# WS2812B_ARRAY.net
KiCad netlist of a schematic drawn in Altium Designer
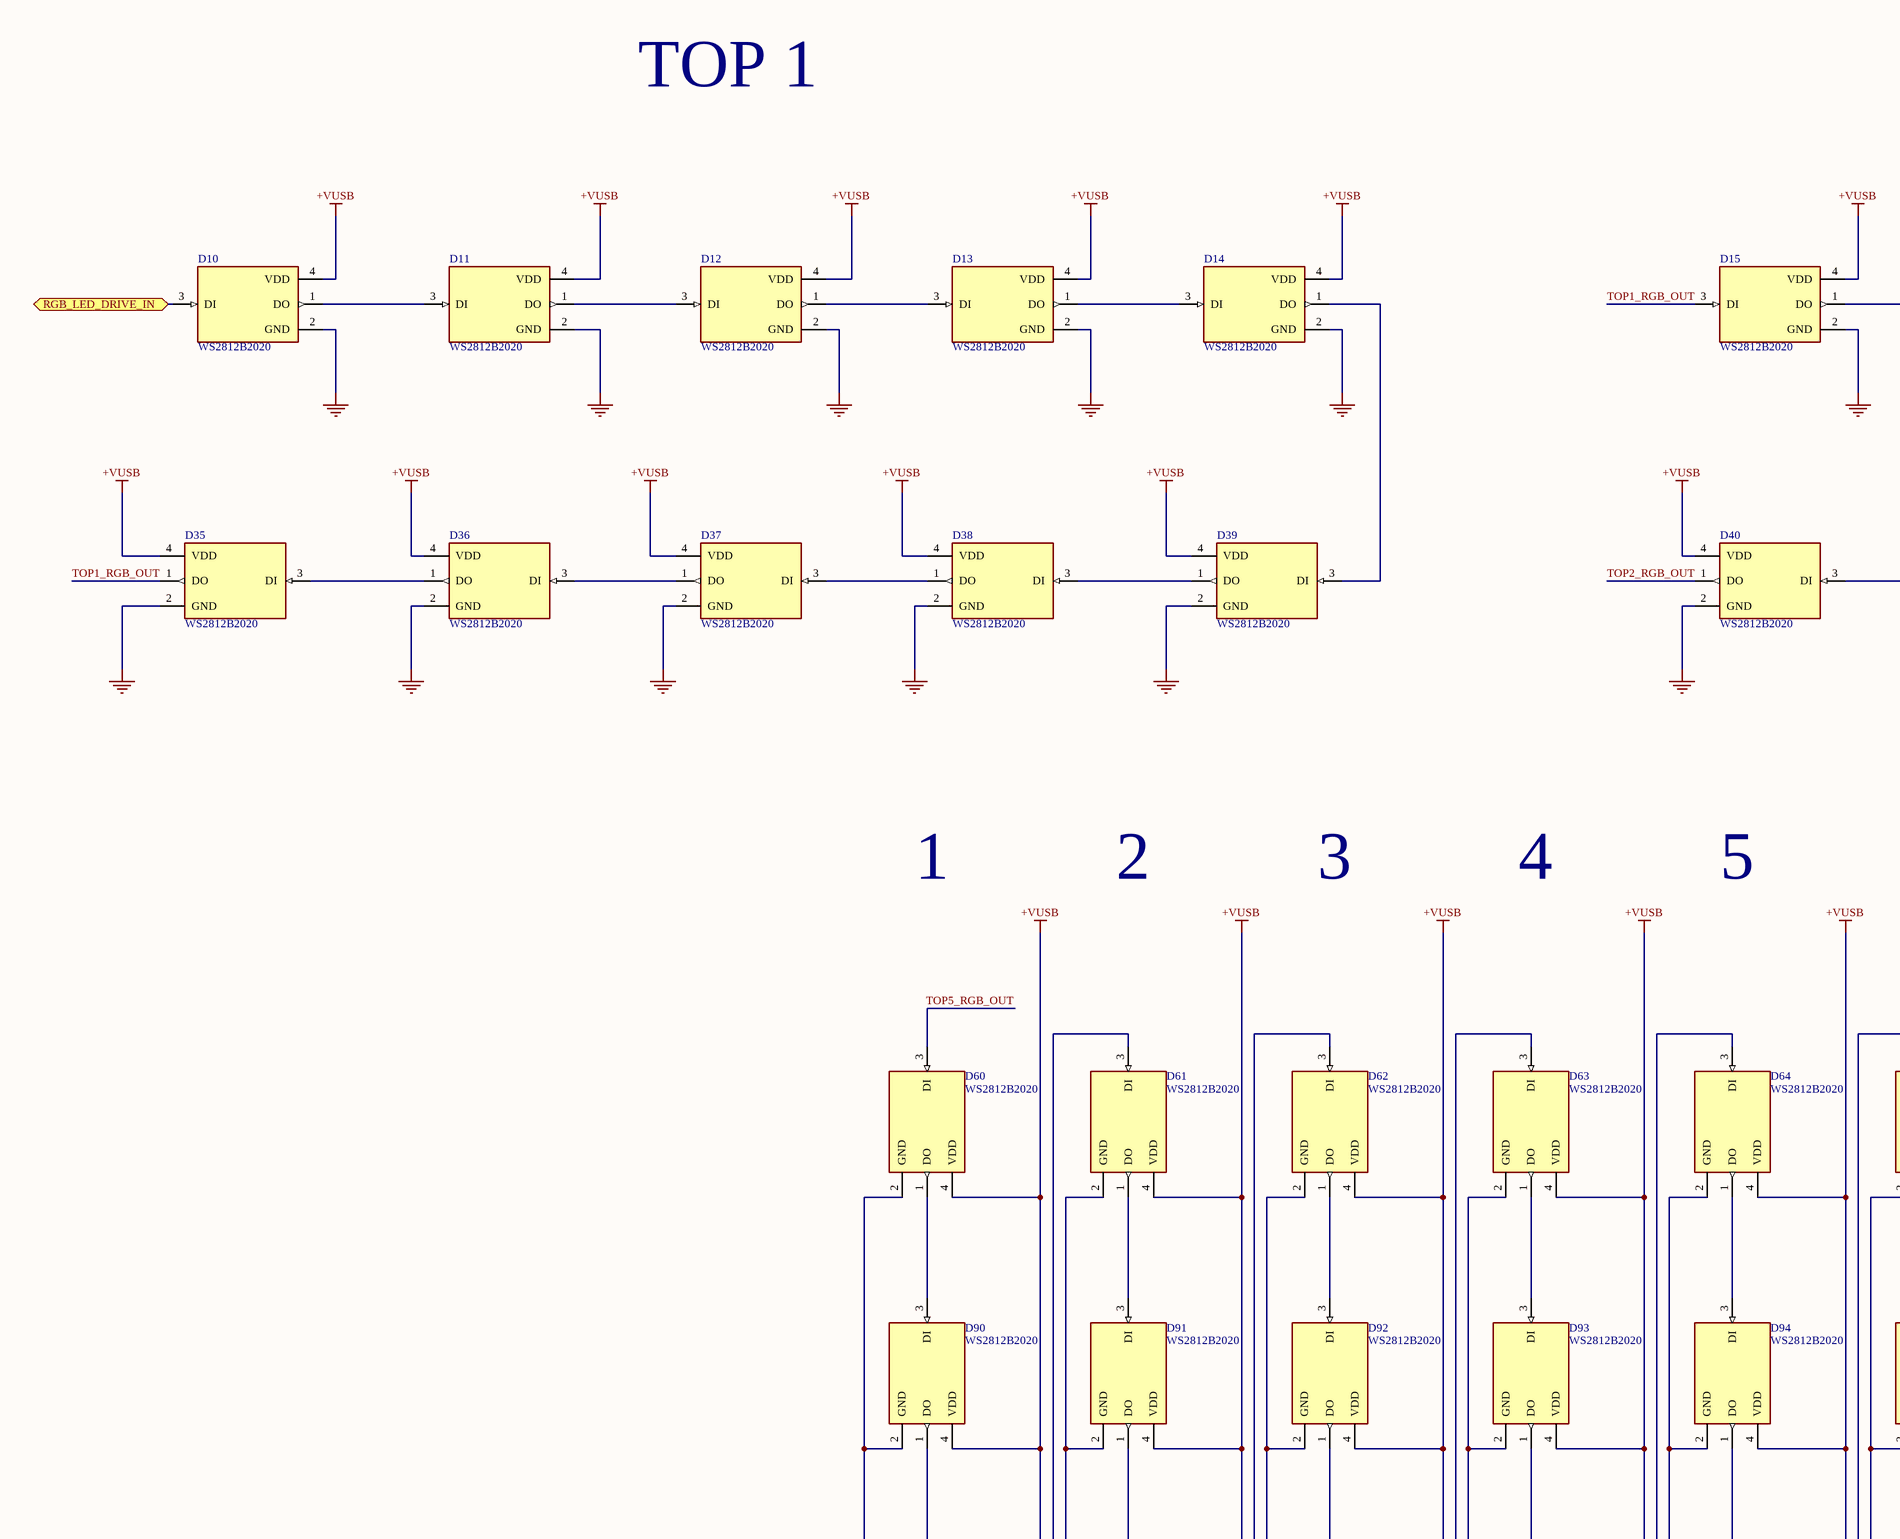
[diagram p0: WS2812B_ARRAY.SchDoc, top column 1 of 4]
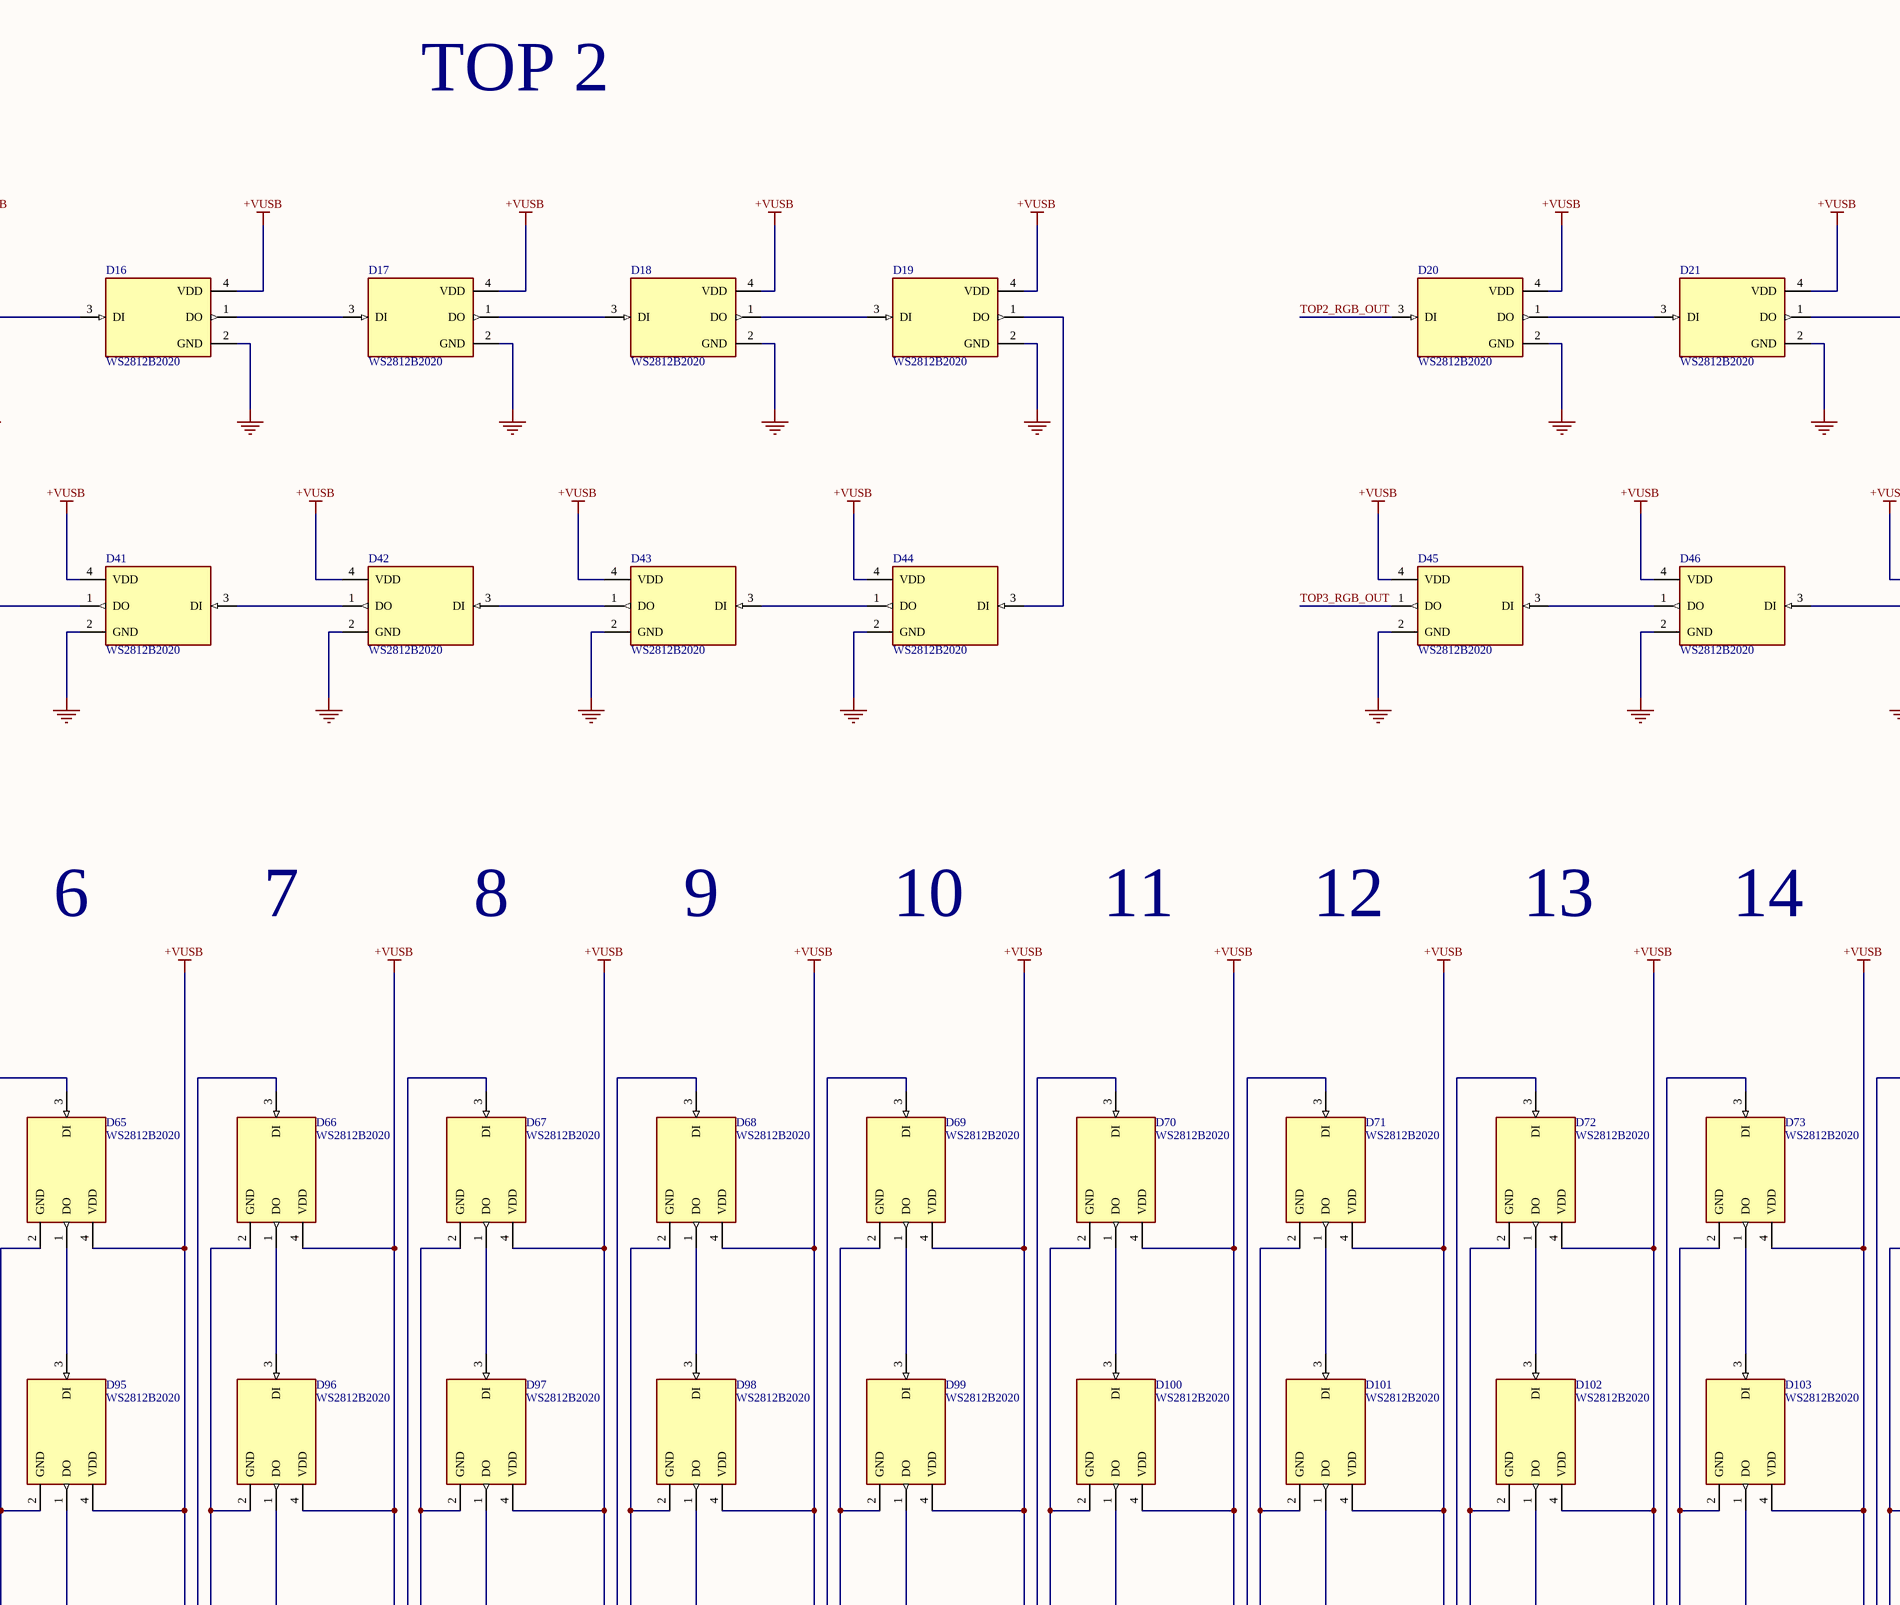
[diagram p1: WS2812B_ARRAY.SchDoc, top column 2 of 4]
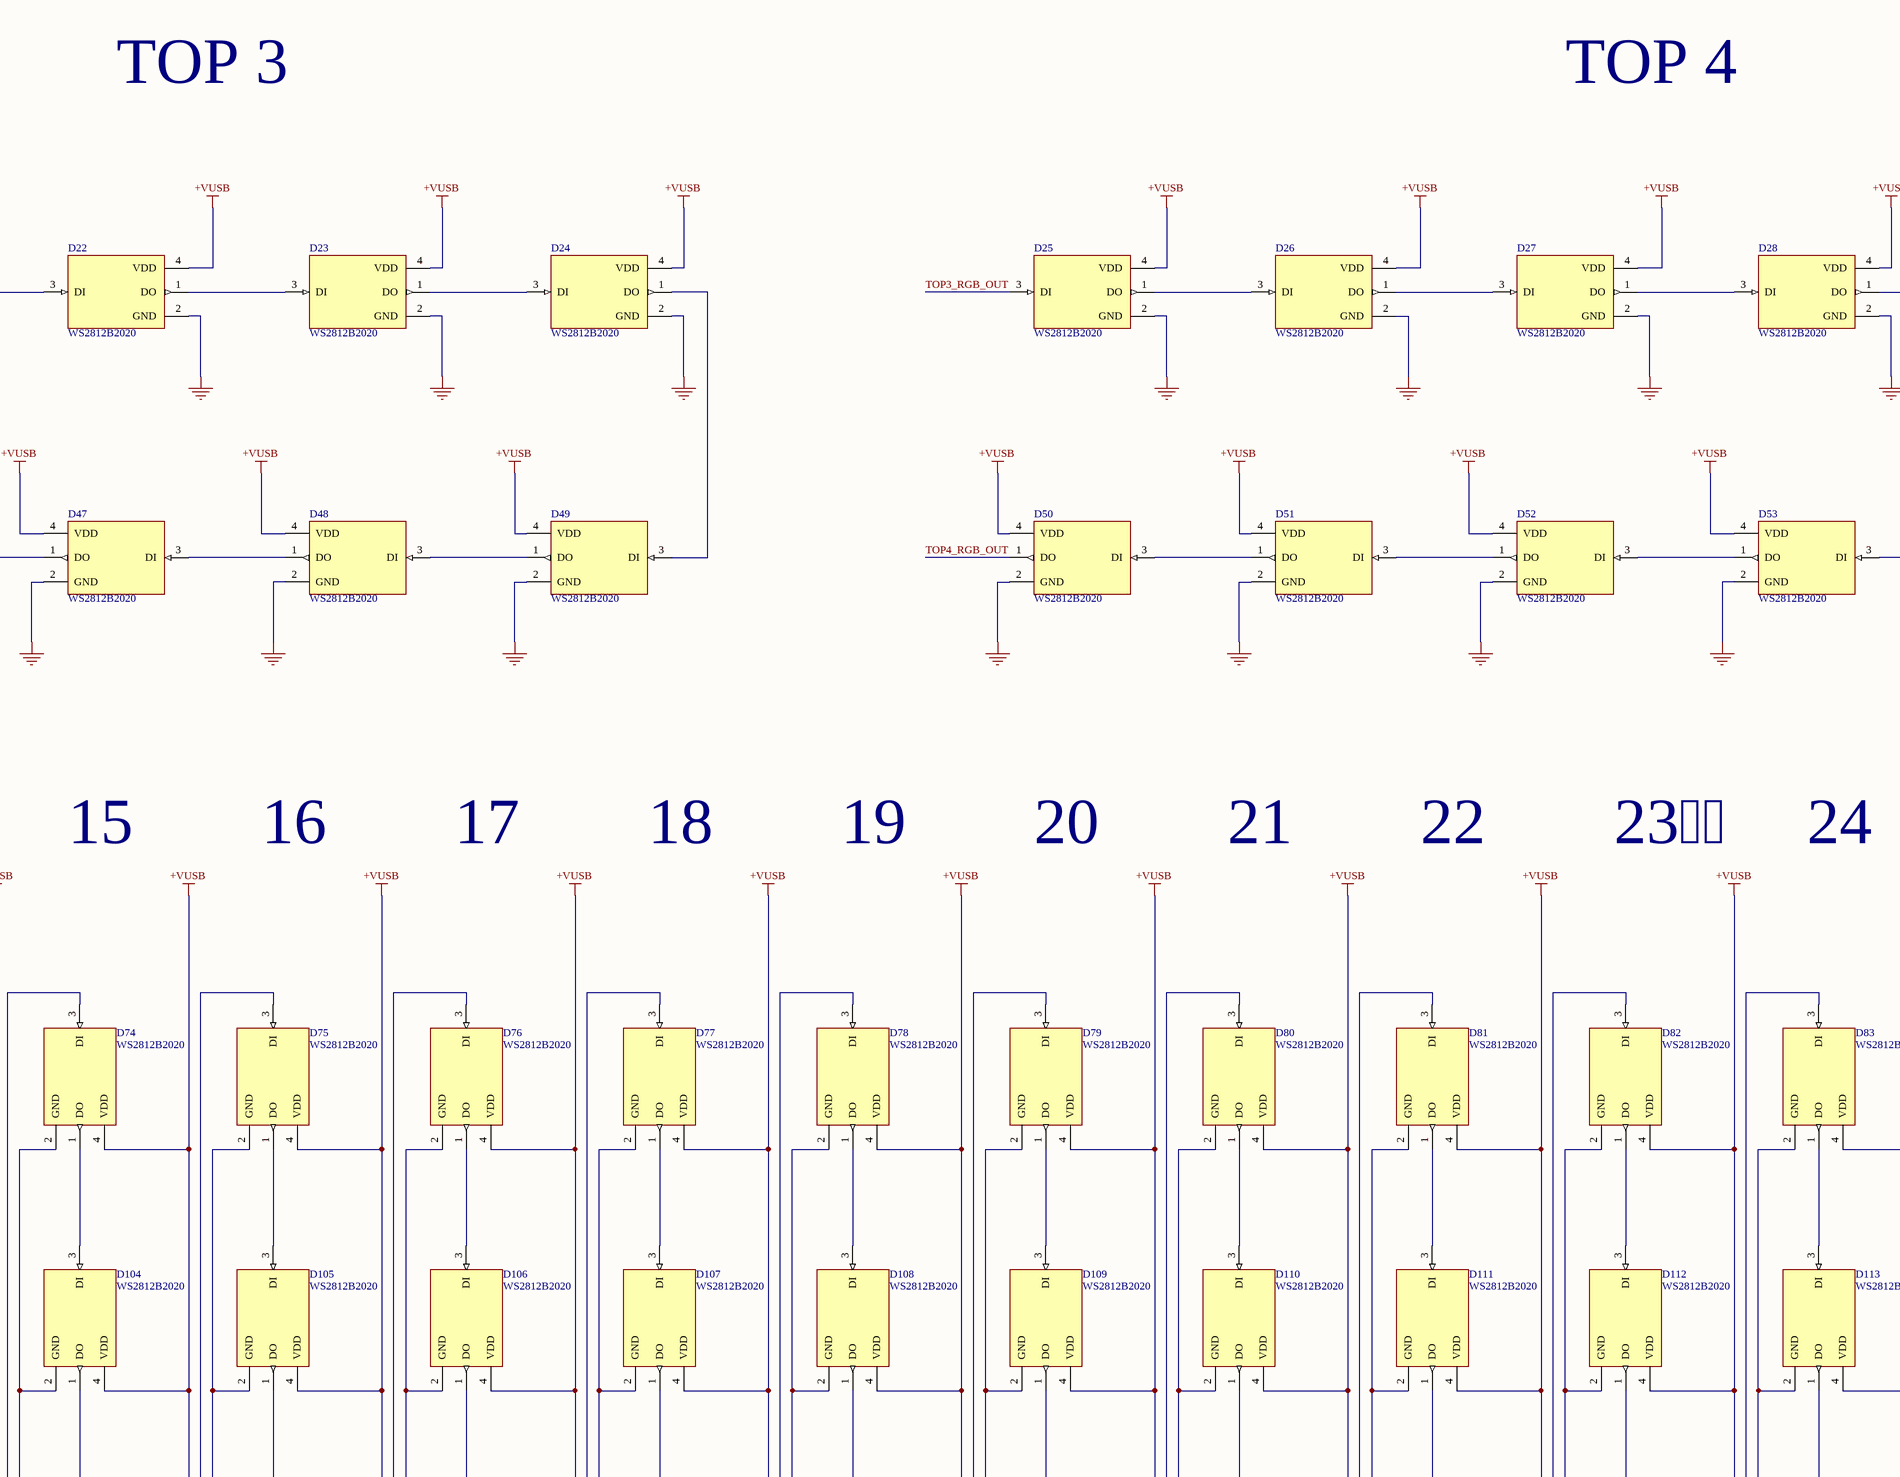
[diagram p2: WS2812B_ARRAY.SchDoc, top column 3 of 4]
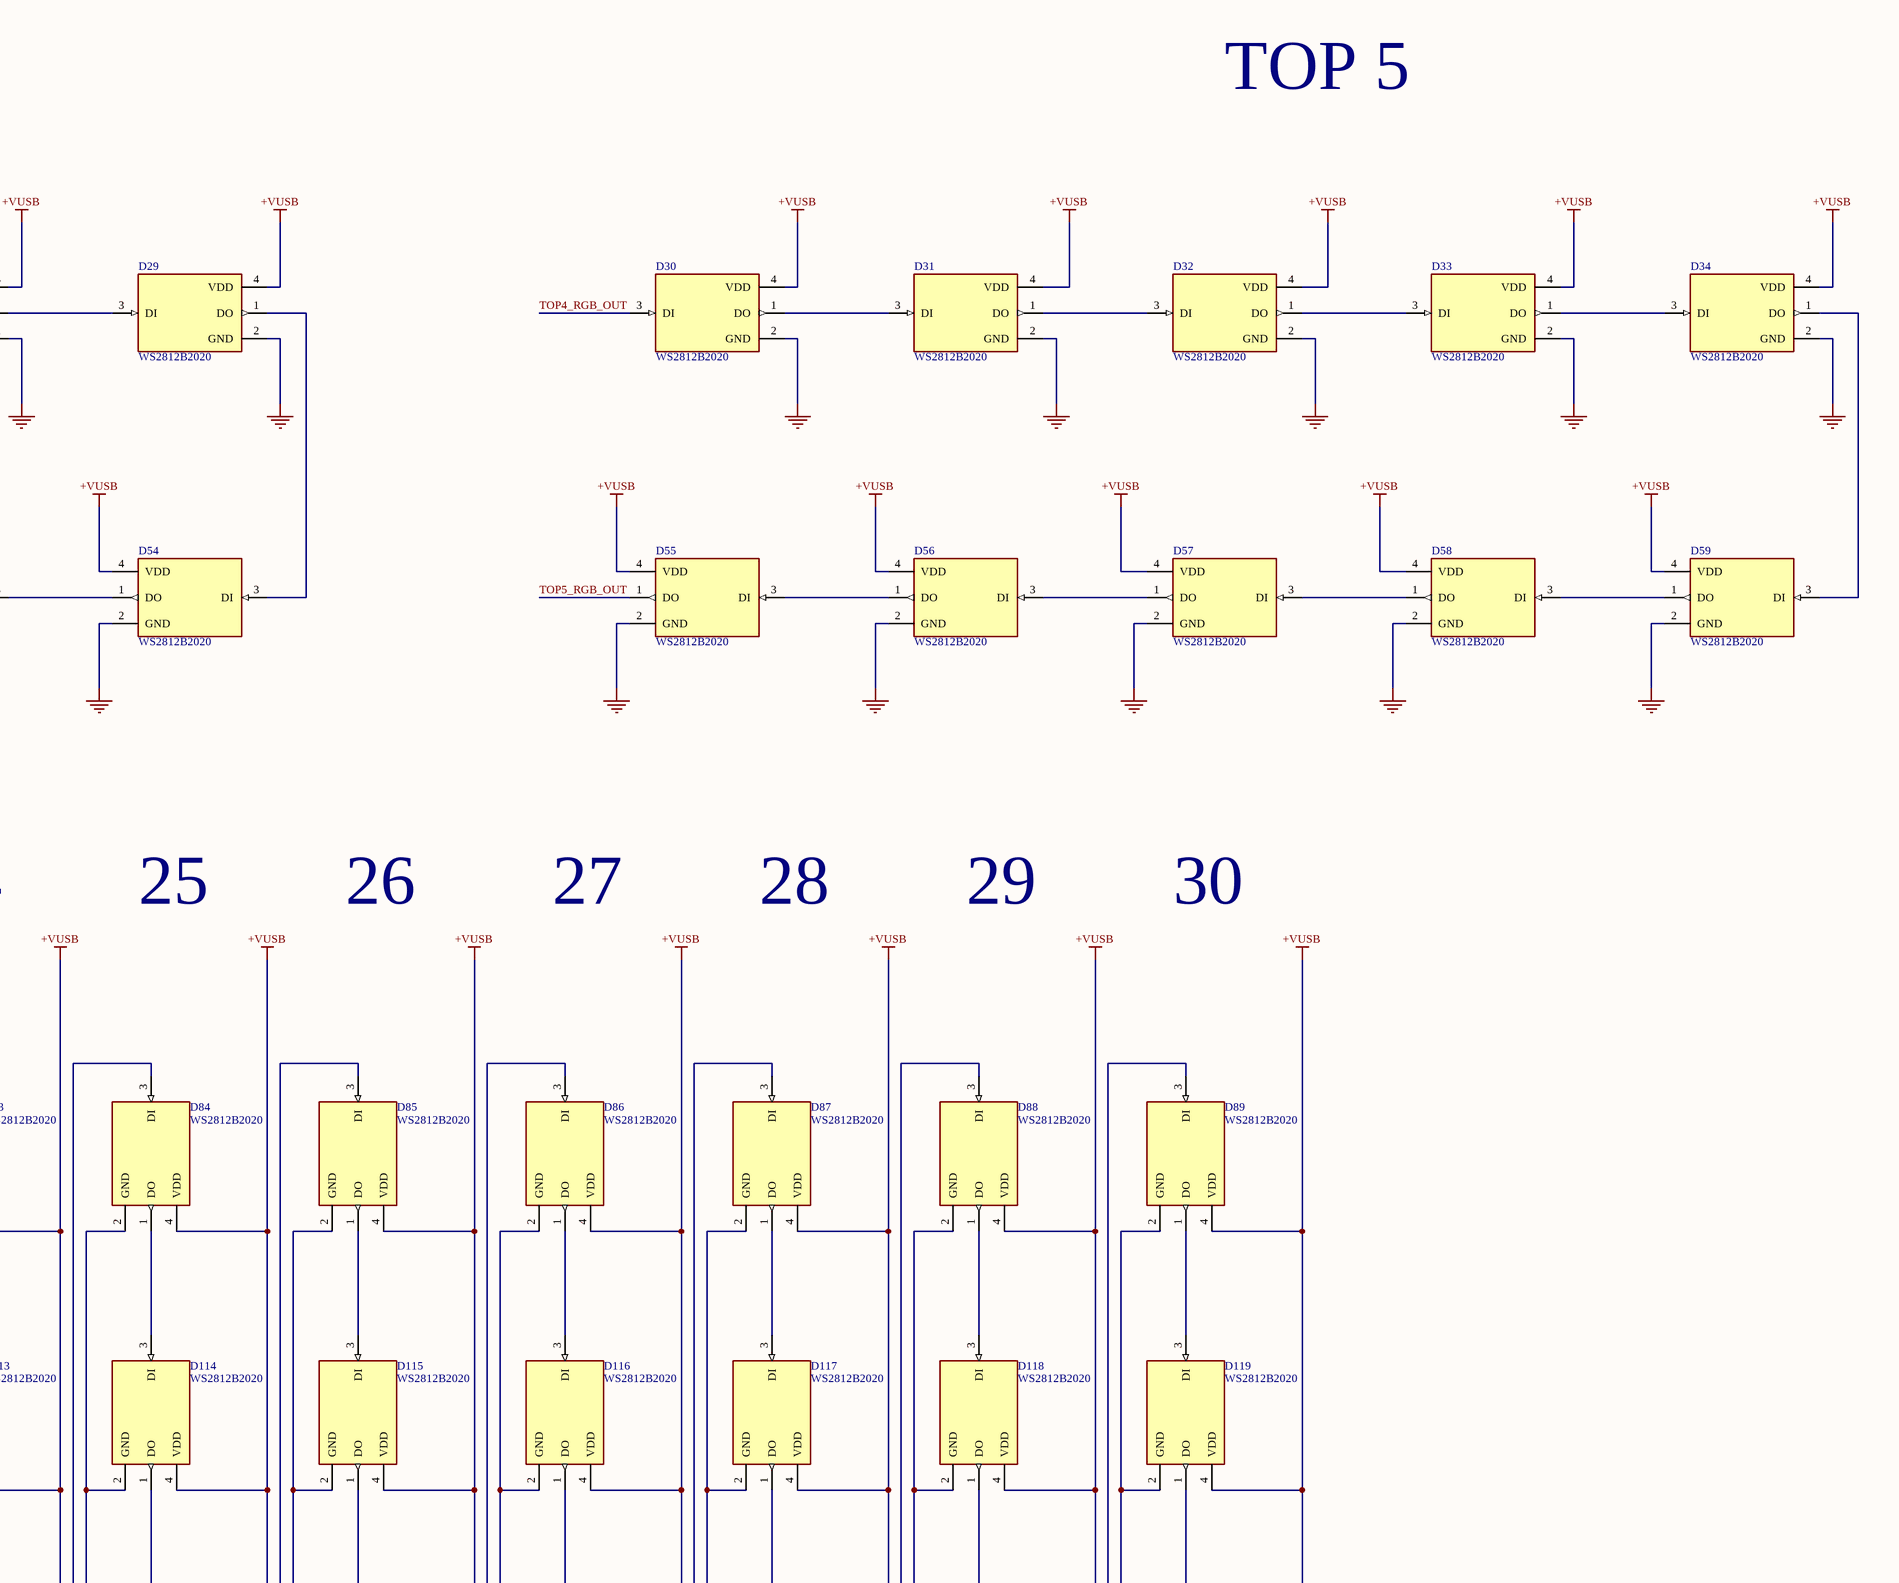
[diagram p3: WS2812B_ARRAY.SchDoc, top column 4 of 4]
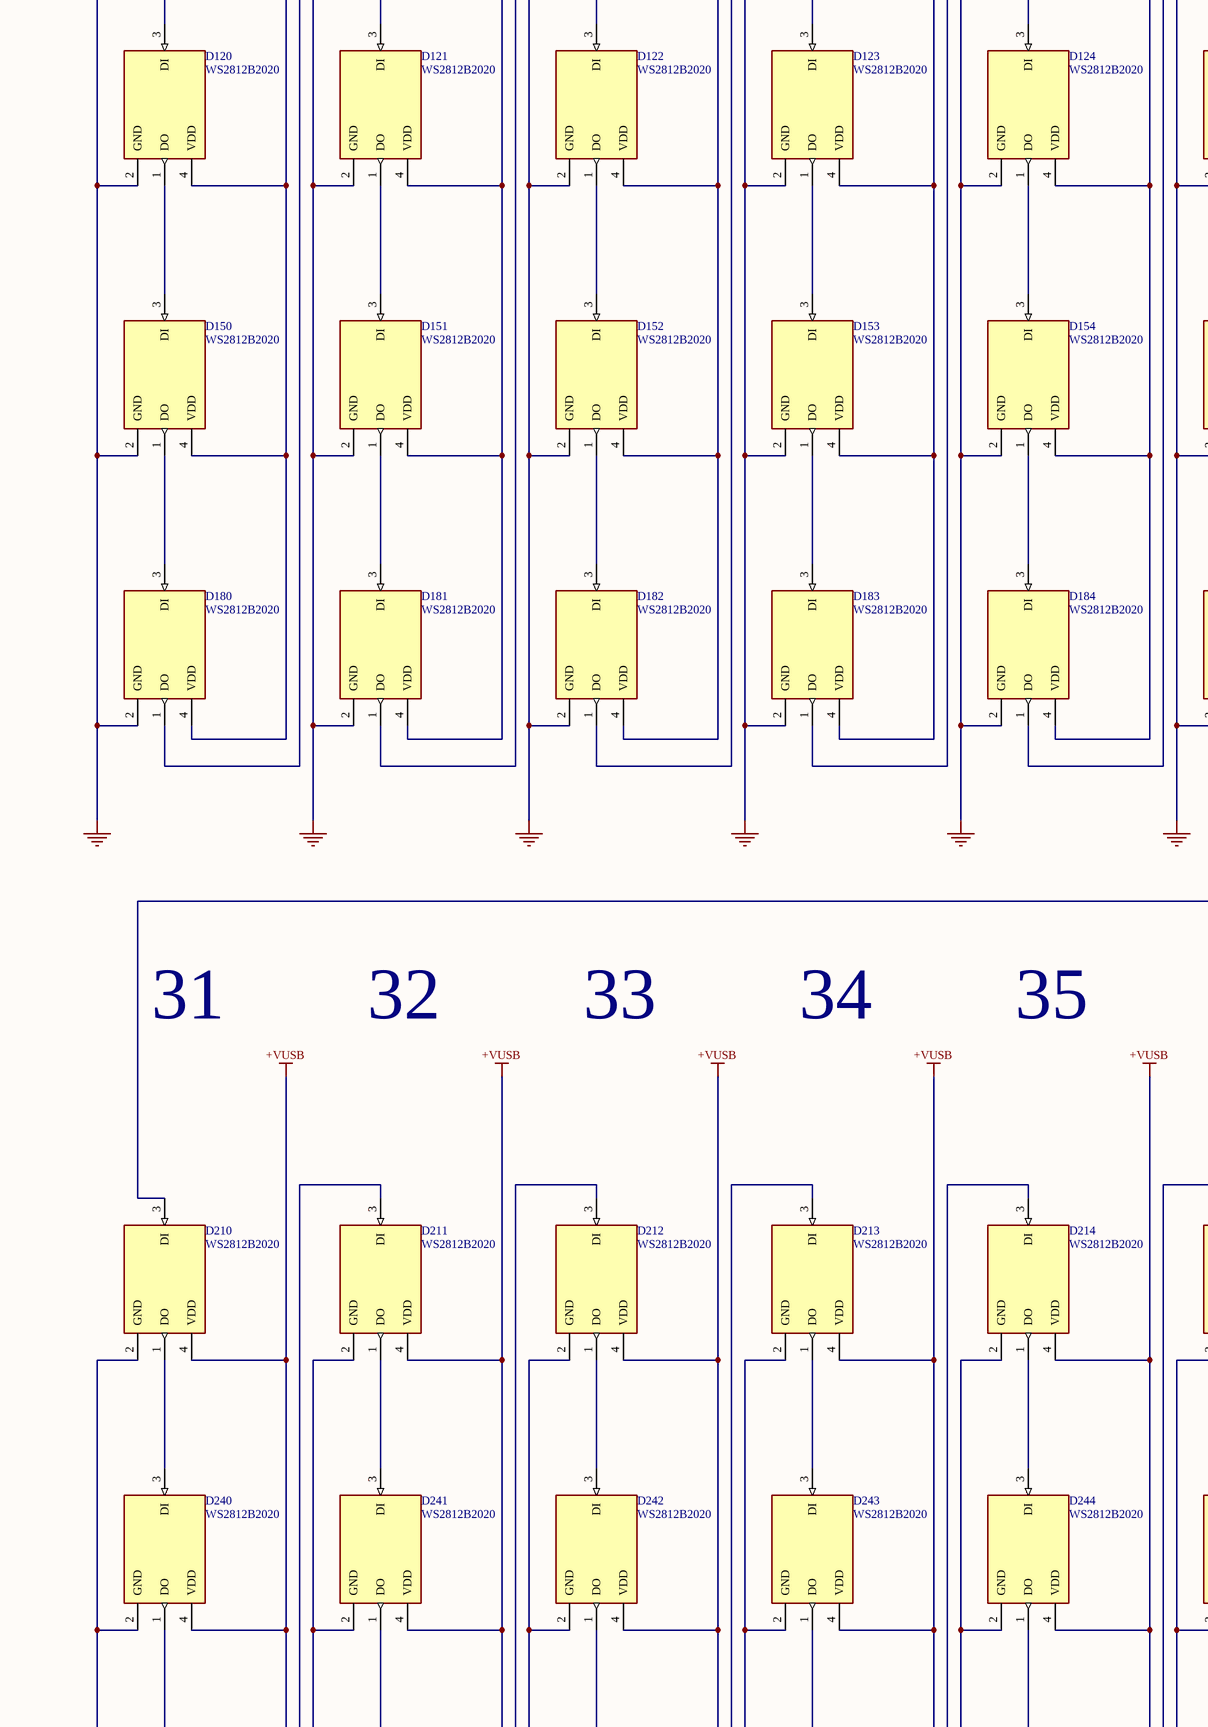
[diagram p4: WS2812B_ARRAY.SchDoc, centre column 1 of 4]
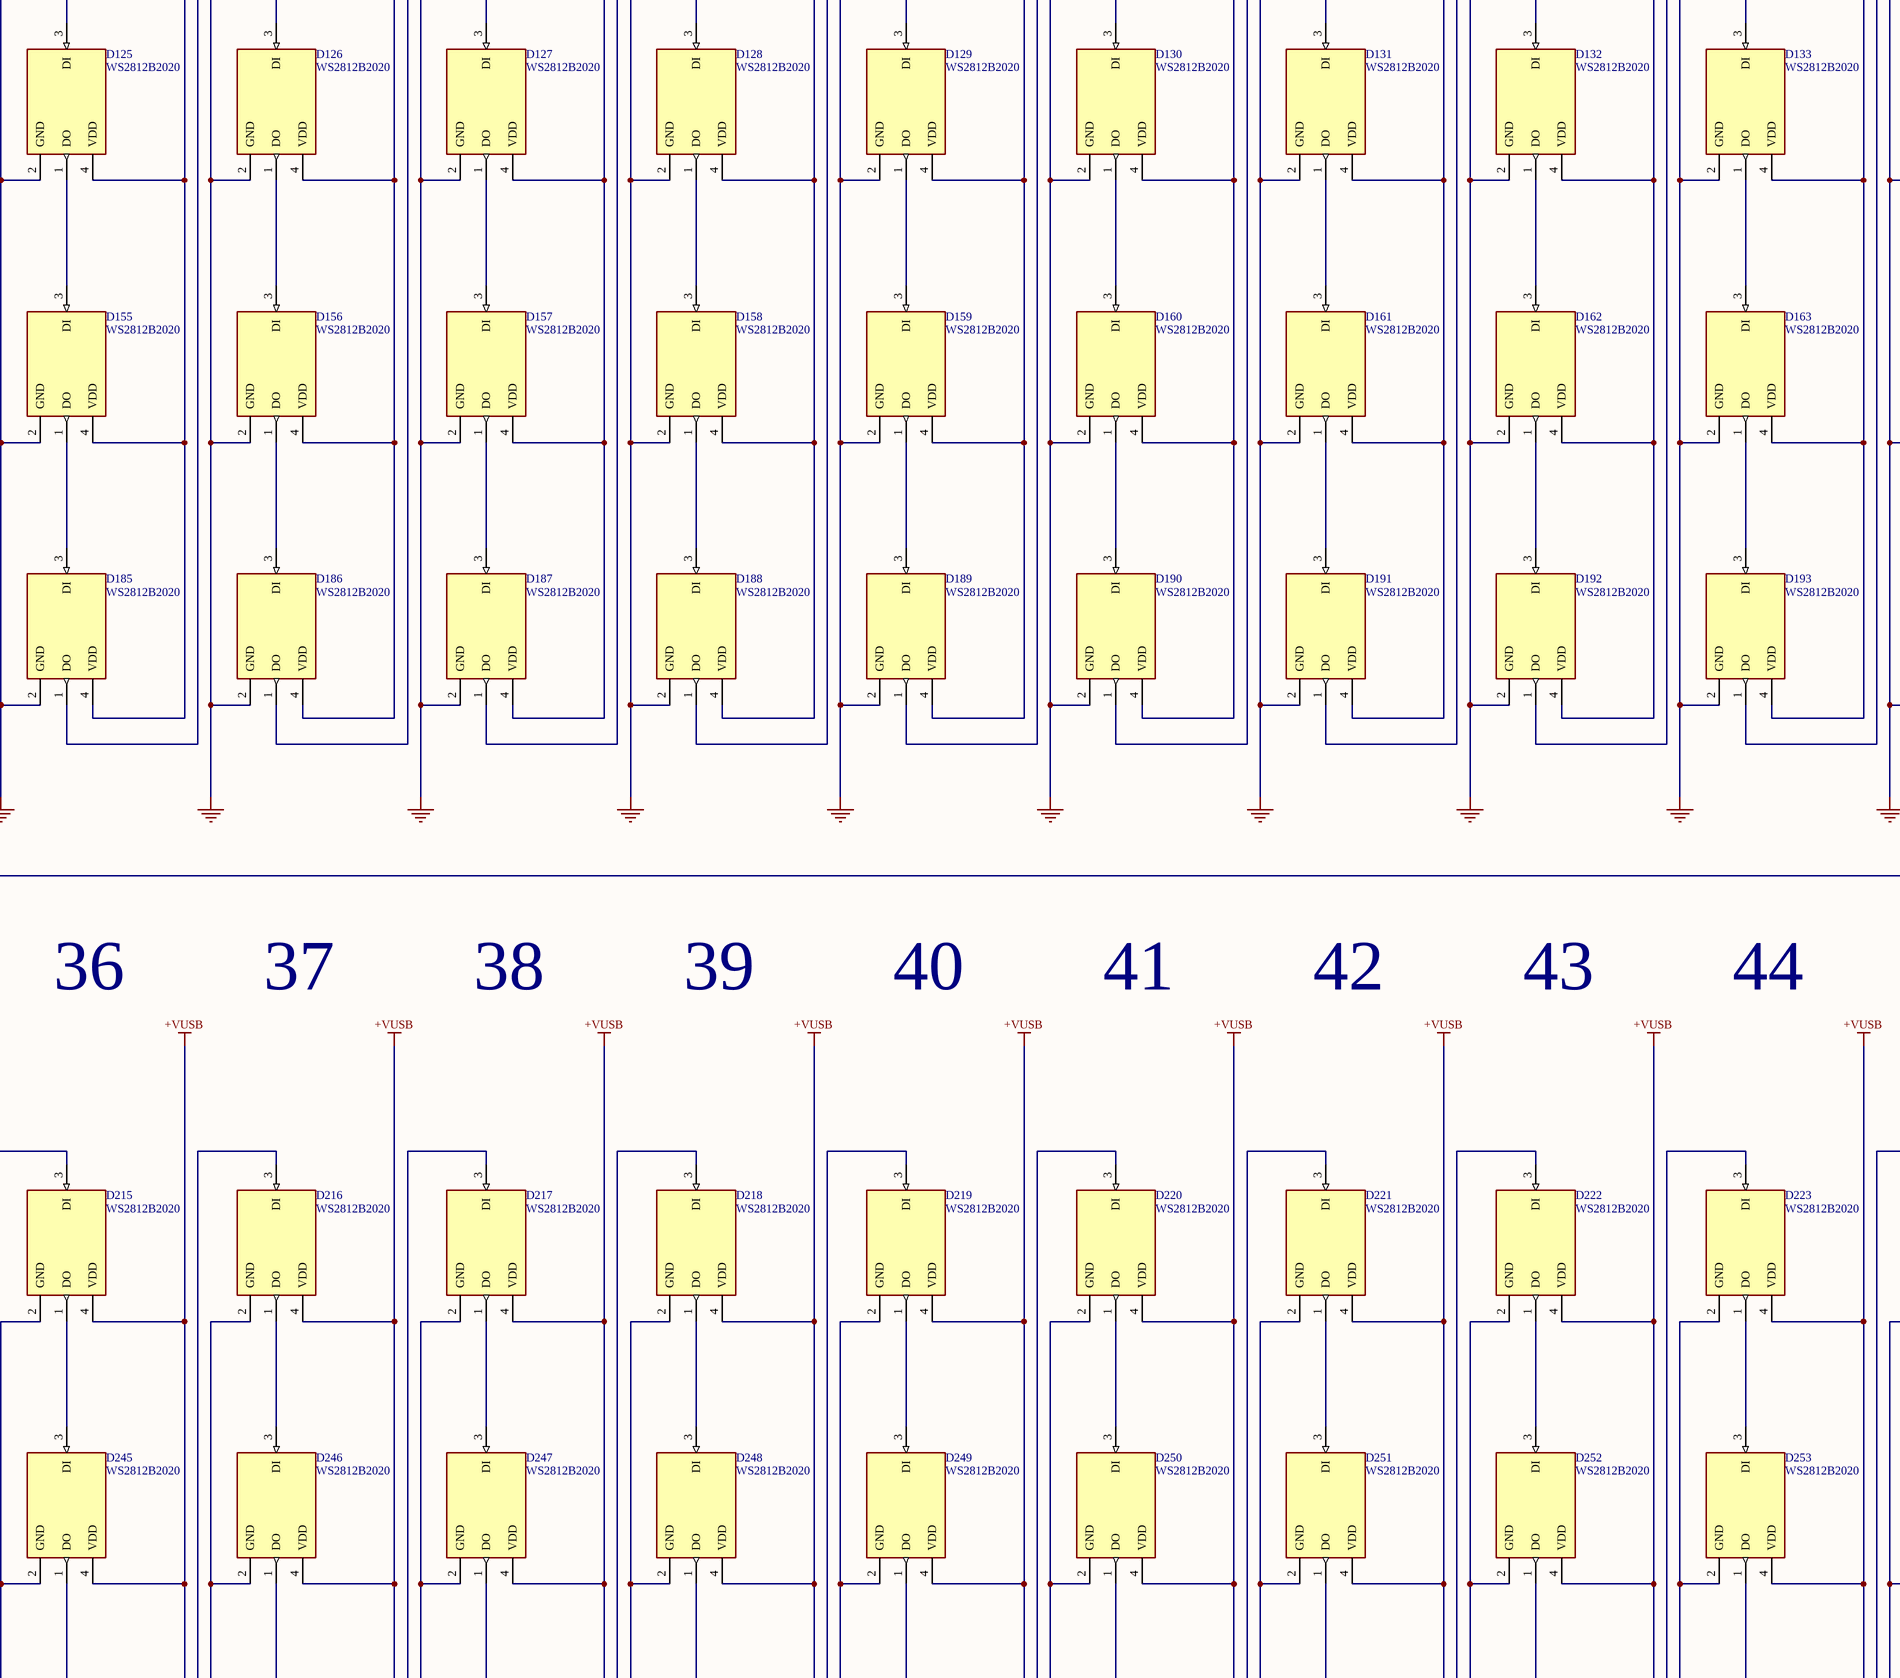
[diagram p5: WS2812B_ARRAY.SchDoc, centre column 2 of 4]
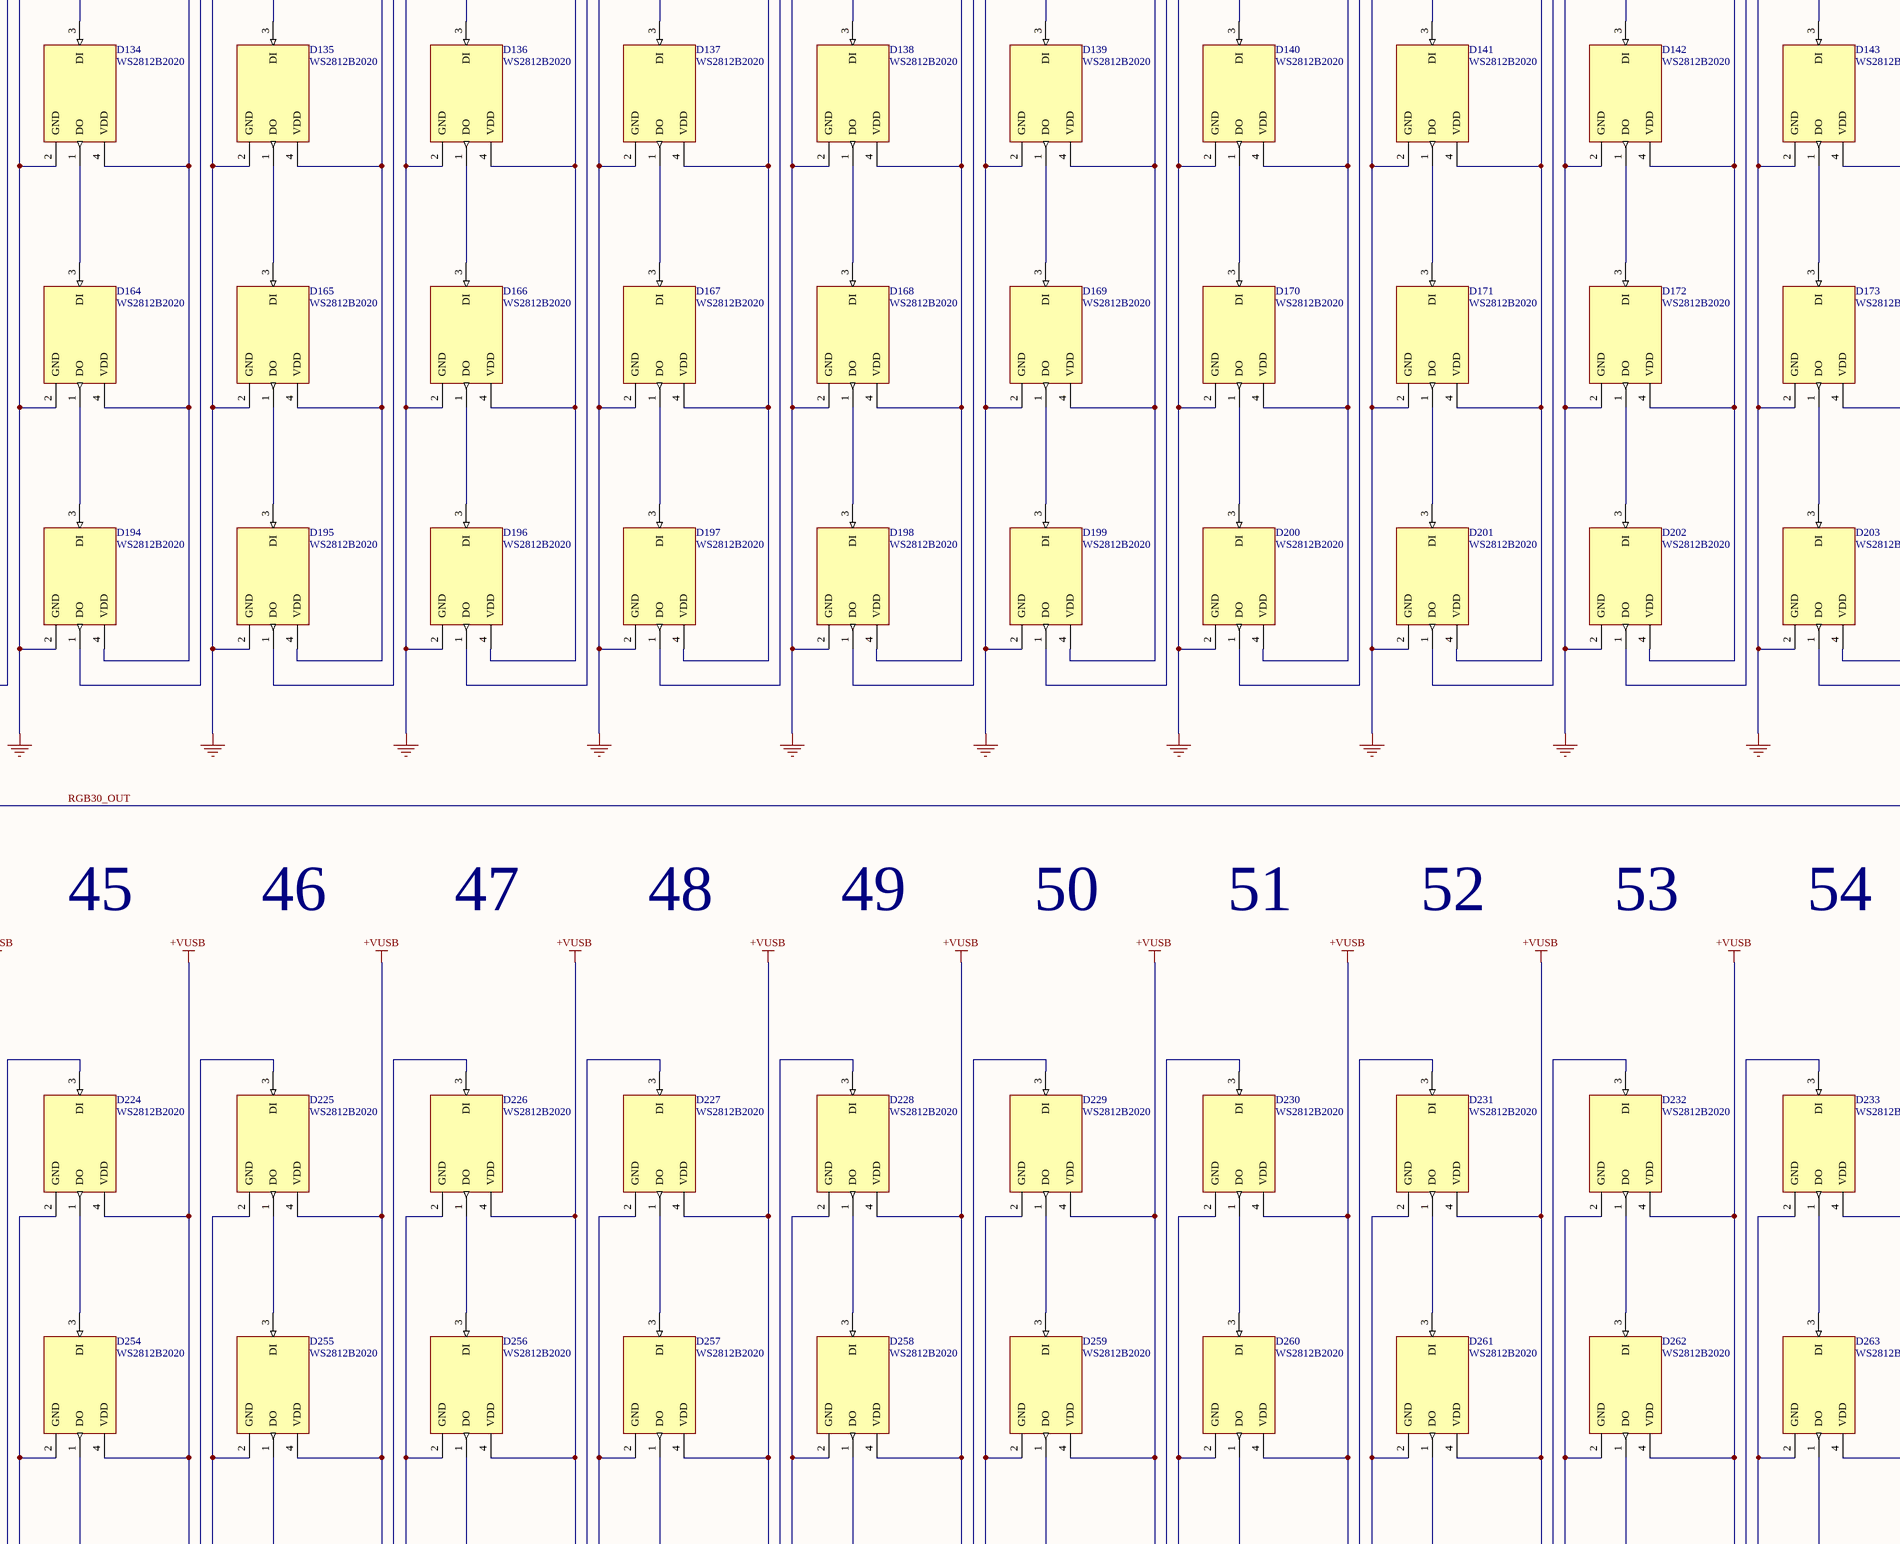
[diagram p6: WS2812B_ARRAY.SchDoc, centre column 3 of 4]
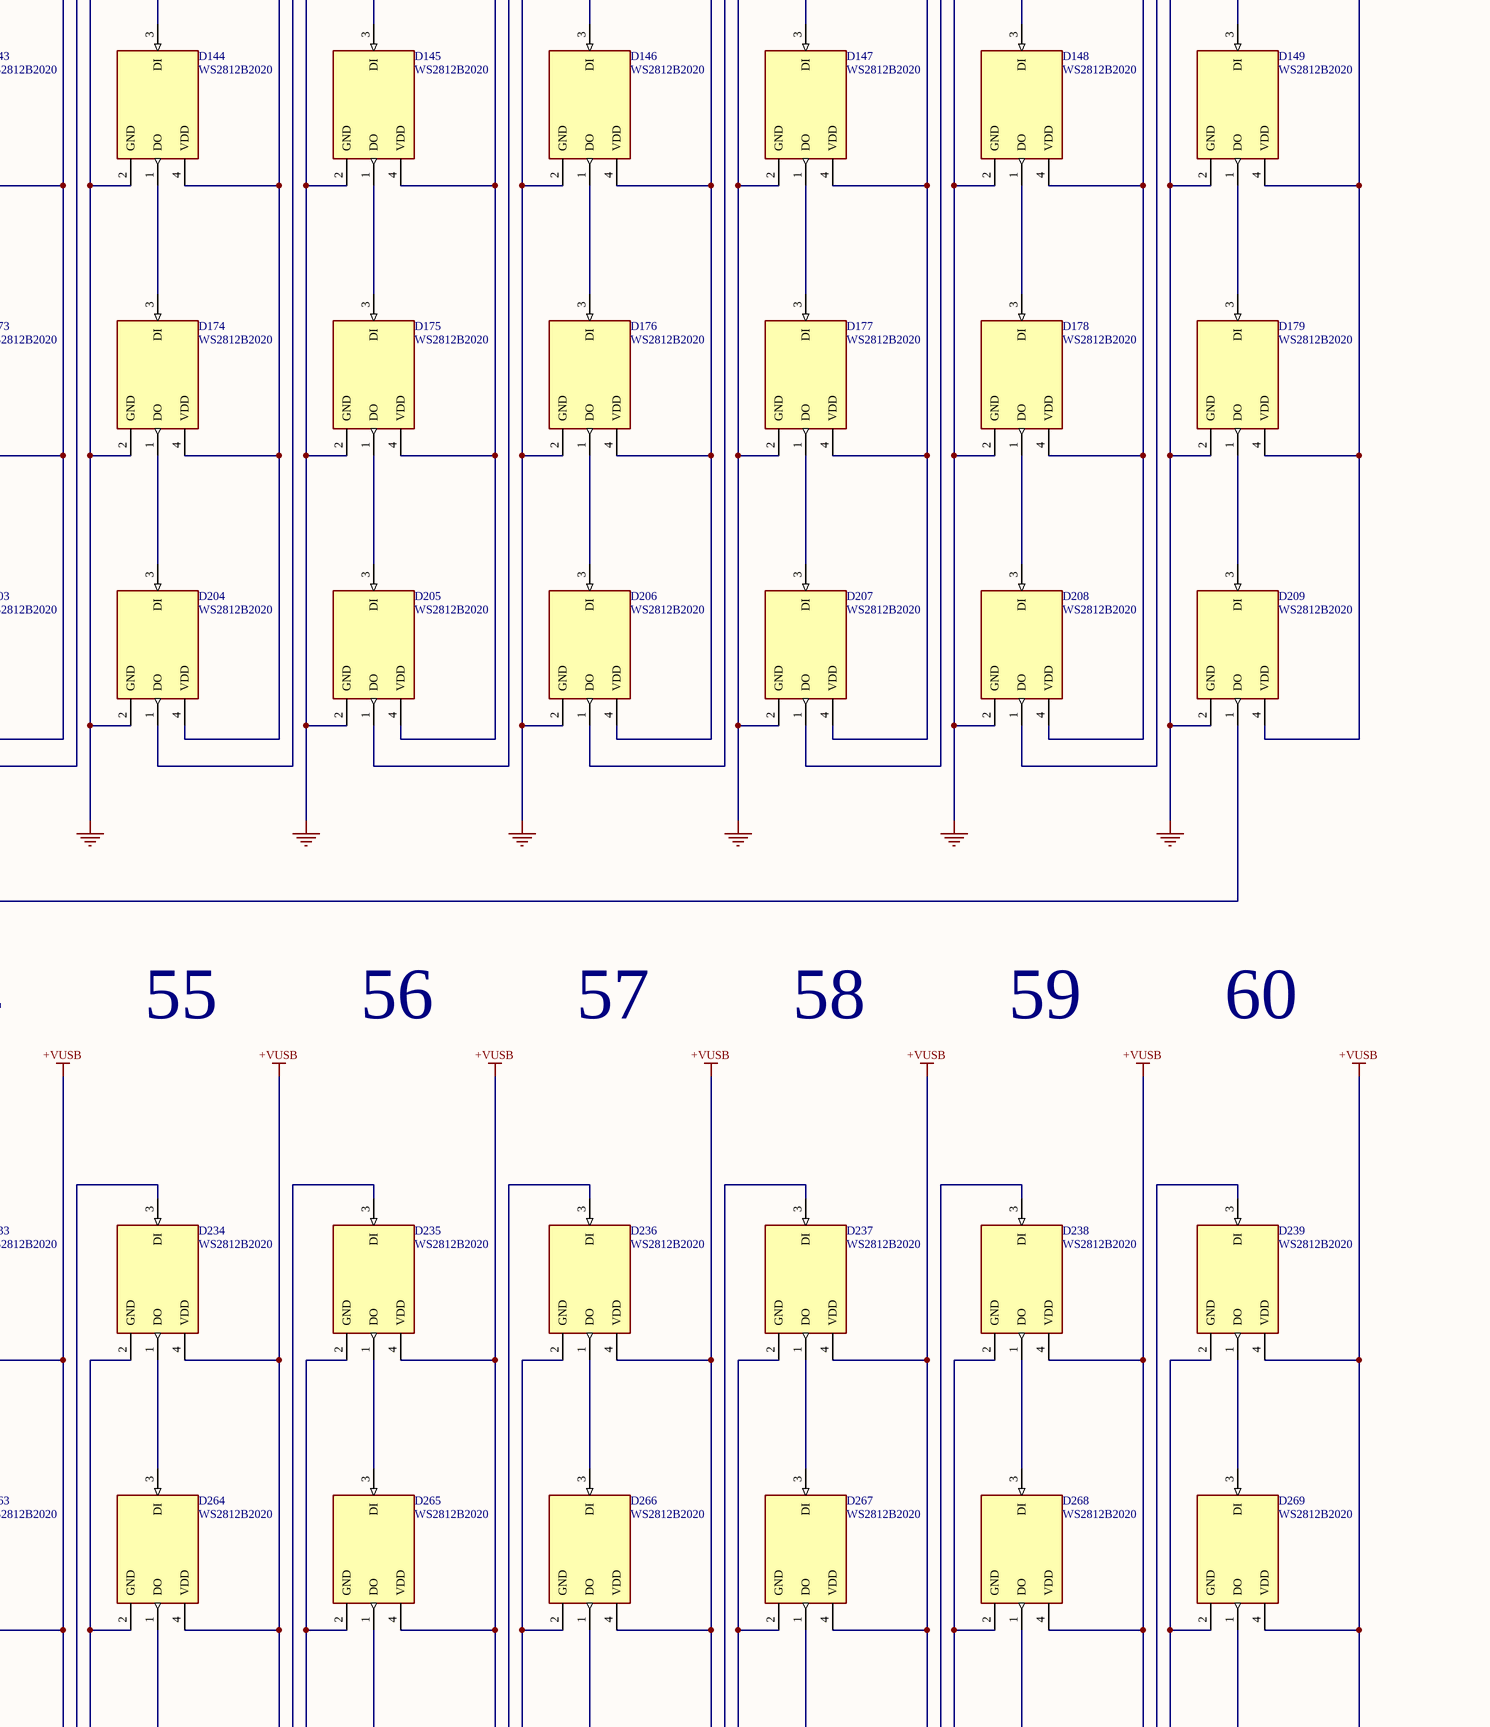
[diagram p7: WS2812B_ARRAY.SchDoc, centre column 4 of 4]
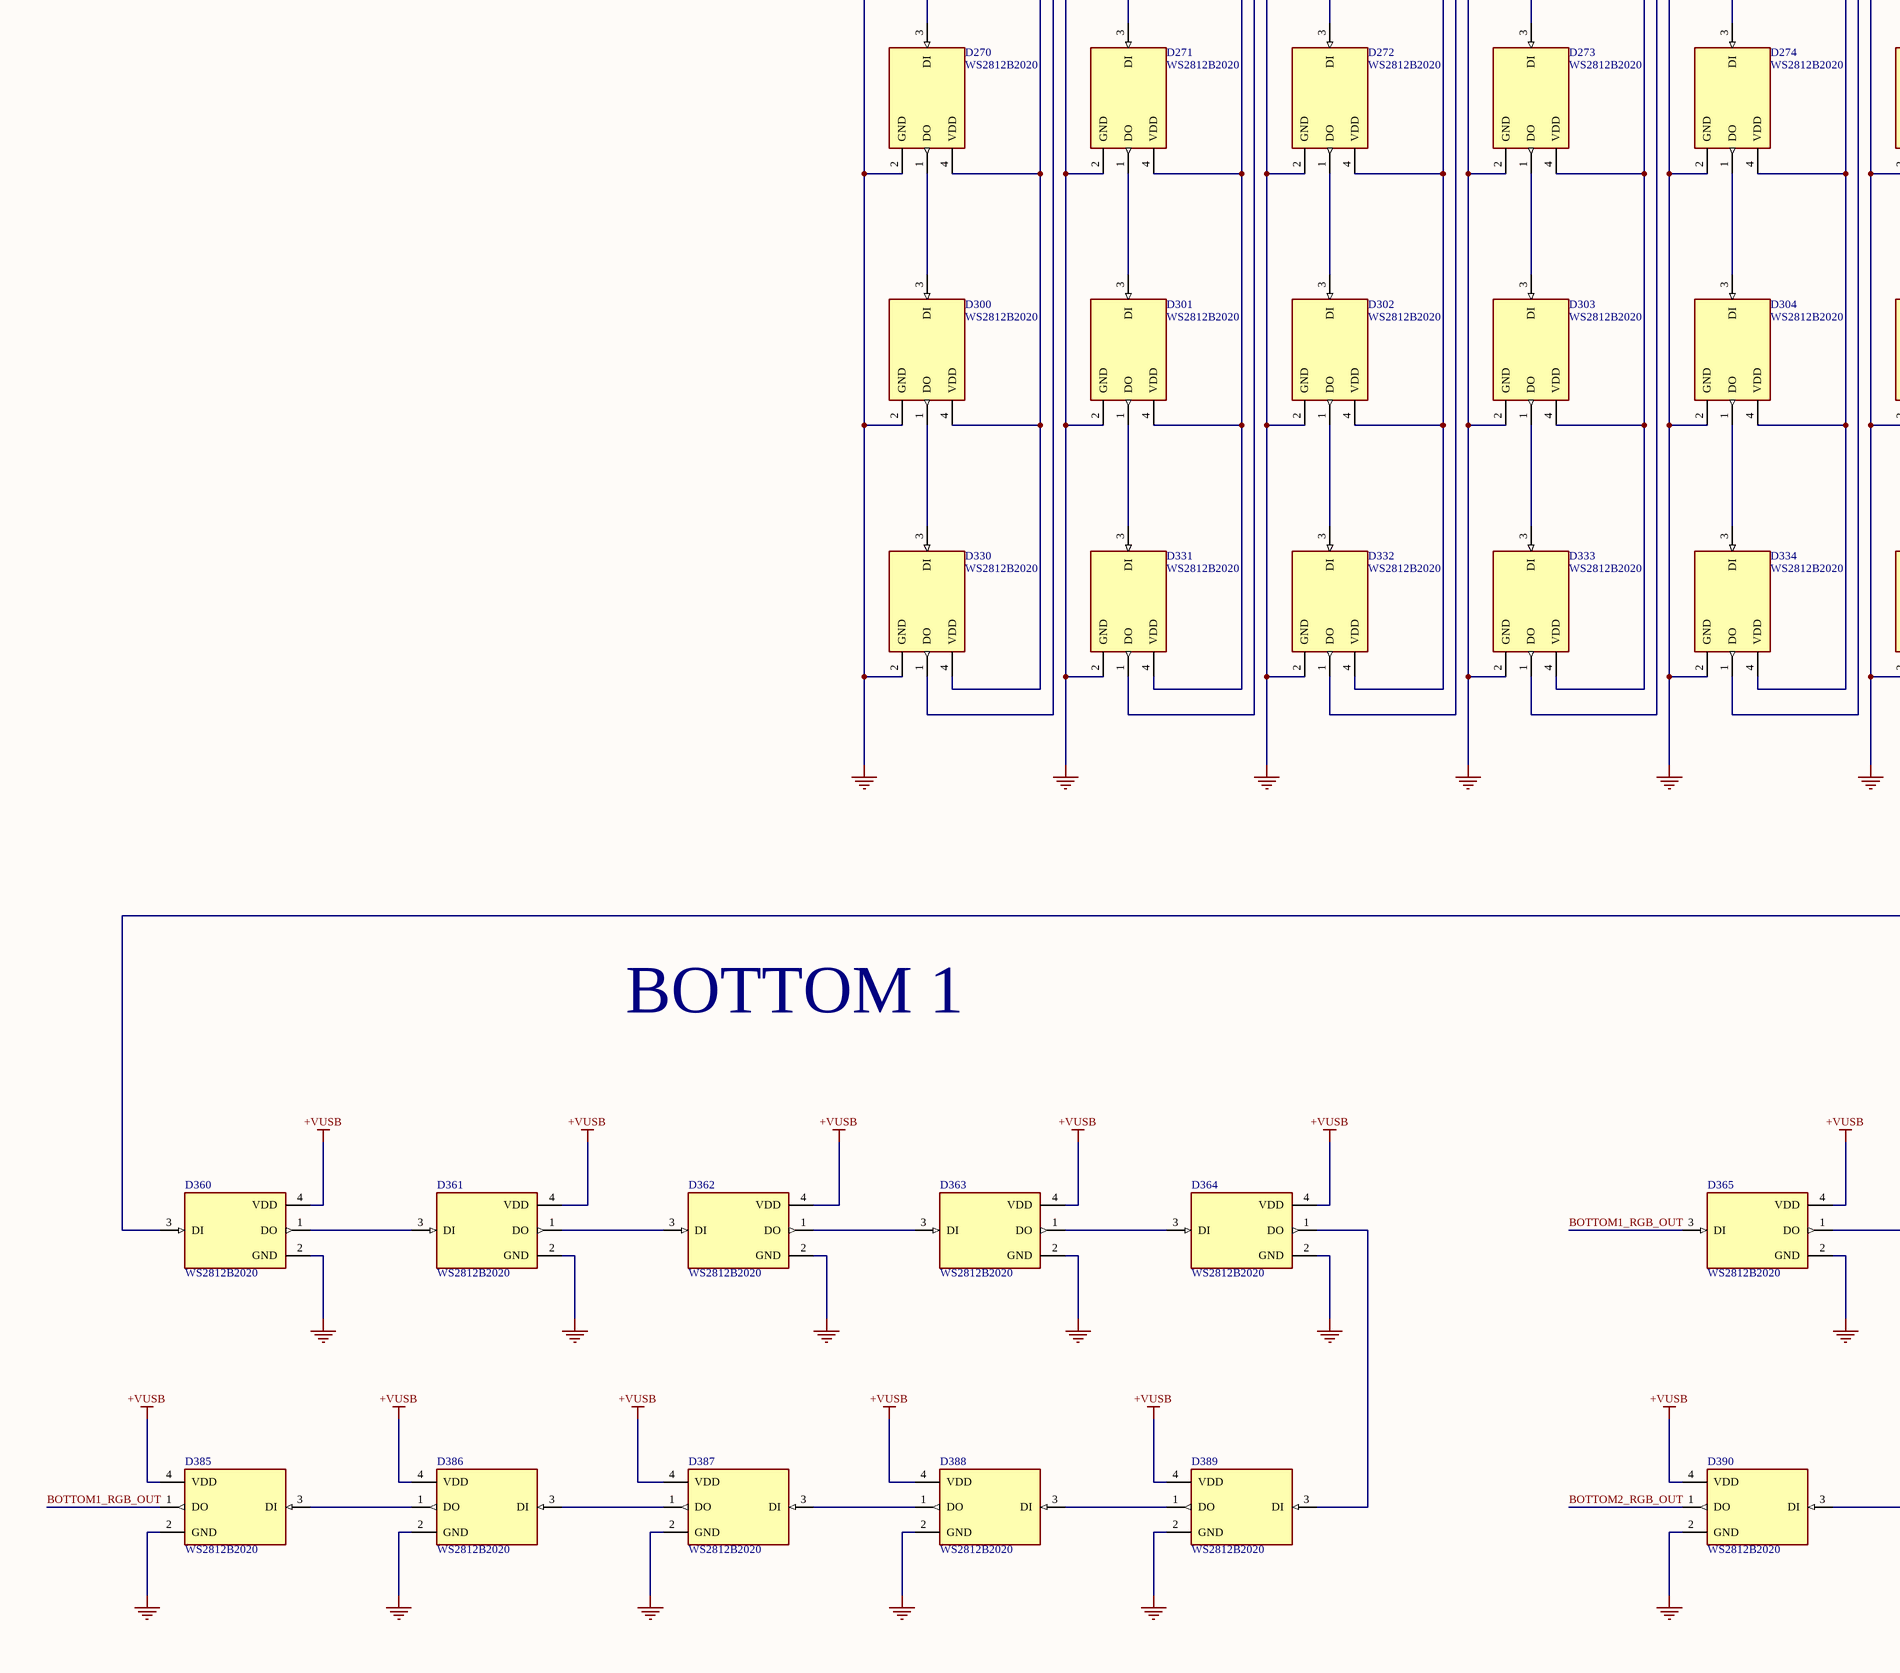
[diagram p8: WS2812B_ARRAY.SchDoc, bottom column 1 of 4]
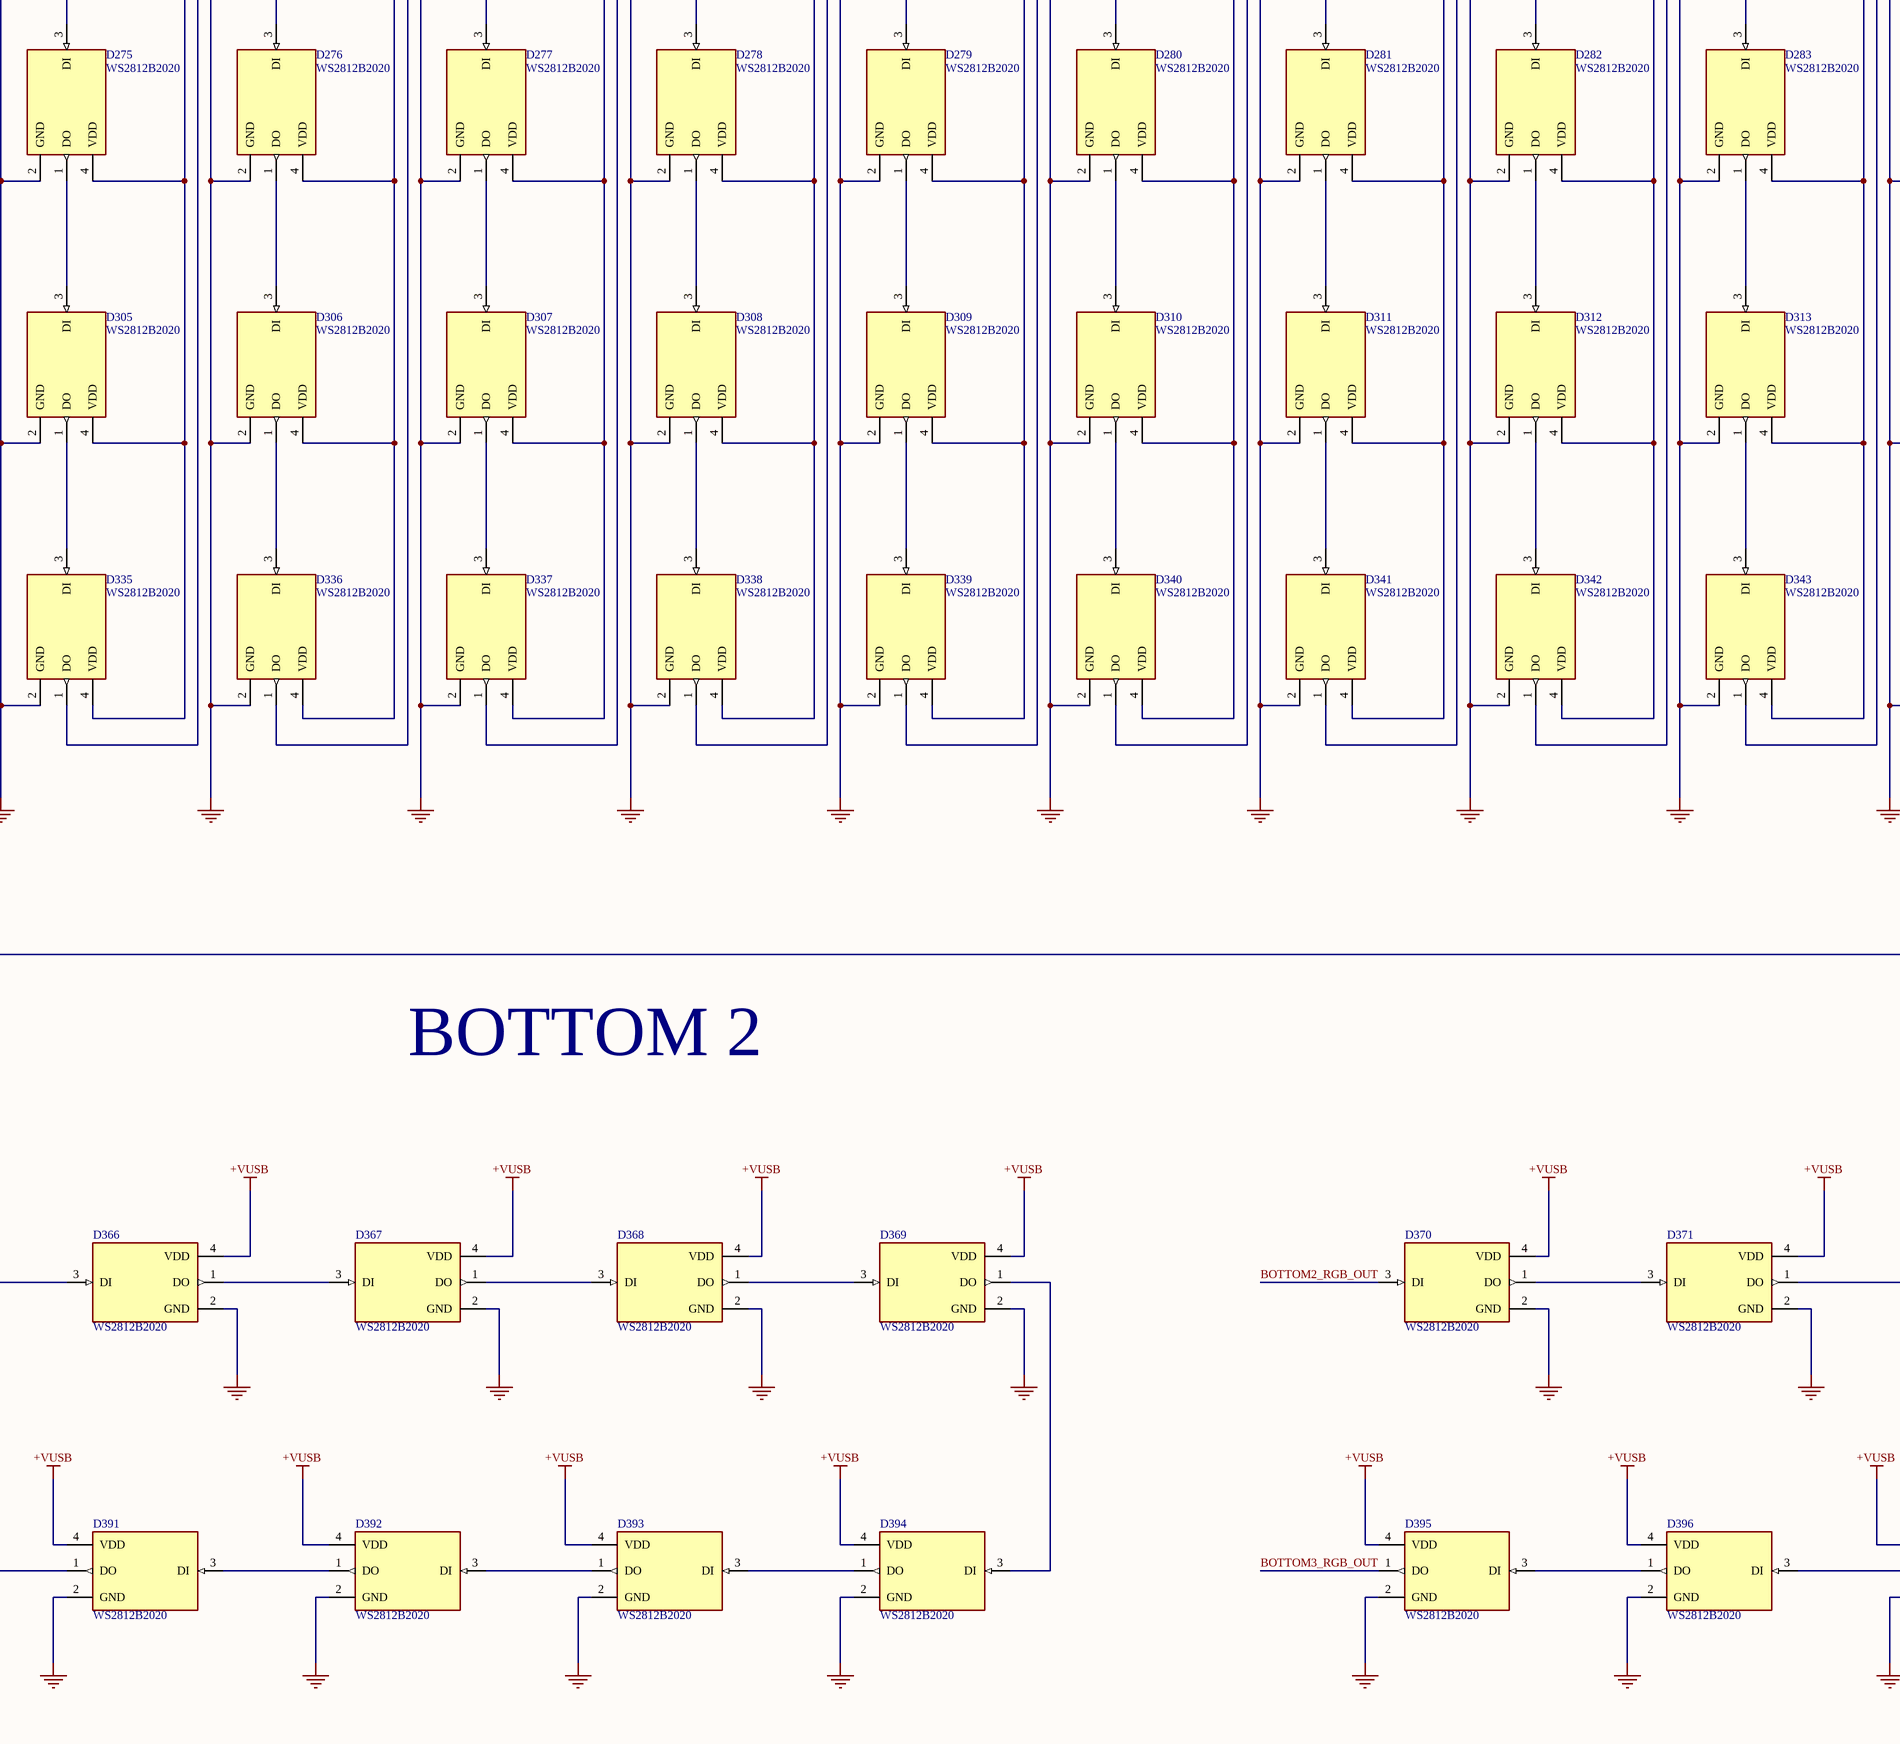
[diagram p9: WS2812B_ARRAY.SchDoc, bottom column 2 of 4]
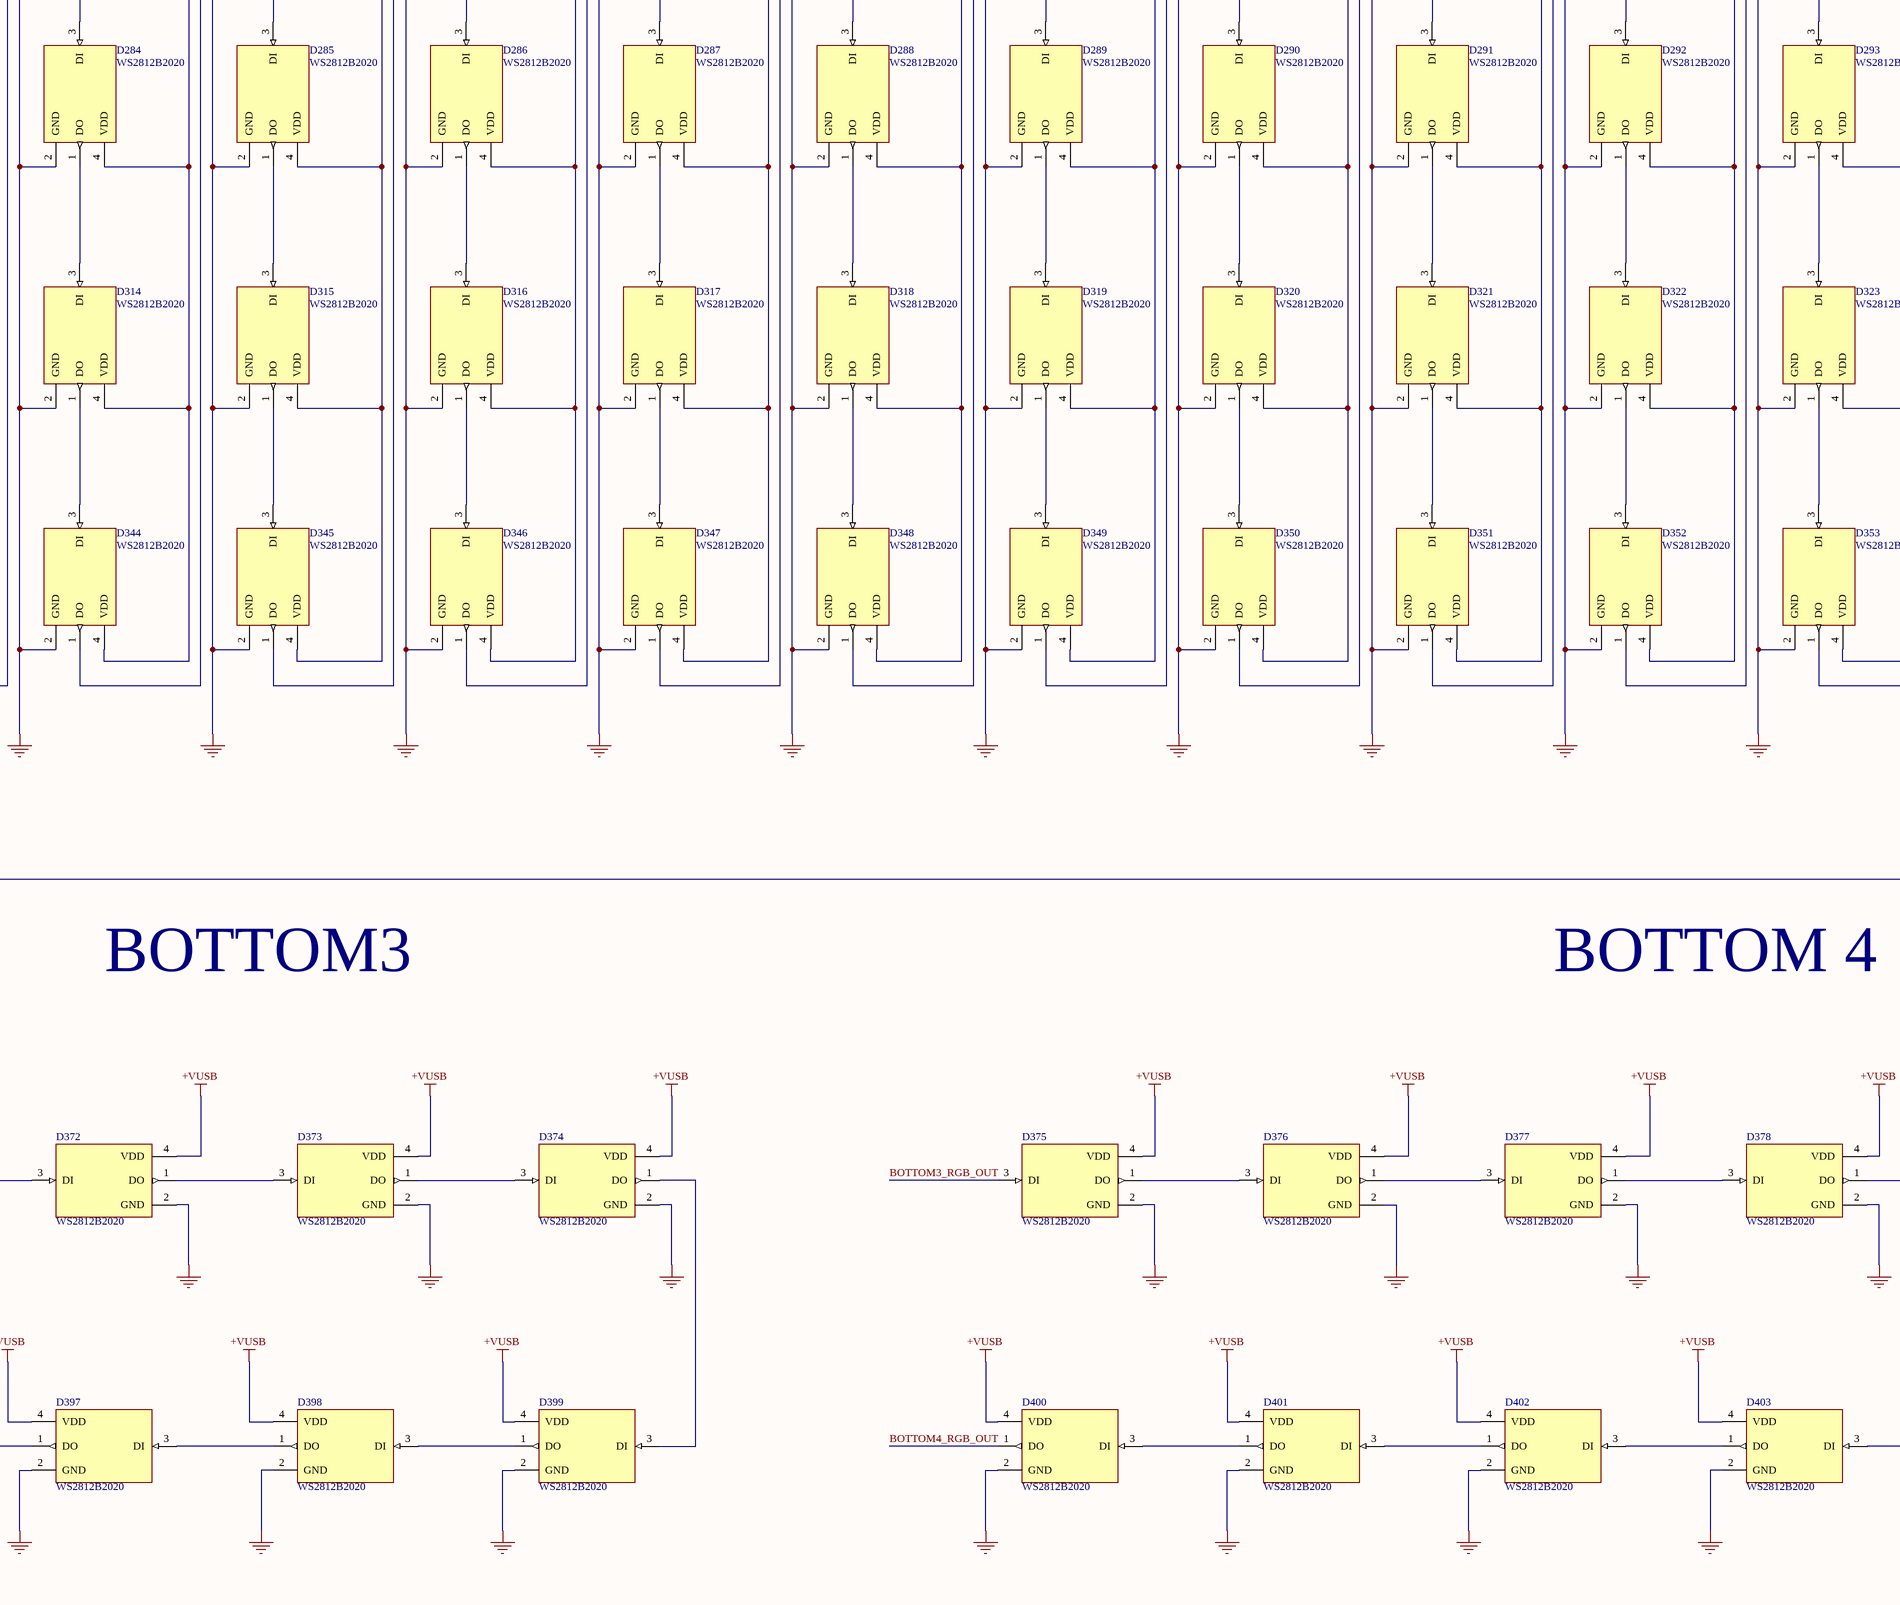
[diagram p10: WS2812B_ARRAY.SchDoc, bottom column 3 of 4]
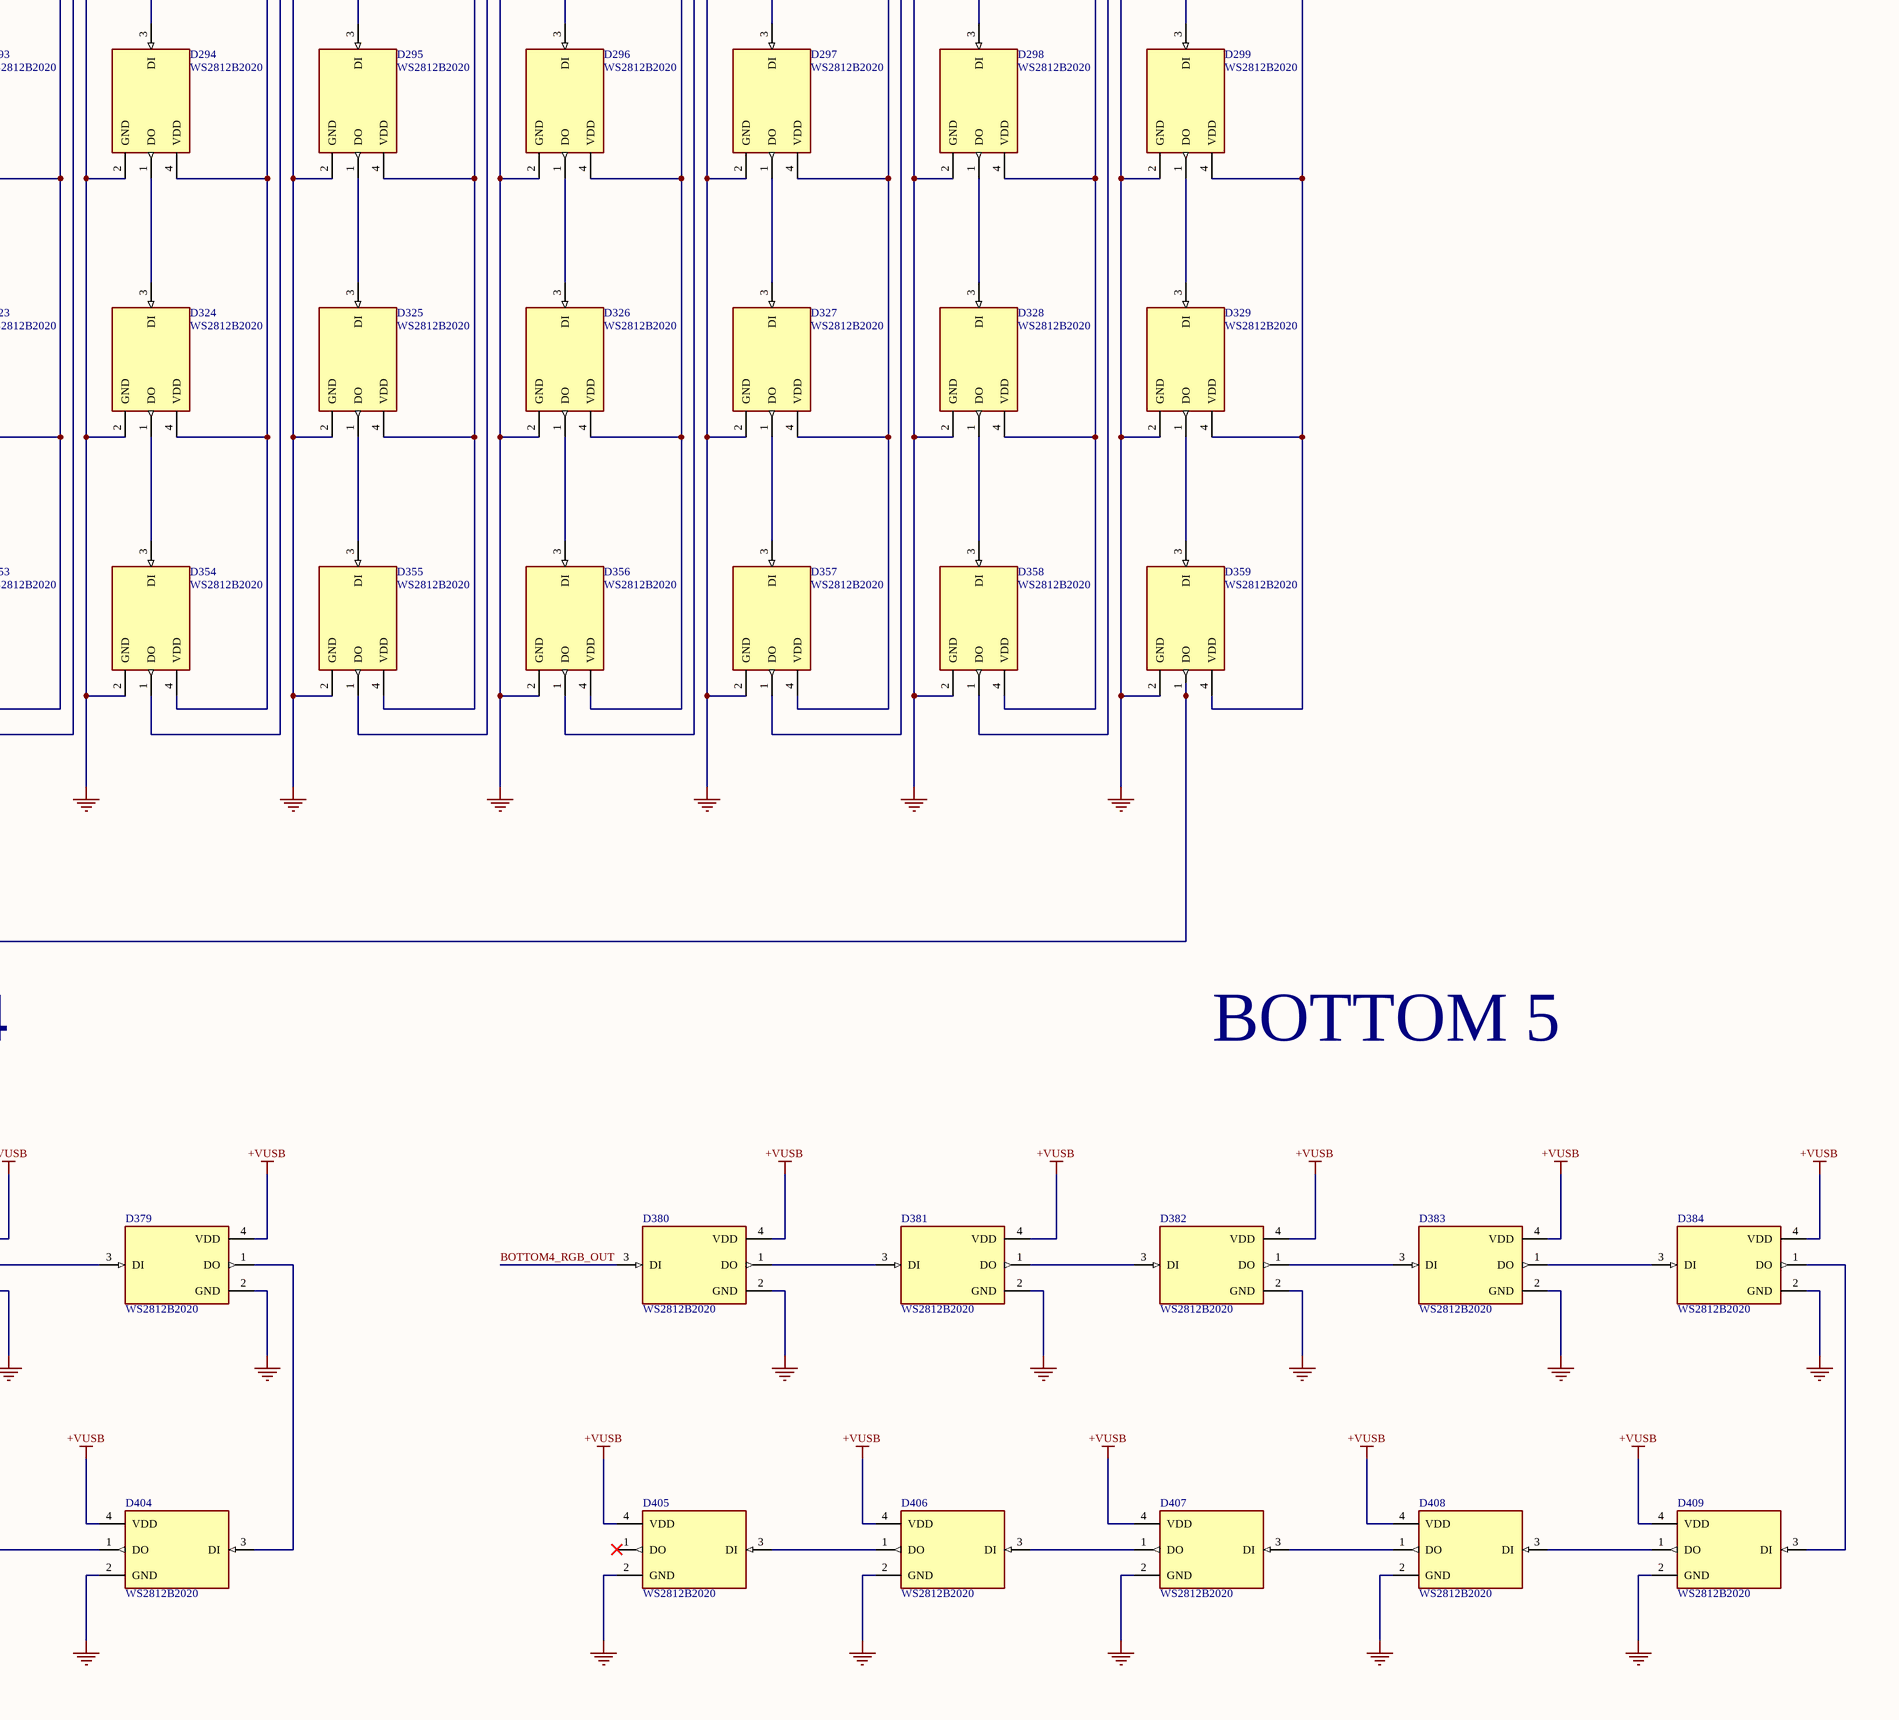
[diagram p11: WS2812B_ARRAY.SchDoc, bottom column 4 of 4]

(export (version "E")
  (design (tool "Eeschema 10.0.6"))
  (components
    (comp (ref "D10")
      (value "WS2812B2020")
      (footprint "XL-1010RGBC-WS2812B")
      (description "LED; SMD; 2020; RGB; 2x2x0.84mm; 3.7Ã·5.3V; Lens: transparent; 2kHz")
      (fields (field (name "MF") "WorldSemi"))
      (libsource (lib "") (part "WS2812B2020_1"))
    )
    (comp (ref "D11")
      (value "WS2812B2020")
      (footprint "XL-1010RGBC-WS2812B")
      (description "LED; SMD; 2020; RGB; 2x2x0.84mm; 3.7Ã·5.3V; Lens: transparent; 2kHz")
      (fields (field (name "MF") "WorldSemi"))
      (libsource (lib "") (part "WS2812B2020_1"))
    )
    (comp (ref "D12")
      (value "WS2812B2020")
      (footprint "XL-1010RGBC-WS2812B")
      (description "LED; SMD; 2020; RGB; 2x2x0.84mm; 3.7Ã·5.3V; Lens: transparent; 2kHz")
      (fields (field (name "MF") "WorldSemi"))
      (libsource (lib "") (part "WS2812B2020_1"))
    )
    (comp (ref "D13")
      (value "WS2812B2020")
      (footprint "XL-1010RGBC-WS2812B")
      (description "LED; SMD; 2020; RGB; 2x2x0.84mm; 3.7Ã·5.3V; Lens: transparent; 2kHz")
      (fields (field (name "MF") "WorldSemi"))
      (libsource (lib "") (part "WS2812B2020_1"))
    )
    (comp (ref "D14")
      (value "WS2812B2020")
      (footprint "XL-1010RGBC-WS2812B")
      (description "LED; SMD; 2020; RGB; 2x2x0.84mm; 3.7Ã·5.3V; Lens: transparent; 2kHz")
      (fields (field (name "MF") "WorldSemi"))
      (libsource (lib "") (part "WS2812B2020_1"))
    )
    (comp (ref "D15")
      (value "WS2812B2020")
      (footprint "XL-1010RGBC-WS2812B")
      (description "LED; SMD; 2020; RGB; 2x2x0.84mm; 3.7Ã·5.3V; Lens: transparent; 2kHz")
      (fields (field (name "MF") "WorldSemi"))
      (libsource (lib "") (part "WS2812B2020_1"))
    )
    (comp (ref "D16")
      (value "WS2812B2020")
      (footprint "XL-1010RGBC-WS2812B")
      (description "LED; SMD; 2020; RGB; 2x2x0.84mm; 3.7Ã·5.3V; Lens: transparent; 2kHz")
      (fields (field (name "MF") "WorldSemi"))
      (libsource (lib "") (part "WS2812B2020_1"))
    )
    (comp (ref "D17")
      (value "WS2812B2020")
      (footprint "XL-1010RGBC-WS2812B")
      (description "LED; SMD; 2020; RGB; 2x2x0.84mm; 3.7Ã·5.3V; Lens: transparent; 2kHz")
      (fields (field (name "MF") "WorldSemi"))
      (libsource (lib "") (part "WS2812B2020_1"))
    )
    (comp (ref "D18")
      (value "WS2812B2020")
      (footprint "XL-1010RGBC-WS2812B")
      (description "LED; SMD; 2020; RGB; 2x2x0.84mm; 3.7Ã·5.3V; Lens: transparent; 2kHz")
      (fields (field (name "MF") "WorldSemi"))
      (libsource (lib "") (part "WS2812B2020_1"))
    )
    (comp (ref "D19")
      (value "WS2812B2020")
      (footprint "XL-1010RGBC-WS2812B")
      (description "LED; SMD; 2020; RGB; 2x2x0.84mm; 3.7Ã·5.3V; Lens: transparent; 2kHz")
      (fields (field (name "MF") "WorldSemi"))
      (libsource (lib "") (part "WS2812B2020_1"))
    )
    (comp (ref "D20")
      (value "WS2812B2020")
      (footprint "XL-1010RGBC-WS2812B")
      (description "LED; SMD; 2020; RGB; 2x2x0.84mm; 3.7Ã·5.3V; Lens: transparent; 2kHz")
      (fields (field (name "MF") "WorldSemi"))
      (libsource (lib "") (part "WS2812B2020_1"))
    )
    (comp (ref "D21")
      (value "WS2812B2020")
      (footprint "XL-1010RGBC-WS2812B")
      (description "LED; SMD; 2020; RGB; 2x2x0.84mm; 3.7Ã·5.3V; Lens: transparent; 2kHz")
      (fields (field (name "MF") "WorldSemi"))
      (libsource (lib "") (part "WS2812B2020_1"))
    )
    (comp (ref "D22")
      (value "WS2812B2020")
      (footprint "XL-1010RGBC-WS2812B")
      (description "LED; SMD; 2020; RGB; 2x2x0.84mm; 3.7Ã·5.3V; Lens: transparent; 2kHz")
      (fields (field (name "MF") "WorldSemi"))
      (libsource (lib "") (part "WS2812B2020_1"))
    )
    (comp (ref "D23")
      (value "WS2812B2020")
      (footprint "XL-1010RGBC-WS2812B")
      (description "LED; SMD; 2020; RGB; 2x2x0.84mm; 3.7Ã·5.3V; Lens: transparent; 2kHz")
      (fields (field (name "MF") "WorldSemi"))
      (libsource (lib "") (part "WS2812B2020_1"))
    )
    (comp (ref "D24")
      (value "WS2812B2020")
      (footprint "XL-1010RGBC-WS2812B")
      (description "LED; SMD; 2020; RGB; 2x2x0.84mm; 3.7Ã·5.3V; Lens: transparent; 2kHz")
      (fields (field (name "MF") "WorldSemi"))
      (libsource (lib "") (part "WS2812B2020_1"))
    )
    (comp (ref "D25")
      (value "WS2812B2020")
      (footprint "XL-1010RGBC-WS2812B")
      (description "LED; SMD; 2020; RGB; 2x2x0.84mm; 3.7Ã·5.3V; Lens: transparent; 2kHz")
      (fields (field (name "MF") "WorldSemi"))
      (libsource (lib "") (part "WS2812B2020_1"))
    )
    (comp (ref "D26")
      (value "WS2812B2020")
      (footprint "XL-1010RGBC-WS2812B")
      (description "LED; SMD; 2020; RGB; 2x2x0.84mm; 3.7Ã·5.3V; Lens: transparent; 2kHz")
      (fields (field (name "MF") "WorldSemi"))
      (libsource (lib "") (part "WS2812B2020_1"))
    )
    (comp (ref "D27")
      (value "WS2812B2020")
      (footprint "XL-1010RGBC-WS2812B")
      (description "LED; SMD; 2020; RGB; 2x2x0.84mm; 3.7Ã·5.3V; Lens: transparent; 2kHz")
      (fields (field (name "MF") "WorldSemi"))
      (libsource (lib "") (part "WS2812B2020_1"))
    )
    (comp (ref "D28")
      (value "WS2812B2020")
      (footprint "XL-1010RGBC-WS2812B")
      (description "LED; SMD; 2020; RGB; 2x2x0.84mm; 3.7Ã·5.3V; Lens: transparent; 2kHz")
      (fields (field (name "MF") "WorldSemi"))
      (libsource (lib "") (part "WS2812B2020_1"))
    )
    (comp (ref "D29")
      (value "WS2812B2020")
      (footprint "XL-1010RGBC-WS2812B")
      (description "LED; SMD; 2020; RGB; 2x2x0.84mm; 3.7Ã·5.3V; Lens: transparent; 2kHz")
      (fields (field (name "MF") "WorldSemi"))
      (libsource (lib "") (part "WS2812B2020_1"))
    )
    (comp (ref "D30")
      (value "WS2812B2020")
      (footprint "XL-1010RGBC-WS2812B")
      (description "LED; SMD; 2020; RGB; 2x2x0.84mm; 3.7Ã·5.3V; Lens: transparent; 2kHz")
      (fields (field (name "MF") "WorldSemi"))
      (libsource (lib "") (part "WS2812B2020_1"))
    )
    (comp (ref "D31")
      (value "WS2812B2020")
      (footprint "XL-1010RGBC-WS2812B")
      (description "LED; SMD; 2020; RGB; 2x2x0.84mm; 3.7Ã·5.3V; Lens: transparent; 2kHz")
      (fields (field (name "MF") "WorldSemi"))
      (libsource (lib "") (part "WS2812B2020_1"))
    )
    (comp (ref "D32")
      (value "WS2812B2020")
      (footprint "XL-1010RGBC-WS2812B")
      (description "LED; SMD; 2020; RGB; 2x2x0.84mm; 3.7Ã·5.3V; Lens: transparent; 2kHz")
      (fields (field (name "MF") "WorldSemi"))
      (libsource (lib "") (part "WS2812B2020_1"))
    )
    (comp (ref "D33")
      (value "WS2812B2020")
      (footprint "XL-1010RGBC-WS2812B")
      (description "LED; SMD; 2020; RGB; 2x2x0.84mm; 3.7Ã·5.3V; Lens: transparent; 2kHz")
      (fields (field (name "MF") "WorldSemi"))
      (libsource (lib "") (part "WS2812B2020_1"))
    )
    (comp (ref "D34")
      (value "WS2812B2020")
      (footprint "XL-1010RGBC-WS2812B")
      (description "LED; SMD; 2020; RGB; 2x2x0.84mm; 3.7Ã·5.3V; Lens: transparent; 2kHz")
      (fields (field (name "MF") "WorldSemi"))
      (libsource (lib "") (part "WS2812B2020_1"))
    )
    (comp (ref "D35")
      (value "WS2812B2020")
      (footprint "XL-1010RGBC-WS2812B")
      (description "LED; SMD; 2020; RGB; 2x2x0.84mm; 3.7Ã·5.3V; Lens: transparent; 2kHz")
      (fields (field (name "MF") "WorldSemi"))
      (libsource (lib "WS2812B2020") (part "WS2812B2020"))
    )
    (comp (ref "D36")
      (value "WS2812B2020")
      (footprint "XL-1010RGBC-WS2812B")
      (description "LED; SMD; 2020; RGB; 2x2x0.84mm; 3.7Ã·5.3V; Lens: transparent; 2kHz")
      (fields (field (name "MF") "WorldSemi"))
      (libsource (lib "WS2812B2020") (part "WS2812B2020"))
    )
    (comp (ref "D37")
      (value "WS2812B2020")
      (footprint "XL-1010RGBC-WS2812B")
      (description "LED; SMD; 2020; RGB; 2x2x0.84mm; 3.7Ã·5.3V; Lens: transparent; 2kHz")
      (fields (field (name "MF") "WorldSemi"))
      (libsource (lib "WS2812B2020") (part "WS2812B2020"))
    )
    (comp (ref "D38")
      (value "WS2812B2020")
      (footprint "XL-1010RGBC-WS2812B")
      (description "LED; SMD; 2020; RGB; 2x2x0.84mm; 3.7Ã·5.3V; Lens: transparent; 2kHz")
      (fields (field (name "MF") "WorldSemi"))
      (libsource (lib "WS2812B2020") (part "WS2812B2020"))
    )
    (comp (ref "D39")
      (value "WS2812B2020")
      (footprint "XL-1010RGBC-WS2812B")
      (description "LED; SMD; 2020; RGB; 2x2x0.84mm; 3.7Ã·5.3V; Lens: transparent; 2kHz")
      (fields (field (name "MF") "WorldSemi"))
      (libsource (lib "WS2812B2020") (part "WS2812B2020"))
    )
    (comp (ref "D40")
      (value "WS2812B2020")
      (footprint "XL-1010RGBC-WS2812B")
      (description "LED; SMD; 2020; RGB; 2x2x0.84mm; 3.7Ã·5.3V; Lens: transparent; 2kHz")
      (fields (field (name "MF") "WorldSemi"))
      (libsource (lib "WS2812B2020") (part "WS2812B2020"))
    )
    (comp (ref "D41")
      (value "WS2812B2020")
      (footprint "XL-1010RGBC-WS2812B")
      (description "LED; SMD; 2020; RGB; 2x2x0.84mm; 3.7Ã·5.3V; Lens: transparent; 2kHz")
      (fields (field (name "MF") "WorldSemi"))
      (libsource (lib "WS2812B2020") (part "WS2812B2020"))
    )
    (comp (ref "D42")
      (value "WS2812B2020")
      (footprint "XL-1010RGBC-WS2812B")
      (description "LED; SMD; 2020; RGB; 2x2x0.84mm; 3.7Ã·5.3V; Lens: transparent; 2kHz")
      (fields (field (name "MF") "WorldSemi"))
      (libsource (lib "WS2812B2020") (part "WS2812B2020"))
    )
    (comp (ref "D43")
      (value "WS2812B2020")
      (footprint "XL-1010RGBC-WS2812B")
      (description "LED; SMD; 2020; RGB; 2x2x0.84mm; 3.7Ã·5.3V; Lens: transparent; 2kHz")
      (fields (field (name "MF") "WorldSemi"))
      (libsource (lib "WS2812B2020") (part "WS2812B2020"))
    )
    (comp (ref "D44")
      (value "WS2812B2020")
      (footprint "XL-1010RGBC-WS2812B")
      (description "LED; SMD; 2020; RGB; 2x2x0.84mm; 3.7Ã·5.3V; Lens: transparent; 2kHz")
      (fields (field (name "MF") "WorldSemi"))
      (libsource (lib "WS2812B2020") (part "WS2812B2020"))
    )
    (comp (ref "D45")
      (value "WS2812B2020")
      (footprint "XL-1010RGBC-WS2812B")
      (description "LED; SMD; 2020; RGB; 2x2x0.84mm; 3.7Ã·5.3V; Lens: transparent; 2kHz")
      (fields (field (name "MF") "WorldSemi"))
      (libsource (lib "WS2812B2020") (part "WS2812B2020"))
    )
    (comp (ref "D46")
      (value "WS2812B2020")
      (footprint "XL-1010RGBC-WS2812B")
      (description "LED; SMD; 2020; RGB; 2x2x0.84mm; 3.7Ã·5.3V; Lens: transparent; 2kHz")
      (fields (field (name "MF") "WorldSemi"))
      (libsource (lib "WS2812B2020") (part "WS2812B2020"))
    )
    (comp (ref "D47")
      (value "WS2812B2020")
      (footprint "XL-1010RGBC-WS2812B")
      (description "LED; SMD; 2020; RGB; 2x2x0.84mm; 3.7Ã·5.3V; Lens: transparent; 2kHz")
      (fields (field (name "MF") "WorldSemi"))
      (libsource (lib "WS2812B2020") (part "WS2812B2020"))
    )
    (comp (ref "D48")
      (value "WS2812B2020")
      (footprint "XL-1010RGBC-WS2812B")
      (description "LED; SMD; 2020; RGB; 2x2x0.84mm; 3.7Ã·5.3V; Lens: transparent; 2kHz")
      (fields (field (name "MF") "WorldSemi"))
      (libsource (lib "WS2812B2020") (part "WS2812B2020"))
    )
    (comp (ref "D49")
      (value "WS2812B2020")
      (footprint "XL-1010RGBC-WS2812B")
      (description "LED; SMD; 2020; RGB; 2x2x0.84mm; 3.7Ã·5.3V; Lens: transparent; 2kHz")
      (fields (field (name "MF") "WorldSemi"))
      (libsource (lib "WS2812B2020") (part "WS2812B2020"))
    )
    (comp (ref "D50")
      (value "WS2812B2020")
      (footprint "XL-1010RGBC-WS2812B")
      (description "LED; SMD; 2020; RGB; 2x2x0.84mm; 3.7Ã·5.3V; Lens: transparent; 2kHz")
      (fields (field (name "MF") "WorldSemi"))
      (libsource (lib "WS2812B2020") (part "WS2812B2020"))
    )
    (comp (ref "D51")
      (value "WS2812B2020")
      (footprint "XL-1010RGBC-WS2812B")
      (description "LED; SMD; 2020; RGB; 2x2x0.84mm; 3.7Ã·5.3V; Lens: transparent; 2kHz")
      (fields (field (name "MF") "WorldSemi"))
      (libsource (lib "WS2812B2020") (part "WS2812B2020"))
    )
    (comp (ref "D52")
      (value "WS2812B2020")
      (footprint "XL-1010RGBC-WS2812B")
      (description "LED; SMD; 2020; RGB; 2x2x0.84mm; 3.7Ã·5.3V; Lens: transparent; 2kHz")
      (fields (field (name "MF") "WorldSemi"))
      (libsource (lib "WS2812B2020") (part "WS2812B2020"))
    )
    (comp (ref "D53")
      (value "WS2812B2020")
      (footprint "XL-1010RGBC-WS2812B")
      (description "LED; SMD; 2020; RGB; 2x2x0.84mm; 3.7Ã·5.3V; Lens: transparent; 2kHz")
      (fields (field (name "MF") "WorldSemi"))
      (libsource (lib "WS2812B2020") (part "WS2812B2020"))
    )
    (comp (ref "D54")
      (value "WS2812B2020")
      (footprint "XL-1010RGBC-WS2812B")
      (description "LED; SMD; 2020; RGB; 2x2x0.84mm; 3.7Ã·5.3V; Lens: transparent; 2kHz")
      (fields (field (name "MF") "WorldSemi"))
      (libsource (lib "WS2812B2020") (part "WS2812B2020"))
    )
    (comp (ref "D55")
      (value "WS2812B2020")
      (footprint "XL-1010RGBC-WS2812B")
      (description "LED; SMD; 2020; RGB; 2x2x0.84mm; 3.7Ã·5.3V; Lens: transparent; 2kHz")
      (fields (field (name "MF") "WorldSemi"))
      (libsource (lib "WS2812B2020") (part "WS2812B2020"))
    )
    (comp (ref "D56")
      (value "WS2812B2020")
      (footprint "XL-1010RGBC-WS2812B")
      (description "LED; SMD; 2020; RGB; 2x2x0.84mm; 3.7Ã·5.3V; Lens: transparent; 2kHz")
      (fields (field (name "MF") "WorldSemi"))
      (libsource (lib "WS2812B2020") (part "WS2812B2020"))
    )
    (comp (ref "D57")
      (value "WS2812B2020")
      (footprint "XL-1010RGBC-WS2812B")
      (description "LED; SMD; 2020; RGB; 2x2x0.84mm; 3.7Ã·5.3V; Lens: transparent; 2kHz")
      (fields (field (name "MF") "WorldSemi"))
      (libsource (lib "WS2812B2020") (part "WS2812B2020"))
    )
    (comp (ref "D58")
      (value "WS2812B2020")
      (footprint "XL-1010RGBC-WS2812B")
      (description "LED; SMD; 2020; RGB; 2x2x0.84mm; 3.7Ã·5.3V; Lens: transparent; 2kHz")
      (fields (field (name "MF") "WorldSemi"))
      (libsource (lib "WS2812B2020") (part "WS2812B2020"))
    )
    (comp (ref "D59")
      (value "WS2812B2020")
      (footprint "XL-1010RGBC-WS2812B")
      (description "LED; SMD; 2020; RGB; 2x2x0.84mm; 3.7Ã·5.3V; Lens: transparent; 2kHz")
      (fields (field (name "MF") "WorldSemi"))
      (libsource (lib "WS2812B2020") (part "WS2812B2020"))
    )
    (comp (ref "D60")
      (value "WS2812B2020")
      (footprint "XL-1010RGBC-WS2812B")
      (description "LED; SMD; 2020; RGB; 2x2x0.84mm; 3.7Ã·5.3V; Lens: transparent; 2kHz")
      (fields (field (name "MF") "WorldSemi"))
      (libsource (lib "WS2812B2020") (part "WS2812B2020"))
    )
    (comp (ref "D61")
      (value "WS2812B2020")
      (footprint "XL-1010RGBC-WS2812B")
      (description "LED; SMD; 2020; RGB; 2x2x0.84mm; 3.7Ã·5.3V; Lens: transparent; 2kHz")
      (fields (field (name "MF") "WorldSemi"))
      (libsource (lib "WS2812B2020") (part "WS2812B2020"))
    )
    (comp (ref "D62")
      (value "WS2812B2020")
      (footprint "XL-1010RGBC-WS2812B")
      (description "LED; SMD; 2020; RGB; 2x2x0.84mm; 3.7Ã·5.3V; Lens: transparent; 2kHz")
      (fields (field (name "MF") "WorldSemi"))
      (libsource (lib "WS2812B2020") (part "WS2812B2020"))
    )
    (comp (ref "D63")
      (value "WS2812B2020")
      (footprint "XL-1010RGBC-WS2812B")
      (description "LED; SMD; 2020; RGB; 2x2x0.84mm; 3.7Ã·5.3V; Lens: transparent; 2kHz")
      (fields (field (name "MF") "WorldSemi"))
      (libsource (lib "WS2812B2020") (part "WS2812B2020"))
    )
    (comp (ref "D64")
      (value "WS2812B2020")
      (footprint "XL-1010RGBC-WS2812B")
      (description "LED; SMD; 2020; RGB; 2x2x0.84mm; 3.7Ã·5.3V; Lens: transparent; 2kHz")
      (fields (field (name "MF") "WorldSemi"))
      (libsource (lib "WS2812B2020") (part "WS2812B2020"))
    )
    (comp (ref "D65")
      (value "WS2812B2020")
      (footprint "XL-1010RGBC-WS2812B")
      (description "LED; SMD; 2020; RGB; 2x2x0.84mm; 3.7Ã·5.3V; Lens: transparent; 2kHz")
      (fields (field (name "MF") "WorldSemi"))
      (libsource (lib "WS2812B2020") (part "WS2812B2020"))
    )
    (comp (ref "D66")
      (value "WS2812B2020")
      (footprint "XL-1010RGBC-WS2812B")
      (description "LED; SMD; 2020; RGB; 2x2x0.84mm; 3.7Ã·5.3V; Lens: transparent; 2kHz")
      (fields (field (name "MF") "WorldSemi"))
      (libsource (lib "WS2812B2020") (part "WS2812B2020"))
    )
    (comp (ref "D67")
      (value "WS2812B2020")
      (footprint "XL-1010RGBC-WS2812B")
      (description "LED; SMD; 2020; RGB; 2x2x0.84mm; 3.7Ã·5.3V; Lens: transparent; 2kHz")
      (fields (field (name "MF") "WorldSemi"))
      (libsource (lib "WS2812B2020") (part "WS2812B2020"))
    )
    (comp (ref "D68")
      (value "WS2812B2020")
      (footprint "XL-1010RGBC-WS2812B")
      (description "LED; SMD; 2020; RGB; 2x2x0.84mm; 3.7Ã·5.3V; Lens: transparent; 2kHz")
      (fields (field (name "MF") "WorldSemi"))
      (libsource (lib "WS2812B2020") (part "WS2812B2020"))
    )
    (comp (ref "D69")
      (value "WS2812B2020")
      (footprint "XL-1010RGBC-WS2812B")
      (description "LED; SMD; 2020; RGB; 2x2x0.84mm; 3.7Ã·5.3V; Lens: transparent; 2kHz")
      (fields (field (name "MF") "WorldSemi"))
      (libsource (lib "WS2812B2020") (part "WS2812B2020"))
    )
    (comp (ref "D70")
      (value "WS2812B2020")
      (footprint "XL-1010RGBC-WS2812B")
      (description "LED; SMD; 2020; RGB; 2x2x0.84mm; 3.7Ã·5.3V; Lens: transparent; 2kHz")
      (fields (field (name "MF") "WorldSemi"))
      (libsource (lib "WS2812B2020") (part "WS2812B2020"))
    )
    (comp (ref "D71")
      (value "WS2812B2020")
      (footprint "XL-1010RGBC-WS2812B")
      (description "LED; SMD; 2020; RGB; 2x2x0.84mm; 3.7Ã·5.3V; Lens: transparent; 2kHz")
      (fields (field (name "MF") "WorldSemi"))
      (libsource (lib "WS2812B2020") (part "WS2812B2020"))
    )
    (comp (ref "D72")
      (value "WS2812B2020")
      (footprint "XL-1010RGBC-WS2812B")
      (description "LED; SMD; 2020; RGB; 2x2x0.84mm; 3.7Ã·5.3V; Lens: transparent; 2kHz")
      (fields (field (name "MF") "WorldSemi"))
      (libsource (lib "WS2812B2020") (part "WS2812B2020"))
    )
    (comp (ref "D73")
      (value "WS2812B2020")
      (footprint "XL-1010RGBC-WS2812B")
      (description "LED; SMD; 2020; RGB; 2x2x0.84mm; 3.7Ã·5.3V; Lens: transparent; 2kHz")
      (fields (field (name "MF") "WorldSemi"))
      (libsource (lib "WS2812B2020") (part "WS2812B2020"))
    )
    (comp (ref "D74")
      (value "WS2812B2020")
      (footprint "XL-1010RGBC-WS2812B")
      (description "LED; SMD; 2020; RGB; 2x2x0.84mm; 3.7Ã·5.3V; Lens: transparent; 2kHz")
      (fields (field (name "MF") "WorldSemi"))
      (libsource (lib "WS2812B2020") (part "WS2812B2020"))
    )
    (comp (ref "D75")
      (value "WS2812B2020")
      (footprint "XL-1010RGBC-WS2812B")
      (description "LED; SMD; 2020; RGB; 2x2x0.84mm; 3.7Ã·5.3V; Lens: transparent; 2kHz")
      (fields (field (name "MF") "WorldSemi"))
      (libsource (lib "WS2812B2020") (part "WS2812B2020"))
    )
    (comp (ref "D76")
      (value "WS2812B2020")
      (footprint "XL-1010RGBC-WS2812B")
      (description "LED; SMD; 2020; RGB; 2x2x0.84mm; 3.7Ã·5.3V; Lens: transparent; 2kHz")
      (fields (field (name "MF") "WorldSemi"))
      (libsource (lib "WS2812B2020") (part "WS2812B2020"))
    )
    (comp (ref "D77")
      (value "WS2812B2020")
      (footprint "XL-1010RGBC-WS2812B")
      (description "LED; SMD; 2020; RGB; 2x2x0.84mm; 3.7Ã·5.3V; Lens: transparent; 2kHz")
      (fields (field (name "MF") "WorldSemi"))
      (libsource (lib "WS2812B2020") (part "WS2812B2020"))
    )
    (comp (ref "D78")
      (value "WS2812B2020")
      (footprint "XL-1010RGBC-WS2812B")
      (description "LED; SMD; 2020; RGB; 2x2x0.84mm; 3.7Ã·5.3V; Lens: transparent; 2kHz")
      (fields (field (name "MF") "WorldSemi"))
      (libsource (lib "WS2812B2020") (part "WS2812B2020"))
    )
    (comp (ref "D79")
      (value "WS2812B2020")
      (footprint "XL-1010RGBC-WS2812B")
      (description "LED; SMD; 2020; RGB; 2x2x0.84mm; 3.7Ã·5.3V; Lens: transparent; 2kHz")
      (fields (field (name "MF") "WorldSemi"))
      (libsource (lib "WS2812B2020") (part "WS2812B2020"))
    )
    (comp (ref "D80")
      (value "WS2812B2020")
      (footprint "XL-1010RGBC-WS2812B")
      (description "LED; SMD; 2020; RGB; 2x2x0.84mm; 3.7Ã·5.3V; Lens: transparent; 2kHz")
      (fields (field (name "MF") "WorldSemi"))
      (libsource (lib "WS2812B2020") (part "WS2812B2020"))
    )
    (comp (ref "D81")
      (value "WS2812B2020")
      (footprint "XL-1010RGBC-WS2812B")
      (description "LED; SMD; 2020; RGB; 2x2x0.84mm; 3.7Ã·5.3V; Lens: transparent; 2kHz")
      (fields (field (name "MF") "WorldSemi"))
      (libsource (lib "WS2812B2020") (part "WS2812B2020"))
    )
    (comp (ref "D82")
      (value "WS2812B2020")
      (footprint "XL-1010RGBC-WS2812B")
      (description "LED; SMD; 2020; RGB; 2x2x0.84mm; 3.7Ã·5.3V; Lens: transparent; 2kHz")
      (fields (field (name "MF") "WorldSemi"))
      (libsource (lib "WS2812B2020") (part "WS2812B2020"))
    )
    (comp (ref "D83")
      (value "WS2812B2020")
      (footprint "XL-1010RGBC-WS2812B")
      (description "LED; SMD; 2020; RGB; 2x2x0.84mm; 3.7Ã·5.3V; Lens: transparent; 2kHz")
      (fields (field (name "MF") "WorldSemi"))
      (libsource (lib "WS2812B2020") (part "WS2812B2020"))
    )
    (comp (ref "D84")
      (value "WS2812B2020")
      (footprint "XL-1010RGBC-WS2812B")
      (description "LED; SMD; 2020; RGB; 2x2x0.84mm; 3.7Ã·5.3V; Lens: transparent; 2kHz")
      (fields (field (name "MF") "WorldSemi"))
      (libsource (lib "WS2812B2020") (part "WS2812B2020"))
    )
    (comp (ref "D85")
      (value "WS2812B2020")
      (footprint "XL-1010RGBC-WS2812B")
      (description "LED; SMD; 2020; RGB; 2x2x0.84mm; 3.7Ã·5.3V; Lens: transparent; 2kHz")
      (fields (field (name "MF") "WorldSemi"))
      (libsource (lib "WS2812B2020") (part "WS2812B2020"))
    )
    (comp (ref "D86")
      (value "WS2812B2020")
      (footprint "XL-1010RGBC-WS2812B")
      (description "LED; SMD; 2020; RGB; 2x2x0.84mm; 3.7Ã·5.3V; Lens: transparent; 2kHz")
      (fields (field (name "MF") "WorldSemi"))
      (libsource (lib "WS2812B2020") (part "WS2812B2020"))
    )
    (comp (ref "D87")
      (value "WS2812B2020")
      (footprint "XL-1010RGBC-WS2812B")
      (description "LED; SMD; 2020; RGB; 2x2x0.84mm; 3.7Ã·5.3V; Lens: transparent; 2kHz")
      (fields (field (name "MF") "WorldSemi"))
      (libsource (lib "WS2812B2020") (part "WS2812B2020"))
    )
    (comp (ref "D88")
      (value "WS2812B2020")
      (footprint "XL-1010RGBC-WS2812B")
      (description "LED; SMD; 2020; RGB; 2x2x0.84mm; 3.7Ã·5.3V; Lens: transparent; 2kHz")
      (fields (field (name "MF") "WorldSemi"))
      (libsource (lib "WS2812B2020") (part "WS2812B2020"))
    )
    (comp (ref "D89")
      (value "WS2812B2020")
      (footprint "XL-1010RGBC-WS2812B")
      (description "LED; SMD; 2020; RGB; 2x2x0.84mm; 3.7Ã·5.3V; Lens: transparent; 2kHz")
      (fields (field (name "MF") "WorldSemi"))
      (libsource (lib "WS2812B2020") (part "WS2812B2020"))
    )
    (comp (ref "D90")
      (value "WS2812B2020")
      (footprint "XL-1010RGBC-WS2812B")
      (description "LED; SMD; 2020; RGB; 2x2x0.84mm; 3.7Ã·5.3V; Lens: transparent; 2kHz")
      (fields (field (name "MF") "WorldSemi"))
      (libsource (lib "WS2812B2020") (part "WS2812B2020"))
    )
    (comp (ref "D91")
      (value "WS2812B2020")
      (footprint "XL-1010RGBC-WS2812B")
      (description "LED; SMD; 2020; RGB; 2x2x0.84mm; 3.7Ã·5.3V; Lens: transparent; 2kHz")
      (fields (field (name "MF") "WorldSemi"))
      (libsource (lib "WS2812B2020") (part "WS2812B2020"))
    )
    (comp (ref "D92")
      (value "WS2812B2020")
      (footprint "XL-1010RGBC-WS2812B")
      (description "LED; SMD; 2020; RGB; 2x2x0.84mm; 3.7Ã·5.3V; Lens: transparent; 2kHz")
      (fields (field (name "MF") "WorldSemi"))
      (libsource (lib "WS2812B2020") (part "WS2812B2020"))
    )
    (comp (ref "D93")
      (value "WS2812B2020")
      (footprint "XL-1010RGBC-WS2812B")
      (description "LED; SMD; 2020; RGB; 2x2x0.84mm; 3.7Ã·5.3V; Lens: transparent; 2kHz")
      (fields (field (name "MF") "WorldSemi"))
      (libsource (lib "WS2812B2020") (part "WS2812B2020"))
    )
    (comp (ref "D94")
      (value "WS2812B2020")
      (footprint "XL-1010RGBC-WS2812B")
      (description "LED; SMD; 2020; RGB; 2x2x0.84mm; 3.7Ã·5.3V; Lens: transparent; 2kHz")
      (fields (field (name "MF") "WorldSemi"))
      (libsource (lib "WS2812B2020") (part "WS2812B2020"))
    )
    (comp (ref "D95")
      (value "WS2812B2020")
      (footprint "XL-1010RGBC-WS2812B")
      (description "LED; SMD; 2020; RGB; 2x2x0.84mm; 3.7Ã·5.3V; Lens: transparent; 2kHz")
      (fields (field (name "MF") "WorldSemi"))
      (libsource (lib "WS2812B2020") (part "WS2812B2020"))
    )
    (comp (ref "D96")
      (value "WS2812B2020")
      (footprint "XL-1010RGBC-WS2812B")
      (description "LED; SMD; 2020; RGB; 2x2x0.84mm; 3.7Ã·5.3V; Lens: transparent; 2kHz")
      (fields (field (name "MF") "WorldSemi"))
      (libsource (lib "WS2812B2020") (part "WS2812B2020"))
    )
    (comp (ref "D97")
      (value "WS2812B2020")
      (footprint "XL-1010RGBC-WS2812B")
      (description "LED; SMD; 2020; RGB; 2x2x0.84mm; 3.7Ã·5.3V; Lens: transparent; 2kHz")
      (fields (field (name "MF") "WorldSemi"))
      (libsource (lib "WS2812B2020") (part "WS2812B2020"))
    )
    (comp (ref "D98")
      (value "WS2812B2020")
      (footprint "XL-1010RGBC-WS2812B")
      (description "LED; SMD; 2020; RGB; 2x2x0.84mm; 3.7Ã·5.3V; Lens: transparent; 2kHz")
      (fields (field (name "MF") "WorldSemi"))
      (libsource (lib "WS2812B2020") (part "WS2812B2020"))
    )
    (comp (ref "D99")
      (value "WS2812B2020")
      (footprint "XL-1010RGBC-WS2812B")
      (description "LED; SMD; 2020; RGB; 2x2x0.84mm; 3.7Ã·5.3V; Lens: transparent; 2kHz")
      (fields (field (name "MF") "WorldSemi"))
      (libsource (lib "WS2812B2020") (part "WS2812B2020"))
    )
    (comp (ref "D100")
      (value "WS2812B2020")
      (footprint "XL-1010RGBC-WS2812B")
      (description "LED; SMD; 2020; RGB; 2x2x0.84mm; 3.7Ã·5.3V; Lens: transparent; 2kHz")
      (fields (field (name "MF") "WorldSemi"))
      (libsource (lib "WS2812B2020") (part "WS2812B2020"))
    )
    (comp (ref "D101")
      (value "WS2812B2020")
      (footprint "XL-1010RGBC-WS2812B")
      (description "LED; SMD; 2020; RGB; 2x2x0.84mm; 3.7Ã·5.3V; Lens: transparent; 2kHz")
      (fields (field (name "MF") "WorldSemi"))
      (libsource (lib "WS2812B2020") (part "WS2812B2020"))
    )
    (comp (ref "D102")
      (value "WS2812B2020")
      (footprint "XL-1010RGBC-WS2812B")
      (description "LED; SMD; 2020; RGB; 2x2x0.84mm; 3.7Ã·5.3V; Lens: transparent; 2kHz")
      (fields (field (name "MF") "WorldSemi"))
      (libsource (lib "WS2812B2020") (part "WS2812B2020"))
    )
    (comp (ref "D103")
      (value "WS2812B2020")
      (footprint "XL-1010RGBC-WS2812B")
      (description "LED; SMD; 2020; RGB; 2x2x0.84mm; 3.7Ã·5.3V; Lens: transparent; 2kHz")
      (fields (field (name "MF") "WorldSemi"))
      (libsource (lib "WS2812B2020") (part "WS2812B2020"))
    )
    (comp (ref "D104")
      (value "WS2812B2020")
      (footprint "XL-1010RGBC-WS2812B")
      (description "LED; SMD; 2020; RGB; 2x2x0.84mm; 3.7Ã·5.3V; Lens: transparent; 2kHz")
      (fields (field (name "MF") "WorldSemi"))
      (libsource (lib "WS2812B2020") (part "WS2812B2020"))
    )
    (comp (ref "D105")
      (value "WS2812B2020")
      (footprint "XL-1010RGBC-WS2812B")
      (description "LED; SMD; 2020; RGB; 2x2x0.84mm; 3.7Ã·5.3V; Lens: transparent; 2kHz")
      (fields (field (name "MF") "WorldSemi"))
      (libsource (lib "WS2812B2020") (part "WS2812B2020"))
    )
    (comp (ref "D106")
      (value "WS2812B2020")
      (footprint "XL-1010RGBC-WS2812B")
      (description "LED; SMD; 2020; RGB; 2x2x0.84mm; 3.7Ã·5.3V; Lens: transparent; 2kHz")
      (fields (field (name "MF") "WorldSemi"))
      (libsource (lib "WS2812B2020") (part "WS2812B2020"))
    )
    (comp (ref "D107")
      (value "WS2812B2020")
      (footprint "XL-1010RGBC-WS2812B")
      (description "LED; SMD; 2020; RGB; 2x2x0.84mm; 3.7Ã·5.3V; Lens: transparent; 2kHz")
      (fields (field (name "MF") "WorldSemi"))
      (libsource (lib "WS2812B2020") (part "WS2812B2020"))
    )
    (comp (ref "D108")
      (value "WS2812B2020")
      (footprint "XL-1010RGBC-WS2812B")
      (description "LED; SMD; 2020; RGB; 2x2x0.84mm; 3.7Ã·5.3V; Lens: transparent; 2kHz")
      (fields (field (name "MF") "WorldSemi"))
      (libsource (lib "WS2812B2020") (part "WS2812B2020"))
    )
    (comp (ref "D109")
      (value "WS2812B2020")
      (footprint "XL-1010RGBC-WS2812B")
      (description "LED; SMD; 2020; RGB; 2x2x0.84mm; 3.7Ã·5.3V; Lens: transparent; 2kHz")
      (fields (field (name "MF") "WorldSemi"))
      (libsource (lib "WS2812B2020") (part "WS2812B2020"))
    )
    (comp (ref "D110")
      (value "WS2812B2020")
      (footprint "XL-1010RGBC-WS2812B")
      (description "LED; SMD; 2020; RGB; 2x2x0.84mm; 3.7Ã·5.3V; Lens: transparent; 2kHz")
      (fields (field (name "MF") "WorldSemi"))
      (libsource (lib "WS2812B2020") (part "WS2812B2020"))
    )
    (comp (ref "D111")
      (value "WS2812B2020")
      (footprint "XL-1010RGBC-WS2812B")
      (description "LED; SMD; 2020; RGB; 2x2x0.84mm; 3.7Ã·5.3V; Lens: transparent; 2kHz")
      (fields (field (name "MF") "WorldSemi"))
      (libsource (lib "WS2812B2020") (part "WS2812B2020"))
    )
    (comp (ref "D112")
      (value "WS2812B2020")
      (footprint "XL-1010RGBC-WS2812B")
      (description "LED; SMD; 2020; RGB; 2x2x0.84mm; 3.7Ã·5.3V; Lens: transparent; 2kHz")
      (fields (field (name "MF") "WorldSemi"))
      (libsource (lib "WS2812B2020") (part "WS2812B2020"))
    )
    (comp (ref "D113")
      (value "WS2812B2020")
      (footprint "XL-1010RGBC-WS2812B")
      (description "LED; SMD; 2020; RGB; 2x2x0.84mm; 3.7Ã·5.3V; Lens: transparent; 2kHz")
      (fields (field (name "MF") "WorldSemi"))
      (libsource (lib "WS2812B2020") (part "WS2812B2020"))
    )
    (comp (ref "D114")
      (value "WS2812B2020")
      (footprint "XL-1010RGBC-WS2812B")
      (description "LED; SMD; 2020; RGB; 2x2x0.84mm; 3.7Ã·5.3V; Lens: transparent; 2kHz")
      (fields (field (name "MF") "WorldSemi"))
      (libsource (lib "WS2812B2020") (part "WS2812B2020"))
    )
    (comp (ref "D115")
      (value "WS2812B2020")
      (footprint "XL-1010RGBC-WS2812B")
      (description "LED; SMD; 2020; RGB; 2x2x0.84mm; 3.7Ã·5.3V; Lens: transparent; 2kHz")
      (fields (field (name "MF") "WorldSemi"))
      (libsource (lib "WS2812B2020") (part "WS2812B2020"))
    )
    (comp (ref "D116")
      (value "WS2812B2020")
      (footprint "XL-1010RGBC-WS2812B")
      (description "LED; SMD; 2020; RGB; 2x2x0.84mm; 3.7Ã·5.3V; Lens: transparent; 2kHz")
      (fields (field (name "MF") "WorldSemi"))
      (libsource (lib "WS2812B2020") (part "WS2812B2020"))
    )
    (comp (ref "D117")
      (value "WS2812B2020")
      (footprint "XL-1010RGBC-WS2812B")
      (description "LED; SMD; 2020; RGB; 2x2x0.84mm; 3.7Ã·5.3V; Lens: transparent; 2kHz")
      (fields (field (name "MF") "WorldSemi"))
      (libsource (lib "WS2812B2020") (part "WS2812B2020"))
    )
    (comp (ref "D118")
      (value "WS2812B2020")
      (footprint "XL-1010RGBC-WS2812B")
      (description "LED; SMD; 2020; RGB; 2x2x0.84mm; 3.7Ã·5.3V; Lens: transparent; 2kHz")
      (fields (field (name "MF") "WorldSemi"))
      (libsource (lib "WS2812B2020") (part "WS2812B2020"))
    )
    (comp (ref "D119")
      (value "WS2812B2020")
      (footprint "XL-1010RGBC-WS2812B")
      (description "LED; SMD; 2020; RGB; 2x2x0.84mm; 3.7Ã·5.3V; Lens: transparent; 2kHz")
      (fields (field (name "MF") "WorldSemi"))
      (libsource (lib "WS2812B2020") (part "WS2812B2020"))
    )
    (comp (ref "D120")
      (value "WS2812B2020")
      (footprint "XL-1010RGBC-WS2812B")
      (description "LED; SMD; 2020; RGB; 2x2x0.84mm; 3.7Ã·5.3V; Lens: transparent; 2kHz")
      (fields (field (name "MF") "WorldSemi"))
      (libsource (lib "WS2812B2020") (part "WS2812B2020"))
    )
    (comp (ref "D121")
      (value "WS2812B2020")
      (footprint "XL-1010RGBC-WS2812B")
      (description "LED; SMD; 2020; RGB; 2x2x0.84mm; 3.7Ã·5.3V; Lens: transparent; 2kHz")
      (fields (field (name "MF") "WorldSemi"))
      (libsource (lib "WS2812B2020") (part "WS2812B2020"))
    )
    (comp (ref "D122")
      (value "WS2812B2020")
      (footprint "XL-1010RGBC-WS2812B")
      (description "LED; SMD; 2020; RGB; 2x2x0.84mm; 3.7Ã·5.3V; Lens: transparent; 2kHz")
      (fields (field (name "MF") "WorldSemi"))
      (libsource (lib "WS2812B2020") (part "WS2812B2020"))
    )
    (comp (ref "D123")
      (value "WS2812B2020")
      (footprint "XL-1010RGBC-WS2812B")
      (description "LED; SMD; 2020; RGB; 2x2x0.84mm; 3.7Ã·5.3V; Lens: transparent; 2kHz")
      (fields (field (name "MF") "WorldSemi"))
      (libsource (lib "WS2812B2020") (part "WS2812B2020"))
    )
    (comp (ref "D124")
      (value "WS2812B2020")
      (footprint "XL-1010RGBC-WS2812B")
      (description "LED; SMD; 2020; RGB; 2x2x0.84mm; 3.7Ã·5.3V; Lens: transparent; 2kHz")
      (fields (field (name "MF") "WorldSemi"))
      (libsource (lib "WS2812B2020") (part "WS2812B2020"))
    )
    (comp (ref "D125")
      (value "WS2812B2020")
      (footprint "XL-1010RGBC-WS2812B")
      (description "LED; SMD; 2020; RGB; 2x2x0.84mm; 3.7Ã·5.3V; Lens: transparent; 2kHz")
      (fields (field (name "MF") "WorldSemi"))
      (libsource (lib "WS2812B2020") (part "WS2812B2020"))
    )
    (comp (ref "D126")
      (value "WS2812B2020")
      (footprint "XL-1010RGBC-WS2812B")
      (description "LED; SMD; 2020; RGB; 2x2x0.84mm; 3.7Ã·5.3V; Lens: transparent; 2kHz")
      (fields (field (name "MF") "WorldSemi"))
      (libsource (lib "WS2812B2020") (part "WS2812B2020"))
    )
    (comp (ref "D127")
      (value "WS2812B2020")
      (footprint "XL-1010RGBC-WS2812B")
      (description "LED; SMD; 2020; RGB; 2x2x0.84mm; 3.7Ã·5.3V; Lens: transparent; 2kHz")
      (fields (field (name "MF") "WorldSemi"))
      (libsource (lib "WS2812B2020") (part "WS2812B2020"))
    )
    (comp (ref "D128")
      (value "WS2812B2020")
      (footprint "XL-1010RGBC-WS2812B")
      (description "LED; SMD; 2020; RGB; 2x2x0.84mm; 3.7Ã·5.3V; Lens: transparent; 2kHz")
      (fields (field (name "MF") "WorldSemi"))
      (libsource (lib "WS2812B2020") (part "WS2812B2020"))
    )
    (comp (ref "D129")
      (value "WS2812B2020")
      (footprint "XL-1010RGBC-WS2812B")
      (description "LED; SMD; 2020; RGB; 2x2x0.84mm; 3.7Ã·5.3V; Lens: transparent; 2kHz")
      (fields (field (name "MF") "WorldSemi"))
      (libsource (lib "WS2812B2020") (part "WS2812B2020"))
    )
    (comp (ref "D130")
      (value "WS2812B2020")
      (footprint "XL-1010RGBC-WS2812B")
      (description "LED; SMD; 2020; RGB; 2x2x0.84mm; 3.7Ã·5.3V; Lens: transparent; 2kHz")
      (fields (field (name "MF") "WorldSemi"))
      (libsource (lib "WS2812B2020") (part "WS2812B2020"))
    )
    (comp (ref "D131")
      (value "WS2812B2020")
      (footprint "XL-1010RGBC-WS2812B")
      (description "LED; SMD; 2020; RGB; 2x2x0.84mm; 3.7Ã·5.3V; Lens: transparent; 2kHz")
      (fields (field (name "MF") "WorldSemi"))
      (libsource (lib "WS2812B2020") (part "WS2812B2020"))
    )
    (comp (ref "D132")
      (value "WS2812B2020")
      (footprint "XL-1010RGBC-WS2812B")
      (description "LED; SMD; 2020; RGB; 2x2x0.84mm; 3.7Ã·5.3V; Lens: transparent; 2kHz")
      (fields (field (name "MF") "WorldSemi"))
      (libsource (lib "WS2812B2020") (part "WS2812B2020"))
    )
    (comp (ref "D133")
      (value "WS2812B2020")
      (footprint "XL-1010RGBC-WS2812B")
      (description "LED; SMD; 2020; RGB; 2x2x0.84mm; 3.7Ã·5.3V; Lens: transparent; 2kHz")
      (fields (field (name "MF") "WorldSemi"))
      (libsource (lib "WS2812B2020") (part "WS2812B2020"))
    )
    (comp (ref "D134")
      (value "WS2812B2020")
      (footprint "XL-1010RGBC-WS2812B")
      (description "LED; SMD; 2020; RGB; 2x2x0.84mm; 3.7Ã·5.3V; Lens: transparent; 2kHz")
      (fields (field (name "MF") "WorldSemi"))
      (libsource (lib "WS2812B2020") (part "WS2812B2020"))
    )
    (comp (ref "D135")
      (value "WS2812B2020")
      (footprint "XL-1010RGBC-WS2812B")
      (description "LED; SMD; 2020; RGB; 2x2x0.84mm; 3.7Ã·5.3V; Lens: transparent; 2kHz")
      (fields (field (name "MF") "WorldSemi"))
      (libsource (lib "WS2812B2020") (part "WS2812B2020"))
    )
    (comp (ref "D136")
      (value "WS2812B2020")
      (footprint "XL-1010RGBC-WS2812B")
      (description "LED; SMD; 2020; RGB; 2x2x0.84mm; 3.7Ã·5.3V; Lens: transparent; 2kHz")
      (fields (field (name "MF") "WorldSemi"))
      (libsource (lib "WS2812B2020") (part "WS2812B2020"))
    )
    (comp (ref "D137")
      (value "WS2812B2020")
      (footprint "XL-1010RGBC-WS2812B")
      (description "LED; SMD; 2020; RGB; 2x2x0.84mm; 3.7Ã·5.3V; Lens: transparent; 2kHz")
      (fields (field (name "MF") "WorldSemi"))
      (libsource (lib "WS2812B2020") (part "WS2812B2020"))
    )
    (comp (ref "D138")
      (value "WS2812B2020")
      (footprint "XL-1010RGBC-WS2812B")
      (description "LED; SMD; 2020; RGB; 2x2x0.84mm; 3.7Ã·5.3V; Lens: transparent; 2kHz")
      (fields (field (name "MF") "WorldSemi"))
      (libsource (lib "WS2812B2020") (part "WS2812B2020"))
    )
    (comp (ref "D139")
      (value "WS2812B2020")
      (footprint "XL-1010RGBC-WS2812B")
      (description "LED; SMD; 2020; RGB; 2x2x0.84mm; 3.7Ã·5.3V; Lens: transparent; 2kHz")
      (fields (field (name "MF") "WorldSemi"))
      (libsource (lib "WS2812B2020") (part "WS2812B2020"))
    )
    (comp (ref "D140")
      (value "WS2812B2020")
      (footprint "XL-1010RGBC-WS2812B")
      (description "LED; SMD; 2020; RGB; 2x2x0.84mm; 3.7Ã·5.3V; Lens: transparent; 2kHz")
      (fields (field (name "MF") "WorldSemi"))
      (libsource (lib "WS2812B2020") (part "WS2812B2020"))
    )
    (comp (ref "D141")
      (value "WS2812B2020")
      (footprint "XL-1010RGBC-WS2812B")
      (description "LED; SMD; 2020; RGB; 2x2x0.84mm; 3.7Ã·5.3V; Lens: transparent; 2kHz")
      (fields (field (name "MF") "WorldSemi"))
      (libsource (lib "WS2812B2020") (part "WS2812B2020"))
    )
    (comp (ref "D142")
      (value "WS2812B2020")
      (footprint "XL-1010RGBC-WS2812B")
      (description "LED; SMD; 2020; RGB; 2x2x0.84mm; 3.7Ã·5.3V; Lens: transparent; 2kHz")
      (fields (field (name "MF") "WorldSemi"))
      (libsource (lib "WS2812B2020") (part "WS2812B2020"))
    )
    (comp (ref "D143")
      (value "WS2812B2020")
      (footprint "XL-1010RGBC-WS2812B")
      (description "LED; SMD; 2020; RGB; 2x2x0.84mm; 3.7Ã·5.3V; Lens: transparent; 2kHz")
      (fields (field (name "MF") "WorldSemi"))
      (libsource (lib "WS2812B2020") (part "WS2812B2020"))
    )
    (comp (ref "D144")
      (value "WS2812B2020")
      (footprint "XL-1010RGBC-WS2812B")
      (description "LED; SMD; 2020; RGB; 2x2x0.84mm; 3.7Ã·5.3V; Lens: transparent; 2kHz")
      (fields (field (name "MF") "WorldSemi"))
      (libsource (lib "WS2812B2020") (part "WS2812B2020"))
    )
    (comp (ref "D145")
      (value "WS2812B2020")
      (footprint "XL-1010RGBC-WS2812B")
      (description "LED; SMD; 2020; RGB; 2x2x0.84mm; 3.7Ã·5.3V; Lens: transparent; 2kHz")
      (fields (field (name "MF") "WorldSemi"))
      (libsource (lib "WS2812B2020") (part "WS2812B2020"))
    )
    (comp (ref "D146")
      (value "WS2812B2020")
      (footprint "XL-1010RGBC-WS2812B")
      (description "LED; SMD; 2020; RGB; 2x2x0.84mm; 3.7Ã·5.3V; Lens: transparent; 2kHz")
      (fields (field (name "MF") "WorldSemi"))
      (libsource (lib "WS2812B2020") (part "WS2812B2020"))
    )
    (comp (ref "D147")
      (value "WS2812B2020")
      (footprint "XL-1010RGBC-WS2812B")
      (description "LED; SMD; 2020; RGB; 2x2x0.84mm; 3.7Ã·5.3V; Lens: transparent; 2kHz")
      (fields (field (name "MF") "WorldSemi"))
      (libsource (lib "WS2812B2020") (part "WS2812B2020"))
    )
    (comp (ref "D148")
      (value "WS2812B2020")
      (footprint "XL-1010RGBC-WS2812B")
      (description "LED; SMD; 2020; RGB; 2x2x0.84mm; 3.7Ã·5.3V; Lens: transparent; 2kHz")
      (fields (field (name "MF") "WorldSemi"))
      (libsource (lib "WS2812B2020") (part "WS2812B2020"))
    )
    (comp (ref "D149")
      (value "WS2812B2020")
      (footprint "XL-1010RGBC-WS2812B")
      (description "LED; SMD; 2020; RGB; 2x2x0.84mm; 3.7Ã·5.3V; Lens: transparent; 2kHz")
      (fields (field (name "MF") "WorldSemi"))
      (libsource (lib "WS2812B2020") (part "WS2812B2020"))
    )
    (comp (ref "D150")
      (value "WS2812B2020")
      (footprint "XL-1010RGBC-WS2812B")
      (description "LED; SMD; 2020; RGB; 2x2x0.84mm; 3.7Ã·5.3V; Lens: transparent; 2kHz")
      (fields (field (name "MF") "WorldSemi"))
      (libsource (lib "WS2812B2020") (part "WS2812B2020"))
    )
    (comp (ref "D151")
      (value "WS2812B2020")
      (footprint "XL-1010RGBC-WS2812B")
      (description "LED; SMD; 2020; RGB; 2x2x0.84mm; 3.7Ã·5.3V; Lens: transparent; 2kHz")
      (fields (field (name "MF") "WorldSemi"))
      (libsource (lib "WS2812B2020") (part "WS2812B2020"))
    )
    (comp (ref "D152")
      (value "WS2812B2020")
      (footprint "XL-1010RGBC-WS2812B")
      (description "LED; SMD; 2020; RGB; 2x2x0.84mm; 3.7Ã·5.3V; Lens: transparent; 2kHz")
      (fields (field (name "MF") "WorldSemi"))
      (libsource (lib "WS2812B2020") (part "WS2812B2020"))
    )
    (comp (ref "D153")
      (value "WS2812B2020")
      (footprint "XL-1010RGBC-WS2812B")
      (description "LED; SMD; 2020; RGB; 2x2x0.84mm; 3.7Ã·5.3V; Lens: transparent; 2kHz")
      (fields (field (name "MF") "WorldSemi"))
      (libsource (lib "WS2812B2020") (part "WS2812B2020"))
    )
    (comp (ref "D154")
      (value "WS2812B2020")
      (footprint "XL-1010RGBC-WS2812B")
      (description "LED; SMD; 2020; RGB; 2x2x0.84mm; 3.7Ã·5.3V; Lens: transparent; 2kHz")
      (fields (field (name "MF") "WorldSemi"))
      (libsource (lib "WS2812B2020") (part "WS2812B2020"))
    )
    (comp (ref "D155")
      (value "WS2812B2020")
      (footprint "XL-1010RGBC-WS2812B")
      (description "LED; SMD; 2020; RGB; 2x2x0.84mm; 3.7Ã·5.3V; Lens: transparent; 2kHz")
      (fields (field (name "MF") "WorldSemi"))
      (libsource (lib "WS2812B2020") (part "WS2812B2020"))
    )
    (comp (ref "D156")
      (value "WS2812B2020")
      (footprint "XL-1010RGBC-WS2812B")
      (description "LED; SMD; 2020; RGB; 2x2x0.84mm; 3.7Ã·5.3V; Lens: transparent; 2kHz")
      (fields (field (name "MF") "WorldSemi"))
      (libsource (lib "WS2812B2020") (part "WS2812B2020"))
    )
    (comp (ref "D157")
      (value "WS2812B2020")
      (footprint "XL-1010RGBC-WS2812B")
      (description "LED; SMD; 2020; RGB; 2x2x0.84mm; 3.7Ã·5.3V; Lens: transparent; 2kHz")
      (fields (field (name "MF") "WorldSemi"))
      (libsource (lib "WS2812B2020") (part "WS2812B2020"))
    )
    (comp (ref "D158")
      (value "WS2812B2020")
      (footprint "XL-1010RGBC-WS2812B")
      (description "LED; SMD; 2020; RGB; 2x2x0.84mm; 3.7Ã·5.3V; Lens: transparent; 2kHz")
      (fields (field (name "MF") "WorldSemi"))
      (libsource (lib "WS2812B2020") (part "WS2812B2020"))
    )
    (comp (ref "D159")
      (value "WS2812B2020")
      (footprint "XL-1010RGBC-WS2812B")
      (description "LED; SMD; 2020; RGB; 2x2x0.84mm; 3.7Ã·5.3V; Lens: transparent; 2kHz")
      (fields (field (name "MF") "WorldSemi"))
      (libsource (lib "WS2812B2020") (part "WS2812B2020"))
    )
    (comp (ref "D160")
      (value "WS2812B2020")
      (footprint "XL-1010RGBC-WS2812B")
      (description "LED; SMD; 2020; RGB; 2x2x0.84mm; 3.7Ã·5.3V; Lens: transparent; 2kHz")
      (fields (field (name "MF") "WorldSemi"))
      (libsource (lib "WS2812B2020") (part "WS2812B2020"))
    )
    (comp (ref "D161")
      (value "WS2812B2020")
      (footprint "XL-1010RGBC-WS2812B")
      (description "LED; SMD; 2020; RGB; 2x2x0.84mm; 3.7Ã·5.3V; Lens: transparent; 2kHz")
      (fields (field (name "MF") "WorldSemi"))
      (libsource (lib "WS2812B2020") (part "WS2812B2020"))
    )
    (comp (ref "D162")
      (value "WS2812B2020")
      (footprint "XL-1010RGBC-WS2812B")
      (description "LED; SMD; 2020; RGB; 2x2x0.84mm; 3.7Ã·5.3V; Lens: transparent; 2kHz")
      (fields (field (name "MF") "WorldSemi"))
      (libsource (lib "WS2812B2020") (part "WS2812B2020"))
    )
    (comp (ref "D163")
      (value "WS2812B2020")
      (footprint "XL-1010RGBC-WS2812B")
      (description "LED; SMD; 2020; RGB; 2x2x0.84mm; 3.7Ã·5.3V; Lens: transparent; 2kHz")
      (fields (field (name "MF") "WorldSemi"))
      (libsource (lib "WS2812B2020") (part "WS2812B2020"))
    )
    (comp (ref "D164")
      (value "WS2812B2020")
      (footprint "XL-1010RGBC-WS2812B")
      (description "LED; SMD; 2020; RGB; 2x2x0.84mm; 3.7Ã·5.3V; Lens: transparent; 2kHz")
      (fields (field (name "MF") "WorldSemi"))
      (libsource (lib "WS2812B2020") (part "WS2812B2020"))
    )
    (comp (ref "D165")
      (value "WS2812B2020")
      (footprint "XL-1010RGBC-WS2812B")
      (description "LED; SMD; 2020; RGB; 2x2x0.84mm; 3.7Ã·5.3V; Lens: transparent; 2kHz")
      (fields (field (name "MF") "WorldSemi"))
      (libsource (lib "WS2812B2020") (part "WS2812B2020"))
    )
    (comp (ref "D166")
      (value "WS2812B2020")
      (footprint "XL-1010RGBC-WS2812B")
      (description "LED; SMD; 2020; RGB; 2x2x0.84mm; 3.7Ã·5.3V; Lens: transparent; 2kHz")
      (fields (field (name "MF") "WorldSemi"))
      (libsource (lib "WS2812B2020") (part "WS2812B2020"))
    )
    (comp (ref "D167")
      (value "WS2812B2020")
      (footprint "XL-1010RGBC-WS2812B")
      (description "LED; SMD; 2020; RGB; 2x2x0.84mm; 3.7Ã·5.3V; Lens: transparent; 2kHz")
      (fields (field (name "MF") "WorldSemi"))
      (libsource (lib "WS2812B2020") (part "WS2812B2020"))
    )
    (comp (ref "D168")
      (value "WS2812B2020")
      (footprint "XL-1010RGBC-WS2812B")
      (description "LED; SMD; 2020; RGB; 2x2x0.84mm; 3.7Ã·5.3V; Lens: transparent; 2kHz")
      (fields (field (name "MF") "WorldSemi"))
      (libsource (lib "WS2812B2020") (part "WS2812B2020"))
    )
    (comp (ref "D169")
      (value "WS2812B2020")
      (footprint "XL-1010RGBC-WS2812B")
      (description "LED; SMD; 2020; RGB; 2x2x0.84mm; 3.7Ã·5.3V; Lens: transparent; 2kHz")
      (fields (field (name "MF") "WorldSemi"))
      (libsource (lib "WS2812B2020") (part "WS2812B2020"))
    )
    (comp (ref "D170")
      (value "WS2812B2020")
      (footprint "XL-1010RGBC-WS2812B")
      (description "LED; SMD; 2020; RGB; 2x2x0.84mm; 3.7Ã·5.3V; Lens: transparent; 2kHz")
      (fields (field (name "MF") "WorldSemi"))
      (libsource (lib "WS2812B2020") (part "WS2812B2020"))
    )
    (comp (ref "D171")
      (value "WS2812B2020")
      (footprint "XL-1010RGBC-WS2812B")
      (description "LED; SMD; 2020; RGB; 2x2x0.84mm; 3.7Ã·5.3V; Lens: transparent; 2kHz")
      (fields (field (name "MF") "WorldSemi"))
      (libsource (lib "WS2812B2020") (part "WS2812B2020"))
    )
    (comp (ref "D172")
      (value "WS2812B2020")
      (footprint "XL-1010RGBC-WS2812B")
      (description "LED; SMD; 2020; RGB; 2x2x0.84mm; 3.7Ã·5.3V; Lens: transparent; 2kHz")
      (fields (field (name "MF") "WorldSemi"))
      (libsource (lib "WS2812B2020") (part "WS2812B2020"))
    )
    (comp (ref "D173")
      (value "WS2812B2020")
      (footprint "XL-1010RGBC-WS2812B")
      (description "LED; SMD; 2020; RGB; 2x2x0.84mm; 3.7Ã·5.3V; Lens: transparent; 2kHz")
      (fields (field (name "MF") "WorldSemi"))
      (libsource (lib "WS2812B2020") (part "WS2812B2020"))
    )
    (comp (ref "D174")
      (value "WS2812B2020")
      (footprint "XL-1010RGBC-WS2812B")
      (description "LED; SMD; 2020; RGB; 2x2x0.84mm; 3.7Ã·5.3V; Lens: transparent; 2kHz")
      (fields (field (name "MF") "WorldSemi"))
      (libsource (lib "WS2812B2020") (part "WS2812B2020"))
    )
    (comp (ref "D175")
      (value "WS2812B2020")
      (footprint "XL-1010RGBC-WS2812B")
      (description "LED; SMD; 2020; RGB; 2x2x0.84mm; 3.7Ã·5.3V; Lens: transparent; 2kHz")
      (fields (field (name "MF") "WorldSemi"))
      (libsource (lib "WS2812B2020") (part "WS2812B2020"))
    )
    (comp (ref "D176")
      (value "WS2812B2020")
      (footprint "XL-1010RGBC-WS2812B")
      (description "LED; SMD; 2020; RGB; 2x2x0.84mm; 3.7Ã·5.3V; Lens: transparent; 2kHz")
      (fields (field (name "MF") "WorldSemi"))
      (libsource (lib "WS2812B2020") (part "WS2812B2020"))
    )
    (comp (ref "D177")
      (value "WS2812B2020")
      (footprint "XL-1010RGBC-WS2812B")
      (description "LED; SMD; 2020; RGB; 2x2x0.84mm; 3.7Ã·5.3V; Lens: transparent; 2kHz")
      (fields (field (name "MF") "WorldSemi"))
      (libsource (lib "WS2812B2020") (part "WS2812B2020"))
    )
    (comp (ref "D178")
      (value "WS2812B2020")
      (footprint "XL-1010RGBC-WS2812B")
      (description "LED; SMD; 2020; RGB; 2x2x0.84mm; 3.7Ã·5.3V; Lens: transparent; 2kHz")
      (fields (field (name "MF") "WorldSemi"))
      (libsource (lib "WS2812B2020") (part "WS2812B2020"))
    )
    (comp (ref "D179")
      (value "WS2812B2020")
      (footprint "XL-1010RGBC-WS2812B")
      (description "LED; SMD; 2020; RGB; 2x2x0.84mm; 3.7Ã·5.3V; Lens: transparent; 2kHz")
      (fields (field (name "MF") "WorldSemi"))
      (libsource (lib "WS2812B2020") (part "WS2812B2020"))
    )
    (comp (ref "D180")
      (value "WS2812B2020")
      (footprint "XL-1010RGBC-WS2812B")
      (description "LED; SMD; 2020; RGB; 2x2x0.84mm; 3.7Ã·5.3V; Lens: transparent; 2kHz")
      (fields (field (name "MF") "WorldSemi"))
      (libsource (lib "WS2812B2020") (part "WS2812B2020"))
    )
    (comp (ref "D181")
      (value "WS2812B2020")
      (footprint "XL-1010RGBC-WS2812B")
      (description "LED; SMD; 2020; RGB; 2x2x0.84mm; 3.7Ã·5.3V; Lens: transparent; 2kHz")
      (fields (field (name "MF") "WorldSemi"))
      (libsource (lib "WS2812B2020") (part "WS2812B2020"))
    )
    (comp (ref "D182")
      (value "WS2812B2020")
      (footprint "XL-1010RGBC-WS2812B")
      (description "LED; SMD; 2020; RGB; 2x2x0.84mm; 3.7Ã·5.3V; Lens: transparent; 2kHz")
      (fields (field (name "MF") "WorldSemi"))
      (libsource (lib "WS2812B2020") (part "WS2812B2020"))
    )
    (comp (ref "D183")
      (value "WS2812B2020")
      (footprint "XL-1010RGBC-WS2812B")
      (description "LED; SMD; 2020; RGB; 2x2x0.84mm; 3.7Ã·5.3V; Lens: transparent; 2kHz")
      (fields (field (name "MF") "WorldSemi"))
      (libsource (lib "WS2812B2020") (part "WS2812B2020"))
    )
    (comp (ref "D184")
      (value "WS2812B2020")
      (footprint "XL-1010RGBC-WS2812B")
      (description "LED; SMD; 2020; RGB; 2x2x0.84mm; 3.7Ã·5.3V; Lens: transparent; 2kHz")
      (fields (field (name "MF") "WorldSemi"))
      (libsource (lib "WS2812B2020") (part "WS2812B2020"))
    )
    (comp (ref "D185")
      (value "WS2812B2020")
      (footprint "XL-1010RGBC-WS2812B")
      (description "LED; SMD; 2020; RGB; 2x2x0.84mm; 3.7Ã·5.3V; Lens: transparent; 2kHz")
      (fields (field (name "MF") "WorldSemi"))
      (libsource (lib "WS2812B2020") (part "WS2812B2020"))
    )
    (comp (ref "D186")
      (value "WS2812B2020")
      (footprint "XL-1010RGBC-WS2812B")
      (description "LED; SMD; 2020; RGB; 2x2x0.84mm; 3.7Ã·5.3V; Lens: transparent; 2kHz")
      (fields (field (name "MF") "WorldSemi"))
      (libsource (lib "WS2812B2020") (part "WS2812B2020"))
    )
    (comp (ref "D187")
      (value "WS2812B2020")
      (footprint "XL-1010RGBC-WS2812B")
      (description "LED; SMD; 2020; RGB; 2x2x0.84mm; 3.7Ã·5.3V; Lens: transparent; 2kHz")
      (fields (field (name "MF") "WorldSemi"))
      (libsource (lib "WS2812B2020") (part "WS2812B2020"))
    )
    (comp (ref "D188")
      (value "WS2812B2020")
      (footprint "XL-1010RGBC-WS2812B")
      (description "LED; SMD; 2020; RGB; 2x2x0.84mm; 3.7Ã·5.3V; Lens: transparent; 2kHz")
      (fields (field (name "MF") "WorldSemi"))
      (libsource (lib "WS2812B2020") (part "WS2812B2020"))
    )
    (comp (ref "D189")
      (value "WS2812B2020")
      (footprint "XL-1010RGBC-WS2812B")
      (description "LED; SMD; 2020; RGB; 2x2x0.84mm; 3.7Ã·5.3V; Lens: transparent; 2kHz")
      (fields (field (name "MF") "WorldSemi"))
      (libsource (lib "WS2812B2020") (part "WS2812B2020"))
    )
    (comp (ref "D190")
      (value "WS2812B2020")
      (footprint "XL-1010RGBC-WS2812B")
      (description "LED; SMD; 2020; RGB; 2x2x0.84mm; 3.7Ã·5.3V; Lens: transparent; 2kHz")
      (fields (field (name "MF") "WorldSemi"))
      (libsource (lib "WS2812B2020") (part "WS2812B2020"))
    )
    (comp (ref "D191")
      (value "WS2812B2020")
      (footprint "XL-1010RGBC-WS2812B")
      (description "LED; SMD; 2020; RGB; 2x2x0.84mm; 3.7Ã·5.3V; Lens: transparent; 2kHz")
      (fields (field (name "MF") "WorldSemi"))
      (libsource (lib "WS2812B2020") (part "WS2812B2020"))
    )
    (comp (ref "D192")
      (value "WS2812B2020")
      (footprint "XL-1010RGBC-WS2812B")
      (description "LED; SMD; 2020; RGB; 2x2x0.84mm; 3.7Ã·5.3V; Lens: transparent; 2kHz")
      (fields (field (name "MF") "WorldSemi"))
      (libsource (lib "WS2812B2020") (part "WS2812B2020"))
    )
    (comp (ref "D193")
      (value "WS2812B2020")
      (footprint "XL-1010RGBC-WS2812B")
      (description "LED; SMD; 2020; RGB; 2x2x0.84mm; 3.7Ã·5.3V; Lens: transparent; 2kHz")
      (fields (field (name "MF") "WorldSemi"))
      (libsource (lib "WS2812B2020") (part "WS2812B2020"))
    )
    (comp (ref "D194")
      (value "WS2812B2020")
      (footprint "XL-1010RGBC-WS2812B")
      (description "LED; SMD; 2020; RGB; 2x2x0.84mm; 3.7Ã·5.3V; Lens: transparent; 2kHz")
      (fields (field (name "MF") "WorldSemi"))
      (libsource (lib "WS2812B2020") (part "WS2812B2020"))
    )
    (comp (ref "D195")
      (value "WS2812B2020")
      (footprint "XL-1010RGBC-WS2812B")
      (description "LED; SMD; 2020; RGB; 2x2x0.84mm; 3.7Ã·5.3V; Lens: transparent; 2kHz")
      (fields (field (name "MF") "WorldSemi"))
      (libsource (lib "WS2812B2020") (part "WS2812B2020"))
    )
    (comp (ref "D196")
      (value "WS2812B2020")
      (footprint "XL-1010RGBC-WS2812B")
      (description "LED; SMD; 2020; RGB; 2x2x0.84mm; 3.7Ã·5.3V; Lens: transparent; 2kHz")
      (fields (field (name "MF") "WorldSemi"))
      (libsource (lib "WS2812B2020") (part "WS2812B2020"))
    )
    (comp (ref "D197")
      (value "WS2812B2020")
      (footprint "XL-1010RGBC-WS2812B")
      (description "LED; SMD; 2020; RGB; 2x2x0.84mm; 3.7Ã·5.3V; Lens: transparent; 2kHz")
      (fields (field (name "MF") "WorldSemi"))
      (libsource (lib "WS2812B2020") (part "WS2812B2020"))
    )
    (comp (ref "D198")
      (value "WS2812B2020")
      (footprint "XL-1010RGBC-WS2812B")
      (description "LED; SMD; 2020; RGB; 2x2x0.84mm; 3.7Ã·5.3V; Lens: transparent; 2kHz")
      (fields (field (name "MF") "WorldSemi"))
      (libsource (lib "WS2812B2020") (part "WS2812B2020"))
    )
    (comp (ref "D199")
      (value "WS2812B2020")
      (footprint "XL-1010RGBC-WS2812B")
      (description "LED; SMD; 2020; RGB; 2x2x0.84mm; 3.7Ã·5.3V; Lens: transparent; 2kHz")
      (fields (field (name "MF") "WorldSemi"))
      (libsource (lib "WS2812B2020") (part "WS2812B2020"))
    )
    (comp (ref "D200")
      (value "WS2812B2020")
      (footprint "XL-1010RGBC-WS2812B")
      (description "LED; SMD; 2020; RGB; 2x2x0.84mm; 3.7Ã·5.3V; Lens: transparent; 2kHz")
      (fields (field (name "MF") "WorldSemi"))
      (libsource (lib "WS2812B2020") (part "WS2812B2020"))
    )
    (comp (ref "D201")
      (value "WS2812B2020")
      (footprint "XL-1010RGBC-WS2812B")
      (description "LED; SMD; 2020; RGB; 2x2x0.84mm; 3.7Ã·5.3V; Lens: transparent; 2kHz")
      (fields (field (name "MF") "WorldSemi"))
      (libsource (lib "WS2812B2020") (part "WS2812B2020"))
    )
    (comp (ref "D202")
      (value "WS2812B2020")
      (footprint "XL-1010RGBC-WS2812B")
      (description "LED; SMD; 2020; RGB; 2x2x0.84mm; 3.7Ã·5.3V; Lens: transparent; 2kHz")
      (fields (field (name "MF") "WorldSemi"))
      (libsource (lib "WS2812B2020") (part "WS2812B2020"))
    )
    (comp (ref "D203")
      (value "WS2812B2020")
      (footprint "XL-1010RGBC-WS2812B")
      (description "LED; SMD; 2020; RGB; 2x2x0.84mm; 3.7Ã·5.3V; Lens: transparent; 2kHz")
      (fields (field (name "MF") "WorldSemi"))
      (libsource (lib "WS2812B2020") (part "WS2812B2020"))
    )
    (comp (ref "D204")
      (value "WS2812B2020")
      (footprint "XL-1010RGBC-WS2812B")
      (description "LED; SMD; 2020; RGB; 2x2x0.84mm; 3.7Ã·5.3V; Lens: transparent; 2kHz")
      (fields (field (name "MF") "WorldSemi"))
      (libsource (lib "WS2812B2020") (part "WS2812B2020"))
    )
    (comp (ref "D205")
      (value "WS2812B2020")
      (footprint "XL-1010RGBC-WS2812B")
      (description "LED; SMD; 2020; RGB; 2x2x0.84mm; 3.7Ã·5.3V; Lens: transparent; 2kHz")
      (fields (field (name "MF") "WorldSemi"))
      (libsource (lib "WS2812B2020") (part "WS2812B2020"))
    )
    (comp (ref "D206")
      (value "WS2812B2020")
      (footprint "XL-1010RGBC-WS2812B")
      (description "LED; SMD; 2020; RGB; 2x2x0.84mm; 3.7Ã·5.3V; Lens: transparent; 2kHz")
      (fields (field (name "MF") "WorldSemi"))
      (libsource (lib "WS2812B2020") (part "WS2812B2020"))
    )
    (comp (ref "D207")
      (value "WS2812B2020")
      (footprint "XL-1010RGBC-WS2812B")
      (description "LED; SMD; 2020; RGB; 2x2x0.84mm; 3.7Ã·5.3V; Lens: transparent; 2kHz")
      (fields (field (name "MF") "WorldSemi"))
      (libsource (lib "WS2812B2020") (part "WS2812B2020"))
    )
    (comp (ref "D208")
      (value "WS2812B2020")
      (footprint "XL-1010RGBC-WS2812B")
      (description "LED; SMD; 2020; RGB; 2x2x0.84mm; 3.7Ã·5.3V; Lens: transparent; 2kHz")
      (fields (field (name "MF") "WorldSemi"))
      (libsource (lib "WS2812B2020") (part "WS2812B2020"))
    )
    (comp (ref "D209")
      (value "WS2812B2020")
      (footprint "XL-1010RGBC-WS2812B")
      (description "LED; SMD; 2020; RGB; 2x2x0.84mm; 3.7Ã·5.3V; Lens: transparent; 2kHz")
      (fields (field (name "MF") "WorldSemi"))
      (libsource (lib "WS2812B2020") (part "WS2812B2020"))
    )
    (comp (ref "D210")
      (value "WS2812B2020")
      (footprint "XL-1010RGBC-WS2812B")
      (description "LED; SMD; 2020; RGB; 2x2x0.84mm; 3.7Ã·5.3V; Lens: transparent; 2kHz")
      (fields (field (name "MF") "WorldSemi"))
      (libsource (lib "WS2812B2020") (part "WS2812B2020"))
    )
    (comp (ref "D211")
      (value "WS2812B2020")
      (footprint "XL-1010RGBC-WS2812B")
      (description "LED; SMD; 2020; RGB; 2x2x0.84mm; 3.7Ã·5.3V; Lens: transparent; 2kHz")
      (fields (field (name "MF") "WorldSemi"))
      (libsource (lib "WS2812B2020") (part "WS2812B2020"))
    )
    (comp (ref "D212")
      (value "WS2812B2020")
      (footprint "XL-1010RGBC-WS2812B")
      (description "LED; SMD; 2020; RGB; 2x2x0.84mm; 3.7Ã·5.3V; Lens: transparent; 2kHz")
      (fields (field (name "MF") "WorldSemi"))
      (libsource (lib "WS2812B2020") (part "WS2812B2020"))
    )
    (comp (ref "D213")
      (value "WS2812B2020")
      (footprint "XL-1010RGBC-WS2812B")
      (description "LED; SMD; 2020; RGB; 2x2x0.84mm; 3.7Ã·5.3V; Lens: transparent; 2kHz")
      (fields (field (name "MF") "WorldSemi"))
      (libsource (lib "WS2812B2020") (part "WS2812B2020"))
    )
    (comp (ref "D214")
      (value "WS2812B2020")
      (footprint "XL-1010RGBC-WS2812B")
      (description "LED; SMD; 2020; RGB; 2x2x0.84mm; 3.7Ã·5.3V; Lens: transparent; 2kHz")
      (fields (field (name "MF") "WorldSemi"))
      (libsource (lib "WS2812B2020") (part "WS2812B2020"))
    )
    (comp (ref "D215")
      (value "WS2812B2020")
      (footprint "XL-1010RGBC-WS2812B")
      (description "LED; SMD; 2020; RGB; 2x2x0.84mm; 3.7Ã·5.3V; Lens: transparent; 2kHz")
      (fields (field (name "MF") "WorldSemi"))
      (libsource (lib "WS2812B2020") (part "WS2812B2020"))
    )
    (comp (ref "D216")
      (value "WS2812B2020")
      (footprint "XL-1010RGBC-WS2812B")
      (description "LED; SMD; 2020; RGB; 2x2x0.84mm; 3.7Ã·5.3V; Lens: transparent; 2kHz")
      (fields (field (name "MF") "WorldSemi"))
      (libsource (lib "WS2812B2020") (part "WS2812B2020"))
    )
    (comp (ref "D217")
      (value "WS2812B2020")
      (footprint "XL-1010RGBC-WS2812B")
      (description "LED; SMD; 2020; RGB; 2x2x0.84mm; 3.7Ã·5.3V; Lens: transparent; 2kHz")
      (fields (field (name "MF") "WorldSemi"))
      (libsource (lib "WS2812B2020") (part "WS2812B2020"))
    )
    (comp (ref "D218")
      (value "WS2812B2020")
      (footprint "XL-1010RGBC-WS2812B")
      (description "LED; SMD; 2020; RGB; 2x2x0.84mm; 3.7Ã·5.3V; Lens: transparent; 2kHz")
      (fields (field (name "MF") "WorldSemi"))
      (libsource (lib "WS2812B2020") (part "WS2812B2020"))
    )
    (comp (ref "D219")
      (value "WS2812B2020")
      (footprint "XL-1010RGBC-WS2812B")
      (description "LED; SMD; 2020; RGB; 2x2x0.84mm; 3.7Ã·5.3V; Lens: transparent; 2kHz")
      (fields (field (name "MF") "WorldSemi"))
      (libsource (lib "WS2812B2020") (part "WS2812B2020"))
    )
    (comp (ref "D220")
      (value "WS2812B2020")
      (footprint "XL-1010RGBC-WS2812B")
      (description "LED; SMD; 2020; RGB; 2x2x0.84mm; 3.7Ã·5.3V; Lens: transparent; 2kHz")
      (fields (field (name "MF") "WorldSemi"))
      (libsource (lib "WS2812B2020") (part "WS2812B2020"))
    )
    (comp (ref "D221")
      (value "WS2812B2020")
      (footprint "XL-1010RGBC-WS2812B")
      (description "LED; SMD; 2020; RGB; 2x2x0.84mm; 3.7Ã·5.3V; Lens: transparent; 2kHz")
      (fields (field (name "MF") "WorldSemi"))
      (libsource (lib "WS2812B2020") (part "WS2812B2020"))
    )
    (comp (ref "D222")
      (value "WS2812B2020")
      (footprint "XL-1010RGBC-WS2812B")
      (description "LED; SMD; 2020; RGB; 2x2x0.84mm; 3.7Ã·5.3V; Lens: transparent; 2kHz")
      (fields (field (name "MF") "WorldSemi"))
      (libsource (lib "WS2812B2020") (part "WS2812B2020"))
    )
    (comp (ref "D223")
      (value "WS2812B2020")
      (footprint "XL-1010RGBC-WS2812B")
      (description "LED; SMD; 2020; RGB; 2x2x0.84mm; 3.7Ã·5.3V; Lens: transparent; 2kHz")
      (fields (field (name "MF") "WorldSemi"))
      (libsource (lib "WS2812B2020") (part "WS2812B2020"))
    )
    (comp (ref "D224")
      (value "WS2812B2020")
      (footprint "XL-1010RGBC-WS2812B")
      (description "LED; SMD; 2020; RGB; 2x2x0.84mm; 3.7Ã·5.3V; Lens: transparent; 2kHz")
      (fields (field (name "MF") "WorldSemi"))
      (libsource (lib "WS2812B2020") (part "WS2812B2020"))
    )
    (comp (ref "D225")
      (value "WS2812B2020")
      (footprint "XL-1010RGBC-WS2812B")
      (description "LED; SMD; 2020; RGB; 2x2x0.84mm; 3.7Ã·5.3V; Lens: transparent; 2kHz")
      (fields (field (name "MF") "WorldSemi"))
      (libsource (lib "WS2812B2020") (part "WS2812B2020"))
    )
    (comp (ref "D226")
      (value "WS2812B2020")
      (footprint "XL-1010RGBC-WS2812B")
      (description "LED; SMD; 2020; RGB; 2x2x0.84mm; 3.7Ã·5.3V; Lens: transparent; 2kHz")
      (fields (field (name "MF") "WorldSemi"))
      (libsource (lib "WS2812B2020") (part "WS2812B2020"))
    )
    (comp (ref "D227")
      (value "WS2812B2020")
      (footprint "XL-1010RGBC-WS2812B")
      (description "LED; SMD; 2020; RGB; 2x2x0.84mm; 3.7Ã·5.3V; Lens: transparent; 2kHz")
      (fields (field (name "MF") "WorldSemi"))
      (libsource (lib "WS2812B2020") (part "WS2812B2020"))
    )
    (comp (ref "D228")
      (value "WS2812B2020")
      (footprint "XL-1010RGBC-WS2812B")
      (description "LED; SMD; 2020; RGB; 2x2x0.84mm; 3.7Ã·5.3V; Lens: transparent; 2kHz")
      (fields (field (name "MF") "WorldSemi"))
      (libsource (lib "WS2812B2020") (part "WS2812B2020"))
    )
    (comp (ref "D229")
      (value "WS2812B2020")
      (footprint "XL-1010RGBC-WS2812B")
      (description "LED; SMD; 2020; RGB; 2x2x0.84mm; 3.7Ã·5.3V; Lens: transparent; 2kHz")
      (fields (field (name "MF") "WorldSemi"))
      (libsource (lib "WS2812B2020") (part "WS2812B2020"))
    )
    (comp (ref "D230")
      (value "WS2812B2020")
      (footprint "XL-1010RGBC-WS2812B")
      (description "LED; SMD; 2020; RGB; 2x2x0.84mm; 3.7Ã·5.3V; Lens: transparent; 2kHz")
      (fields (field (name "MF") "WorldSemi"))
      (libsource (lib "WS2812B2020") (part "WS2812B2020"))
    )
    (comp (ref "D231")
      (value "WS2812B2020")
      (footprint "XL-1010RGBC-WS2812B")
      (description "LED; SMD; 2020; RGB; 2x2x0.84mm; 3.7Ã·5.3V; Lens: transparent; 2kHz")
      (fields (field (name "MF") "WorldSemi"))
      (libsource (lib "WS2812B2020") (part "WS2812B2020"))
    )
    (comp (ref "D232")
      (value "WS2812B2020")
      (footprint "XL-1010RGBC-WS2812B")
      (description "LED; SMD; 2020; RGB; 2x2x0.84mm; 3.7Ã·5.3V; Lens: transparent; 2kHz")
      (fields (field (name "MF") "WorldSemi"))
      (libsource (lib "WS2812B2020") (part "WS2812B2020"))
    )
    (comp (ref "D233")
      (value "WS2812B2020")
      (footprint "XL-1010RGBC-WS2812B")
      (description "LED; SMD; 2020; RGB; 2x2x0.84mm; 3.7Ã·5.3V; Lens: transparent; 2kHz")
      (fields (field (name "MF") "WorldSemi"))
      (libsource (lib "WS2812B2020") (part "WS2812B2020"))
    )
    (comp (ref "D234")
      (value "WS2812B2020")
      (footprint "XL-1010RGBC-WS2812B")
      (description "LED; SMD; 2020; RGB; 2x2x0.84mm; 3.7Ã·5.3V; Lens: transparent; 2kHz")
      (fields (field (name "MF") "WorldSemi"))
      (libsource (lib "WS2812B2020") (part "WS2812B2020"))
    )
    (comp (ref "D235")
      (value "WS2812B2020")
      (footprint "XL-1010RGBC-WS2812B")
      (description "LED; SMD; 2020; RGB; 2x2x0.84mm; 3.7Ã·5.3V; Lens: transparent; 2kHz")
      (fields (field (name "MF") "WorldSemi"))
      (libsource (lib "WS2812B2020") (part "WS2812B2020"))
    )
    (comp (ref "D236")
      (value "WS2812B2020")
      (footprint "XL-1010RGBC-WS2812B")
      (description "LED; SMD; 2020; RGB; 2x2x0.84mm; 3.7Ã·5.3V; Lens: transparent; 2kHz")
      (fields (field (name "MF") "WorldSemi"))
      (libsource (lib "WS2812B2020") (part "WS2812B2020"))
    )
    (comp (ref "D237")
      (value "WS2812B2020")
      (footprint "XL-1010RGBC-WS2812B")
      (description "LED; SMD; 2020; RGB; 2x2x0.84mm; 3.7Ã·5.3V; Lens: transparent; 2kHz")
      (fields (field (name "MF") "WorldSemi"))
      (libsource (lib "WS2812B2020") (part "WS2812B2020"))
    )
    (comp (ref "D238")
      (value "WS2812B2020")
      (footprint "XL-1010RGBC-WS2812B")
      (description "LED; SMD; 2020; RGB; 2x2x0.84mm; 3.7Ã·5.3V; Lens: transparent; 2kHz")
      (fields (field (name "MF") "WorldSemi"))
      (libsource (lib "WS2812B2020") (part "WS2812B2020"))
    )
    (comp (ref "D239")
      (value "WS2812B2020")
      (footprint "XL-1010RGBC-WS2812B")
      (description "LED; SMD; 2020; RGB; 2x2x0.84mm; 3.7Ã·5.3V; Lens: transparent; 2kHz")
      (fields (field (name "MF") "WorldSemi"))
      (libsource (lib "WS2812B2020") (part "WS2812B2020"))
    )
    (comp (ref "D240")
      (value "WS2812B2020")
      (footprint "XL-1010RGBC-WS2812B")
      (description "LED; SMD; 2020; RGB; 2x2x0.84mm; 3.7Ã·5.3V; Lens: transparent; 2kHz")
      (fields (field (name "MF") "WorldSemi"))
      (libsource (lib "WS2812B2020") (part "WS2812B2020"))
    )
    (comp (ref "D241")
      (value "WS2812B2020")
      (footprint "XL-1010RGBC-WS2812B")
      (description "LED; SMD; 2020; RGB; 2x2x0.84mm; 3.7Ã·5.3V; Lens: transparent; 2kHz")
      (fields (field (name "MF") "WorldSemi"))
      (libsource (lib "WS2812B2020") (part "WS2812B2020"))
    )
    (comp (ref "D242")
      (value "WS2812B2020")
      (footprint "XL-1010RGBC-WS2812B")
      (description "LED; SMD; 2020; RGB; 2x2x0.84mm; 3.7Ã·5.3V; Lens: transparent; 2kHz")
      (fields (field (name "MF") "WorldSemi"))
      (libsource (lib "WS2812B2020") (part "WS2812B2020"))
    )
    (comp (ref "D243")
      (value "WS2812B2020")
      (footprint "XL-1010RGBC-WS2812B")
      (description "LED; SMD; 2020; RGB; 2x2x0.84mm; 3.7Ã·5.3V; Lens: transparent; 2kHz")
      (fields (field (name "MF") "WorldSemi"))
      (libsource (lib "WS2812B2020") (part "WS2812B2020"))
    )
    (comp (ref "D244")
      (value "WS2812B2020")
      (footprint "XL-1010RGBC-WS2812B")
      (description "LED; SMD; 2020; RGB; 2x2x0.84mm; 3.7Ã·5.3V; Lens: transparent; 2kHz")
      (fields (field (name "MF") "WorldSemi"))
      (libsource (lib "WS2812B2020") (part "WS2812B2020"))
    )
    (comp (ref "D245")
      (value "WS2812B2020")
      (footprint "XL-1010RGBC-WS2812B")
      (description "LED; SMD; 2020; RGB; 2x2x0.84mm; 3.7Ã·5.3V; Lens: transparent; 2kHz")
      (fields (field (name "MF") "WorldSemi"))
      (libsource (lib "WS2812B2020") (part "WS2812B2020"))
    )
    (comp (ref "D246")
      (value "WS2812B2020")
      (footprint "XL-1010RGBC-WS2812B")
      (description "LED; SMD; 2020; RGB; 2x2x0.84mm; 3.7Ã·5.3V; Lens: transparent; 2kHz")
      (fields (field (name "MF") "WorldSemi"))
      (libsource (lib "WS2812B2020") (part "WS2812B2020"))
    )
    (comp (ref "D247")
      (value "WS2812B2020")
      (footprint "XL-1010RGBC-WS2812B")
      (description "LED; SMD; 2020; RGB; 2x2x0.84mm; 3.7Ã·5.3V; Lens: transparent; 2kHz")
      (fields (field (name "MF") "WorldSemi"))
      (libsource (lib "WS2812B2020") (part "WS2812B2020"))
    )
    (comp (ref "D248")
      (value "WS2812B2020")
      (footprint "XL-1010RGBC-WS2812B")
      (description "LED; SMD; 2020; RGB; 2x2x0.84mm; 3.7Ã·5.3V; Lens: transparent; 2kHz")
      (fields (field (name "MF") "WorldSemi"))
      (libsource (lib "WS2812B2020") (part "WS2812B2020"))
    )
    (comp (ref "D249")
      (value "WS2812B2020")
      (footprint "XL-1010RGBC-WS2812B")
      (description "LED; SMD; 2020; RGB; 2x2x0.84mm; 3.7Ã·5.3V; Lens: transparent; 2kHz")
      (fields (field (name "MF") "WorldSemi"))
      (libsource (lib "WS2812B2020") (part "WS2812B2020"))
    )
    (comp (ref "D250")
      (value "WS2812B2020")
      (footprint "XL-1010RGBC-WS2812B")
      (description "LED; SMD; 2020; RGB; 2x2x0.84mm; 3.7Ã·5.3V; Lens: transparent; 2kHz")
      (fields (field (name "MF") "WorldSemi"))
      (libsource (lib "WS2812B2020") (part "WS2812B2020"))
    )
    (comp (ref "D251")
      (value "WS2812B2020")
      (footprint "XL-1010RGBC-WS2812B")
      (description "LED; SMD; 2020; RGB; 2x2x0.84mm; 3.7Ã·5.3V; Lens: transparent; 2kHz")
      (fields (field (name "MF") "WorldSemi"))
      (libsource (lib "WS2812B2020") (part "WS2812B2020"))
    )
    (comp (ref "D252")
      (value "WS2812B2020")
      (footprint "XL-1010RGBC-WS2812B")
      (description "LED; SMD; 2020; RGB; 2x2x0.84mm; 3.7Ã·5.3V; Lens: transparent; 2kHz")
      (fields (field (name "MF") "WorldSemi"))
      (libsource (lib "WS2812B2020") (part "WS2812B2020"))
    )
    (comp (ref "D253")
      (value "WS2812B2020")
      (footprint "XL-1010RGBC-WS2812B")
      (description "LED; SMD; 2020; RGB; 2x2x0.84mm; 3.7Ã·5.3V; Lens: transparent; 2kHz")
      (fields (field (name "MF") "WorldSemi"))
      (libsource (lib "WS2812B2020") (part "WS2812B2020"))
    )
    (comp (ref "D254")
      (value "WS2812B2020")
      (footprint "XL-1010RGBC-WS2812B")
      (description "LED; SMD; 2020; RGB; 2x2x0.84mm; 3.7Ã·5.3V; Lens: transparent; 2kHz")
      (fields (field (name "MF") "WorldSemi"))
      (libsource (lib "WS2812B2020") (part "WS2812B2020"))
    )
    (comp (ref "D255")
      (value "WS2812B2020")
      (footprint "XL-1010RGBC-WS2812B")
      (description "LED; SMD; 2020; RGB; 2x2x0.84mm; 3.7Ã·5.3V; Lens: transparent; 2kHz")
      (fields (field (name "MF") "WorldSemi"))
      (libsource (lib "WS2812B2020") (part "WS2812B2020"))
    )
    (comp (ref "D256")
      (value "WS2812B2020")
      (footprint "XL-1010RGBC-WS2812B")
      (description "LED; SMD; 2020; RGB; 2x2x0.84mm; 3.7Ã·5.3V; Lens: transparent; 2kHz")
      (fields (field (name "MF") "WorldSemi"))
      (libsource (lib "WS2812B2020") (part "WS2812B2020"))
    )
    (comp (ref "D257")
      (value "WS2812B2020")
      (footprint "XL-1010RGBC-WS2812B")
      (description "LED; SMD; 2020; RGB; 2x2x0.84mm; 3.7Ã·5.3V; Lens: transparent; 2kHz")
      (fields (field (name "MF") "WorldSemi"))
      (libsource (lib "WS2812B2020") (part "WS2812B2020"))
    )
    (comp (ref "D258")
      (value "WS2812B2020")
      (footprint "XL-1010RGBC-WS2812B")
      (description "LED; SMD; 2020; RGB; 2x2x0.84mm; 3.7Ã·5.3V; Lens: transparent; 2kHz")
      (fields (field (name "MF") "WorldSemi"))
      (libsource (lib "WS2812B2020") (part "WS2812B2020"))
    )
    (comp (ref "D259")
      (value "WS2812B2020")
      (footprint "XL-1010RGBC-WS2812B")
      (description "LED; SMD; 2020; RGB; 2x2x0.84mm; 3.7Ã·5.3V; Lens: transparent; 2kHz")
      (fields (field (name "MF") "WorldSemi"))
      (libsource (lib "WS2812B2020") (part "WS2812B2020"))
    )
    (comp (ref "D260")
      (value "WS2812B2020")
      (footprint "XL-1010RGBC-WS2812B")
      (description "LED; SMD; 2020; RGB; 2x2x0.84mm; 3.7Ã·5.3V; Lens: transparent; 2kHz")
      (fields (field (name "MF") "WorldSemi"))
      (libsource (lib "WS2812B2020") (part "WS2812B2020"))
    )
    (comp (ref "D261")
      (value "WS2812B2020")
      (footprint "XL-1010RGBC-WS2812B")
      (description "LED; SMD; 2020; RGB; 2x2x0.84mm; 3.7Ã·5.3V; Lens: transparent; 2kHz")
      (fields (field (name "MF") "WorldSemi"))
      (libsource (lib "WS2812B2020") (part "WS2812B2020"))
    )
    (comp (ref "D262")
      (value "WS2812B2020")
      (footprint "XL-1010RGBC-WS2812B")
      (description "LED; SMD; 2020; RGB; 2x2x0.84mm; 3.7Ã·5.3V; Lens: transparent; 2kHz")
      (fields (field (name "MF") "WorldSemi"))
      (libsource (lib "WS2812B2020") (part "WS2812B2020"))
    )
    (comp (ref "D263")
      (value "WS2812B2020")
      (footprint "XL-1010RGBC-WS2812B")
      (description "LED; SMD; 2020; RGB; 2x2x0.84mm; 3.7Ã·5.3V; Lens: transparent; 2kHz")
      (fields (field (name "MF") "WorldSemi"))
      (libsource (lib "WS2812B2020") (part "WS2812B2020"))
    )
    (comp (ref "D264")
      (value "WS2812B2020")
      (footprint "XL-1010RGBC-WS2812B")
      (description "LED; SMD; 2020; RGB; 2x2x0.84mm; 3.7Ã·5.3V; Lens: transparent; 2kHz")
      (fields (field (name "MF") "WorldSemi"))
      (libsource (lib "WS2812B2020") (part "WS2812B2020"))
    )
    (comp (ref "D265")
      (value "WS2812B2020")
      (footprint "XL-1010RGBC-WS2812B")
      (description "LED; SMD; 2020; RGB; 2x2x0.84mm; 3.7Ã·5.3V; Lens: transparent; 2kHz")
      (fields (field (name "MF") "WorldSemi"))
      (libsource (lib "WS2812B2020") (part "WS2812B2020"))
    )
    (comp (ref "D266")
      (value "WS2812B2020")
      (footprint "XL-1010RGBC-WS2812B")
      (description "LED; SMD; 2020; RGB; 2x2x0.84mm; 3.7Ã·5.3V; Lens: transparent; 2kHz")
      (fields (field (name "MF") "WorldSemi"))
      (libsource (lib "WS2812B2020") (part "WS2812B2020"))
    )
    (comp (ref "D267")
      (value "WS2812B2020")
      (footprint "XL-1010RGBC-WS2812B")
      (description "LED; SMD; 2020; RGB; 2x2x0.84mm; 3.7Ã·5.3V; Lens: transparent; 2kHz")
      (fields (field (name "MF") "WorldSemi"))
      (libsource (lib "WS2812B2020") (part "WS2812B2020"))
    )
    (comp (ref "D268")
      (value "WS2812B2020")
      (footprint "XL-1010RGBC-WS2812B")
      (description "LED; SMD; 2020; RGB; 2x2x0.84mm; 3.7Ã·5.3V; Lens: transparent; 2kHz")
      (fields (field (name "MF") "WorldSemi"))
      (libsource (lib "WS2812B2020") (part "WS2812B2020"))
    )
    (comp (ref "D269")
      (value "WS2812B2020")
      (footprint "XL-1010RGBC-WS2812B")
      (description "LED; SMD; 2020; RGB; 2x2x0.84mm; 3.7Ã·5.3V; Lens: transparent; 2kHz")
      (fields (field (name "MF") "WorldSemi"))
      (libsource (lib "WS2812B2020") (part "WS2812B2020"))
    )
    (comp (ref "D270")
      (value "WS2812B2020")
      (footprint "XL-1010RGBC-WS2812B")
      (description "LED; SMD; 2020; RGB; 2x2x0.84mm; 3.7Ã·5.3V; Lens: transparent; 2kHz")
      (fields (field (name "MF") "WorldSemi"))
      (libsource (lib "WS2812B2020") (part "WS2812B2020"))
    )
    (comp (ref "D271")
      (value "WS2812B2020")
      (footprint "XL-1010RGBC-WS2812B")
      (description "LED; SMD; 2020; RGB; 2x2x0.84mm; 3.7Ã·5.3V; Lens: transparent; 2kHz")
      (fields (field (name "MF") "WorldSemi"))
      (libsource (lib "WS2812B2020") (part "WS2812B2020"))
    )
    (comp (ref "D272")
      (value "WS2812B2020")
      (footprint "XL-1010RGBC-WS2812B")
      (description "LED; SMD; 2020; RGB; 2x2x0.84mm; 3.7Ã·5.3V; Lens: transparent; 2kHz")
      (fields (field (name "MF") "WorldSemi"))
      (libsource (lib "WS2812B2020") (part "WS2812B2020"))
    )
    (comp (ref "D273")
      (value "WS2812B2020")
      (footprint "XL-1010RGBC-WS2812B")
      (description "LED; SMD; 2020; RGB; 2x2x0.84mm; 3.7Ã·5.3V; Lens: transparent; 2kHz")
      (fields (field (name "MF") "WorldSemi"))
      (libsource (lib "WS2812B2020") (part "WS2812B2020"))
    )
    (comp (ref "D274")
      (value "WS2812B2020")
      (footprint "XL-1010RGBC-WS2812B")
      (description "LED; SMD; 2020; RGB; 2x2x0.84mm; 3.7Ã·5.3V; Lens: transparent; 2kHz")
      (fields (field (name "MF") "WorldSemi"))
      (libsource (lib "WS2812B2020") (part "WS2812B2020"))
    )
    (comp (ref "D275")
      (value "WS2812B2020")
      (footprint "XL-1010RGBC-WS2812B")
      (description "LED; SMD; 2020; RGB; 2x2x0.84mm; 3.7Ã·5.3V; Lens: transparent; 2kHz")
      (fields (field (name "MF") "WorldSemi"))
      (libsource (lib "WS2812B2020") (part "WS2812B2020"))
    )
    (comp (ref "D276")
      (value "WS2812B2020")
      (footprint "XL-1010RGBC-WS2812B")
      (description "LED; SMD; 2020; RGB; 2x2x0.84mm; 3.7Ã·5.3V; Lens: transparent; 2kHz")
      (fields (field (name "MF") "WorldSemi"))
      (libsource (lib "WS2812B2020") (part "WS2812B2020"))
    )
    (comp (ref "D277")
      (value "WS2812B2020")
      (footprint "XL-1010RGBC-WS2812B")
      (description "LED; SMD; 2020; RGB; 2x2x0.84mm; 3.7Ã·5.3V; Lens: transparent; 2kHz")
      (fields (field (name "MF") "WorldSemi"))
      (libsource (lib "WS2812B2020") (part "WS2812B2020"))
    )
    (comp (ref "D278")
      (value "WS2812B2020")
      (footprint "XL-1010RGBC-WS2812B")
      (description "LED; SMD; 2020; RGB; 2x2x0.84mm; 3.7Ã·5.3V; Lens: transparent; 2kHz")
      (fields (field (name "MF") "WorldSemi"))
      (libsource (lib "WS2812B2020") (part "WS2812B2020"))
    )
    (comp (ref "D279")
      (value "WS2812B2020")
      (footprint "XL-1010RGBC-WS2812B")
      (description "LED; SMD; 2020; RGB; 2x2x0.84mm; 3.7Ã·5.3V; Lens: transparent; 2kHz")
      (fields (field (name "MF") "WorldSemi"))
      (libsource (lib "WS2812B2020") (part "WS2812B2020"))
    )
    (comp (ref "D280")
      (value "WS2812B2020")
      (footprint "XL-1010RGBC-WS2812B")
      (description "LED; SMD; 2020; RGB; 2x2x0.84mm; 3.7Ã·5.3V; Lens: transparent; 2kHz")
      (fields (field (name "MF") "WorldSemi"))
      (libsource (lib "WS2812B2020") (part "WS2812B2020"))
    )
    (comp (ref "D281")
      (value "WS2812B2020")
      (footprint "XL-1010RGBC-WS2812B")
      (description "LED; SMD; 2020; RGB; 2x2x0.84mm; 3.7Ã·5.3V; Lens: transparent; 2kHz")
      (fields (field (name "MF") "WorldSemi"))
      (libsource (lib "WS2812B2020") (part "WS2812B2020"))
    )
    (comp (ref "D282")
      (value "WS2812B2020")
      (footprint "XL-1010RGBC-WS2812B")
      (description "LED; SMD; 2020; RGB; 2x2x0.84mm; 3.7Ã·5.3V; Lens: transparent; 2kHz")
      (fields (field (name "MF") "WorldSemi"))
      (libsource (lib "WS2812B2020") (part "WS2812B2020"))
    )
    (comp (ref "D283")
      (value "WS2812B2020")
      (footprint "XL-1010RGBC-WS2812B")
      (description "LED; SMD; 2020; RGB; 2x2x0.84mm; 3.7Ã·5.3V; Lens: transparent; 2kHz")
      (fields (field (name "MF") "WorldSemi"))
      (libsource (lib "WS2812B2020") (part "WS2812B2020"))
    )
    (comp (ref "D284")
      (value "WS2812B2020")
      (footprint "XL-1010RGBC-WS2812B")
      (description "LED; SMD; 2020; RGB; 2x2x0.84mm; 3.7Ã·5.3V; Lens: transparent; 2kHz")
      (fields (field (name "MF") "WorldSemi"))
      (libsource (lib "WS2812B2020") (part "WS2812B2020"))
    )
    (comp (ref "D285")
      (value "WS2812B2020")
      (footprint "XL-1010RGBC-WS2812B")
      (description "LED; SMD; 2020; RGB; 2x2x0.84mm; 3.7Ã·5.3V; Lens: transparent; 2kHz")
      (fields (field (name "MF") "WorldSemi"))
      (libsource (lib "WS2812B2020") (part "WS2812B2020"))
    )
    (comp (ref "D286")
      (value "WS2812B2020")
      (footprint "XL-1010RGBC-WS2812B")
      (description "LED; SMD; 2020; RGB; 2x2x0.84mm; 3.7Ã·5.3V; Lens: transparent; 2kHz")
      (fields (field (name "MF") "WorldSemi"))
      (libsource (lib "WS2812B2020") (part "WS2812B2020"))
    )
    (comp (ref "D287")
      (value "WS2812B2020")
      (footprint "XL-1010RGBC-WS2812B")
      (description "LED; SMD; 2020; RGB; 2x2x0.84mm; 3.7Ã·5.3V; Lens: transparent; 2kHz")
      (fields (field (name "MF") "WorldSemi"))
      (libsource (lib "WS2812B2020") (part "WS2812B2020"))
    )
    (comp (ref "D288")
      (value "WS2812B2020")
      (footprint "XL-1010RGBC-WS2812B")
      (description "LED; SMD; 2020; RGB; 2x2x0.84mm; 3.7Ã·5.3V; Lens: transparent; 2kHz")
      (fields (field (name "MF") "WorldSemi"))
      (libsource (lib "WS2812B2020") (part "WS2812B2020"))
    )
    (comp (ref "D289")
      (value "WS2812B2020")
      (footprint "XL-1010RGBC-WS2812B")
      (description "LED; SMD; 2020; RGB; 2x2x0.84mm; 3.7Ã·5.3V; Lens: transparent; 2kHz")
      (fields (field (name "MF") "WorldSemi"))
      (libsource (lib "WS2812B2020") (part "WS2812B2020"))
    )
    (comp (ref "D290")
      (value "WS2812B2020")
      (footprint "XL-1010RGBC-WS2812B")
      (description "LED; SMD; 2020; RGB; 2x2x0.84mm; 3.7Ã·5.3V; Lens: transparent; 2kHz")
      (fields (field (name "MF") "WorldSemi"))
      (libsource (lib "WS2812B2020") (part "WS2812B2020"))
    )
    (comp (ref "D291")
      (value "WS2812B2020")
      (footprint "XL-1010RGBC-WS2812B")
      (description "LED; SMD; 2020; RGB; 2x2x0.84mm; 3.7Ã·5.3V; Lens: transparent; 2kHz")
      (fields (field (name "MF") "WorldSemi"))
      (libsource (lib "WS2812B2020") (part "WS2812B2020"))
    )
    (comp (ref "D292")
      (value "WS2812B2020")
      (footprint "XL-1010RGBC-WS2812B")
      (description "LED; SMD; 2020; RGB; 2x2x0.84mm; 3.7Ã·5.3V; Lens: transparent; 2kHz")
      (fields (field (name "MF") "WorldSemi"))
      (libsource (lib "WS2812B2020") (part "WS2812B2020"))
    )
    (comp (ref "D293")
      (value "WS2812B2020")
      (footprint "XL-1010RGBC-WS2812B")
      (description "LED; SMD; 2020; RGB; 2x2x0.84mm; 3.7Ã·5.3V; Lens: transparent; 2kHz")
      (fields (field (name "MF") "WorldSemi"))
      (libsource (lib "WS2812B2020") (part "WS2812B2020"))
    )
    (comp (ref "D294")
      (value "WS2812B2020")
      (footprint "XL-1010RGBC-WS2812B")
      (description "LED; SMD; 2020; RGB; 2x2x0.84mm; 3.7Ã·5.3V; Lens: transparent; 2kHz")
      (fields (field (name "MF") "WorldSemi"))
      (libsource (lib "WS2812B2020") (part "WS2812B2020"))
    )
    (comp (ref "D295")
      (value "WS2812B2020")
      (footprint "XL-1010RGBC-WS2812B")
      (description "LED; SMD; 2020; RGB; 2x2x0.84mm; 3.7Ã·5.3V; Lens: transparent; 2kHz")
      (fields (field (name "MF") "WorldSemi"))
      (libsource (lib "WS2812B2020") (part "WS2812B2020"))
    )
    (comp (ref "D296")
      (value "WS2812B2020")
      (footprint "XL-1010RGBC-WS2812B")
      (description "LED; SMD; 2020; RGB; 2x2x0.84mm; 3.7Ã·5.3V; Lens: transparent; 2kHz")
      (fields (field (name "MF") "WorldSemi"))
      (libsource (lib "WS2812B2020") (part "WS2812B2020"))
    )
    (comp (ref "D297")
      (value "WS2812B2020")
      (footprint "XL-1010RGBC-WS2812B")
      (description "LED; SMD; 2020; RGB; 2x2x0.84mm; 3.7Ã·5.3V; Lens: transparent; 2kHz")
      (fields (field (name "MF") "WorldSemi"))
      (libsource (lib "WS2812B2020") (part "WS2812B2020"))
    )
    (comp (ref "D298")
      (value "WS2812B2020")
      (footprint "XL-1010RGBC-WS2812B")
      (description "LED; SMD; 2020; RGB; 2x2x0.84mm; 3.7Ã·5.3V; Lens: transparent; 2kHz")
      (fields (field (name "MF") "WorldSemi"))
      (libsource (lib "WS2812B2020") (part "WS2812B2020"))
    )
    (comp (ref "D299")
      (value "WS2812B2020")
      (footprint "XL-1010RGBC-WS2812B")
      (description "LED; SMD; 2020; RGB; 2x2x0.84mm; 3.7Ã·5.3V; Lens: transparent; 2kHz")
      (fields (field (name "MF") "WorldSemi"))
      (libsource (lib "WS2812B2020") (part "WS2812B2020"))
    )
    (comp (ref "D300")
      (value "WS2812B2020")
      (footprint "XL-1010RGBC-WS2812B")
      (description "LED; SMD; 2020; RGB; 2x2x0.84mm; 3.7Ã·5.3V; Lens: transparent; 2kHz")
      (fields (field (name "MF") "WorldSemi"))
      (libsource (lib "WS2812B2020") (part "WS2812B2020"))
    )
    (comp (ref "D301")
      (value "WS2812B2020")
      (footprint "XL-1010RGBC-WS2812B")
      (description "LED; SMD; 2020; RGB; 2x2x0.84mm; 3.7Ã·5.3V; Lens: transparent; 2kHz")
      (fields (field (name "MF") "WorldSemi"))
      (libsource (lib "WS2812B2020") (part "WS2812B2020"))
    )
    (comp (ref "D302")
      (value "WS2812B2020")
      (footprint "XL-1010RGBC-WS2812B")
      (description "LED; SMD; 2020; RGB; 2x2x0.84mm; 3.7Ã·5.3V; Lens: transparent; 2kHz")
      (fields (field (name "MF") "WorldSemi"))
      (libsource (lib "WS2812B2020") (part "WS2812B2020"))
    )
    (comp (ref "D303")
      (value "WS2812B2020")
      (footprint "XL-1010RGBC-WS2812B")
      (description "LED; SMD; 2020; RGB; 2x2x0.84mm; 3.7Ã·5.3V; Lens: transparent; 2kHz")
      (fields (field (name "MF") "WorldSemi"))
      (libsource (lib "WS2812B2020") (part "WS2812B2020"))
    )
    (comp (ref "D304")
      (value "WS2812B2020")
      (footprint "XL-1010RGBC-WS2812B")
      (description "LED; SMD; 2020; RGB; 2x2x0.84mm; 3.7Ã·5.3V; Lens: transparent; 2kHz")
      (fields (field (name "MF") "WorldSemi"))
      (libsource (lib "WS2812B2020") (part "WS2812B2020"))
    )
    (comp (ref "D305")
      (value "WS2812B2020")
      (footprint "XL-1010RGBC-WS2812B")
      (description "LED; SMD; 2020; RGB; 2x2x0.84mm; 3.7Ã·5.3V; Lens: transparent; 2kHz")
      (fields (field (name "MF") "WorldSemi"))
      (libsource (lib "WS2812B2020") (part "WS2812B2020"))
    )
    (comp (ref "D306")
      (value "WS2812B2020")
      (footprint "XL-1010RGBC-WS2812B")
      (description "LED; SMD; 2020; RGB; 2x2x0.84mm; 3.7Ã·5.3V; Lens: transparent; 2kHz")
      (fields (field (name "MF") "WorldSemi"))
      (libsource (lib "WS2812B2020") (part "WS2812B2020"))
    )
    (comp (ref "D307")
      (value "WS2812B2020")
      (footprint "XL-1010RGBC-WS2812B")
      (description "LED; SMD; 2020; RGB; 2x2x0.84mm; 3.7Ã·5.3V; Lens: transparent; 2kHz")
      (fields (field (name "MF") "WorldSemi"))
      (libsource (lib "WS2812B2020") (part "WS2812B2020"))
    )
    (comp (ref "D308")
      (value "WS2812B2020")
      (footprint "XL-1010RGBC-WS2812B")
      (description "LED; SMD; 2020; RGB; 2x2x0.84mm; 3.7Ã·5.3V; Lens: transparent; 2kHz")
      (fields (field (name "MF") "WorldSemi"))
      (libsource (lib "WS2812B2020") (part "WS2812B2020"))
    )
    (comp (ref "D309")
      (value "WS2812B2020")
      (footprint "XL-1010RGBC-WS2812B")
      (description "LED; SMD; 2020; RGB; 2x2x0.84mm; 3.7Ã·5.3V; Lens: transparent; 2kHz")
      (fields (field (name "MF") "WorldSemi"))
      (libsource (lib "WS2812B2020") (part "WS2812B2020"))
    )
    (comp (ref "D310")
      (value "WS2812B2020")
      (footprint "XL-1010RGBC-WS2812B")
      (description "LED; SMD; 2020; RGB; 2x2x0.84mm; 3.7Ã·5.3V; Lens: transparent; 2kHz")
      (fields (field (name "MF") "WorldSemi"))
      (libsource (lib "WS2812B2020") (part "WS2812B2020"))
    )
    (comp (ref "D311")
      (value "WS2812B2020")
      (footprint "XL-1010RGBC-WS2812B")
      (description "LED; SMD; 2020; RGB; 2x2x0.84mm; 3.7Ã·5.3V; Lens: transparent; 2kHz")
      (fields (field (name "MF") "WorldSemi"))
      (libsource (lib "WS2812B2020") (part "WS2812B2020"))
    )
    (comp (ref "D312")
      (value "WS2812B2020")
      (footprint "XL-1010RGBC-WS2812B")
      (description "LED; SMD; 2020; RGB; 2x2x0.84mm; 3.7Ã·5.3V; Lens: transparent; 2kHz")
      (fields (field (name "MF") "WorldSemi"))
      (libsource (lib "WS2812B2020") (part "WS2812B2020"))
    )
    (comp (ref "D313")
      (value "WS2812B2020")
      (footprint "XL-1010RGBC-WS2812B")
      (description "LED; SMD; 2020; RGB; 2x2x0.84mm; 3.7Ã·5.3V; Lens: transparent; 2kHz")
      (fields (field (name "MF") "WorldSemi"))
      (libsource (lib "WS2812B2020") (part "WS2812B2020"))
    )
    (comp (ref "D314")
      (value "WS2812B2020")
      (footprint "XL-1010RGBC-WS2812B")
      (description "LED; SMD; 2020; RGB; 2x2x0.84mm; 3.7Ã·5.3V; Lens: transparent; 2kHz")
      (fields (field (name "MF") "WorldSemi"))
      (libsource (lib "WS2812B2020") (part "WS2812B2020"))
    )
    (comp (ref "D315")
      (value "WS2812B2020")
      (footprint "XL-1010RGBC-WS2812B")
      (description "LED; SMD; 2020; RGB; 2x2x0.84mm; 3.7Ã·5.3V; Lens: transparent; 2kHz")
      (fields (field (name "MF") "WorldSemi"))
      (libsource (lib "WS2812B2020") (part "WS2812B2020"))
    )
    (comp (ref "D316")
      (value "WS2812B2020")
      (footprint "XL-1010RGBC-WS2812B")
      (description "LED; SMD; 2020; RGB; 2x2x0.84mm; 3.7Ã·5.3V; Lens: transparent; 2kHz")
      (fields (field (name "MF") "WorldSemi"))
      (libsource (lib "WS2812B2020") (part "WS2812B2020"))
    )
    (comp (ref "D317")
      (value "WS2812B2020")
      (footprint "XL-1010RGBC-WS2812B")
      (description "LED; SMD; 2020; RGB; 2x2x0.84mm; 3.7Ã·5.3V; Lens: transparent; 2kHz")
      (fields (field (name "MF") "WorldSemi"))
      (libsource (lib "WS2812B2020") (part "WS2812B2020"))
    )
    (comp (ref "D318")
      (value "WS2812B2020")
      (footprint "XL-1010RGBC-WS2812B")
      (description "LED; SMD; 2020; RGB; 2x2x0.84mm; 3.7Ã·5.3V; Lens: transparent; 2kHz")
      (fields (field (name "MF") "WorldSemi"))
      (libsource (lib "WS2812B2020") (part "WS2812B2020"))
    )
    (comp (ref "D319")
      (value "WS2812B2020")
      (footprint "XL-1010RGBC-WS2812B")
      (description "LED; SMD; 2020; RGB; 2x2x0.84mm; 3.7Ã·5.3V; Lens: transparent; 2kHz")
      (fields (field (name "MF") "WorldSemi"))
      (libsource (lib "WS2812B2020") (part "WS2812B2020"))
    )
    (comp (ref "D320")
      (value "WS2812B2020")
      (footprint "XL-1010RGBC-WS2812B")
      (description "LED; SMD; 2020; RGB; 2x2x0.84mm; 3.7Ã·5.3V; Lens: transparent; 2kHz")
      (fields (field (name "MF") "WorldSemi"))
      (libsource (lib "WS2812B2020") (part "WS2812B2020"))
    )
    (comp (ref "D321")
      (value "WS2812B2020")
      (footprint "XL-1010RGBC-WS2812B")
      (description "LED; SMD; 2020; RGB; 2x2x0.84mm; 3.7Ã·5.3V; Lens: transparent; 2kHz")
      (fields (field (name "MF") "WorldSemi"))
      (libsource (lib "WS2812B2020") (part "WS2812B2020"))
    )
    (comp (ref "D322")
      (value "WS2812B2020")
      (footprint "XL-1010RGBC-WS2812B")
      (description "LED; SMD; 2020; RGB; 2x2x0.84mm; 3.7Ã·5.3V; Lens: transparent; 2kHz")
      (fields (field (name "MF") "WorldSemi"))
      (libsource (lib "WS2812B2020") (part "WS2812B2020"))
    )
    (comp (ref "D323")
      (value "WS2812B2020")
      (footprint "XL-1010RGBC-WS2812B")
      (description "LED; SMD; 2020; RGB; 2x2x0.84mm; 3.7Ã·5.3V; Lens: transparent; 2kHz")
      (fields (field (name "MF") "WorldSemi"))
      (libsource (lib "WS2812B2020") (part "WS2812B2020"))
    )
    (comp (ref "D324")
      (value "WS2812B2020")
      (footprint "XL-1010RGBC-WS2812B")
      (description "LED; SMD; 2020; RGB; 2x2x0.84mm; 3.7Ã·5.3V; Lens: transparent; 2kHz")
      (fields (field (name "MF") "WorldSemi"))
      (libsource (lib "WS2812B2020") (part "WS2812B2020"))
    )
    (comp (ref "D325")
      (value "WS2812B2020")
      (footprint "XL-1010RGBC-WS2812B")
      (description "LED; SMD; 2020; RGB; 2x2x0.84mm; 3.7Ã·5.3V; Lens: transparent; 2kHz")
      (fields (field (name "MF") "WorldSemi"))
      (libsource (lib "WS2812B2020") (part "WS2812B2020"))
    )
    (comp (ref "D326")
      (value "WS2812B2020")
      (footprint "XL-1010RGBC-WS2812B")
      (description "LED; SMD; 2020; RGB; 2x2x0.84mm; 3.7Ã·5.3V; Lens: transparent; 2kHz")
      (fields (field (name "MF") "WorldSemi"))
      (libsource (lib "WS2812B2020") (part "WS2812B2020"))
    )
    (comp (ref "D327")
      (value "WS2812B2020")
      (footprint "XL-1010RGBC-WS2812B")
      (description "LED; SMD; 2020; RGB; 2x2x0.84mm; 3.7Ã·5.3V; Lens: transparent; 2kHz")
      (fields (field (name "MF") "WorldSemi"))
      (libsource (lib "WS2812B2020") (part "WS2812B2020"))
    )
    (comp (ref "D328")
      (value "WS2812B2020")
      (footprint "XL-1010RGBC-WS2812B")
      (description "LED; SMD; 2020; RGB; 2x2x0.84mm; 3.7Ã·5.3V; Lens: transparent; 2kHz")
      (fields (field (name "MF") "WorldSemi"))
      (libsource (lib "WS2812B2020") (part "WS2812B2020"))
    )
    (comp (ref "D329")
      (value "WS2812B2020")
      (footprint "XL-1010RGBC-WS2812B")
      (description "LED; SMD; 2020; RGB; 2x2x0.84mm; 3.7Ã·5.3V; Lens: transparent; 2kHz")
      (fields (field (name "MF") "WorldSemi"))
      (libsource (lib "WS2812B2020") (part "WS2812B2020"))
    )
    (comp (ref "D330")
      (value "WS2812B2020")
      (footprint "XL-1010RGBC-WS2812B")
      (description "LED; SMD; 2020; RGB; 2x2x0.84mm; 3.7Ã·5.3V; Lens: transparent; 2kHz")
      (fields (field (name "MF") "WorldSemi"))
      (libsource (lib "WS2812B2020") (part "WS2812B2020"))
    )
    (comp (ref "D331")
      (value "WS2812B2020")
      (footprint "XL-1010RGBC-WS2812B")
      (description "LED; SMD; 2020; RGB; 2x2x0.84mm; 3.7Ã·5.3V; Lens: transparent; 2kHz")
      (fields (field (name "MF") "WorldSemi"))
      (libsource (lib "WS2812B2020") (part "WS2812B2020"))
    )
    (comp (ref "D332")
      (value "WS2812B2020")
      (footprint "XL-1010RGBC-WS2812B")
      (description "LED; SMD; 2020; RGB; 2x2x0.84mm; 3.7Ã·5.3V; Lens: transparent; 2kHz")
      (fields (field (name "MF") "WorldSemi"))
      (libsource (lib "WS2812B2020") (part "WS2812B2020"))
    )
    (comp (ref "D333")
      (value "WS2812B2020")
      (footprint "XL-1010RGBC-WS2812B")
      (description "LED; SMD; 2020; RGB; 2x2x0.84mm; 3.7Ã·5.3V; Lens: transparent; 2kHz")
      (fields (field (name "MF") "WorldSemi"))
      (libsource (lib "WS2812B2020") (part "WS2812B2020"))
    )
    (comp (ref "D334")
      (value "WS2812B2020")
      (footprint "XL-1010RGBC-WS2812B")
      (description "LED; SMD; 2020; RGB; 2x2x0.84mm; 3.7Ã·5.3V; Lens: transparent; 2kHz")
      (fields (field (name "MF") "WorldSemi"))
      (libsource (lib "WS2812B2020") (part "WS2812B2020"))
    )
    (comp (ref "D335")
      (value "WS2812B2020")
      (footprint "XL-1010RGBC-WS2812B")
      (description "LED; SMD; 2020; RGB; 2x2x0.84mm; 3.7Ã·5.3V; Lens: transparent; 2kHz")
      (fields (field (name "MF") "WorldSemi"))
      (libsource (lib "WS2812B2020") (part "WS2812B2020"))
    )
    (comp (ref "D336")
      (value "WS2812B2020")
      (footprint "XL-1010RGBC-WS2812B")
      (description "LED; SMD; 2020; RGB; 2x2x0.84mm; 3.7Ã·5.3V; Lens: transparent; 2kHz")
      (fields (field (name "MF") "WorldSemi"))
      (libsource (lib "WS2812B2020") (part "WS2812B2020"))
    )
    (comp (ref "D337")
      (value "WS2812B2020")
      (footprint "XL-1010RGBC-WS2812B")
      (description "LED; SMD; 2020; RGB; 2x2x0.84mm; 3.7Ã·5.3V; Lens: transparent; 2kHz")
      (fields (field (name "MF") "WorldSemi"))
      (libsource (lib "WS2812B2020") (part "WS2812B2020"))
    )
    (comp (ref "D338")
      (value "WS2812B2020")
      (footprint "XL-1010RGBC-WS2812B")
      (description "LED; SMD; 2020; RGB; 2x2x0.84mm; 3.7Ã·5.3V; Lens: transparent; 2kHz")
      (fields (field (name "MF") "WorldSemi"))
      (libsource (lib "WS2812B2020") (part "WS2812B2020"))
    )
    (comp (ref "D339")
      (value "WS2812B2020")
      (footprint "XL-1010RGBC-WS2812B")
      (description "LED; SMD; 2020; RGB; 2x2x0.84mm; 3.7Ã·5.3V; Lens: transparent; 2kHz")
      (fields (field (name "MF") "WorldSemi"))
      (libsource (lib "WS2812B2020") (part "WS2812B2020"))
    )
    (comp (ref "D340")
      (value "WS2812B2020")
      (footprint "XL-1010RGBC-WS2812B")
      (description "LED; SMD; 2020; RGB; 2x2x0.84mm; 3.7Ã·5.3V; Lens: transparent; 2kHz")
      (fields (field (name "MF") "WorldSemi"))
      (libsource (lib "WS2812B2020") (part "WS2812B2020"))
    )
    (comp (ref "D341")
      (value "WS2812B2020")
      (footprint "XL-1010RGBC-WS2812B")
      (description "LED; SMD; 2020; RGB; 2x2x0.84mm; 3.7Ã·5.3V; Lens: transparent; 2kHz")
      (fields (field (name "MF") "WorldSemi"))
      (libsource (lib "WS2812B2020") (part "WS2812B2020"))
    )
    (comp (ref "D342")
      (value "WS2812B2020")
      (footprint "XL-1010RGBC-WS2812B")
      (description "LED; SMD; 2020; RGB; 2x2x0.84mm; 3.7Ã·5.3V; Lens: transparent; 2kHz")
      (fields (field (name "MF") "WorldSemi"))
      (libsource (lib "WS2812B2020") (part "WS2812B2020"))
    )
    (comp (ref "D343")
      (value "WS2812B2020")
      (footprint "XL-1010RGBC-WS2812B")
      (description "LED; SMD; 2020; RGB; 2x2x0.84mm; 3.7Ã·5.3V; Lens: transparent; 2kHz")
      (fields (field (name "MF") "WorldSemi"))
      (libsource (lib "WS2812B2020") (part "WS2812B2020"))
    )
    (comp (ref "D344")
      (value "WS2812B2020")
      (footprint "XL-1010RGBC-WS2812B")
      (description "LED; SMD; 2020; RGB; 2x2x0.84mm; 3.7Ã·5.3V; Lens: transparent; 2kHz")
      (fields (field (name "MF") "WorldSemi"))
      (libsource (lib "WS2812B2020") (part "WS2812B2020"))
    )
    (comp (ref "D345")
      (value "WS2812B2020")
      (footprint "XL-1010RGBC-WS2812B")
      (description "LED; SMD; 2020; RGB; 2x2x0.84mm; 3.7Ã·5.3V; Lens: transparent; 2kHz")
      (fields (field (name "MF") "WorldSemi"))
      (libsource (lib "WS2812B2020") (part "WS2812B2020"))
    )
    (comp (ref "D346")
      (value "WS2812B2020")
      (footprint "XL-1010RGBC-WS2812B")
      (description "LED; SMD; 2020; RGB; 2x2x0.84mm; 3.7Ã·5.3V; Lens: transparent; 2kHz")
      (fields (field (name "MF") "WorldSemi"))
      (libsource (lib "WS2812B2020") (part "WS2812B2020"))
    )
    (comp (ref "D347")
      (value "WS2812B2020")
      (footprint "XL-1010RGBC-WS2812B")
      (description "LED; SMD; 2020; RGB; 2x2x0.84mm; 3.7Ã·5.3V; Lens: transparent; 2kHz")
      (fields (field (name "MF") "WorldSemi"))
      (libsource (lib "WS2812B2020") (part "WS2812B2020"))
    )
    (comp (ref "D348")
      (value "WS2812B2020")
      (footprint "XL-1010RGBC-WS2812B")
      (description "LED; SMD; 2020; RGB; 2x2x0.84mm; 3.7Ã·5.3V; Lens: transparent; 2kHz")
      (fields (field (name "MF") "WorldSemi"))
      (libsource (lib "WS2812B2020") (part "WS2812B2020"))
    )
    (comp (ref "D349")
      (value "WS2812B2020")
      (footprint "XL-1010RGBC-WS2812B")
      (description "LED; SMD; 2020; RGB; 2x2x0.84mm; 3.7Ã·5.3V; Lens: transparent; 2kHz")
      (fields (field (name "MF") "WorldSemi"))
      (libsource (lib "WS2812B2020") (part "WS2812B2020"))
    )
    (comp (ref "D350")
      (value "WS2812B2020")
      (footprint "XL-1010RGBC-WS2812B")
      (description "LED; SMD; 2020; RGB; 2x2x0.84mm; 3.7Ã·5.3V; Lens: transparent; 2kHz")
      (fields (field (name "MF") "WorldSemi"))
      (libsource (lib "WS2812B2020") (part "WS2812B2020"))
    )
    (comp (ref "D351")
      (value "WS2812B2020")
      (footprint "XL-1010RGBC-WS2812B")
      (description "LED; SMD; 2020; RGB; 2x2x0.84mm; 3.7Ã·5.3V; Lens: transparent; 2kHz")
      (fields (field (name "MF") "WorldSemi"))
      (libsource (lib "WS2812B2020") (part "WS2812B2020"))
    )
    (comp (ref "D352")
      (value "WS2812B2020")
      (footprint "XL-1010RGBC-WS2812B")
      (description "LED; SMD; 2020; RGB; 2x2x0.84mm; 3.7Ã·5.3V; Lens: transparent; 2kHz")
      (fields (field (name "MF") "WorldSemi"))
      (libsource (lib "WS2812B2020") (part "WS2812B2020"))
    )
    (comp (ref "D353")
      (value "WS2812B2020")
      (footprint "XL-1010RGBC-WS2812B")
      (description "LED; SMD; 2020; RGB; 2x2x0.84mm; 3.7Ã·5.3V; Lens: transparent; 2kHz")
      (fields (field (name "MF") "WorldSemi"))
      (libsource (lib "WS2812B2020") (part "WS2812B2020"))
    )
    (comp (ref "D354")
      (value "WS2812B2020")
      (footprint "XL-1010RGBC-WS2812B")
      (description "LED; SMD; 2020; RGB; 2x2x0.84mm; 3.7Ã·5.3V; Lens: transparent; 2kHz")
      (fields (field (name "MF") "WorldSemi"))
      (libsource (lib "WS2812B2020") (part "WS2812B2020"))
    )
    (comp (ref "D355")
      (value "WS2812B2020")
      (footprint "XL-1010RGBC-WS2812B")
      (description "LED; SMD; 2020; RGB; 2x2x0.84mm; 3.7Ã·5.3V; Lens: transparent; 2kHz")
      (fields (field (name "MF") "WorldSemi"))
      (libsource (lib "WS2812B2020") (part "WS2812B2020"))
    )
    (comp (ref "D356")
      (value "WS2812B2020")
      (footprint "XL-1010RGBC-WS2812B")
      (description "LED; SMD; 2020; RGB; 2x2x0.84mm; 3.7Ã·5.3V; Lens: transparent; 2kHz")
      (fields (field (name "MF") "WorldSemi"))
      (libsource (lib "WS2812B2020") (part "WS2812B2020"))
    )
    (comp (ref "D357")
      (value "WS2812B2020")
      (footprint "XL-1010RGBC-WS2812B")
      (description "LED; SMD; 2020; RGB; 2x2x0.84mm; 3.7Ã·5.3V; Lens: transparent; 2kHz")
      (fields (field (name "MF") "WorldSemi"))
      (libsource (lib "WS2812B2020") (part "WS2812B2020"))
    )
    (comp (ref "D358")
      (value "WS2812B2020")
      (footprint "XL-1010RGBC-WS2812B")
      (description "LED; SMD; 2020; RGB; 2x2x0.84mm; 3.7Ã·5.3V; Lens: transparent; 2kHz")
      (fields (field (name "MF") "WorldSemi"))
      (libsource (lib "WS2812B2020") (part "WS2812B2020"))
    )
    (comp (ref "D359")
      (value "WS2812B2020")
      (footprint "XL-1010RGBC-WS2812B")
      (description "LED; SMD; 2020; RGB; 2x2x0.84mm; 3.7Ã·5.3V; Lens: transparent; 2kHz")
      (fields (field (name "MF") "WorldSemi"))
      (libsource (lib "WS2812B2020") (part "WS2812B2020"))
    )
    (comp (ref "D360")
      (value "WS2812B2020")
      (footprint "XL-1010RGBC-WS2812B")
      (description "LED; SMD; 2020; RGB; 2x2x0.84mm; 3.7Ã·5.3V; Lens: transparent; 2kHz")
      (fields (field (name "MF") "WorldSemi"))
      (libsource (lib "") (part "WS2812B2020_1"))
    )
    (comp (ref "D361")
      (value "WS2812B2020")
      (footprint "XL-1010RGBC-WS2812B")
      (description "LED; SMD; 2020; RGB; 2x2x0.84mm; 3.7Ã·5.3V; Lens: transparent; 2kHz")
      (fields (field (name "MF") "WorldSemi"))
      (libsource (lib "") (part "WS2812B2020_1"))
    )
    (comp (ref "D362")
      (value "WS2812B2020")
      (footprint "XL-1010RGBC-WS2812B")
      (description "LED; SMD; 2020; RGB; 2x2x0.84mm; 3.7Ã·5.3V; Lens: transparent; 2kHz")
      (fields (field (name "MF") "WorldSemi"))
      (libsource (lib "") (part "WS2812B2020_1"))
    )
    (comp (ref "D363")
      (value "WS2812B2020")
      (footprint "XL-1010RGBC-WS2812B")
      (description "LED; SMD; 2020; RGB; 2x2x0.84mm; 3.7Ã·5.3V; Lens: transparent; 2kHz")
      (fields (field (name "MF") "WorldSemi"))
      (libsource (lib "") (part "WS2812B2020_1"))
    )
    (comp (ref "D364")
      (value "WS2812B2020")
      (footprint "XL-1010RGBC-WS2812B")
      (description "LED; SMD; 2020; RGB; 2x2x0.84mm; 3.7Ã·5.3V; Lens: transparent; 2kHz")
      (fields (field (name "MF") "WorldSemi"))
      (libsource (lib "") (part "WS2812B2020_1"))
    )
    (comp (ref "D365")
      (value "WS2812B2020")
      (footprint "XL-1010RGBC-WS2812B")
      (description "LED; SMD; 2020; RGB; 2x2x0.84mm; 3.7Ã·5.3V; Lens: transparent; 2kHz")
      (fields (field (name "MF") "WorldSemi"))
      (libsource (lib "") (part "WS2812B2020_1"))
    )
    (comp (ref "D366")
      (value "WS2812B2020")
      (footprint "XL-1010RGBC-WS2812B")
      (description "LED; SMD; 2020; RGB; 2x2x0.84mm; 3.7Ã·5.3V; Lens: transparent; 2kHz")
      (fields (field (name "MF") "WorldSemi"))
      (libsource (lib "") (part "WS2812B2020_1"))
    )
    (comp (ref "D367")
      (value "WS2812B2020")
      (footprint "XL-1010RGBC-WS2812B")
      (description "LED; SMD; 2020; RGB; 2x2x0.84mm; 3.7Ã·5.3V; Lens: transparent; 2kHz")
      (fields (field (name "MF") "WorldSemi"))
      (libsource (lib "") (part "WS2812B2020_1"))
    )
    (comp (ref "D368")
      (value "WS2812B2020")
      (footprint "XL-1010RGBC-WS2812B")
      (description "LED; SMD; 2020; RGB; 2x2x0.84mm; 3.7Ã·5.3V; Lens: transparent; 2kHz")
      (fields (field (name "MF") "WorldSemi"))
      (libsource (lib "") (part "WS2812B2020_1"))
    )
    (comp (ref "D369")
      (value "WS2812B2020")
      (footprint "XL-1010RGBC-WS2812B")
      (description "LED; SMD; 2020; RGB; 2x2x0.84mm; 3.7Ã·5.3V; Lens: transparent; 2kHz")
      (fields (field (name "MF") "WorldSemi"))
      (libsource (lib "") (part "WS2812B2020_1"))
    )
    (comp (ref "D370")
      (value "WS2812B2020")
      (footprint "XL-1010RGBC-WS2812B")
      (description "LED; SMD; 2020; RGB; 2x2x0.84mm; 3.7Ã·5.3V; Lens: transparent; 2kHz")
      (fields (field (name "MF") "WorldSemi"))
      (libsource (lib "") (part "WS2812B2020_1"))
    )
    (comp (ref "D371")
      (value "WS2812B2020")
      (footprint "XL-1010RGBC-WS2812B")
      (description "LED; SMD; 2020; RGB; 2x2x0.84mm; 3.7Ã·5.3V; Lens: transparent; 2kHz")
      (fields (field (name "MF") "WorldSemi"))
      (libsource (lib "") (part "WS2812B2020_1"))
    )
    (comp (ref "D372")
      (value "WS2812B2020")
      (footprint "XL-1010RGBC-WS2812B")
      (description "LED; SMD; 2020; RGB; 2x2x0.84mm; 3.7Ã·5.3V; Lens: transparent; 2kHz")
      (fields (field (name "MF") "WorldSemi"))
      (libsource (lib "") (part "WS2812B2020_1"))
    )
    (comp (ref "D373")
      (value "WS2812B2020")
      (footprint "XL-1010RGBC-WS2812B")
      (description "LED; SMD; 2020; RGB; 2x2x0.84mm; 3.7Ã·5.3V; Lens: transparent; 2kHz")
      (fields (field (name "MF") "WorldSemi"))
      (libsource (lib "") (part "WS2812B2020_1"))
    )
    (comp (ref "D374")
      (value "WS2812B2020")
      (footprint "XL-1010RGBC-WS2812B")
      (description "LED; SMD; 2020; RGB; 2x2x0.84mm; 3.7Ã·5.3V; Lens: transparent; 2kHz")
      (fields (field (name "MF") "WorldSemi"))
      (libsource (lib "") (part "WS2812B2020_1"))
    )
    (comp (ref "D375")
      (value "WS2812B2020")
      (footprint "XL-1010RGBC-WS2812B")
      (description "LED; SMD; 2020; RGB; 2x2x0.84mm; 3.7Ã·5.3V; Lens: transparent; 2kHz")
      (fields (field (name "MF") "WorldSemi"))
      (libsource (lib "") (part "WS2812B2020_1"))
    )
    (comp (ref "D376")
      (value "WS2812B2020")
      (footprint "XL-1010RGBC-WS2812B")
      (description "LED; SMD; 2020; RGB; 2x2x0.84mm; 3.7Ã·5.3V; Lens: transparent; 2kHz")
      (fields (field (name "MF") "WorldSemi"))
      (libsource (lib "") (part "WS2812B2020_1"))
    )
    (comp (ref "D377")
      (value "WS2812B2020")
      (footprint "XL-1010RGBC-WS2812B")
      (description "LED; SMD; 2020; RGB; 2x2x0.84mm; 3.7Ã·5.3V; Lens: transparent; 2kHz")
      (fields (field (name "MF") "WorldSemi"))
      (libsource (lib "") (part "WS2812B2020_1"))
    )
    (comp (ref "D378")
      (value "WS2812B2020")
      (footprint "XL-1010RGBC-WS2812B")
      (description "LED; SMD; 2020; RGB; 2x2x0.84mm; 3.7Ã·5.3V; Lens: transparent; 2kHz")
      (fields (field (name "MF") "WorldSemi"))
      (libsource (lib "") (part "WS2812B2020_1"))
    )
    (comp (ref "D379")
      (value "WS2812B2020")
      (footprint "XL-1010RGBC-WS2812B")
      (description "LED; SMD; 2020; RGB; 2x2x0.84mm; 3.7Ã·5.3V; Lens: transparent; 2kHz")
      (fields (field (name "MF") "WorldSemi"))
      (libsource (lib "") (part "WS2812B2020_1"))
    )
    (comp (ref "D380")
      (value "WS2812B2020")
      (footprint "XL-1010RGBC-WS2812B")
      (description "LED; SMD; 2020; RGB; 2x2x0.84mm; 3.7Ã·5.3V; Lens: transparent; 2kHz")
      (fields (field (name "MF") "WorldSemi"))
      (libsource (lib "") (part "WS2812B2020_1"))
    )
    (comp (ref "D381")
      (value "WS2812B2020")
      (footprint "XL-1010RGBC-WS2812B")
      (description "LED; SMD; 2020; RGB; 2x2x0.84mm; 3.7Ã·5.3V; Lens: transparent; 2kHz")
      (fields (field (name "MF") "WorldSemi"))
      (libsource (lib "") (part "WS2812B2020_1"))
    )
    (comp (ref "D382")
      (value "WS2812B2020")
      (footprint "XL-1010RGBC-WS2812B")
      (description "LED; SMD; 2020; RGB; 2x2x0.84mm; 3.7Ã·5.3V; Lens: transparent; 2kHz")
      (fields (field (name "MF") "WorldSemi"))
      (libsource (lib "") (part "WS2812B2020_1"))
    )
    (comp (ref "D383")
      (value "WS2812B2020")
      (footprint "XL-1010RGBC-WS2812B")
      (description "LED; SMD; 2020; RGB; 2x2x0.84mm; 3.7Ã·5.3V; Lens: transparent; 2kHz")
      (fields (field (name "MF") "WorldSemi"))
      (libsource (lib "") (part "WS2812B2020_1"))
    )
    (comp (ref "D384")
      (value "WS2812B2020")
      (footprint "XL-1010RGBC-WS2812B")
      (description "LED; SMD; 2020; RGB; 2x2x0.84mm; 3.7Ã·5.3V; Lens: transparent; 2kHz")
      (fields (field (name "MF") "WorldSemi"))
      (libsource (lib "") (part "WS2812B2020_1"))
    )
    (comp (ref "D385")
      (value "WS2812B2020")
      (footprint "XL-1010RGBC-WS2812B")
      (description "LED; SMD; 2020; RGB; 2x2x0.84mm; 3.7Ã·5.3V; Lens: transparent; 2kHz")
      (fields (field (name "MF") "WorldSemi"))
      (libsource (lib "WS2812B2020") (part "WS2812B2020"))
    )
    (comp (ref "D386")
      (value "WS2812B2020")
      (footprint "XL-1010RGBC-WS2812B")
      (description "LED; SMD; 2020; RGB; 2x2x0.84mm; 3.7Ã·5.3V; Lens: transparent; 2kHz")
      (fields (field (name "MF") "WorldSemi"))
      (libsource (lib "WS2812B2020") (part "WS2812B2020"))
    )
    (comp (ref "D387")
      (value "WS2812B2020")
      (footprint "XL-1010RGBC-WS2812B")
      (description "LED; SMD; 2020; RGB; 2x2x0.84mm; 3.7Ã·5.3V; Lens: transparent; 2kHz")
      (fields (field (name "MF") "WorldSemi"))
      (libsource (lib "WS2812B2020") (part "WS2812B2020"))
    )
    (comp (ref "D388")
      (value "WS2812B2020")
      (footprint "XL-1010RGBC-WS2812B")
      (description "LED; SMD; 2020; RGB; 2x2x0.84mm; 3.7Ã·5.3V; Lens: transparent; 2kHz")
      (fields (field (name "MF") "WorldSemi"))
      (libsource (lib "WS2812B2020") (part "WS2812B2020"))
    )
    (comp (ref "D389")
      (value "WS2812B2020")
      (footprint "XL-1010RGBC-WS2812B")
      (description "LED; SMD; 2020; RGB; 2x2x0.84mm; 3.7Ã·5.3V; Lens: transparent; 2kHz")
      (fields (field (name "MF") "WorldSemi"))
      (libsource (lib "WS2812B2020") (part "WS2812B2020"))
    )
    (comp (ref "D390")
      (value "WS2812B2020")
      (footprint "XL-1010RGBC-WS2812B")
      (description "LED; SMD; 2020; RGB; 2x2x0.84mm; 3.7Ã·5.3V; Lens: transparent; 2kHz")
      (fields (field (name "MF") "WorldSemi"))
      (libsource (lib "WS2812B2020") (part "WS2812B2020"))
    )
    (comp (ref "D391")
      (value "WS2812B2020")
      (footprint "XL-1010RGBC-WS2812B")
      (description "LED; SMD; 2020; RGB; 2x2x0.84mm; 3.7Ã·5.3V; Lens: transparent; 2kHz")
      (fields (field (name "MF") "WorldSemi"))
      (libsource (lib "WS2812B2020") (part "WS2812B2020"))
    )
    (comp (ref "D392")
      (value "WS2812B2020")
      (footprint "XL-1010RGBC-WS2812B")
      (description "LED; SMD; 2020; RGB; 2x2x0.84mm; 3.7Ã·5.3V; Lens: transparent; 2kHz")
      (fields (field (name "MF") "WorldSemi"))
      (libsource (lib "WS2812B2020") (part "WS2812B2020"))
    )
    (comp (ref "D393")
      (value "WS2812B2020")
      (footprint "XL-1010RGBC-WS2812B")
      (description "LED; SMD; 2020; RGB; 2x2x0.84mm; 3.7Ã·5.3V; Lens: transparent; 2kHz")
      (fields (field (name "MF") "WorldSemi"))
      (libsource (lib "WS2812B2020") (part "WS2812B2020"))
    )
    (comp (ref "D394")
      (value "WS2812B2020")
      (footprint "XL-1010RGBC-WS2812B")
      (description "LED; SMD; 2020; RGB; 2x2x0.84mm; 3.7Ã·5.3V; Lens: transparent; 2kHz")
      (fields (field (name "MF") "WorldSemi"))
      (libsource (lib "WS2812B2020") (part "WS2812B2020"))
    )
    (comp (ref "D395")
      (value "WS2812B2020")
      (footprint "XL-1010RGBC-WS2812B")
      (description "LED; SMD; 2020; RGB; 2x2x0.84mm; 3.7Ã·5.3V; Lens: transparent; 2kHz")
      (fields (field (name "MF") "WorldSemi"))
      (libsource (lib "WS2812B2020") (part "WS2812B2020"))
    )
    (comp (ref "D396")
      (value "WS2812B2020")
      (footprint "XL-1010RGBC-WS2812B")
      (description "LED; SMD; 2020; RGB; 2x2x0.84mm; 3.7Ã·5.3V; Lens: transparent; 2kHz")
      (fields (field (name "MF") "WorldSemi"))
      (libsource (lib "WS2812B2020") (part "WS2812B2020"))
    )
    (comp (ref "D397")
      (value "WS2812B2020")
      (footprint "XL-1010RGBC-WS2812B")
      (description "LED; SMD; 2020; RGB; 2x2x0.84mm; 3.7Ã·5.3V; Lens: transparent; 2kHz")
      (fields (field (name "MF") "WorldSemi"))
      (libsource (lib "WS2812B2020") (part "WS2812B2020"))
    )
    (comp (ref "D398")
      (value "WS2812B2020")
      (footprint "XL-1010RGBC-WS2812B")
      (description "LED; SMD; 2020; RGB; 2x2x0.84mm; 3.7Ã·5.3V; Lens: transparent; 2kHz")
      (fields (field (name "MF") "WorldSemi"))
      (libsource (lib "WS2812B2020") (part "WS2812B2020"))
    )
    (comp (ref "D399")
      (value "WS2812B2020")
      (footprint "XL-1010RGBC-WS2812B")
      (description "LED; SMD; 2020; RGB; 2x2x0.84mm; 3.7Ã·5.3V; Lens: transparent; 2kHz")
      (fields (field (name "MF") "WorldSemi"))
      (libsource (lib "WS2812B2020") (part "WS2812B2020"))
    )
    (comp (ref "D400")
      (value "WS2812B2020")
      (footprint "XL-1010RGBC-WS2812B")
      (description "LED; SMD; 2020; RGB; 2x2x0.84mm; 3.7Ã·5.3V; Lens: transparent; 2kHz")
      (fields (field (name "MF") "WorldSemi"))
      (libsource (lib "WS2812B2020") (part "WS2812B2020"))
    )
    (comp (ref "D401")
      (value "WS2812B2020")
      (footprint "XL-1010RGBC-WS2812B")
      (description "LED; SMD; 2020; RGB; 2x2x0.84mm; 3.7Ã·5.3V; Lens: transparent; 2kHz")
      (fields (field (name "MF") "WorldSemi"))
      (libsource (lib "WS2812B2020") (part "WS2812B2020"))
    )
    (comp (ref "D402")
      (value "WS2812B2020")
      (footprint "XL-1010RGBC-WS2812B")
      (description "LED; SMD; 2020; RGB; 2x2x0.84mm; 3.7Ã·5.3V; Lens: transparent; 2kHz")
      (fields (field (name "MF") "WorldSemi"))
      (libsource (lib "WS2812B2020") (part "WS2812B2020"))
    )
    (comp (ref "D403")
      (value "WS2812B2020")
      (footprint "XL-1010RGBC-WS2812B")
      (description "LED; SMD; 2020; RGB; 2x2x0.84mm; 3.7Ã·5.3V; Lens: transparent; 2kHz")
      (fields (field (name "MF") "WorldSemi"))
      (libsource (lib "WS2812B2020") (part "WS2812B2020"))
    )
    (comp (ref "D404")
      (value "WS2812B2020")
      (footprint "XL-1010RGBC-WS2812B")
      (description "LED; SMD; 2020; RGB; 2x2x0.84mm; 3.7Ã·5.3V; Lens: transparent; 2kHz")
      (fields (field (name "MF") "WorldSemi"))
      (libsource (lib "WS2812B2020") (part "WS2812B2020"))
    )
    (comp (ref "D405")
      (value "WS2812B2020")
      (footprint "XL-1010RGBC-WS2812B")
      (description "LED; SMD; 2020; RGB; 2x2x0.84mm; 3.7Ã·5.3V; Lens: transparent; 2kHz")
      (fields (field (name "MF") "WorldSemi"))
      (libsource (lib "WS2812B2020") (part "WS2812B2020"))
    )
    (comp (ref "D406")
      (value "WS2812B2020")
      (footprint "XL-1010RGBC-WS2812B")
      (description "LED; SMD; 2020; RGB; 2x2x0.84mm; 3.7Ã·5.3V; Lens: transparent; 2kHz")
      (fields (field (name "MF") "WorldSemi"))
      (libsource (lib "WS2812B2020") (part "WS2812B2020"))
    )
    (comp (ref "D407")
      (value "WS2812B2020")
      (footprint "XL-1010RGBC-WS2812B")
      (description "LED; SMD; 2020; RGB; 2x2x0.84mm; 3.7Ã·5.3V; Lens: transparent; 2kHz")
      (fields (field (name "MF") "WorldSemi"))
      (libsource (lib "WS2812B2020") (part "WS2812B2020"))
    )
    (comp (ref "D408")
      (value "WS2812B2020")
      (footprint "XL-1010RGBC-WS2812B")
      (description "LED; SMD; 2020; RGB; 2x2x0.84mm; 3.7Ã·5.3V; Lens: transparent; 2kHz")
      (fields (field (name "MF") "WorldSemi"))
      (libsource (lib "WS2812B2020") (part "WS2812B2020"))
    )
    (comp (ref "D409")
      (value "WS2812B2020")
      (footprint "XL-1010RGBC-WS2812B")
      (description "LED; SMD; 2020; RGB; 2x2x0.84mm; 3.7Ã·5.3V; Lens: transparent; 2kHz")
      (fields (field (name "MF") "WorldSemi"))
      (libsource (lib "WS2812B2020") (part "WS2812B2020"))
    )
  )
  (nets
    (net (code "1") (name "+VUSB") (class "Default")
      (node (ref "D10") (pin "4") (pinfunction "VDD_4") (pintype "power_in"))
      (node (ref "D100") (pin "4") (pinfunction "VDD_4") (pintype "power_in"))
      (node (ref "D101") (pin "4") (pinfunction "VDD_4") (pintype "power_in"))
      (node (ref "D102") (pin "4") (pinfunction "VDD_4") (pintype "power_in"))
      (node (ref "D103") (pin "4") (pinfunction "VDD_4") (pintype "power_in"))
      (node (ref "D104") (pin "4") (pinfunction "VDD_4") (pintype "power_in"))
      (node (ref "D105") (pin "4") (pinfunction "VDD_4") (pintype "power_in"))
      (node (ref "D106") (pin "4") (pinfunction "VDD_4") (pintype "power_in"))
      (node (ref "D107") (pin "4") (pinfunction "VDD_4") (pintype "power_in"))
      (node (ref "D108") (pin "4") (pinfunction "VDD_4") (pintype "power_in"))
      (node (ref "D109") (pin "4") (pinfunction "VDD_4") (pintype "power_in"))
      (node (ref "D11") (pin "4") (pinfunction "VDD_4") (pintype "power_in"))
      (node (ref "D110") (pin "4") (pinfunction "VDD_4") (pintype "power_in"))
      (node (ref "D111") (pin "4") (pinfunction "VDD_4") (pintype "power_in"))
      (node (ref "D112") (pin "4") (pinfunction "VDD_4") (pintype "power_in"))
      (node (ref "D113") (pin "4") (pinfunction "VDD_4") (pintype "power_in"))
      (node (ref "D114") (pin "4") (pinfunction "VDD_4") (pintype "power_in"))
      (node (ref "D115") (pin "4") (pinfunction "VDD_4") (pintype "power_in"))
      (node (ref "D116") (pin "4") (pinfunction "VDD_4") (pintype "power_in"))
      (node (ref "D117") (pin "4") (pinfunction "VDD_4") (pintype "power_in"))
      (node (ref "D118") (pin "4") (pinfunction "VDD_4") (pintype "power_in"))
      (node (ref "D119") (pin "4") (pinfunction "VDD_4") (pintype "power_in"))
      (node (ref "D12") (pin "4") (pinfunction "VDD_4") (pintype "power_in"))
      (node (ref "D120") (pin "4") (pinfunction "VDD_4") (pintype "power_in"))
      (node (ref "D121") (pin "4") (pinfunction "VDD_4") (pintype "power_in"))
      (node (ref "D122") (pin "4") (pinfunction "VDD_4") (pintype "power_in"))
      (node (ref "D123") (pin "4") (pinfunction "VDD_4") (pintype "power_in"))
      (node (ref "D124") (pin "4") (pinfunction "VDD_4") (pintype "power_in"))
      (node (ref "D125") (pin "4") (pinfunction "VDD_4") (pintype "power_in"))
      (node (ref "D126") (pin "4") (pinfunction "VDD_4") (pintype "power_in"))
      (node (ref "D127") (pin "4") (pinfunction "VDD_4") (pintype "power_in"))
      (node (ref "D128") (pin "4") (pinfunction "VDD_4") (pintype "power_in"))
      (node (ref "D129") (pin "4") (pinfunction "VDD_4") (pintype "power_in"))
      (node (ref "D13") (pin "4") (pinfunction "VDD_4") (pintype "power_in"))
      (node (ref "D130") (pin "4") (pinfunction "VDD_4") (pintype "power_in"))
      (node (ref "D131") (pin "4") (pinfunction "VDD_4") (pintype "power_in"))
      (node (ref "D132") (pin "4") (pinfunction "VDD_4") (pintype "power_in"))
      (node (ref "D133") (pin "4") (pinfunction "VDD_4") (pintype "power_in"))
      (node (ref "D134") (pin "4") (pinfunction "VDD_4") (pintype "power_in"))
      (node (ref "D135") (pin "4") (pinfunction "VDD_4") (pintype "power_in"))
      (node (ref "D136") (pin "4") (pinfunction "VDD_4") (pintype "power_in"))
      (node (ref "D137") (pin "4") (pinfunction "VDD_4") (pintype "power_in"))
      (node (ref "D138") (pin "4") (pinfunction "VDD_4") (pintype "power_in"))
      (node (ref "D139") (pin "4") (pinfunction "VDD_4") (pintype "power_in"))
      (node (ref "D14") (pin "4") (pinfunction "VDD_4") (pintype "power_in"))
      (node (ref "D140") (pin "4") (pinfunction "VDD_4") (pintype "power_in"))
      (node (ref "D141") (pin "4") (pinfunction "VDD_4") (pintype "power_in"))
      (node (ref "D142") (pin "4") (pinfunction "VDD_4") (pintype "power_in"))
      (node (ref "D143") (pin "4") (pinfunction "VDD_4") (pintype "power_in"))
      (node (ref "D144") (pin "4") (pinfunction "VDD_4") (pintype "power_in"))
      (node (ref "D145") (pin "4") (pinfunction "VDD_4") (pintype "power_in"))
      (node (ref "D146") (pin "4") (pinfunction "VDD_4") (pintype "power_in"))
      (node (ref "D147") (pin "4") (pinfunction "VDD_4") (pintype "power_in"))
      (node (ref "D148") (pin "4") (pinfunction "VDD_4") (pintype "power_in"))
      (node (ref "D149") (pin "4") (pinfunction "VDD_4") (pintype "power_in"))
      (node (ref "D15") (pin "4") (pinfunction "VDD_4") (pintype "power_in"))
      (node (ref "D150") (pin "4") (pinfunction "VDD_4") (pintype "power_in"))
      (node (ref "D151") (pin "4") (pinfunction "VDD_4") (pintype "power_in"))
      (node (ref "D152") (pin "4") (pinfunction "VDD_4") (pintype "power_in"))
      (node (ref "D153") (pin "4") (pinfunction "VDD_4") (pintype "power_in"))
      (node (ref "D154") (pin "4") (pinfunction "VDD_4") (pintype "power_in"))
      (node (ref "D155") (pin "4") (pinfunction "VDD_4") (pintype "power_in"))
      (node (ref "D156") (pin "4") (pinfunction "VDD_4") (pintype "power_in"))
      (node (ref "D157") (pin "4") (pinfunction "VDD_4") (pintype "power_in"))
      (node (ref "D158") (pin "4") (pinfunction "VDD_4") (pintype "power_in"))
      (node (ref "D159") (pin "4") (pinfunction "VDD_4") (pintype "power_in"))
      (node (ref "D16") (pin "4") (pinfunction "VDD_4") (pintype "power_in"))
      (node (ref "D160") (pin "4") (pinfunction "VDD_4") (pintype "power_in"))
      (node (ref "D161") (pin "4") (pinfunction "VDD_4") (pintype "power_in"))
      (node (ref "D162") (pin "4") (pinfunction "VDD_4") (pintype "power_in"))
      (node (ref "D163") (pin "4") (pinfunction "VDD_4") (pintype "power_in"))
      (node (ref "D164") (pin "4") (pinfunction "VDD_4") (pintype "power_in"))
      (node (ref "D165") (pin "4") (pinfunction "VDD_4") (pintype "power_in"))
      (node (ref "D166") (pin "4") (pinfunction "VDD_4") (pintype "power_in"))
      (node (ref "D167") (pin "4") (pinfunction "VDD_4") (pintype "power_in"))
      (node (ref "D168") (pin "4") (pinfunction "VDD_4") (pintype "power_in"))
      (node (ref "D169") (pin "4") (pinfunction "VDD_4") (pintype "power_in"))
      (node (ref "D17") (pin "4") (pinfunction "VDD_4") (pintype "power_in"))
      (node (ref "D170") (pin "4") (pinfunction "VDD_4") (pintype "power_in"))
      (node (ref "D171") (pin "4") (pinfunction "VDD_4") (pintype "power_in"))
      (node (ref "D172") (pin "4") (pinfunction "VDD_4") (pintype "power_in"))
      (node (ref "D173") (pin "4") (pinfunction "VDD_4") (pintype "power_in"))
      (node (ref "D174") (pin "4") (pinfunction "VDD_4") (pintype "power_in"))
      (node (ref "D175") (pin "4") (pinfunction "VDD_4") (pintype "power_in"))
      (node (ref "D176") (pin "4") (pinfunction "VDD_4") (pintype "power_in"))
      (node (ref "D177") (pin "4") (pinfunction "VDD_4") (pintype "power_in"))
      (node (ref "D178") (pin "4") (pinfunction "VDD_4") (pintype "power_in"))
      (node (ref "D179") (pin "4") (pinfunction "VDD_4") (pintype "power_in"))
      (node (ref "D18") (pin "4") (pinfunction "VDD_4") (pintype "power_in"))
      (node (ref "D180") (pin "4") (pinfunction "VDD_4") (pintype "power_in"))
      (node (ref "D181") (pin "4") (pinfunction "VDD_4") (pintype "power_in"))
      (node (ref "D182") (pin "4") (pinfunction "VDD_4") (pintype "power_in"))
      (node (ref "D183") (pin "4") (pinfunction "VDD_4") (pintype "power_in"))
      (node (ref "D184") (pin "4") (pinfunction "VDD_4") (pintype "power_in"))
      (node (ref "D185") (pin "4") (pinfunction "VDD_4") (pintype "power_in"))
      (node (ref "D186") (pin "4") (pinfunction "VDD_4") (pintype "power_in"))
      (node (ref "D187") (pin "4") (pinfunction "VDD_4") (pintype "power_in"))
      (node (ref "D188") (pin "4") (pinfunction "VDD_4") (pintype "power_in"))
      (node (ref "D189") (pin "4") (pinfunction "VDD_4") (pintype "power_in"))
      (node (ref "D19") (pin "4") (pinfunction "VDD_4") (pintype "power_in"))
      (node (ref "D190") (pin "4") (pinfunction "VDD_4") (pintype "power_in"))
      (node (ref "D191") (pin "4") (pinfunction "VDD_4") (pintype "power_in"))
      (node (ref "D192") (pin "4") (pinfunction "VDD_4") (pintype "power_in"))
      (node (ref "D193") (pin "4") (pinfunction "VDD_4") (pintype "power_in"))
      (node (ref "D194") (pin "4") (pinfunction "VDD_4") (pintype "power_in"))
      (node (ref "D195") (pin "4") (pinfunction "VDD_4") (pintype "power_in"))
      (node (ref "D196") (pin "4") (pinfunction "VDD_4") (pintype "power_in"))
      (node (ref "D197") (pin "4") (pinfunction "VDD_4") (pintype "power_in"))
      (node (ref "D198") (pin "4") (pinfunction "VDD_4") (pintype "power_in"))
      (node (ref "D199") (pin "4") (pinfunction "VDD_4") (pintype "power_in"))
      (node (ref "D20") (pin "4") (pinfunction "VDD_4") (pintype "power_in"))
      (node (ref "D200") (pin "4") (pinfunction "VDD_4") (pintype "power_in"))
      (node (ref "D201") (pin "4") (pinfunction "VDD_4") (pintype "power_in"))
      (node (ref "D202") (pin "4") (pinfunction "VDD_4") (pintype "power_in"))
      (node (ref "D203") (pin "4") (pinfunction "VDD_4") (pintype "power_in"))
      (node (ref "D204") (pin "4") (pinfunction "VDD_4") (pintype "power_in"))
      (node (ref "D205") (pin "4") (pinfunction "VDD_4") (pintype "power_in"))
      (node (ref "D206") (pin "4") (pinfunction "VDD_4") (pintype "power_in"))
      (node (ref "D207") (pin "4") (pinfunction "VDD_4") (pintype "power_in"))
      (node (ref "D208") (pin "4") (pinfunction "VDD_4") (pintype "power_in"))
      (node (ref "D209") (pin "4") (pinfunction "VDD_4") (pintype "power_in"))
      (node (ref "D21") (pin "4") (pinfunction "VDD_4") (pintype "power_in"))
      (node (ref "D210") (pin "4") (pinfunction "VDD_4") (pintype "power_in"))
      (node (ref "D211") (pin "4") (pinfunction "VDD_4") (pintype "power_in"))
      (node (ref "D212") (pin "4") (pinfunction "VDD_4") (pintype "power_in"))
      (node (ref "D213") (pin "4") (pinfunction "VDD_4") (pintype "power_in"))
      (node (ref "D214") (pin "4") (pinfunction "VDD_4") (pintype "power_in"))
      (node (ref "D215") (pin "4") (pinfunction "VDD_4") (pintype "power_in"))
      (node (ref "D216") (pin "4") (pinfunction "VDD_4") (pintype "power_in"))
      (node (ref "D217") (pin "4") (pinfunction "VDD_4") (pintype "power_in"))
      (node (ref "D218") (pin "4") (pinfunction "VDD_4") (pintype "power_in"))
      (node (ref "D219") (pin "4") (pinfunction "VDD_4") (pintype "power_in"))
      (node (ref "D22") (pin "4") (pinfunction "VDD_4") (pintype "power_in"))
      (node (ref "D220") (pin "4") (pinfunction "VDD_4") (pintype "power_in"))
      (node (ref "D221") (pin "4") (pinfunction "VDD_4") (pintype "power_in"))
      (node (ref "D222") (pin "4") (pinfunction "VDD_4") (pintype "power_in"))
      (node (ref "D223") (pin "4") (pinfunction "VDD_4") (pintype "power_in"))
      (node (ref "D224") (pin "4") (pinfunction "VDD_4") (pintype "power_in"))
      (node (ref "D225") (pin "4") (pinfunction "VDD_4") (pintype "power_in"))
      (node (ref "D226") (pin "4") (pinfunction "VDD_4") (pintype "power_in"))
      (node (ref "D227") (pin "4") (pinfunction "VDD_4") (pintype "power_in"))
      (node (ref "D228") (pin "4") (pinfunction "VDD_4") (pintype "power_in"))
      (node (ref "D229") (pin "4") (pinfunction "VDD_4") (pintype "power_in"))
      (node (ref "D23") (pin "4") (pinfunction "VDD_4") (pintype "power_in"))
      (node (ref "D230") (pin "4") (pinfunction "VDD_4") (pintype "power_in"))
      (node (ref "D231") (pin "4") (pinfunction "VDD_4") (pintype "power_in"))
      (node (ref "D232") (pin "4") (pinfunction "VDD_4") (pintype "power_in"))
      (node (ref "D233") (pin "4") (pinfunction "VDD_4") (pintype "power_in"))
      (node (ref "D234") (pin "4") (pinfunction "VDD_4") (pintype "power_in"))
      (node (ref "D235") (pin "4") (pinfunction "VDD_4") (pintype "power_in"))
      (node (ref "D236") (pin "4") (pinfunction "VDD_4") (pintype "power_in"))
      (node (ref "D237") (pin "4") (pinfunction "VDD_4") (pintype "power_in"))
      (node (ref "D238") (pin "4") (pinfunction "VDD_4") (pintype "power_in"))
      (node (ref "D239") (pin "4") (pinfunction "VDD_4") (pintype "power_in"))
      (node (ref "D24") (pin "4") (pinfunction "VDD_4") (pintype "power_in"))
      (node (ref "D240") (pin "4") (pinfunction "VDD_4") (pintype "power_in"))
      (node (ref "D241") (pin "4") (pinfunction "VDD_4") (pintype "power_in"))
      (node (ref "D242") (pin "4") (pinfunction "VDD_4") (pintype "power_in"))
      (node (ref "D243") (pin "4") (pinfunction "VDD_4") (pintype "power_in"))
      (node (ref "D244") (pin "4") (pinfunction "VDD_4") (pintype "power_in"))
      (node (ref "D245") (pin "4") (pinfunction "VDD_4") (pintype "power_in"))
      (node (ref "D246") (pin "4") (pinfunction "VDD_4") (pintype "power_in"))
      (node (ref "D247") (pin "4") (pinfunction "VDD_4") (pintype "power_in"))
      (node (ref "D248") (pin "4") (pinfunction "VDD_4") (pintype "power_in"))
      (node (ref "D249") (pin "4") (pinfunction "VDD_4") (pintype "power_in"))
      (node (ref "D25") (pin "4") (pinfunction "VDD_4") (pintype "power_in"))
      (node (ref "D250") (pin "4") (pinfunction "VDD_4") (pintype "power_in"))
      (node (ref "D251") (pin "4") (pinfunction "VDD_4") (pintype "power_in"))
      (node (ref "D252") (pin "4") (pinfunction "VDD_4") (pintype "power_in"))
      (node (ref "D253") (pin "4") (pinfunction "VDD_4") (pintype "power_in"))
      (node (ref "D254") (pin "4") (pinfunction "VDD_4") (pintype "power_in"))
      (node (ref "D255") (pin "4") (pinfunction "VDD_4") (pintype "power_in"))
      (node (ref "D256") (pin "4") (pinfunction "VDD_4") (pintype "power_in"))
      (node (ref "D257") (pin "4") (pinfunction "VDD_4") (pintype "power_in"))
      (node (ref "D258") (pin "4") (pinfunction "VDD_4") (pintype "power_in"))
      (node (ref "D259") (pin "4") (pinfunction "VDD_4") (pintype "power_in"))
      (node (ref "D26") (pin "4") (pinfunction "VDD_4") (pintype "power_in"))
      (node (ref "D260") (pin "4") (pinfunction "VDD_4") (pintype "power_in"))
      (node (ref "D261") (pin "4") (pinfunction "VDD_4") (pintype "power_in"))
      (node (ref "D262") (pin "4") (pinfunction "VDD_4") (pintype "power_in"))
      (node (ref "D263") (pin "4") (pinfunction "VDD_4") (pintype "power_in"))
      (node (ref "D264") (pin "4") (pinfunction "VDD_4") (pintype "power_in"))
      (node (ref "D265") (pin "4") (pinfunction "VDD_4") (pintype "power_in"))
      (node (ref "D266") (pin "4") (pinfunction "VDD_4") (pintype "power_in"))
      (node (ref "D267") (pin "4") (pinfunction "VDD_4") (pintype "power_in"))
      (node (ref "D268") (pin "4") (pinfunction "VDD_4") (pintype "power_in"))
      (node (ref "D269") (pin "4") (pinfunction "VDD_4") (pintype "power_in"))
      (node (ref "D27") (pin "4") (pinfunction "VDD_4") (pintype "power_in"))
      (node (ref "D270") (pin "4") (pinfunction "VDD_4") (pintype "power_in"))
      (node (ref "D271") (pin "4") (pinfunction "VDD_4") (pintype "power_in"))
      (node (ref "D272") (pin "4") (pinfunction "VDD_4") (pintype "power_in"))
      (node (ref "D273") (pin "4") (pinfunction "VDD_4") (pintype "power_in"))
      (node (ref "D274") (pin "4") (pinfunction "VDD_4") (pintype "power_in"))
      (node (ref "D275") (pin "4") (pinfunction "VDD_4") (pintype "power_in"))
      (node (ref "D276") (pin "4") (pinfunction "VDD_4") (pintype "power_in"))
      (node (ref "D277") (pin "4") (pinfunction "VDD_4") (pintype "power_in"))
      (node (ref "D278") (pin "4") (pinfunction "VDD_4") (pintype "power_in"))
      (node (ref "D279") (pin "4") (pinfunction "VDD_4") (pintype "power_in"))
      (node (ref "D28") (pin "4") (pinfunction "VDD_4") (pintype "power_in"))
      (node (ref "D280") (pin "4") (pinfunction "VDD_4") (pintype "power_in"))
      (node (ref "D281") (pin "4") (pinfunction "VDD_4") (pintype "power_in"))
      (node (ref "D282") (pin "4") (pinfunction "VDD_4") (pintype "power_in"))
      (node (ref "D283") (pin "4") (pinfunction "VDD_4") (pintype "power_in"))
      (node (ref "D284") (pin "4") (pinfunction "VDD_4") (pintype "power_in"))
      (node (ref "D285") (pin "4") (pinfunction "VDD_4") (pintype "power_in"))
      (node (ref "D286") (pin "4") (pinfunction "VDD_4") (pintype "power_in"))
      (node (ref "D287") (pin "4") (pinfunction "VDD_4") (pintype "power_in"))
      (node (ref "D288") (pin "4") (pinfunction "VDD_4") (pintype "power_in"))
      (node (ref "D289") (pin "4") (pinfunction "VDD_4") (pintype "power_in"))
      (node (ref "D29") (pin "4") (pinfunction "VDD_4") (pintype "power_in"))
      (node (ref "D290") (pin "4") (pinfunction "VDD_4") (pintype "power_in"))
      (node (ref "D291") (pin "4") (pinfunction "VDD_4") (pintype "power_in"))
      (node (ref "D292") (pin "4") (pinfunction "VDD_4") (pintype "power_in"))
      (node (ref "D293") (pin "4") (pinfunction "VDD_4") (pintype "power_in"))
      (node (ref "D294") (pin "4") (pinfunction "VDD_4") (pintype "power_in"))
      (node (ref "D295") (pin "4") (pinfunction "VDD_4") (pintype "power_in"))
      (node (ref "D296") (pin "4") (pinfunction "VDD_4") (pintype "power_in"))
      (node (ref "D297") (pin "4") (pinfunction "VDD_4") (pintype "power_in"))
      (node (ref "D298") (pin "4") (pinfunction "VDD_4") (pintype "power_in"))
      (node (ref "D299") (pin "4") (pinfunction "VDD_4") (pintype "power_in"))
      (node (ref "D30") (pin "4") (pinfunction "VDD_4") (pintype "power_in"))
      (node (ref "D300") (pin "4") (pinfunction "VDD_4") (pintype "power_in"))
      (node (ref "D301") (pin "4") (pinfunction "VDD_4") (pintype "power_in"))
      (node (ref "D302") (pin "4") (pinfunction "VDD_4") (pintype "power_in"))
      (node (ref "D303") (pin "4") (pinfunction "VDD_4") (pintype "power_in"))
      (node (ref "D304") (pin "4") (pinfunction "VDD_4") (pintype "power_in"))
      (node (ref "D305") (pin "4") (pinfunction "VDD_4") (pintype "power_in"))
      (node (ref "D306") (pin "4") (pinfunction "VDD_4") (pintype "power_in"))
      (node (ref "D307") (pin "4") (pinfunction "VDD_4") (pintype "power_in"))
      (node (ref "D308") (pin "4") (pinfunction "VDD_4") (pintype "power_in"))
      (node (ref "D309") (pin "4") (pinfunction "VDD_4") (pintype "power_in"))
      (node (ref "D31") (pin "4") (pinfunction "VDD_4") (pintype "power_in"))
      (node (ref "D310") (pin "4") (pinfunction "VDD_4") (pintype "power_in"))
      (node (ref "D311") (pin "4") (pinfunction "VDD_4") (pintype "power_in"))
      (node (ref "D312") (pin "4") (pinfunction "VDD_4") (pintype "power_in"))
      (node (ref "D313") (pin "4") (pinfunction "VDD_4") (pintype "power_in"))
      (node (ref "D314") (pin "4") (pinfunction "VDD_4") (pintype "power_in"))
      (node (ref "D315") (pin "4") (pinfunction "VDD_4") (pintype "power_in"))
      (node (ref "D316") (pin "4") (pinfunction "VDD_4") (pintype "power_in"))
      (node (ref "D317") (pin "4") (pinfunction "VDD_4") (pintype "power_in"))
      (node (ref "D318") (pin "4") (pinfunction "VDD_4") (pintype "power_in"))
      (node (ref "D319") (pin "4") (pinfunction "VDD_4") (pintype "power_in"))
      (node (ref "D32") (pin "4") (pinfunction "VDD_4") (pintype "power_in"))
      (node (ref "D320") (pin "4") (pinfunction "VDD_4") (pintype "power_in"))
      (node (ref "D321") (pin "4") (pinfunction "VDD_4") (pintype "power_in"))
      (node (ref "D322") (pin "4") (pinfunction "VDD_4") (pintype "power_in"))
      (node (ref "D323") (pin "4") (pinfunction "VDD_4") (pintype "power_in"))
      (node (ref "D324") (pin "4") (pinfunction "VDD_4") (pintype "power_in"))
      (node (ref "D325") (pin "4") (pinfunction "VDD_4") (pintype "power_in"))
      (node (ref "D326") (pin "4") (pinfunction "VDD_4") (pintype "power_in"))
      (node (ref "D327") (pin "4") (pinfunction "VDD_4") (pintype "power_in"))
      (node (ref "D328") (pin "4") (pinfunction "VDD_4") (pintype "power_in"))
      (node (ref "D329") (pin "4") (pinfunction "VDD_4") (pintype "power_in"))
      (node (ref "D33") (pin "4") (pinfunction "VDD_4") (pintype "power_in"))
      (node (ref "D330") (pin "4") (pinfunction "VDD_4") (pintype "power_in"))
      (node (ref "D331") (pin "4") (pinfunction "VDD_4") (pintype "power_in"))
      (node (ref "D332") (pin "4") (pinfunction "VDD_4") (pintype "power_in"))
      (node (ref "D333") (pin "4") (pinfunction "VDD_4") (pintype "power_in"))
      (node (ref "D334") (pin "4") (pinfunction "VDD_4") (pintype "power_in"))
      (node (ref "D335") (pin "4") (pinfunction "VDD_4") (pintype "power_in"))
      (node (ref "D336") (pin "4") (pinfunction "VDD_4") (pintype "power_in"))
      (node (ref "D337") (pin "4") (pinfunction "VDD_4") (pintype "power_in"))
      (node (ref "D338") (pin "4") (pinfunction "VDD_4") (pintype "power_in"))
      (node (ref "D339") (pin "4") (pinfunction "VDD_4") (pintype "power_in"))
      (node (ref "D34") (pin "4") (pinfunction "VDD_4") (pintype "power_in"))
      (node (ref "D340") (pin "4") (pinfunction "VDD_4") (pintype "power_in"))
      (node (ref "D341") (pin "4") (pinfunction "VDD_4") (pintype "power_in"))
      (node (ref "D342") (pin "4") (pinfunction "VDD_4") (pintype "power_in"))
      (node (ref "D343") (pin "4") (pinfunction "VDD_4") (pintype "power_in"))
      (node (ref "D344") (pin "4") (pinfunction "VDD_4") (pintype "power_in"))
      (node (ref "D345") (pin "4") (pinfunction "VDD_4") (pintype "power_in"))
      (node (ref "D346") (pin "4") (pinfunction "VDD_4") (pintype "power_in"))
      (node (ref "D347") (pin "4") (pinfunction "VDD_4") (pintype "power_in"))
      (node (ref "D348") (pin "4") (pinfunction "VDD_4") (pintype "power_in"))
      (node (ref "D349") (pin "4") (pinfunction "VDD_4") (pintype "power_in"))
      (node (ref "D35") (pin "4") (pinfunction "VDD_4") (pintype "power_in"))
      (node (ref "D350") (pin "4") (pinfunction "VDD_4") (pintype "power_in"))
      (node (ref "D351") (pin "4") (pinfunction "VDD_4") (pintype "power_in"))
      (node (ref "D352") (pin "4") (pinfunction "VDD_4") (pintype "power_in"))
      (node (ref "D353") (pin "4") (pinfunction "VDD_4") (pintype "power_in"))
      (node (ref "D354") (pin "4") (pinfunction "VDD_4") (pintype "power_in"))
      (node (ref "D355") (pin "4") (pinfunction "VDD_4") (pintype "power_in"))
      (node (ref "D356") (pin "4") (pinfunction "VDD_4") (pintype "power_in"))
      (node (ref "D357") (pin "4") (pinfunction "VDD_4") (pintype "power_in"))
      (node (ref "D358") (pin "4") (pinfunction "VDD_4") (pintype "power_in"))
      (node (ref "D359") (pin "4") (pinfunction "VDD_4") (pintype "power_in"))
      (node (ref "D36") (pin "4") (pinfunction "VDD_4") (pintype "power_in"))
      (node (ref "D360") (pin "4") (pinfunction "VDD_4") (pintype "power_in"))
      (node (ref "D361") (pin "4") (pinfunction "VDD_4") (pintype "power_in"))
      (node (ref "D362") (pin "4") (pinfunction "VDD_4") (pintype "power_in"))
      (node (ref "D363") (pin "4") (pinfunction "VDD_4") (pintype "power_in"))
      (node (ref "D364") (pin "4") (pinfunction "VDD_4") (pintype "power_in"))
      (node (ref "D365") (pin "4") (pinfunction "VDD_4") (pintype "power_in"))
      (node (ref "D366") (pin "4") (pinfunction "VDD_4") (pintype "power_in"))
      (node (ref "D367") (pin "4") (pinfunction "VDD_4") (pintype "power_in"))
      (node (ref "D368") (pin "4") (pinfunction "VDD_4") (pintype "power_in"))
      (node (ref "D369") (pin "4") (pinfunction "VDD_4") (pintype "power_in"))
      (node (ref "D37") (pin "4") (pinfunction "VDD_4") (pintype "power_in"))
      (node (ref "D370") (pin "4") (pinfunction "VDD_4") (pintype "power_in"))
      (node (ref "D371") (pin "4") (pinfunction "VDD_4") (pintype "power_in"))
      (node (ref "D372") (pin "4") (pinfunction "VDD_4") (pintype "power_in"))
      (node (ref "D373") (pin "4") (pinfunction "VDD_4") (pintype "power_in"))
      (node (ref "D374") (pin "4") (pinfunction "VDD_4") (pintype "power_in"))
      (node (ref "D375") (pin "4") (pinfunction "VDD_4") (pintype "power_in"))
      (node (ref "D376") (pin "4") (pinfunction "VDD_4") (pintype "power_in"))
      (node (ref "D377") (pin "4") (pinfunction "VDD_4") (pintype "power_in"))
      (node (ref "D378") (pin "4") (pinfunction "VDD_4") (pintype "power_in"))
      (node (ref "D379") (pin "4") (pinfunction "VDD_4") (pintype "power_in"))
      (node (ref "D38") (pin "4") (pinfunction "VDD_4") (pintype "power_in"))
      (node (ref "D380") (pin "4") (pinfunction "VDD_4") (pintype "power_in"))
      (node (ref "D381") (pin "4") (pinfunction "VDD_4") (pintype "power_in"))
      (node (ref "D382") (pin "4") (pinfunction "VDD_4") (pintype "power_in"))
      (node (ref "D383") (pin "4") (pinfunction "VDD_4") (pintype "power_in"))
      (node (ref "D384") (pin "4") (pinfunction "VDD_4") (pintype "power_in"))
      (node (ref "D385") (pin "4") (pinfunction "VDD_4") (pintype "power_in"))
      (node (ref "D386") (pin "4") (pinfunction "VDD_4") (pintype "power_in"))
      (node (ref "D387") (pin "4") (pinfunction "VDD_4") (pintype "power_in"))
      (node (ref "D388") (pin "4") (pinfunction "VDD_4") (pintype "power_in"))
      (node (ref "D389") (pin "4") (pinfunction "VDD_4") (pintype "power_in"))
      (node (ref "D39") (pin "4") (pinfunction "VDD_4") (pintype "power_in"))
      (node (ref "D390") (pin "4") (pinfunction "VDD_4") (pintype "power_in"))
      (node (ref "D391") (pin "4") (pinfunction "VDD_4") (pintype "power_in"))
      (node (ref "D392") (pin "4") (pinfunction "VDD_4") (pintype "power_in"))
      (node (ref "D393") (pin "4") (pinfunction "VDD_4") (pintype "power_in"))
      (node (ref "D394") (pin "4") (pinfunction "VDD_4") (pintype "power_in"))
      (node (ref "D395") (pin "4") (pinfunction "VDD_4") (pintype "power_in"))
      (node (ref "D396") (pin "4") (pinfunction "VDD_4") (pintype "power_in"))
      (node (ref "D397") (pin "4") (pinfunction "VDD_4") (pintype "power_in"))
      (node (ref "D398") (pin "4") (pinfunction "VDD_4") (pintype "power_in"))
      (node (ref "D399") (pin "4") (pinfunction "VDD_4") (pintype "power_in"))
      (node (ref "D40") (pin "4") (pinfunction "VDD_4") (pintype "power_in"))
      (node (ref "D400") (pin "4") (pinfunction "VDD_4") (pintype "power_in"))
      (node (ref "D401") (pin "4") (pinfunction "VDD_4") (pintype "power_in"))
      (node (ref "D402") (pin "4") (pinfunction "VDD_4") (pintype "power_in"))
      (node (ref "D403") (pin "4") (pinfunction "VDD_4") (pintype "power_in"))
      (node (ref "D404") (pin "4") (pinfunction "VDD_4") (pintype "power_in"))
      (node (ref "D405") (pin "4") (pinfunction "VDD_4") (pintype "power_in"))
      (node (ref "D406") (pin "4") (pinfunction "VDD_4") (pintype "power_in"))
      (node (ref "D407") (pin "4") (pinfunction "VDD_4") (pintype "power_in"))
      (node (ref "D408") (pin "4") (pinfunction "VDD_4") (pintype "power_in"))
      (node (ref "D409") (pin "4") (pinfunction "VDD_4") (pintype "power_in"))
      (node (ref "D41") (pin "4") (pinfunction "VDD_4") (pintype "power_in"))
      (node (ref "D42") (pin "4") (pinfunction "VDD_4") (pintype "power_in"))
      (node (ref "D43") (pin "4") (pinfunction "VDD_4") (pintype "power_in"))
      (node (ref "D44") (pin "4") (pinfunction "VDD_4") (pintype "power_in"))
      (node (ref "D45") (pin "4") (pinfunction "VDD_4") (pintype "power_in"))
      (node (ref "D46") (pin "4") (pinfunction "VDD_4") (pintype "power_in"))
      (node (ref "D47") (pin "4") (pinfunction "VDD_4") (pintype "power_in"))
      (node (ref "D48") (pin "4") (pinfunction "VDD_4") (pintype "power_in"))
      (node (ref "D49") (pin "4") (pinfunction "VDD_4") (pintype "power_in"))
      (node (ref "D50") (pin "4") (pinfunction "VDD_4") (pintype "power_in"))
      (node (ref "D51") (pin "4") (pinfunction "VDD_4") (pintype "power_in"))
      (node (ref "D52") (pin "4") (pinfunction "VDD_4") (pintype "power_in"))
      (node (ref "D53") (pin "4") (pinfunction "VDD_4") (pintype "power_in"))
      (node (ref "D54") (pin "4") (pinfunction "VDD_4") (pintype "power_in"))
      (node (ref "D55") (pin "4") (pinfunction "VDD_4") (pintype "power_in"))
      (node (ref "D56") (pin "4") (pinfunction "VDD_4") (pintype "power_in"))
      (node (ref "D57") (pin "4") (pinfunction "VDD_4") (pintype "power_in"))
      (node (ref "D58") (pin "4") (pinfunction "VDD_4") (pintype "power_in"))
      (node (ref "D59") (pin "4") (pinfunction "VDD_4") (pintype "power_in"))
      (node (ref "D60") (pin "4") (pinfunction "VDD_4") (pintype "power_in"))
      (node (ref "D61") (pin "4") (pinfunction "VDD_4") (pintype "power_in"))
      (node (ref "D62") (pin "4") (pinfunction "VDD_4") (pintype "power_in"))
      (node (ref "D63") (pin "4") (pinfunction "VDD_4") (pintype "power_in"))
      (node (ref "D64") (pin "4") (pinfunction "VDD_4") (pintype "power_in"))
      (node (ref "D65") (pin "4") (pinfunction "VDD_4") (pintype "power_in"))
      (node (ref "D66") (pin "4") (pinfunction "VDD_4") (pintype "power_in"))
      (node (ref "D67") (pin "4") (pinfunction "VDD_4") (pintype "power_in"))
      (node (ref "D68") (pin "4") (pinfunction "VDD_4") (pintype "power_in"))
      (node (ref "D69") (pin "4") (pinfunction "VDD_4") (pintype "power_in"))
      (node (ref "D70") (pin "4") (pinfunction "VDD_4") (pintype "power_in"))
      (node (ref "D71") (pin "4") (pinfunction "VDD_4") (pintype "power_in"))
      (node (ref "D72") (pin "4") (pinfunction "VDD_4") (pintype "power_in"))
      (node (ref "D73") (pin "4") (pinfunction "VDD_4") (pintype "power_in"))
      (node (ref "D74") (pin "4") (pinfunction "VDD_4") (pintype "power_in"))
      (node (ref "D75") (pin "4") (pinfunction "VDD_4") (pintype "power_in"))
      (node (ref "D76") (pin "4") (pinfunction "VDD_4") (pintype "power_in"))
      (node (ref "D77") (pin "4") (pinfunction "VDD_4") (pintype "power_in"))
      (node (ref "D78") (pin "4") (pinfunction "VDD_4") (pintype "power_in"))
      (node (ref "D79") (pin "4") (pinfunction "VDD_4") (pintype "power_in"))
      (node (ref "D80") (pin "4") (pinfunction "VDD_4") (pintype "power_in"))
      (node (ref "D81") (pin "4") (pinfunction "VDD_4") (pintype "power_in"))
      (node (ref "D82") (pin "4") (pinfunction "VDD_4") (pintype "power_in"))
      (node (ref "D83") (pin "4") (pinfunction "VDD_4") (pintype "power_in"))
      (node (ref "D84") (pin "4") (pinfunction "VDD_4") (pintype "power_in"))
      (node (ref "D85") (pin "4") (pinfunction "VDD_4") (pintype "power_in"))
      (node (ref "D86") (pin "4") (pinfunction "VDD_4") (pintype "power_in"))
      (node (ref "D87") (pin "4") (pinfunction "VDD_4") (pintype "power_in"))
      (node (ref "D88") (pin "4") (pinfunction "VDD_4") (pintype "power_in"))
      (node (ref "D89") (pin "4") (pinfunction "VDD_4") (pintype "power_in"))
      (node (ref "D90") (pin "4") (pinfunction "VDD_4") (pintype "power_in"))
      (node (ref "D91") (pin "4") (pinfunction "VDD_4") (pintype "power_in"))
      (node (ref "D92") (pin "4") (pinfunction "VDD_4") (pintype "power_in"))
      (node (ref "D93") (pin "4") (pinfunction "VDD_4") (pintype "power_in"))
      (node (ref "D94") (pin "4") (pinfunction "VDD_4") (pintype "power_in"))
      (node (ref "D95") (pin "4") (pinfunction "VDD_4") (pintype "power_in"))
      (node (ref "D96") (pin "4") (pinfunction "VDD_4") (pintype "power_in"))
      (node (ref "D97") (pin "4") (pinfunction "VDD_4") (pintype "power_in"))
      (node (ref "D98") (pin "4") (pinfunction "VDD_4") (pintype "power_in"))
      (node (ref "D99") (pin "4") (pinfunction "VDD_4") (pintype "power_in"))
    )
    (net (code "2") (name "/BOTTOM1_RGB_OUT") (class "Default")
      (node (ref "D365") (pin "3") (pinfunction "DI_3") (pintype "input"))
      (node (ref "D385") (pin "1") (pinfunction "DO_1") (pintype "output"))
    )
    (net (code "3") (name "/BOTTOM2_RGB_OUT") (class "Default")
      (node (ref "D370") (pin "3") (pinfunction "DI_3") (pintype "input"))
      (node (ref "D390") (pin "1") (pinfunction "DO_1") (pintype "output"))
    )
    (net (code "4") (name "/BOTTOM3_RGB_OUT") (class "Default")
      (node (ref "D375") (pin "3") (pinfunction "DI_3") (pintype "input"))
      (node (ref "D395") (pin "1") (pinfunction "DO_1") (pintype "output"))
    )
    (net (code "5") (name "/BOTTOM4_RGB_OUT") (class "Default")
      (node (ref "D380") (pin "3") (pinfunction "DI_3") (pintype "input"))
      (node (ref "D400") (pin "1") (pinfunction "DO_1") (pintype "output"))
    )
    (net (code "6") (name "/RGB30_OUT") (class "Default")
      (node (ref "D209") (pin "1") (pinfunction "DO_1") (pintype "output"))
      (node (ref "D210") (pin "3") (pinfunction "DI_3") (pintype "input"))
    )
    (net (code "7") (name "/RGB_LED_DRIVE_IN") (class "Default")
      (node (ref "D10") (pin "3") (pinfunction "DI_3") (pintype "input"))
    )
    (net (code "8") (name "/TOP1_RGB_OUT") (class "Default")
      (node (ref "D15") (pin "3") (pinfunction "DI_3") (pintype "input"))
      (node (ref "D35") (pin "1") (pinfunction "DO_1") (pintype "output"))
    )
    (net (code "9") (name "/TOP2_RGB_OUT") (class "Default")
      (node (ref "D20") (pin "3") (pinfunction "DI_3") (pintype "input"))
      (node (ref "D40") (pin "1") (pinfunction "DO_1") (pintype "output"))
    )
    (net (code "10") (name "/TOP3_RGB_OUT") (class "Default")
      (node (ref "D25") (pin "3") (pinfunction "DI_3") (pintype "input"))
      (node (ref "D45") (pin "1") (pinfunction "DO_1") (pintype "output"))
    )
    (net (code "11") (name "/TOP4_RGB_OUT") (class "Default")
      (node (ref "D30") (pin "3") (pinfunction "DI_3") (pintype "input"))
      (node (ref "D50") (pin "1") (pinfunction "DO_1") (pintype "output"))
    )
    (net (code "12") (name "/TOP5_RGB_OUT") (class "Default")
      (node (ref "D55") (pin "1") (pinfunction "DO_1") (pintype "output"))
      (node (ref "D60") (pin "3") (pinfunction "DI_3") (pintype "input"))
    )
    (net (code "13") (name "GND") (class "Default")
      (node (ref "D10") (pin "2") (pinfunction "GND_2") (pintype "power_in"))
      (node (ref "D100") (pin "2") (pinfunction "GND_2") (pintype "power_in"))
      (node (ref "D101") (pin "2") (pinfunction "GND_2") (pintype "power_in"))
      (node (ref "D102") (pin "2") (pinfunction "GND_2") (pintype "power_in"))
      (node (ref "D103") (pin "2") (pinfunction "GND_2") (pintype "power_in"))
      (node (ref "D104") (pin "2") (pinfunction "GND_2") (pintype "power_in"))
      (node (ref "D105") (pin "2") (pinfunction "GND_2") (pintype "power_in"))
      (node (ref "D106") (pin "2") (pinfunction "GND_2") (pintype "power_in"))
      (node (ref "D107") (pin "2") (pinfunction "GND_2") (pintype "power_in"))
      (node (ref "D108") (pin "2") (pinfunction "GND_2") (pintype "power_in"))
      (node (ref "D109") (pin "2") (pinfunction "GND_2") (pintype "power_in"))
      (node (ref "D11") (pin "2") (pinfunction "GND_2") (pintype "power_in"))
      (node (ref "D110") (pin "2") (pinfunction "GND_2") (pintype "power_in"))
      (node (ref "D111") (pin "2") (pinfunction "GND_2") (pintype "power_in"))
      (node (ref "D112") (pin "2") (pinfunction "GND_2") (pintype "power_in"))
      (node (ref "D113") (pin "2") (pinfunction "GND_2") (pintype "power_in"))
      (node (ref "D114") (pin "2") (pinfunction "GND_2") (pintype "power_in"))
      (node (ref "D115") (pin "2") (pinfunction "GND_2") (pintype "power_in"))
      (node (ref "D116") (pin "2") (pinfunction "GND_2") (pintype "power_in"))
      (node (ref "D117") (pin "2") (pinfunction "GND_2") (pintype "power_in"))
      (node (ref "D118") (pin "2") (pinfunction "GND_2") (pintype "power_in"))
      (node (ref "D119") (pin "2") (pinfunction "GND_2") (pintype "power_in"))
      (node (ref "D12") (pin "2") (pinfunction "GND_2") (pintype "power_in"))
      (node (ref "D120") (pin "2") (pinfunction "GND_2") (pintype "power_in"))
      (node (ref "D121") (pin "2") (pinfunction "GND_2") (pintype "power_in"))
      (node (ref "D122") (pin "2") (pinfunction "GND_2") (pintype "power_in"))
      (node (ref "D123") (pin "2") (pinfunction "GND_2") (pintype "power_in"))
      (node (ref "D124") (pin "2") (pinfunction "GND_2") (pintype "power_in"))
      (node (ref "D125") (pin "2") (pinfunction "GND_2") (pintype "power_in"))
      (node (ref "D126") (pin "2") (pinfunction "GND_2") (pintype "power_in"))
      (node (ref "D127") (pin "2") (pinfunction "GND_2") (pintype "power_in"))
      (node (ref "D128") (pin "2") (pinfunction "GND_2") (pintype "power_in"))
      (node (ref "D129") (pin "2") (pinfunction "GND_2") (pintype "power_in"))
      (node (ref "D13") (pin "2") (pinfunction "GND_2") (pintype "power_in"))
      (node (ref "D130") (pin "2") (pinfunction "GND_2") (pintype "power_in"))
      (node (ref "D131") (pin "2") (pinfunction "GND_2") (pintype "power_in"))
      (node (ref "D132") (pin "2") (pinfunction "GND_2") (pintype "power_in"))
      (node (ref "D133") (pin "2") (pinfunction "GND_2") (pintype "power_in"))
      (node (ref "D134") (pin "2") (pinfunction "GND_2") (pintype "power_in"))
      (node (ref "D135") (pin "2") (pinfunction "GND_2") (pintype "power_in"))
      (node (ref "D136") (pin "2") (pinfunction "GND_2") (pintype "power_in"))
      (node (ref "D137") (pin "2") (pinfunction "GND_2") (pintype "power_in"))
      (node (ref "D138") (pin "2") (pinfunction "GND_2") (pintype "power_in"))
      (node (ref "D139") (pin "2") (pinfunction "GND_2") (pintype "power_in"))
      (node (ref "D14") (pin "2") (pinfunction "GND_2") (pintype "power_in"))
      (node (ref "D140") (pin "2") (pinfunction "GND_2") (pintype "power_in"))
      (node (ref "D141") (pin "2") (pinfunction "GND_2") (pintype "power_in"))
      (node (ref "D142") (pin "2") (pinfunction "GND_2") (pintype "power_in"))
      (node (ref "D143") (pin "2") (pinfunction "GND_2") (pintype "power_in"))
      (node (ref "D144") (pin "2") (pinfunction "GND_2") (pintype "power_in"))
      (node (ref "D145") (pin "2") (pinfunction "GND_2") (pintype "power_in"))
      (node (ref "D146") (pin "2") (pinfunction "GND_2") (pintype "power_in"))
      (node (ref "D147") (pin "2") (pinfunction "GND_2") (pintype "power_in"))
      (node (ref "D148") (pin "2") (pinfunction "GND_2") (pintype "power_in"))
      (node (ref "D149") (pin "2") (pinfunction "GND_2") (pintype "power_in"))
      (node (ref "D15") (pin "2") (pinfunction "GND_2") (pintype "power_in"))
      (node (ref "D150") (pin "2") (pinfunction "GND_2") (pintype "power_in"))
      (node (ref "D151") (pin "2") (pinfunction "GND_2") (pintype "power_in"))
      (node (ref "D152") (pin "2") (pinfunction "GND_2") (pintype "power_in"))
      (node (ref "D153") (pin "2") (pinfunction "GND_2") (pintype "power_in"))
      (node (ref "D154") (pin "2") (pinfunction "GND_2") (pintype "power_in"))
      (node (ref "D155") (pin "2") (pinfunction "GND_2") (pintype "power_in"))
      (node (ref "D156") (pin "2") (pinfunction "GND_2") (pintype "power_in"))
      (node (ref "D157") (pin "2") (pinfunction "GND_2") (pintype "power_in"))
      (node (ref "D158") (pin "2") (pinfunction "GND_2") (pintype "power_in"))
      (node (ref "D159") (pin "2") (pinfunction "GND_2") (pintype "power_in"))
      (node (ref "D16") (pin "2") (pinfunction "GND_2") (pintype "power_in"))
      (node (ref "D160") (pin "2") (pinfunction "GND_2") (pintype "power_in"))
      (node (ref "D161") (pin "2") (pinfunction "GND_2") (pintype "power_in"))
      (node (ref "D162") (pin "2") (pinfunction "GND_2") (pintype "power_in"))
      (node (ref "D163") (pin "2") (pinfunction "GND_2") (pintype "power_in"))
      (node (ref "D164") (pin "2") (pinfunction "GND_2") (pintype "power_in"))
      (node (ref "D165") (pin "2") (pinfunction "GND_2") (pintype "power_in"))
      (node (ref "D166") (pin "2") (pinfunction "GND_2") (pintype "power_in"))
      (node (ref "D167") (pin "2") (pinfunction "GND_2") (pintype "power_in"))
      (node (ref "D168") (pin "2") (pinfunction "GND_2") (pintype "power_in"))
      (node (ref "D169") (pin "2") (pinfunction "GND_2") (pintype "power_in"))
      (node (ref "D17") (pin "2") (pinfunction "GND_2") (pintype "power_in"))
      (node (ref "D170") (pin "2") (pinfunction "GND_2") (pintype "power_in"))
      (node (ref "D171") (pin "2") (pinfunction "GND_2") (pintype "power_in"))
      (node (ref "D172") (pin "2") (pinfunction "GND_2") (pintype "power_in"))
      (node (ref "D173") (pin "2") (pinfunction "GND_2") (pintype "power_in"))
      (node (ref "D174") (pin "2") (pinfunction "GND_2") (pintype "power_in"))
      (node (ref "D175") (pin "2") (pinfunction "GND_2") (pintype "power_in"))
      (node (ref "D176") (pin "2") (pinfunction "GND_2") (pintype "power_in"))
      (node (ref "D177") (pin "2") (pinfunction "GND_2") (pintype "power_in"))
      (node (ref "D178") (pin "2") (pinfunction "GND_2") (pintype "power_in"))
      (node (ref "D179") (pin "2") (pinfunction "GND_2") (pintype "power_in"))
      (node (ref "D18") (pin "2") (pinfunction "GND_2") (pintype "power_in"))
      (node (ref "D180") (pin "2") (pinfunction "GND_2") (pintype "power_in"))
      (node (ref "D181") (pin "2") (pinfunction "GND_2") (pintype "power_in"))
      (node (ref "D182") (pin "2") (pinfunction "GND_2") (pintype "power_in"))
      (node (ref "D183") (pin "2") (pinfunction "GND_2") (pintype "power_in"))
      (node (ref "D184") (pin "2") (pinfunction "GND_2") (pintype "power_in"))
      (node (ref "D185") (pin "2") (pinfunction "GND_2") (pintype "power_in"))
      (node (ref "D186") (pin "2") (pinfunction "GND_2") (pintype "power_in"))
      (node (ref "D187") (pin "2") (pinfunction "GND_2") (pintype "power_in"))
      (node (ref "D188") (pin "2") (pinfunction "GND_2") (pintype "power_in"))
      (node (ref "D189") (pin "2") (pinfunction "GND_2") (pintype "power_in"))
      (node (ref "D19") (pin "2") (pinfunction "GND_2") (pintype "power_in"))
      (node (ref "D190") (pin "2") (pinfunction "GND_2") (pintype "power_in"))
      (node (ref "D191") (pin "2") (pinfunction "GND_2") (pintype "power_in"))
      (node (ref "D192") (pin "2") (pinfunction "GND_2") (pintype "power_in"))
      (node (ref "D193") (pin "2") (pinfunction "GND_2") (pintype "power_in"))
      (node (ref "D194") (pin "2") (pinfunction "GND_2") (pintype "power_in"))
      (node (ref "D195") (pin "2") (pinfunction "GND_2") (pintype "power_in"))
      (node (ref "D196") (pin "2") (pinfunction "GND_2") (pintype "power_in"))
      (node (ref "D197") (pin "2") (pinfunction "GND_2") (pintype "power_in"))
      (node (ref "D198") (pin "2") (pinfunction "GND_2") (pintype "power_in"))
      (node (ref "D199") (pin "2") (pinfunction "GND_2") (pintype "power_in"))
      (node (ref "D20") (pin "2") (pinfunction "GND_2") (pintype "power_in"))
      (node (ref "D200") (pin "2") (pinfunction "GND_2") (pintype "power_in"))
      (node (ref "D201") (pin "2") (pinfunction "GND_2") (pintype "power_in"))
      (node (ref "D202") (pin "2") (pinfunction "GND_2") (pintype "power_in"))
      (node (ref "D203") (pin "2") (pinfunction "GND_2") (pintype "power_in"))
      (node (ref "D204") (pin "2") (pinfunction "GND_2") (pintype "power_in"))
      (node (ref "D205") (pin "2") (pinfunction "GND_2") (pintype "power_in"))
      (node (ref "D206") (pin "2") (pinfunction "GND_2") (pintype "power_in"))
      (node (ref "D207") (pin "2") (pinfunction "GND_2") (pintype "power_in"))
      (node (ref "D208") (pin "2") (pinfunction "GND_2") (pintype "power_in"))
      (node (ref "D209") (pin "2") (pinfunction "GND_2") (pintype "power_in"))
      (node (ref "D21") (pin "2") (pinfunction "GND_2") (pintype "power_in"))
      (node (ref "D210") (pin "2") (pinfunction "GND_2") (pintype "power_in"))
      (node (ref "D211") (pin "2") (pinfunction "GND_2") (pintype "power_in"))
      (node (ref "D212") (pin "2") (pinfunction "GND_2") (pintype "power_in"))
      (node (ref "D213") (pin "2") (pinfunction "GND_2") (pintype "power_in"))
      (node (ref "D214") (pin "2") (pinfunction "GND_2") (pintype "power_in"))
      (node (ref "D215") (pin "2") (pinfunction "GND_2") (pintype "power_in"))
      (node (ref "D216") (pin "2") (pinfunction "GND_2") (pintype "power_in"))
      (node (ref "D217") (pin "2") (pinfunction "GND_2") (pintype "power_in"))
      (node (ref "D218") (pin "2") (pinfunction "GND_2") (pintype "power_in"))
      (node (ref "D219") (pin "2") (pinfunction "GND_2") (pintype "power_in"))
      (node (ref "D22") (pin "2") (pinfunction "GND_2") (pintype "power_in"))
      (node (ref "D220") (pin "2") (pinfunction "GND_2") (pintype "power_in"))
      (node (ref "D221") (pin "2") (pinfunction "GND_2") (pintype "power_in"))
      (node (ref "D222") (pin "2") (pinfunction "GND_2") (pintype "power_in"))
      (node (ref "D223") (pin "2") (pinfunction "GND_2") (pintype "power_in"))
      (node (ref "D224") (pin "2") (pinfunction "GND_2") (pintype "power_in"))
      (node (ref "D225") (pin "2") (pinfunction "GND_2") (pintype "power_in"))
      (node (ref "D226") (pin "2") (pinfunction "GND_2") (pintype "power_in"))
      (node (ref "D227") (pin "2") (pinfunction "GND_2") (pintype "power_in"))
      (node (ref "D228") (pin "2") (pinfunction "GND_2") (pintype "power_in"))
      (node (ref "D229") (pin "2") (pinfunction "GND_2") (pintype "power_in"))
      (node (ref "D23") (pin "2") (pinfunction "GND_2") (pintype "power_in"))
      (node (ref "D230") (pin "2") (pinfunction "GND_2") (pintype "power_in"))
      (node (ref "D231") (pin "2") (pinfunction "GND_2") (pintype "power_in"))
      (node (ref "D232") (pin "2") (pinfunction "GND_2") (pintype "power_in"))
      (node (ref "D233") (pin "2") (pinfunction "GND_2") (pintype "power_in"))
      (node (ref "D234") (pin "2") (pinfunction "GND_2") (pintype "power_in"))
      (node (ref "D235") (pin "2") (pinfunction "GND_2") (pintype "power_in"))
      (node (ref "D236") (pin "2") (pinfunction "GND_2") (pintype "power_in"))
      (node (ref "D237") (pin "2") (pinfunction "GND_2") (pintype "power_in"))
      (node (ref "D238") (pin "2") (pinfunction "GND_2") (pintype "power_in"))
      (node (ref "D239") (pin "2") (pinfunction "GND_2") (pintype "power_in"))
      (node (ref "D24") (pin "2") (pinfunction "GND_2") (pintype "power_in"))
      (node (ref "D240") (pin "2") (pinfunction "GND_2") (pintype "power_in"))
      (node (ref "D241") (pin "2") (pinfunction "GND_2") (pintype "power_in"))
      (node (ref "D242") (pin "2") (pinfunction "GND_2") (pintype "power_in"))
      (node (ref "D243") (pin "2") (pinfunction "GND_2") (pintype "power_in"))
      (node (ref "D244") (pin "2") (pinfunction "GND_2") (pintype "power_in"))
      (node (ref "D245") (pin "2") (pinfunction "GND_2") (pintype "power_in"))
      (node (ref "D246") (pin "2") (pinfunction "GND_2") (pintype "power_in"))
      (node (ref "D247") (pin "2") (pinfunction "GND_2") (pintype "power_in"))
      (node (ref "D248") (pin "2") (pinfunction "GND_2") (pintype "power_in"))
      (node (ref "D249") (pin "2") (pinfunction "GND_2") (pintype "power_in"))
      (node (ref "D25") (pin "2") (pinfunction "GND_2") (pintype "power_in"))
      (node (ref "D250") (pin "2") (pinfunction "GND_2") (pintype "power_in"))
      (node (ref "D251") (pin "2") (pinfunction "GND_2") (pintype "power_in"))
      (node (ref "D252") (pin "2") (pinfunction "GND_2") (pintype "power_in"))
      (node (ref "D253") (pin "2") (pinfunction "GND_2") (pintype "power_in"))
      (node (ref "D254") (pin "2") (pinfunction "GND_2") (pintype "power_in"))
      (node (ref "D255") (pin "2") (pinfunction "GND_2") (pintype "power_in"))
      (node (ref "D256") (pin "2") (pinfunction "GND_2") (pintype "power_in"))
      (node (ref "D257") (pin "2") (pinfunction "GND_2") (pintype "power_in"))
      (node (ref "D258") (pin "2") (pinfunction "GND_2") (pintype "power_in"))
      (node (ref "D259") (pin "2") (pinfunction "GND_2") (pintype "power_in"))
      (node (ref "D26") (pin "2") (pinfunction "GND_2") (pintype "power_in"))
      (node (ref "D260") (pin "2") (pinfunction "GND_2") (pintype "power_in"))
      (node (ref "D261") (pin "2") (pinfunction "GND_2") (pintype "power_in"))
      (node (ref "D262") (pin "2") (pinfunction "GND_2") (pintype "power_in"))
      (node (ref "D263") (pin "2") (pinfunction "GND_2") (pintype "power_in"))
      (node (ref "D264") (pin "2") (pinfunction "GND_2") (pintype "power_in"))
      (node (ref "D265") (pin "2") (pinfunction "GND_2") (pintype "power_in"))
      (node (ref "D266") (pin "2") (pinfunction "GND_2") (pintype "power_in"))
      (node (ref "D267") (pin "2") (pinfunction "GND_2") (pintype "power_in"))
      (node (ref "D268") (pin "2") (pinfunction "GND_2") (pintype "power_in"))
      (node (ref "D269") (pin "2") (pinfunction "GND_2") (pintype "power_in"))
      (node (ref "D27") (pin "2") (pinfunction "GND_2") (pintype "power_in"))
      (node (ref "D270") (pin "2") (pinfunction "GND_2") (pintype "power_in"))
      (node (ref "D271") (pin "2") (pinfunction "GND_2") (pintype "power_in"))
      (node (ref "D272") (pin "2") (pinfunction "GND_2") (pintype "power_in"))
      (node (ref "D273") (pin "2") (pinfunction "GND_2") (pintype "power_in"))
      (node (ref "D274") (pin "2") (pinfunction "GND_2") (pintype "power_in"))
      (node (ref "D275") (pin "2") (pinfunction "GND_2") (pintype "power_in"))
      (node (ref "D276") (pin "2") (pinfunction "GND_2") (pintype "power_in"))
      (node (ref "D277") (pin "2") (pinfunction "GND_2") (pintype "power_in"))
      (node (ref "D278") (pin "2") (pinfunction "GND_2") (pintype "power_in"))
      (node (ref "D279") (pin "2") (pinfunction "GND_2") (pintype "power_in"))
      (node (ref "D28") (pin "2") (pinfunction "GND_2") (pintype "power_in"))
      (node (ref "D280") (pin "2") (pinfunction "GND_2") (pintype "power_in"))
      (node (ref "D281") (pin "2") (pinfunction "GND_2") (pintype "power_in"))
      (node (ref "D282") (pin "2") (pinfunction "GND_2") (pintype "power_in"))
      (node (ref "D283") (pin "2") (pinfunction "GND_2") (pintype "power_in"))
      (node (ref "D284") (pin "2") (pinfunction "GND_2") (pintype "power_in"))
      (node (ref "D285") (pin "2") (pinfunction "GND_2") (pintype "power_in"))
      (node (ref "D286") (pin "2") (pinfunction "GND_2") (pintype "power_in"))
      (node (ref "D287") (pin "2") (pinfunction "GND_2") (pintype "power_in"))
      (node (ref "D288") (pin "2") (pinfunction "GND_2") (pintype "power_in"))
      (node (ref "D289") (pin "2") (pinfunction "GND_2") (pintype "power_in"))
      (node (ref "D29") (pin "2") (pinfunction "GND_2") (pintype "power_in"))
      (node (ref "D290") (pin "2") (pinfunction "GND_2") (pintype "power_in"))
      (node (ref "D291") (pin "2") (pinfunction "GND_2") (pintype "power_in"))
      (node (ref "D292") (pin "2") (pinfunction "GND_2") (pintype "power_in"))
      (node (ref "D293") (pin "2") (pinfunction "GND_2") (pintype "power_in"))
      (node (ref "D294") (pin "2") (pinfunction "GND_2") (pintype "power_in"))
      (node (ref "D295") (pin "2") (pinfunction "GND_2") (pintype "power_in"))
      (node (ref "D296") (pin "2") (pinfunction "GND_2") (pintype "power_in"))
      (node (ref "D297") (pin "2") (pinfunction "GND_2") (pintype "power_in"))
      (node (ref "D298") (pin "2") (pinfunction "GND_2") (pintype "power_in"))
      (node (ref "D299") (pin "2") (pinfunction "GND_2") (pintype "power_in"))
      (node (ref "D30") (pin "2") (pinfunction "GND_2") (pintype "power_in"))
      (node (ref "D300") (pin "2") (pinfunction "GND_2") (pintype "power_in"))
      (node (ref "D301") (pin "2") (pinfunction "GND_2") (pintype "power_in"))
      (node (ref "D302") (pin "2") (pinfunction "GND_2") (pintype "power_in"))
      (node (ref "D303") (pin "2") (pinfunction "GND_2") (pintype "power_in"))
      (node (ref "D304") (pin "2") (pinfunction "GND_2") (pintype "power_in"))
      (node (ref "D305") (pin "2") (pinfunction "GND_2") (pintype "power_in"))
      (node (ref "D306") (pin "2") (pinfunction "GND_2") (pintype "power_in"))
      (node (ref "D307") (pin "2") (pinfunction "GND_2") (pintype "power_in"))
      (node (ref "D308") (pin "2") (pinfunction "GND_2") (pintype "power_in"))
      (node (ref "D309") (pin "2") (pinfunction "GND_2") (pintype "power_in"))
      (node (ref "D31") (pin "2") (pinfunction "GND_2") (pintype "power_in"))
      (node (ref "D310") (pin "2") (pinfunction "GND_2") (pintype "power_in"))
      (node (ref "D311") (pin "2") (pinfunction "GND_2") (pintype "power_in"))
      (node (ref "D312") (pin "2") (pinfunction "GND_2") (pintype "power_in"))
      (node (ref "D313") (pin "2") (pinfunction "GND_2") (pintype "power_in"))
      (node (ref "D314") (pin "2") (pinfunction "GND_2") (pintype "power_in"))
      (node (ref "D315") (pin "2") (pinfunction "GND_2") (pintype "power_in"))
      (node (ref "D316") (pin "2") (pinfunction "GND_2") (pintype "power_in"))
      (node (ref "D317") (pin "2") (pinfunction "GND_2") (pintype "power_in"))
      (node (ref "D318") (pin "2") (pinfunction "GND_2") (pintype "power_in"))
      (node (ref "D319") (pin "2") (pinfunction "GND_2") (pintype "power_in"))
      (node (ref "D32") (pin "2") (pinfunction "GND_2") (pintype "power_in"))
      (node (ref "D320") (pin "2") (pinfunction "GND_2") (pintype "power_in"))
      (node (ref "D321") (pin "2") (pinfunction "GND_2") (pintype "power_in"))
      (node (ref "D322") (pin "2") (pinfunction "GND_2") (pintype "power_in"))
      (node (ref "D323") (pin "2") (pinfunction "GND_2") (pintype "power_in"))
      (node (ref "D324") (pin "2") (pinfunction "GND_2") (pintype "power_in"))
      (node (ref "D325") (pin "2") (pinfunction "GND_2") (pintype "power_in"))
      (node (ref "D326") (pin "2") (pinfunction "GND_2") (pintype "power_in"))
      (node (ref "D327") (pin "2") (pinfunction "GND_2") (pintype "power_in"))
      (node (ref "D328") (pin "2") (pinfunction "GND_2") (pintype "power_in"))
      (node (ref "D329") (pin "2") (pinfunction "GND_2") (pintype "power_in"))
      (node (ref "D33") (pin "2") (pinfunction "GND_2") (pintype "power_in"))
      (node (ref "D330") (pin "2") (pinfunction "GND_2") (pintype "power_in"))
      (node (ref "D331") (pin "2") (pinfunction "GND_2") (pintype "power_in"))
      (node (ref "D332") (pin "2") (pinfunction "GND_2") (pintype "power_in"))
      (node (ref "D333") (pin "2") (pinfunction "GND_2") (pintype "power_in"))
      (node (ref "D334") (pin "2") (pinfunction "GND_2") (pintype "power_in"))
      (node (ref "D335") (pin "2") (pinfunction "GND_2") (pintype "power_in"))
      (node (ref "D336") (pin "2") (pinfunction "GND_2") (pintype "power_in"))
      (node (ref "D337") (pin "2") (pinfunction "GND_2") (pintype "power_in"))
      (node (ref "D338") (pin "2") (pinfunction "GND_2") (pintype "power_in"))
      (node (ref "D339") (pin "2") (pinfunction "GND_2") (pintype "power_in"))
      (node (ref "D34") (pin "2") (pinfunction "GND_2") (pintype "power_in"))
      (node (ref "D340") (pin "2") (pinfunction "GND_2") (pintype "power_in"))
      (node (ref "D341") (pin "2") (pinfunction "GND_2") (pintype "power_in"))
      (node (ref "D342") (pin "2") (pinfunction "GND_2") (pintype "power_in"))
      (node (ref "D343") (pin "2") (pinfunction "GND_2") (pintype "power_in"))
      (node (ref "D344") (pin "2") (pinfunction "GND_2") (pintype "power_in"))
      (node (ref "D345") (pin "2") (pinfunction "GND_2") (pintype "power_in"))
      (node (ref "D346") (pin "2") (pinfunction "GND_2") (pintype "power_in"))
      (node (ref "D347") (pin "2") (pinfunction "GND_2") (pintype "power_in"))
      (node (ref "D348") (pin "2") (pinfunction "GND_2") (pintype "power_in"))
      (node (ref "D349") (pin "2") (pinfunction "GND_2") (pintype "power_in"))
      (node (ref "D35") (pin "2") (pinfunction "GND_2") (pintype "power_in"))
      (node (ref "D350") (pin "2") (pinfunction "GND_2") (pintype "power_in"))
      (node (ref "D351") (pin "2") (pinfunction "GND_2") (pintype "power_in"))
      (node (ref "D352") (pin "2") (pinfunction "GND_2") (pintype "power_in"))
      (node (ref "D353") (pin "2") (pinfunction "GND_2") (pintype "power_in"))
      (node (ref "D354") (pin "2") (pinfunction "GND_2") (pintype "power_in"))
      (node (ref "D355") (pin "2") (pinfunction "GND_2") (pintype "power_in"))
      (node (ref "D356") (pin "2") (pinfunction "GND_2") (pintype "power_in"))
      (node (ref "D357") (pin "2") (pinfunction "GND_2") (pintype "power_in"))
      (node (ref "D358") (pin "2") (pinfunction "GND_2") (pintype "power_in"))
      (node (ref "D359") (pin "2") (pinfunction "GND_2") (pintype "power_in"))
      (node (ref "D36") (pin "2") (pinfunction "GND_2") (pintype "power_in"))
      (node (ref "D360") (pin "2") (pinfunction "GND_2") (pintype "power_in"))
      (node (ref "D361") (pin "2") (pinfunction "GND_2") (pintype "power_in"))
      (node (ref "D362") (pin "2") (pinfunction "GND_2") (pintype "power_in"))
      (node (ref "D363") (pin "2") (pinfunction "GND_2") (pintype "power_in"))
      (node (ref "D364") (pin "2") (pinfunction "GND_2") (pintype "power_in"))
      (node (ref "D365") (pin "2") (pinfunction "GND_2") (pintype "power_in"))
      (node (ref "D366") (pin "2") (pinfunction "GND_2") (pintype "power_in"))
      (node (ref "D367") (pin "2") (pinfunction "GND_2") (pintype "power_in"))
      (node (ref "D368") (pin "2") (pinfunction "GND_2") (pintype "power_in"))
      (node (ref "D369") (pin "2") (pinfunction "GND_2") (pintype "power_in"))
      (node (ref "D37") (pin "2") (pinfunction "GND_2") (pintype "power_in"))
      (node (ref "D370") (pin "2") (pinfunction "GND_2") (pintype "power_in"))
      (node (ref "D371") (pin "2") (pinfunction "GND_2") (pintype "power_in"))
      (node (ref "D372") (pin "2") (pinfunction "GND_2") (pintype "power_in"))
      (node (ref "D373") (pin "2") (pinfunction "GND_2") (pintype "power_in"))
      (node (ref "D374") (pin "2") (pinfunction "GND_2") (pintype "power_in"))
      (node (ref "D375") (pin "2") (pinfunction "GND_2") (pintype "power_in"))
      (node (ref "D376") (pin "2") (pinfunction "GND_2") (pintype "power_in"))
      (node (ref "D377") (pin "2") (pinfunction "GND_2") (pintype "power_in"))
      (node (ref "D378") (pin "2") (pinfunction "GND_2") (pintype "power_in"))
      (node (ref "D379") (pin "2") (pinfunction "GND_2") (pintype "power_in"))
      (node (ref "D38") (pin "2") (pinfunction "GND_2") (pintype "power_in"))
      (node (ref "D380") (pin "2") (pinfunction "GND_2") (pintype "power_in"))
      (node (ref "D381") (pin "2") (pinfunction "GND_2") (pintype "power_in"))
      (node (ref "D382") (pin "2") (pinfunction "GND_2") (pintype "power_in"))
      (node (ref "D383") (pin "2") (pinfunction "GND_2") (pintype "power_in"))
      (node (ref "D384") (pin "2") (pinfunction "GND_2") (pintype "power_in"))
      (node (ref "D385") (pin "2") (pinfunction "GND_2") (pintype "power_in"))
      (node (ref "D386") (pin "2") (pinfunction "GND_2") (pintype "power_in"))
      (node (ref "D387") (pin "2") (pinfunction "GND_2") (pintype "power_in"))
      (node (ref "D388") (pin "2") (pinfunction "GND_2") (pintype "power_in"))
      (node (ref "D389") (pin "2") (pinfunction "GND_2") (pintype "power_in"))
      (node (ref "D39") (pin "2") (pinfunction "GND_2") (pintype "power_in"))
      (node (ref "D390") (pin "2") (pinfunction "GND_2") (pintype "power_in"))
      (node (ref "D391") (pin "2") (pinfunction "GND_2") (pintype "power_in"))
      (node (ref "D392") (pin "2") (pinfunction "GND_2") (pintype "power_in"))
      (node (ref "D393") (pin "2") (pinfunction "GND_2") (pintype "power_in"))
      (node (ref "D394") (pin "2") (pinfunction "GND_2") (pintype "power_in"))
      (node (ref "D395") (pin "2") (pinfunction "GND_2") (pintype "power_in"))
      (node (ref "D396") (pin "2") (pinfunction "GND_2") (pintype "power_in"))
      (node (ref "D397") (pin "2") (pinfunction "GND_2") (pintype "power_in"))
      (node (ref "D398") (pin "2") (pinfunction "GND_2") (pintype "power_in"))
      (node (ref "D399") (pin "2") (pinfunction "GND_2") (pintype "power_in"))
      (node (ref "D40") (pin "2") (pinfunction "GND_2") (pintype "power_in"))
      (node (ref "D400") (pin "2") (pinfunction "GND_2") (pintype "power_in"))
      (node (ref "D401") (pin "2") (pinfunction "GND_2") (pintype "power_in"))
      (node (ref "D402") (pin "2") (pinfunction "GND_2") (pintype "power_in"))
      (node (ref "D403") (pin "2") (pinfunction "GND_2") (pintype "power_in"))
      (node (ref "D404") (pin "2") (pinfunction "GND_2") (pintype "power_in"))
      (node (ref "D405") (pin "2") (pinfunction "GND_2") (pintype "power_in"))
      (node (ref "D406") (pin "2") (pinfunction "GND_2") (pintype "power_in"))
      (node (ref "D407") (pin "2") (pinfunction "GND_2") (pintype "power_in"))
      (node (ref "D408") (pin "2") (pinfunction "GND_2") (pintype "power_in"))
      (node (ref "D409") (pin "2") (pinfunction "GND_2") (pintype "power_in"))
      (node (ref "D41") (pin "2") (pinfunction "GND_2") (pintype "power_in"))
      (node (ref "D42") (pin "2") (pinfunction "GND_2") (pintype "power_in"))
      (node (ref "D43") (pin "2") (pinfunction "GND_2") (pintype "power_in"))
      (node (ref "D44") (pin "2") (pinfunction "GND_2") (pintype "power_in"))
      (node (ref "D45") (pin "2") (pinfunction "GND_2") (pintype "power_in"))
      (node (ref "D46") (pin "2") (pinfunction "GND_2") (pintype "power_in"))
      (node (ref "D47") (pin "2") (pinfunction "GND_2") (pintype "power_in"))
      (node (ref "D48") (pin "2") (pinfunction "GND_2") (pintype "power_in"))
      (node (ref "D49") (pin "2") (pinfunction "GND_2") (pintype "power_in"))
      (node (ref "D50") (pin "2") (pinfunction "GND_2") (pintype "power_in"))
      (node (ref "D51") (pin "2") (pinfunction "GND_2") (pintype "power_in"))
      (node (ref "D52") (pin "2") (pinfunction "GND_2") (pintype "power_in"))
      (node (ref "D53") (pin "2") (pinfunction "GND_2") (pintype "power_in"))
      (node (ref "D54") (pin "2") (pinfunction "GND_2") (pintype "power_in"))
      (node (ref "D55") (pin "2") (pinfunction "GND_2") (pintype "power_in"))
      (node (ref "D56") (pin "2") (pinfunction "GND_2") (pintype "power_in"))
      (node (ref "D57") (pin "2") (pinfunction "GND_2") (pintype "power_in"))
      (node (ref "D58") (pin "2") (pinfunction "GND_2") (pintype "power_in"))
      (node (ref "D59") (pin "2") (pinfunction "GND_2") (pintype "power_in"))
      (node (ref "D60") (pin "2") (pinfunction "GND_2") (pintype "power_in"))
      (node (ref "D61") (pin "2") (pinfunction "GND_2") (pintype "power_in"))
      (node (ref "D62") (pin "2") (pinfunction "GND_2") (pintype "power_in"))
      (node (ref "D63") (pin "2") (pinfunction "GND_2") (pintype "power_in"))
      (node (ref "D64") (pin "2") (pinfunction "GND_2") (pintype "power_in"))
      (node (ref "D65") (pin "2") (pinfunction "GND_2") (pintype "power_in"))
      (node (ref "D66") (pin "2") (pinfunction "GND_2") (pintype "power_in"))
      (node (ref "D67") (pin "2") (pinfunction "GND_2") (pintype "power_in"))
      (node (ref "D68") (pin "2") (pinfunction "GND_2") (pintype "power_in"))
      (node (ref "D69") (pin "2") (pinfunction "GND_2") (pintype "power_in"))
      (node (ref "D70") (pin "2") (pinfunction "GND_2") (pintype "power_in"))
      (node (ref "D71") (pin "2") (pinfunction "GND_2") (pintype "power_in"))
      (node (ref "D72") (pin "2") (pinfunction "GND_2") (pintype "power_in"))
      (node (ref "D73") (pin "2") (pinfunction "GND_2") (pintype "power_in"))
      (node (ref "D74") (pin "2") (pinfunction "GND_2") (pintype "power_in"))
      (node (ref "D75") (pin "2") (pinfunction "GND_2") (pintype "power_in"))
      (node (ref "D76") (pin "2") (pinfunction "GND_2") (pintype "power_in"))
      (node (ref "D77") (pin "2") (pinfunction "GND_2") (pintype "power_in"))
      (node (ref "D78") (pin "2") (pinfunction "GND_2") (pintype "power_in"))
      (node (ref "D79") (pin "2") (pinfunction "GND_2") (pintype "power_in"))
      (node (ref "D80") (pin "2") (pinfunction "GND_2") (pintype "power_in"))
      (node (ref "D81") (pin "2") (pinfunction "GND_2") (pintype "power_in"))
      (node (ref "D82") (pin "2") (pinfunction "GND_2") (pintype "power_in"))
      (node (ref "D83") (pin "2") (pinfunction "GND_2") (pintype "power_in"))
      (node (ref "D84") (pin "2") (pinfunction "GND_2") (pintype "power_in"))
      (node (ref "D85") (pin "2") (pinfunction "GND_2") (pintype "power_in"))
      (node (ref "D86") (pin "2") (pinfunction "GND_2") (pintype "power_in"))
      (node (ref "D87") (pin "2") (pinfunction "GND_2") (pintype "power_in"))
      (node (ref "D88") (pin "2") (pinfunction "GND_2") (pintype "power_in"))
      (node (ref "D89") (pin "2") (pinfunction "GND_2") (pintype "power_in"))
      (node (ref "D90") (pin "2") (pinfunction "GND_2") (pintype "power_in"))
      (node (ref "D91") (pin "2") (pinfunction "GND_2") (pintype "power_in"))
      (node (ref "D92") (pin "2") (pinfunction "GND_2") (pintype "power_in"))
      (node (ref "D93") (pin "2") (pinfunction "GND_2") (pintype "power_in"))
      (node (ref "D94") (pin "2") (pinfunction "GND_2") (pintype "power_in"))
      (node (ref "D95") (pin "2") (pinfunction "GND_2") (pintype "power_in"))
      (node (ref "D96") (pin "2") (pinfunction "GND_2") (pintype "power_in"))
      (node (ref "D97") (pin "2") (pinfunction "GND_2") (pintype "power_in"))
      (node (ref "D98") (pin "2") (pinfunction "GND_2") (pintype "power_in"))
      (node (ref "D99") (pin "2") (pinfunction "GND_2") (pintype "power_in"))
    )
    (net (code "14") (name "Net-(D10-DO)") (class "Default")
      (node (ref "D10") (pin "1") (pinfunction "DO_1") (pintype "output"))
      (node (ref "D11") (pin "3") (pinfunction "DI_3") (pintype "input"))
    )
    (net (code "15") (name "Net-(D11-DO)") (class "Default")
      (node (ref "D11") (pin "1") (pinfunction "DO_1") (pintype "output"))
      (node (ref "D12") (pin "3") (pinfunction "DI_3") (pintype "input"))
    )
    (net (code "16") (name "Net-(D12-DO)") (class "Default")
      (node (ref "D12") (pin "1") (pinfunction "DO_1") (pintype "output"))
      (node (ref "D13") (pin "3") (pinfunction "DI_3") (pintype "input"))
    )
    (net (code "17") (name "Net-(D13-DO)") (class "Default")
      (node (ref "D13") (pin "1") (pinfunction "DO_1") (pintype "output"))
      (node (ref "D14") (pin "3") (pinfunction "DI_3") (pintype "input"))
    )
    (net (code "18") (name "Net-(D14-DO)") (class "Default")
      (node (ref "D14") (pin "1") (pinfunction "DO_1") (pintype "output"))
      (node (ref "D39") (pin "3") (pinfunction "DI_3") (pintype "input"))
    )
    (net (code "19") (name "Net-(D15-DO)") (class "Default")
      (node (ref "D15") (pin "1") (pinfunction "DO_1") (pintype "output"))
      (node (ref "D16") (pin "3") (pinfunction "DI_3") (pintype "input"))
    )
    (net (code "20") (name "Net-(D16-DO)") (class "Default")
      (node (ref "D16") (pin "1") (pinfunction "DO_1") (pintype "output"))
      (node (ref "D17") (pin "3") (pinfunction "DI_3") (pintype "input"))
    )
    (net (code "21") (name "Net-(D17-DO)") (class "Default")
      (node (ref "D17") (pin "1") (pinfunction "DO_1") (pintype "output"))
      (node (ref "D18") (pin "3") (pinfunction "DI_3") (pintype "input"))
    )
    (net (code "22") (name "Net-(D18-DO)") (class "Default")
      (node (ref "D18") (pin "1") (pinfunction "DO_1") (pintype "output"))
      (node (ref "D19") (pin "3") (pinfunction "DI_3") (pintype "input"))
    )
    (net (code "23") (name "Net-(D19-DO)") (class "Default")
      (node (ref "D19") (pin "1") (pinfunction "DO_1") (pintype "output"))
      (node (ref "D44") (pin "3") (pinfunction "DI_3") (pintype "input"))
    )
    (net (code "24") (name "Net-(D20-DO)") (class "Default")
      (node (ref "D20") (pin "1") (pinfunction "DO_1") (pintype "output"))
      (node (ref "D21") (pin "3") (pinfunction "DI_3") (pintype "input"))
    )
    (net (code "25") (name "Net-(D21-DO)") (class "Default")
      (node (ref "D21") (pin "1") (pinfunction "DO_1") (pintype "output"))
      (node (ref "D22") (pin "3") (pinfunction "DI_3") (pintype "input"))
    )
    (net (code "26") (name "Net-(D22-DO)") (class "Default")
      (node (ref "D22") (pin "1") (pinfunction "DO_1") (pintype "output"))
      (node (ref "D23") (pin "3") (pinfunction "DI_3") (pintype "input"))
    )
    (net (code "27") (name "Net-(D23-DO)") (class "Default")
      (node (ref "D23") (pin "1") (pinfunction "DO_1") (pintype "output"))
      (node (ref "D24") (pin "3") (pinfunction "DI_3") (pintype "input"))
    )
    (net (code "28") (name "Net-(D24-DO)") (class "Default")
      (node (ref "D24") (pin "1") (pinfunction "DO_1") (pintype "output"))
      (node (ref "D49") (pin "3") (pinfunction "DI_3") (pintype "input"))
    )
    (net (code "29") (name "Net-(D25-DO)") (class "Default")
      (node (ref "D25") (pin "1") (pinfunction "DO_1") (pintype "output"))
      (node (ref "D26") (pin "3") (pinfunction "DI_3") (pintype "input"))
    )
    (net (code "30") (name "Net-(D26-DO)") (class "Default")
      (node (ref "D26") (pin "1") (pinfunction "DO_1") (pintype "output"))
      (node (ref "D27") (pin "3") (pinfunction "DI_3") (pintype "input"))
    )
    (net (code "31") (name "Net-(D27-DO)") (class "Default")
      (node (ref "D27") (pin "1") (pinfunction "DO_1") (pintype "output"))
      (node (ref "D28") (pin "3") (pinfunction "DI_3") (pintype "input"))
    )
    (net (code "32") (name "Net-(D28-DO)") (class "Default")
      (node (ref "D28") (pin "1") (pinfunction "DO_1") (pintype "output"))
      (node (ref "D29") (pin "3") (pinfunction "DI_3") (pintype "input"))
    )
    (net (code "33") (name "Net-(D29-DO)") (class "Default")
      (node (ref "D29") (pin "1") (pinfunction "DO_1") (pintype "output"))
      (node (ref "D54") (pin "3") (pinfunction "DI_3") (pintype "input"))
    )
    (net (code "34") (name "Net-(D30-DO)") (class "Default")
      (node (ref "D30") (pin "1") (pinfunction "DO_1") (pintype "output"))
      (node (ref "D31") (pin "3") (pinfunction "DI_3") (pintype "input"))
    )
    (net (code "35") (name "Net-(D31-DO)") (class "Default")
      (node (ref "D31") (pin "1") (pinfunction "DO_1") (pintype "output"))
      (node (ref "D32") (pin "3") (pinfunction "DI_3") (pintype "input"))
    )
    (net (code "36") (name "Net-(D32-DO)") (class "Default")
      (node (ref "D32") (pin "1") (pinfunction "DO_1") (pintype "output"))
      (node (ref "D33") (pin "3") (pinfunction "DI_3") (pintype "input"))
    )
    (net (code "37") (name "Net-(D33-DO)") (class "Default")
      (node (ref "D33") (pin "1") (pinfunction "DO_1") (pintype "output"))
      (node (ref "D34") (pin "3") (pinfunction "DI_3") (pintype "input"))
    )
    (net (code "38") (name "Net-(D34-DO)") (class "Default")
      (node (ref "D34") (pin "1") (pinfunction "DO_1") (pintype "output"))
      (node (ref "D59") (pin "3") (pinfunction "DI_3") (pintype "input"))
    )
    (net (code "39") (name "Net-(D35-DI)") (class "Default")
      (node (ref "D35") (pin "3") (pinfunction "DI_3") (pintype "input"))
      (node (ref "D36") (pin "1") (pinfunction "DO_1") (pintype "output"))
    )
    (net (code "40") (name "Net-(D36-DI)") (class "Default")
      (node (ref "D36") (pin "3") (pinfunction "DI_3") (pintype "input"))
      (node (ref "D37") (pin "1") (pinfunction "DO_1") (pintype "output"))
    )
    (net (code "41") (name "Net-(D37-DI)") (class "Default")
      (node (ref "D37") (pin "3") (pinfunction "DI_3") (pintype "input"))
      (node (ref "D38") (pin "1") (pinfunction "DO_1") (pintype "output"))
    )
    (net (code "42") (name "Net-(D38-DI)") (class "Default")
      (node (ref "D38") (pin "3") (pinfunction "DI_3") (pintype "input"))
      (node (ref "D39") (pin "1") (pinfunction "DO_1") (pintype "output"))
    )
    (net (code "43") (name "Net-(D40-DI)") (class "Default")
      (node (ref "D40") (pin "3") (pinfunction "DI_3") (pintype "input"))
      (node (ref "D41") (pin "1") (pinfunction "DO_1") (pintype "output"))
    )
    (net (code "44") (name "Net-(D41-DI)") (class "Default")
      (node (ref "D41") (pin "3") (pinfunction "DI_3") (pintype "input"))
      (node (ref "D42") (pin "1") (pinfunction "DO_1") (pintype "output"))
    )
    (net (code "45") (name "Net-(D42-DI)") (class "Default")
      (node (ref "D42") (pin "3") (pinfunction "DI_3") (pintype "input"))
      (node (ref "D43") (pin "1") (pinfunction "DO_1") (pintype "output"))
    )
    (net (code "46") (name "Net-(D43-DI)") (class "Default")
      (node (ref "D43") (pin "3") (pinfunction "DI_3") (pintype "input"))
      (node (ref "D44") (pin "1") (pinfunction "DO_1") (pintype "output"))
    )
    (net (code "47") (name "Net-(D45-DI)") (class "Default")
      (node (ref "D45") (pin "3") (pinfunction "DI_3") (pintype "input"))
      (node (ref "D46") (pin "1") (pinfunction "DO_1") (pintype "output"))
    )
    (net (code "48") (name "Net-(D46-DI)") (class "Default")
      (node (ref "D46") (pin "3") (pinfunction "DI_3") (pintype "input"))
      (node (ref "D47") (pin "1") (pinfunction "DO_1") (pintype "output"))
    )
    (net (code "49") (name "Net-(D47-DI)") (class "Default")
      (node (ref "D47") (pin "3") (pinfunction "DI_3") (pintype "input"))
      (node (ref "D48") (pin "1") (pinfunction "DO_1") (pintype "output"))
    )
    (net (code "50") (name "Net-(D48-DI)") (class "Default")
      (node (ref "D48") (pin "3") (pinfunction "DI_3") (pintype "input"))
      (node (ref "D49") (pin "1") (pinfunction "DO_1") (pintype "output"))
    )
    (net (code "51") (name "Net-(D50-DI)") (class "Default")
      (node (ref "D50") (pin "3") (pinfunction "DI_3") (pintype "input"))
      (node (ref "D51") (pin "1") (pinfunction "DO_1") (pintype "output"))
    )
    (net (code "52") (name "Net-(D51-DI)") (class "Default")
      (node (ref "D51") (pin "3") (pinfunction "DI_3") (pintype "input"))
      (node (ref "D52") (pin "1") (pinfunction "DO_1") (pintype "output"))
    )
    (net (code "53") (name "Net-(D52-DI)") (class "Default")
      (node (ref "D52") (pin "3") (pinfunction "DI_3") (pintype "input"))
      (node (ref "D53") (pin "1") (pinfunction "DO_1") (pintype "output"))
    )
    (net (code "54") (name "Net-(D53-DI)") (class "Default")
      (node (ref "D53") (pin "3") (pinfunction "DI_3") (pintype "input"))
      (node (ref "D54") (pin "1") (pinfunction "DO_1") (pintype "output"))
    )
    (net (code "55") (name "Net-(D55-DI)") (class "Default")
      (node (ref "D55") (pin "3") (pinfunction "DI_3") (pintype "input"))
      (node (ref "D56") (pin "1") (pinfunction "DO_1") (pintype "output"))
    )
    (net (code "56") (name "Net-(D56-DI)") (class "Default")
      (node (ref "D56") (pin "3") (pinfunction "DI_3") (pintype "input"))
      (node (ref "D57") (pin "1") (pinfunction "DO_1") (pintype "output"))
    )
    (net (code "57") (name "Net-(D57-DI)") (class "Default")
      (node (ref "D57") (pin "3") (pinfunction "DI_3") (pintype "input"))
      (node (ref "D58") (pin "1") (pinfunction "DO_1") (pintype "output"))
    )
    (net (code "58") (name "Net-(D58-DI)") (class "Default")
      (node (ref "D58") (pin "3") (pinfunction "DI_3") (pintype "input"))
      (node (ref "D59") (pin "1") (pinfunction "DO_1") (pintype "output"))
    )
    (net (code "59") (name "Net-(D60-DO)") (class "Default")
      (node (ref "D60") (pin "1") (pinfunction "DO_1") (pintype "output"))
      (node (ref "D90") (pin "3") (pinfunction "DI_3") (pintype "input"))
    )
    (net (code "60") (name "Net-(D61-DO)") (class "Default")
      (node (ref "D61") (pin "1") (pinfunction "DO_1") (pintype "output"))
      (node (ref "D91") (pin "3") (pinfunction "DI_3") (pintype "input"))
    )
    (net (code "61") (name "Net-(D62-DO)") (class "Default")
      (node (ref "D62") (pin "1") (pinfunction "DO_1") (pintype "output"))
      (node (ref "D92") (pin "3") (pinfunction "DI_3") (pintype "input"))
    )
    (net (code "62") (name "Net-(D63-DO)") (class "Default")
      (node (ref "D63") (pin "1") (pinfunction "DO_1") (pintype "output"))
      (node (ref "D93") (pin "3") (pinfunction "DI_3") (pintype "input"))
    )
    (net (code "63") (name "Net-(D64-DO)") (class "Default")
      (node (ref "D64") (pin "1") (pinfunction "DO_1") (pintype "output"))
      (node (ref "D94") (pin "3") (pinfunction "DI_3") (pintype "input"))
    )
    (net (code "64") (name "Net-(D65-DO)") (class "Default")
      (node (ref "D65") (pin "1") (pinfunction "DO_1") (pintype "output"))
      (node (ref "D95") (pin "3") (pinfunction "DI_3") (pintype "input"))
    )
    (net (code "65") (name "Net-(D66-DO)") (class "Default")
      (node (ref "D66") (pin "1") (pinfunction "DO_1") (pintype "output"))
      (node (ref "D96") (pin "3") (pinfunction "DI_3") (pintype "input"))
    )
    (net (code "66") (name "Net-(D67-DO)") (class "Default")
      (node (ref "D67") (pin "1") (pinfunction "DO_1") (pintype "output"))
      (node (ref "D97") (pin "3") (pinfunction "DI_3") (pintype "input"))
    )
    (net (code "67") (name "Net-(D68-DO)") (class "Default")
      (node (ref "D68") (pin "1") (pinfunction "DO_1") (pintype "output"))
      (node (ref "D98") (pin "3") (pinfunction "DI_3") (pintype "input"))
    )
    (net (code "68") (name "Net-(D69-DO)") (class "Default")
      (node (ref "D69") (pin "1") (pinfunction "DO_1") (pintype "output"))
      (node (ref "D99") (pin "3") (pinfunction "DI_3") (pintype "input"))
    )
    (net (code "69") (name "Net-(D100-DI)") (class "Default")
      (node (ref "D100") (pin "3") (pinfunction "DI_3") (pintype "input"))
      (node (ref "D70") (pin "1") (pinfunction "DO_1") (pintype "output"))
    )
    (net (code "70") (name "Net-(D100-DO)") (class "Default")
      (node (ref "D100") (pin "1") (pinfunction "DO_1") (pintype "output"))
      (node (ref "D130") (pin "3") (pinfunction "DI_3") (pintype "input"))
    )
    (net (code "71") (name "Net-(D101-DI)") (class "Default")
      (node (ref "D101") (pin "3") (pinfunction "DI_3") (pintype "input"))
      (node (ref "D71") (pin "1") (pinfunction "DO_1") (pintype "output"))
    )
    (net (code "72") (name "Net-(D101-DO)") (class "Default")
      (node (ref "D101") (pin "1") (pinfunction "DO_1") (pintype "output"))
      (node (ref "D131") (pin "3") (pinfunction "DI_3") (pintype "input"))
    )
    (net (code "73") (name "Net-(D102-DI)") (class "Default")
      (node (ref "D102") (pin "3") (pinfunction "DI_3") (pintype "input"))
      (node (ref "D72") (pin "1") (pinfunction "DO_1") (pintype "output"))
    )
    (net (code "74") (name "Net-(D102-DO)") (class "Default")
      (node (ref "D102") (pin "1") (pinfunction "DO_1") (pintype "output"))
      (node (ref "D132") (pin "3") (pinfunction "DI_3") (pintype "input"))
    )
    (net (code "75") (name "Net-(D103-DI)") (class "Default")
      (node (ref "D103") (pin "3") (pinfunction "DI_3") (pintype "input"))
      (node (ref "D73") (pin "1") (pinfunction "DO_1") (pintype "output"))
    )
    (net (code "76") (name "Net-(D103-DO)") (class "Default")
      (node (ref "D103") (pin "1") (pinfunction "DO_1") (pintype "output"))
      (node (ref "D133") (pin "3") (pinfunction "DI_3") (pintype "input"))
    )
    (net (code "77") (name "Net-(D104-DI)") (class "Default")
      (node (ref "D104") (pin "3") (pinfunction "DI_3") (pintype "input"))
      (node (ref "D74") (pin "1") (pinfunction "DO_1") (pintype "output"))
    )
    (net (code "78") (name "Net-(D104-DO)") (class "Default")
      (node (ref "D104") (pin "1") (pinfunction "DO_1") (pintype "output"))
      (node (ref "D134") (pin "3") (pinfunction "DI_3") (pintype "input"))
    )
    (net (code "79") (name "Net-(D105-DI)") (class "Default")
      (node (ref "D105") (pin "3") (pinfunction "DI_3") (pintype "input"))
      (node (ref "D75") (pin "1") (pinfunction "DO_1") (pintype "output"))
    )
    (net (code "80") (name "Net-(D105-DO)") (class "Default")
      (node (ref "D105") (pin "1") (pinfunction "DO_1") (pintype "output"))
      (node (ref "D135") (pin "3") (pinfunction "DI_3") (pintype "input"))
    )
    (net (code "81") (name "Net-(D106-DI)") (class "Default")
      (node (ref "D106") (pin "3") (pinfunction "DI_3") (pintype "input"))
      (node (ref "D76") (pin "1") (pinfunction "DO_1") (pintype "output"))
    )
    (net (code "82") (name "Net-(D106-DO)") (class "Default")
      (node (ref "D106") (pin "1") (pinfunction "DO_1") (pintype "output"))
      (node (ref "D136") (pin "3") (pinfunction "DI_3") (pintype "input"))
    )
    (net (code "83") (name "Net-(D107-DI)") (class "Default")
      (node (ref "D107") (pin "3") (pinfunction "DI_3") (pintype "input"))
      (node (ref "D77") (pin "1") (pinfunction "DO_1") (pintype "output"))
    )
    (net (code "84") (name "Net-(D107-DO)") (class "Default")
      (node (ref "D107") (pin "1") (pinfunction "DO_1") (pintype "output"))
      (node (ref "D137") (pin "3") (pinfunction "DI_3") (pintype "input"))
    )
    (net (code "85") (name "Net-(D108-DI)") (class "Default")
      (node (ref "D108") (pin "3") (pinfunction "DI_3") (pintype "input"))
      (node (ref "D78") (pin "1") (pinfunction "DO_1") (pintype "output"))
    )
    (net (code "86") (name "Net-(D108-DO)") (class "Default")
      (node (ref "D108") (pin "1") (pinfunction "DO_1") (pintype "output"))
      (node (ref "D138") (pin "3") (pinfunction "DI_3") (pintype "input"))
    )
    (net (code "87") (name "Net-(D109-DI)") (class "Default")
      (node (ref "D109") (pin "3") (pinfunction "DI_3") (pintype "input"))
      (node (ref "D79") (pin "1") (pinfunction "DO_1") (pintype "output"))
    )
    (net (code "88") (name "Net-(D109-DO)") (class "Default")
      (node (ref "D109") (pin "1") (pinfunction "DO_1") (pintype "output"))
      (node (ref "D139") (pin "3") (pinfunction "DI_3") (pintype "input"))
    )
    (net (code "89") (name "Net-(D110-DI)") (class "Default")
      (node (ref "D110") (pin "3") (pinfunction "DI_3") (pintype "input"))
      (node (ref "D80") (pin "1") (pinfunction "DO_1") (pintype "output"))
    )
    (net (code "90") (name "Net-(D110-DO)") (class "Default")
      (node (ref "D110") (pin "1") (pinfunction "DO_1") (pintype "output"))
      (node (ref "D140") (pin "3") (pinfunction "DI_3") (pintype "input"))
    )
    (net (code "91") (name "Net-(D111-DI)") (class "Default")
      (node (ref "D111") (pin "3") (pinfunction "DI_3") (pintype "input"))
      (node (ref "D81") (pin "1") (pinfunction "DO_1") (pintype "output"))
    )
    (net (code "92") (name "Net-(D111-DO)") (class "Default")
      (node (ref "D111") (pin "1") (pinfunction "DO_1") (pintype "output"))
      (node (ref "D141") (pin "3") (pinfunction "DI_3") (pintype "input"))
    )
    (net (code "93") (name "Net-(D112-DI)") (class "Default")
      (node (ref "D112") (pin "3") (pinfunction "DI_3") (pintype "input"))
      (node (ref "D82") (pin "1") (pinfunction "DO_1") (pintype "output"))
    )
    (net (code "94") (name "Net-(D112-DO)") (class "Default")
      (node (ref "D112") (pin "1") (pinfunction "DO_1") (pintype "output"))
      (node (ref "D142") (pin "3") (pinfunction "DI_3") (pintype "input"))
    )
    (net (code "95") (name "Net-(D113-DI)") (class "Default")
      (node (ref "D113") (pin "3") (pinfunction "DI_3") (pintype "input"))
      (node (ref "D83") (pin "1") (pinfunction "DO_1") (pintype "output"))
    )
    (net (code "96") (name "Net-(D113-DO)") (class "Default")
      (node (ref "D113") (pin "1") (pinfunction "DO_1") (pintype "output"))
      (node (ref "D143") (pin "3") (pinfunction "DI_3") (pintype "input"))
    )
    (net (code "97") (name "Net-(D114-DI)") (class "Default")
      (node (ref "D114") (pin "3") (pinfunction "DI_3") (pintype "input"))
      (node (ref "D84") (pin "1") (pinfunction "DO_1") (pintype "output"))
    )
    (net (code "98") (name "Net-(D114-DO)") (class "Default")
      (node (ref "D114") (pin "1") (pinfunction "DO_1") (pintype "output"))
      (node (ref "D144") (pin "3") (pinfunction "DI_3") (pintype "input"))
    )
    (net (code "99") (name "Net-(D115-DI)") (class "Default")
      (node (ref "D115") (pin "3") (pinfunction "DI_3") (pintype "input"))
      (node (ref "D85") (pin "1") (pinfunction "DO_1") (pintype "output"))
    )
    (net (code "100") (name "Net-(D115-DO)") (class "Default")
      (node (ref "D115") (pin "1") (pinfunction "DO_1") (pintype "output"))
      (node (ref "D145") (pin "3") (pinfunction "DI_3") (pintype "input"))
    )
    (net (code "101") (name "Net-(D116-DI)") (class "Default")
      (node (ref "D116") (pin "3") (pinfunction "DI_3") (pintype "input"))
      (node (ref "D86") (pin "1") (pinfunction "DO_1") (pintype "output"))
    )
    (net (code "102") (name "Net-(D116-DO)") (class "Default")
      (node (ref "D116") (pin "1") (pinfunction "DO_1") (pintype "output"))
      (node (ref "D146") (pin "3") (pinfunction "DI_3") (pintype "input"))
    )
    (net (code "103") (name "Net-(D117-DI)") (class "Default")
      (node (ref "D117") (pin "3") (pinfunction "DI_3") (pintype "input"))
      (node (ref "D87") (pin "1") (pinfunction "DO_1") (pintype "output"))
    )
    (net (code "104") (name "Net-(D117-DO)") (class "Default")
      (node (ref "D117") (pin "1") (pinfunction "DO_1") (pintype "output"))
      (node (ref "D147") (pin "3") (pinfunction "DI_3") (pintype "input"))
    )
    (net (code "105") (name "Net-(D118-DI)") (class "Default")
      (node (ref "D118") (pin "3") (pinfunction "DI_3") (pintype "input"))
      (node (ref "D88") (pin "1") (pinfunction "DO_1") (pintype "output"))
    )
    (net (code "106") (name "Net-(D118-DO)") (class "Default")
      (node (ref "D118") (pin "1") (pinfunction "DO_1") (pintype "output"))
      (node (ref "D148") (pin "3") (pinfunction "DI_3") (pintype "input"))
    )
    (net (code "107") (name "Net-(D119-DI)") (class "Default")
      (node (ref "D119") (pin "3") (pinfunction "DI_3") (pintype "input"))
      (node (ref "D89") (pin "1") (pinfunction "DO_1") (pintype "output"))
    )
    (net (code "108") (name "Net-(D119-DO)") (class "Default")
      (node (ref "D119") (pin "1") (pinfunction "DO_1") (pintype "output"))
      (node (ref "D149") (pin "3") (pinfunction "DI_3") (pintype "input"))
    )
    (net (code "109") (name "Net-(D120-DI)") (class "Default")
      (node (ref "D120") (pin "3") (pinfunction "DI_3") (pintype "input"))
      (node (ref "D90") (pin "1") (pinfunction "DO_1") (pintype "output"))
    )
    (net (code "110") (name "Net-(D120-DO)") (class "Default")
      (node (ref "D120") (pin "1") (pinfunction "DO_1") (pintype "output"))
      (node (ref "D150") (pin "3") (pinfunction "DI_3") (pintype "input"))
    )
    (net (code "111") (name "Net-(D121-DI)") (class "Default")
      (node (ref "D121") (pin "3") (pinfunction "DI_3") (pintype "input"))
      (node (ref "D91") (pin "1") (pinfunction "DO_1") (pintype "output"))
    )
    (net (code "112") (name "Net-(D121-DO)") (class "Default")
      (node (ref "D121") (pin "1") (pinfunction "DO_1") (pintype "output"))
      (node (ref "D151") (pin "3") (pinfunction "DI_3") (pintype "input"))
    )
    (net (code "113") (name "Net-(D122-DI)") (class "Default")
      (node (ref "D122") (pin "3") (pinfunction "DI_3") (pintype "input"))
      (node (ref "D92") (pin "1") (pinfunction "DO_1") (pintype "output"))
    )
    (net (code "114") (name "Net-(D122-DO)") (class "Default")
      (node (ref "D122") (pin "1") (pinfunction "DO_1") (pintype "output"))
      (node (ref "D152") (pin "3") (pinfunction "DI_3") (pintype "input"))
    )
    (net (code "115") (name "Net-(D123-DI)") (class "Default")
      (node (ref "D123") (pin "3") (pinfunction "DI_3") (pintype "input"))
      (node (ref "D93") (pin "1") (pinfunction "DO_1") (pintype "output"))
    )
    (net (code "116") (name "Net-(D123-DO)") (class "Default")
      (node (ref "D123") (pin "1") (pinfunction "DO_1") (pintype "output"))
      (node (ref "D153") (pin "3") (pinfunction "DI_3") (pintype "input"))
    )
    (net (code "117") (name "Net-(D124-DI)") (class "Default")
      (node (ref "D124") (pin "3") (pinfunction "DI_3") (pintype "input"))
      (node (ref "D94") (pin "1") (pinfunction "DO_1") (pintype "output"))
    )
    (net (code "118") (name "Net-(D124-DO)") (class "Default")
      (node (ref "D124") (pin "1") (pinfunction "DO_1") (pintype "output"))
      (node (ref "D154") (pin "3") (pinfunction "DI_3") (pintype "input"))
    )
    (net (code "119") (name "Net-(D125-DI)") (class "Default")
      (node (ref "D125") (pin "3") (pinfunction "DI_3") (pintype "input"))
      (node (ref "D95") (pin "1") (pinfunction "DO_1") (pintype "output"))
    )
    (net (code "120") (name "Net-(D125-DO)") (class "Default")
      (node (ref "D125") (pin "1") (pinfunction "DO_1") (pintype "output"))
      (node (ref "D155") (pin "3") (pinfunction "DI_3") (pintype "input"))
    )
    (net (code "121") (name "Net-(D126-DI)") (class "Default")
      (node (ref "D126") (pin "3") (pinfunction "DI_3") (pintype "input"))
      (node (ref "D96") (pin "1") (pinfunction "DO_1") (pintype "output"))
    )
    (net (code "122") (name "Net-(D126-DO)") (class "Default")
      (node (ref "D126") (pin "1") (pinfunction "DO_1") (pintype "output"))
      (node (ref "D156") (pin "3") (pinfunction "DI_3") (pintype "input"))
    )
    (net (code "123") (name "Net-(D127-DI)") (class "Default")
      (node (ref "D127") (pin "3") (pinfunction "DI_3") (pintype "input"))
      (node (ref "D97") (pin "1") (pinfunction "DO_1") (pintype "output"))
    )
    (net (code "124") (name "Net-(D127-DO)") (class "Default")
      (node (ref "D127") (pin "1") (pinfunction "DO_1") (pintype "output"))
      (node (ref "D157") (pin "3") (pinfunction "DI_3") (pintype "input"))
    )
    (net (code "125") (name "Net-(D128-DI)") (class "Default")
      (node (ref "D128") (pin "3") (pinfunction "DI_3") (pintype "input"))
      (node (ref "D98") (pin "1") (pinfunction "DO_1") (pintype "output"))
    )
    (net (code "126") (name "Net-(D128-DO)") (class "Default")
      (node (ref "D128") (pin "1") (pinfunction "DO_1") (pintype "output"))
      (node (ref "D158") (pin "3") (pinfunction "DI_3") (pintype "input"))
    )
    (net (code "127") (name "Net-(D129-DI)") (class "Default")
      (node (ref "D129") (pin "3") (pinfunction "DI_3") (pintype "input"))
      (node (ref "D99") (pin "1") (pinfunction "DO_1") (pintype "output"))
    )
    (net (code "128") (name "Net-(D129-DO)") (class "Default")
      (node (ref "D129") (pin "1") (pinfunction "DO_1") (pintype "output"))
      (node (ref "D159") (pin "3") (pinfunction "DI_3") (pintype "input"))
    )
    (net (code "129") (name "Net-(D130-DO)") (class "Default")
      (node (ref "D130") (pin "1") (pinfunction "DO_1") (pintype "output"))
      (node (ref "D160") (pin "3") (pinfunction "DI_3") (pintype "input"))
    )
    (net (code "130") (name "Net-(D131-DO)") (class "Default")
      (node (ref "D131") (pin "1") (pinfunction "DO_1") (pintype "output"))
      (node (ref "D161") (pin "3") (pinfunction "DI_3") (pintype "input"))
    )
    (net (code "131") (name "Net-(D132-DO)") (class "Default")
      (node (ref "D132") (pin "1") (pinfunction "DO_1") (pintype "output"))
      (node (ref "D162") (pin "3") (pinfunction "DI_3") (pintype "input"))
    )
    (net (code "132") (name "Net-(D133-DO)") (class "Default")
      (node (ref "D133") (pin "1") (pinfunction "DO_1") (pintype "output"))
      (node (ref "D163") (pin "3") (pinfunction "DI_3") (pintype "input"))
    )
    (net (code "133") (name "Net-(D134-DO)") (class "Default")
      (node (ref "D134") (pin "1") (pinfunction "DO_1") (pintype "output"))
      (node (ref "D164") (pin "3") (pinfunction "DI_3") (pintype "input"))
    )
    (net (code "134") (name "Net-(D135-DO)") (class "Default")
      (node (ref "D135") (pin "1") (pinfunction "DO_1") (pintype "output"))
      (node (ref "D165") (pin "3") (pinfunction "DI_3") (pintype "input"))
    )
    (net (code "135") (name "Net-(D136-DO)") (class "Default")
      (node (ref "D136") (pin "1") (pinfunction "DO_1") (pintype "output"))
      (node (ref "D166") (pin "3") (pinfunction "DI_3") (pintype "input"))
    )
    (net (code "136") (name "Net-(D137-DO)") (class "Default")
      (node (ref "D137") (pin "1") (pinfunction "DO_1") (pintype "output"))
      (node (ref "D167") (pin "3") (pinfunction "DI_3") (pintype "input"))
    )
    (net (code "137") (name "Net-(D138-DO)") (class "Default")
      (node (ref "D138") (pin "1") (pinfunction "DO_1") (pintype "output"))
      (node (ref "D168") (pin "3") (pinfunction "DI_3") (pintype "input"))
    )
    (net (code "138") (name "Net-(D139-DO)") (class "Default")
      (node (ref "D139") (pin "1") (pinfunction "DO_1") (pintype "output"))
      (node (ref "D169") (pin "3") (pinfunction "DI_3") (pintype "input"))
    )
    (net (code "139") (name "Net-(D140-DO)") (class "Default")
      (node (ref "D140") (pin "1") (pinfunction "DO_1") (pintype "output"))
      (node (ref "D170") (pin "3") (pinfunction "DI_3") (pintype "input"))
    )
    (net (code "140") (name "Net-(D141-DO)") (class "Default")
      (node (ref "D141") (pin "1") (pinfunction "DO_1") (pintype "output"))
      (node (ref "D171") (pin "3") (pinfunction "DI_3") (pintype "input"))
    )
    (net (code "141") (name "Net-(D142-DO)") (class "Default")
      (node (ref "D142") (pin "1") (pinfunction "DO_1") (pintype "output"))
      (node (ref "D172") (pin "3") (pinfunction "DI_3") (pintype "input"))
    )
    (net (code "142") (name "Net-(D143-DO)") (class "Default")
      (node (ref "D143") (pin "1") (pinfunction "DO_1") (pintype "output"))
      (node (ref "D173") (pin "3") (pinfunction "DI_3") (pintype "input"))
    )
    (net (code "143") (name "Net-(D144-DO)") (class "Default")
      (node (ref "D144") (pin "1") (pinfunction "DO_1") (pintype "output"))
      (node (ref "D174") (pin "3") (pinfunction "DI_3") (pintype "input"))
    )
    (net (code "144") (name "Net-(D145-DO)") (class "Default")
      (node (ref "D145") (pin "1") (pinfunction "DO_1") (pintype "output"))
      (node (ref "D175") (pin "3") (pinfunction "DI_3") (pintype "input"))
    )
    (net (code "145") (name "Net-(D146-DO)") (class "Default")
      (node (ref "D146") (pin "1") (pinfunction "DO_1") (pintype "output"))
      (node (ref "D176") (pin "3") (pinfunction "DI_3") (pintype "input"))
    )
    (net (code "146") (name "Net-(D147-DO)") (class "Default")
      (node (ref "D147") (pin "1") (pinfunction "DO_1") (pintype "output"))
      (node (ref "D177") (pin "3") (pinfunction "DI_3") (pintype "input"))
    )
    (net (code "147") (name "Net-(D148-DO)") (class "Default")
      (node (ref "D148") (pin "1") (pinfunction "DO_1") (pintype "output"))
      (node (ref "D178") (pin "3") (pinfunction "DI_3") (pintype "input"))
    )
    (net (code "148") (name "Net-(D149-DO)") (class "Default")
      (node (ref "D149") (pin "1") (pinfunction "DO_1") (pintype "output"))
      (node (ref "D179") (pin "3") (pinfunction "DI_3") (pintype "input"))
    )
    (net (code "149") (name "Net-(D150-DO)") (class "Default")
      (node (ref "D150") (pin "1") (pinfunction "DO_1") (pintype "output"))
      (node (ref "D180") (pin "3") (pinfunction "DI_3") (pintype "input"))
    )
    (net (code "150") (name "Net-(D151-DO)") (class "Default")
      (node (ref "D151") (pin "1") (pinfunction "DO_1") (pintype "output"))
      (node (ref "D181") (pin "3") (pinfunction "DI_3") (pintype "input"))
    )
    (net (code "151") (name "Net-(D152-DO)") (class "Default")
      (node (ref "D152") (pin "1") (pinfunction "DO_1") (pintype "output"))
      (node (ref "D182") (pin "3") (pinfunction "DI_3") (pintype "input"))
    )
    (net (code "152") (name "Net-(D153-DO)") (class "Default")
      (node (ref "D153") (pin "1") (pinfunction "DO_1") (pintype "output"))
      (node (ref "D183") (pin "3") (pinfunction "DI_3") (pintype "input"))
    )
    (net (code "153") (name "Net-(D154-DO)") (class "Default")
      (node (ref "D154") (pin "1") (pinfunction "DO_1") (pintype "output"))
      (node (ref "D184") (pin "3") (pinfunction "DI_3") (pintype "input"))
    )
    (net (code "154") (name "Net-(D155-DO)") (class "Default")
      (node (ref "D155") (pin "1") (pinfunction "DO_1") (pintype "output"))
      (node (ref "D185") (pin "3") (pinfunction "DI_3") (pintype "input"))
    )
    (net (code "155") (name "Net-(D156-DO)") (class "Default")
      (node (ref "D156") (pin "1") (pinfunction "DO_1") (pintype "output"))
      (node (ref "D186") (pin "3") (pinfunction "DI_3") (pintype "input"))
    )
    (net (code "156") (name "Net-(D157-DO)") (class "Default")
      (node (ref "D157") (pin "1") (pinfunction "DO_1") (pintype "output"))
      (node (ref "D187") (pin "3") (pinfunction "DI_3") (pintype "input"))
    )
    (net (code "157") (name "Net-(D158-DO)") (class "Default")
      (node (ref "D158") (pin "1") (pinfunction "DO_1") (pintype "output"))
      (node (ref "D188") (pin "3") (pinfunction "DI_3") (pintype "input"))
    )
    (net (code "158") (name "Net-(D159-DO)") (class "Default")
      (node (ref "D159") (pin "1") (pinfunction "DO_1") (pintype "output"))
      (node (ref "D189") (pin "3") (pinfunction "DI_3") (pintype "input"))
    )
    (net (code "159") (name "Net-(D160-DO)") (class "Default")
      (node (ref "D160") (pin "1") (pinfunction "DO_1") (pintype "output"))
      (node (ref "D190") (pin "3") (pinfunction "DI_3") (pintype "input"))
    )
    (net (code "160") (name "Net-(D161-DO)") (class "Default")
      (node (ref "D161") (pin "1") (pinfunction "DO_1") (pintype "output"))
      (node (ref "D191") (pin "3") (pinfunction "DI_3") (pintype "input"))
    )
    (net (code "161") (name "Net-(D162-DO)") (class "Default")
      (node (ref "D162") (pin "1") (pinfunction "DO_1") (pintype "output"))
      (node (ref "D192") (pin "3") (pinfunction "DI_3") (pintype "input"))
    )
    (net (code "162") (name "Net-(D163-DO)") (class "Default")
      (node (ref "D163") (pin "1") (pinfunction "DO_1") (pintype "output"))
      (node (ref "D193") (pin "3") (pinfunction "DI_3") (pintype "input"))
    )
    (net (code "163") (name "Net-(D164-DO)") (class "Default")
      (node (ref "D164") (pin "1") (pinfunction "DO_1") (pintype "output"))
      (node (ref "D194") (pin "3") (pinfunction "DI_3") (pintype "input"))
    )
    (net (code "164") (name "Net-(D165-DO)") (class "Default")
      (node (ref "D165") (pin "1") (pinfunction "DO_1") (pintype "output"))
      (node (ref "D195") (pin "3") (pinfunction "DI_3") (pintype "input"))
    )
    (net (code "165") (name "Net-(D166-DO)") (class "Default")
      (node (ref "D166") (pin "1") (pinfunction "DO_1") (pintype "output"))
      (node (ref "D196") (pin "3") (pinfunction "DI_3") (pintype "input"))
    )
    (net (code "166") (name "Net-(D167-DO)") (class "Default")
      (node (ref "D167") (pin "1") (pinfunction "DO_1") (pintype "output"))
      (node (ref "D197") (pin "3") (pinfunction "DI_3") (pintype "input"))
    )
    (net (code "167") (name "Net-(D168-DO)") (class "Default")
      (node (ref "D168") (pin "1") (pinfunction "DO_1") (pintype "output"))
      (node (ref "D198") (pin "3") (pinfunction "DI_3") (pintype "input"))
    )
    (net (code "168") (name "Net-(D169-DO)") (class "Default")
      (node (ref "D169") (pin "1") (pinfunction "DO_1") (pintype "output"))
      (node (ref "D199") (pin "3") (pinfunction "DI_3") (pintype "input"))
    )
    (net (code "169") (name "Net-(D170-DO)") (class "Default")
      (node (ref "D170") (pin "1") (pinfunction "DO_1") (pintype "output"))
      (node (ref "D200") (pin "3") (pinfunction "DI_3") (pintype "input"))
    )
    (net (code "170") (name "Net-(D171-DO)") (class "Default")
      (node (ref "D171") (pin "1") (pinfunction "DO_1") (pintype "output"))
      (node (ref "D201") (pin "3") (pinfunction "DI_3") (pintype "input"))
    )
    (net (code "171") (name "Net-(D172-DO)") (class "Default")
      (node (ref "D172") (pin "1") (pinfunction "DO_1") (pintype "output"))
      (node (ref "D202") (pin "3") (pinfunction "DI_3") (pintype "input"))
    )
    (net (code "172") (name "Net-(D173-DO)") (class "Default")
      (node (ref "D173") (pin "1") (pinfunction "DO_1") (pintype "output"))
      (node (ref "D203") (pin "3") (pinfunction "DI_3") (pintype "input"))
    )
    (net (code "173") (name "Net-(D174-DO)") (class "Default")
      (node (ref "D174") (pin "1") (pinfunction "DO_1") (pintype "output"))
      (node (ref "D204") (pin "3") (pinfunction "DI_3") (pintype "input"))
    )
    (net (code "174") (name "Net-(D175-DO)") (class "Default")
      (node (ref "D175") (pin "1") (pinfunction "DO_1") (pintype "output"))
      (node (ref "D205") (pin "3") (pinfunction "DI_3") (pintype "input"))
    )
    (net (code "175") (name "Net-(D176-DO)") (class "Default")
      (node (ref "D176") (pin "1") (pinfunction "DO_1") (pintype "output"))
      (node (ref "D206") (pin "3") (pinfunction "DI_3") (pintype "input"))
    )
    (net (code "176") (name "Net-(D177-DO)") (class "Default")
      (node (ref "D177") (pin "1") (pinfunction "DO_1") (pintype "output"))
      (node (ref "D207") (pin "3") (pinfunction "DI_3") (pintype "input"))
    )
    (net (code "177") (name "Net-(D178-DO)") (class "Default")
      (node (ref "D178") (pin "1") (pinfunction "DO_1") (pintype "output"))
      (node (ref "D208") (pin "3") (pinfunction "DI_3") (pintype "input"))
    )
    (net (code "178") (name "Net-(D179-DO)") (class "Default")
      (node (ref "D179") (pin "1") (pinfunction "DO_1") (pintype "output"))
      (node (ref "D209") (pin "3") (pinfunction "DI_3") (pintype "input"))
    )
    (net (code "179") (name "Net-(D180-DO)") (class "Default")
      (node (ref "D180") (pin "1") (pinfunction "DO_1") (pintype "output"))
      (node (ref "D61") (pin "3") (pinfunction "DI_3") (pintype "input"))
    )
    (net (code "180") (name "Net-(D181-DO)") (class "Default")
      (node (ref "D181") (pin "1") (pinfunction "DO_1") (pintype "output"))
      (node (ref "D62") (pin "3") (pinfunction "DI_3") (pintype "input"))
    )
    (net (code "181") (name "Net-(D182-DO)") (class "Default")
      (node (ref "D182") (pin "1") (pinfunction "DO_1") (pintype "output"))
      (node (ref "D63") (pin "3") (pinfunction "DI_3") (pintype "input"))
    )
    (net (code "182") (name "Net-(D183-DO)") (class "Default")
      (node (ref "D183") (pin "1") (pinfunction "DO_1") (pintype "output"))
      (node (ref "D64") (pin "3") (pinfunction "DI_3") (pintype "input"))
    )
    (net (code "183") (name "Net-(D184-DO)") (class "Default")
      (node (ref "D184") (pin "1") (pinfunction "DO_1") (pintype "output"))
      (node (ref "D65") (pin "3") (pinfunction "DI_3") (pintype "input"))
    )
    (net (code "184") (name "Net-(D185-DO)") (class "Default")
      (node (ref "D185") (pin "1") (pinfunction "DO_1") (pintype "output"))
      (node (ref "D66") (pin "3") (pinfunction "DI_3") (pintype "input"))
    )
    (net (code "185") (name "Net-(D186-DO)") (class "Default")
      (node (ref "D186") (pin "1") (pinfunction "DO_1") (pintype "output"))
      (node (ref "D67") (pin "3") (pinfunction "DI_3") (pintype "input"))
    )
    (net (code "186") (name "Net-(D187-DO)") (class "Default")
      (node (ref "D187") (pin "1") (pinfunction "DO_1") (pintype "output"))
      (node (ref "D68") (pin "3") (pinfunction "DI_3") (pintype "input"))
    )
    (net (code "187") (name "Net-(D188-DO)") (class "Default")
      (node (ref "D188") (pin "1") (pinfunction "DO_1") (pintype "output"))
      (node (ref "D69") (pin "3") (pinfunction "DI_3") (pintype "input"))
    )
    (net (code "188") (name "Net-(D189-DO)") (class "Default")
      (node (ref "D189") (pin "1") (pinfunction "DO_1") (pintype "output"))
      (node (ref "D70") (pin "3") (pinfunction "DI_3") (pintype "input"))
    )
    (net (code "189") (name "Net-(D190-DO)") (class "Default")
      (node (ref "D190") (pin "1") (pinfunction "DO_1") (pintype "output"))
      (node (ref "D71") (pin "3") (pinfunction "DI_3") (pintype "input"))
    )
    (net (code "190") (name "Net-(D191-DO)") (class "Default")
      (node (ref "D191") (pin "1") (pinfunction "DO_1") (pintype "output"))
      (node (ref "D72") (pin "3") (pinfunction "DI_3") (pintype "input"))
    )
    (net (code "191") (name "Net-(D192-DO)") (class "Default")
      (node (ref "D192") (pin "1") (pinfunction "DO_1") (pintype "output"))
      (node (ref "D73") (pin "3") (pinfunction "DI_3") (pintype "input"))
    )
    (net (code "192") (name "Net-(D193-DO)") (class "Default")
      (node (ref "D193") (pin "1") (pinfunction "DO_1") (pintype "output"))
      (node (ref "D74") (pin "3") (pinfunction "DI_3") (pintype "input"))
    )
    (net (code "193") (name "Net-(D194-DO)") (class "Default")
      (node (ref "D194") (pin "1") (pinfunction "DO_1") (pintype "output"))
      (node (ref "D75") (pin "3") (pinfunction "DI_3") (pintype "input"))
    )
    (net (code "194") (name "Net-(D195-DO)") (class "Default")
      (node (ref "D195") (pin "1") (pinfunction "DO_1") (pintype "output"))
      (node (ref "D76") (pin "3") (pinfunction "DI_3") (pintype "input"))
    )
    (net (code "195") (name "Net-(D196-DO)") (class "Default")
      (node (ref "D196") (pin "1") (pinfunction "DO_1") (pintype "output"))
      (node (ref "D77") (pin "3") (pinfunction "DI_3") (pintype "input"))
    )
    (net (code "196") (name "Net-(D197-DO)") (class "Default")
      (node (ref "D197") (pin "1") (pinfunction "DO_1") (pintype "output"))
      (node (ref "D78") (pin "3") (pinfunction "DI_3") (pintype "input"))
    )
    (net (code "197") (name "Net-(D198-DO)") (class "Default")
      (node (ref "D198") (pin "1") (pinfunction "DO_1") (pintype "output"))
      (node (ref "D79") (pin "3") (pinfunction "DI_3") (pintype "input"))
    )
    (net (code "198") (name "Net-(D199-DO)") (class "Default")
      (node (ref "D199") (pin "1") (pinfunction "DO_1") (pintype "output"))
      (node (ref "D80") (pin "3") (pinfunction "DI_3") (pintype "input"))
    )
    (net (code "199") (name "Net-(D200-DO)") (class "Default")
      (node (ref "D200") (pin "1") (pinfunction "DO_1") (pintype "output"))
      (node (ref "D81") (pin "3") (pinfunction "DI_3") (pintype "input"))
    )
    (net (code "200") (name "Net-(D201-DO)") (class "Default")
      (node (ref "D201") (pin "1") (pinfunction "DO_1") (pintype "output"))
      (node (ref "D82") (pin "3") (pinfunction "DI_3") (pintype "input"))
    )
    (net (code "201") (name "Net-(D202-DO)") (class "Default")
      (node (ref "D202") (pin "1") (pinfunction "DO_1") (pintype "output"))
      (node (ref "D83") (pin "3") (pinfunction "DI_3") (pintype "input"))
    )
    (net (code "202") (name "Net-(D203-DO)") (class "Default")
      (node (ref "D203") (pin "1") (pinfunction "DO_1") (pintype "output"))
      (node (ref "D84") (pin "3") (pinfunction "DI_3") (pintype "input"))
    )
    (net (code "203") (name "Net-(D204-DO)") (class "Default")
      (node (ref "D204") (pin "1") (pinfunction "DO_1") (pintype "output"))
      (node (ref "D85") (pin "3") (pinfunction "DI_3") (pintype "input"))
    )
    (net (code "204") (name "Net-(D205-DO)") (class "Default")
      (node (ref "D205") (pin "1") (pinfunction "DO_1") (pintype "output"))
      (node (ref "D86") (pin "3") (pinfunction "DI_3") (pintype "input"))
    )
    (net (code "205") (name "Net-(D206-DO)") (class "Default")
      (node (ref "D206") (pin "1") (pinfunction "DO_1") (pintype "output"))
      (node (ref "D87") (pin "3") (pinfunction "DI_3") (pintype "input"))
    )
    (net (code "206") (name "Net-(D207-DO)") (class "Default")
      (node (ref "D207") (pin "1") (pinfunction "DO_1") (pintype "output"))
      (node (ref "D88") (pin "3") (pinfunction "DI_3") (pintype "input"))
    )
    (net (code "207") (name "Net-(D208-DO)") (class "Default")
      (node (ref "D208") (pin "1") (pinfunction "DO_1") (pintype "output"))
      (node (ref "D89") (pin "3") (pinfunction "DI_3") (pintype "input"))
    )
    (net (code "208") (name "Net-(D210-DO)") (class "Default")
      (node (ref "D210") (pin "1") (pinfunction "DO_1") (pintype "output"))
      (node (ref "D240") (pin "3") (pinfunction "DI_3") (pintype "input"))
    )
    (net (code "209") (name "Net-(D211-DI)") (class "Default")
      (node (ref "D211") (pin "3") (pinfunction "DI_3") (pintype "input"))
      (node (ref "D330") (pin "1") (pinfunction "DO_1") (pintype "output"))
    )
    (net (code "210") (name "Net-(D211-DO)") (class "Default")
      (node (ref "D211") (pin "1") (pinfunction "DO_1") (pintype "output"))
      (node (ref "D241") (pin "3") (pinfunction "DI_3") (pintype "input"))
    )
    (net (code "211") (name "Net-(D212-DI)") (class "Default")
      (node (ref "D212") (pin "3") (pinfunction "DI_3") (pintype "input"))
      (node (ref "D331") (pin "1") (pinfunction "DO_1") (pintype "output"))
    )
    (net (code "212") (name "Net-(D212-DO)") (class "Default")
      (node (ref "D212") (pin "1") (pinfunction "DO_1") (pintype "output"))
      (node (ref "D242") (pin "3") (pinfunction "DI_3") (pintype "input"))
    )
    (net (code "213") (name "Net-(D213-DI)") (class "Default")
      (node (ref "D213") (pin "3") (pinfunction "DI_3") (pintype "input"))
      (node (ref "D332") (pin "1") (pinfunction "DO_1") (pintype "output"))
    )
    (net (code "214") (name "Net-(D213-DO)") (class "Default")
      (node (ref "D213") (pin "1") (pinfunction "DO_1") (pintype "output"))
      (node (ref "D243") (pin "3") (pinfunction "DI_3") (pintype "input"))
    )
    (net (code "215") (name "Net-(D214-DI)") (class "Default")
      (node (ref "D214") (pin "3") (pinfunction "DI_3") (pintype "input"))
      (node (ref "D333") (pin "1") (pinfunction "DO_1") (pintype "output"))
    )
    (net (code "216") (name "Net-(D214-DO)") (class "Default")
      (node (ref "D214") (pin "1") (pinfunction "DO_1") (pintype "output"))
      (node (ref "D244") (pin "3") (pinfunction "DI_3") (pintype "input"))
    )
    (net (code "217") (name "Net-(D215-DI)") (class "Default")
      (node (ref "D215") (pin "3") (pinfunction "DI_3") (pintype "input"))
      (node (ref "D334") (pin "1") (pinfunction "DO_1") (pintype "output"))
    )
    (net (code "218") (name "Net-(D215-DO)") (class "Default")
      (node (ref "D215") (pin "1") (pinfunction "DO_1") (pintype "output"))
      (node (ref "D245") (pin "3") (pinfunction "DI_3") (pintype "input"))
    )
    (net (code "219") (name "Net-(D216-DI)") (class "Default")
      (node (ref "D216") (pin "3") (pinfunction "DI_3") (pintype "input"))
      (node (ref "D335") (pin "1") (pinfunction "DO_1") (pintype "output"))
    )
    (net (code "220") (name "Net-(D216-DO)") (class "Default")
      (node (ref "D216") (pin "1") (pinfunction "DO_1") (pintype "output"))
      (node (ref "D246") (pin "3") (pinfunction "DI_3") (pintype "input"))
    )
    (net (code "221") (name "Net-(D217-DI)") (class "Default")
      (node (ref "D217") (pin "3") (pinfunction "DI_3") (pintype "input"))
      (node (ref "D336") (pin "1") (pinfunction "DO_1") (pintype "output"))
    )
    (net (code "222") (name "Net-(D217-DO)") (class "Default")
      (node (ref "D217") (pin "1") (pinfunction "DO_1") (pintype "output"))
      (node (ref "D247") (pin "3") (pinfunction "DI_3") (pintype "input"))
    )
    (net (code "223") (name "Net-(D218-DI)") (class "Default")
      (node (ref "D218") (pin "3") (pinfunction "DI_3") (pintype "input"))
      (node (ref "D337") (pin "1") (pinfunction "DO_1") (pintype "output"))
    )
    (net (code "224") (name "Net-(D218-DO)") (class "Default")
      (node (ref "D218") (pin "1") (pinfunction "DO_1") (pintype "output"))
      (node (ref "D248") (pin "3") (pinfunction "DI_3") (pintype "input"))
    )
    (net (code "225") (name "Net-(D219-DI)") (class "Default")
      (node (ref "D219") (pin "3") (pinfunction "DI_3") (pintype "input"))
      (node (ref "D338") (pin "1") (pinfunction "DO_1") (pintype "output"))
    )
    (net (code "226") (name "Net-(D219-DO)") (class "Default")
      (node (ref "D219") (pin "1") (pinfunction "DO_1") (pintype "output"))
      (node (ref "D249") (pin "3") (pinfunction "DI_3") (pintype "input"))
    )
    (net (code "227") (name "Net-(D220-DI)") (class "Default")
      (node (ref "D220") (pin "3") (pinfunction "DI_3") (pintype "input"))
      (node (ref "D339") (pin "1") (pinfunction "DO_1") (pintype "output"))
    )
    (net (code "228") (name "Net-(D220-DO)") (class "Default")
      (node (ref "D220") (pin "1") (pinfunction "DO_1") (pintype "output"))
      (node (ref "D250") (pin "3") (pinfunction "DI_3") (pintype "input"))
    )
    (net (code "229") (name "Net-(D221-DI)") (class "Default")
      (node (ref "D221") (pin "3") (pinfunction "DI_3") (pintype "input"))
      (node (ref "D340") (pin "1") (pinfunction "DO_1") (pintype "output"))
    )
    (net (code "230") (name "Net-(D221-DO)") (class "Default")
      (node (ref "D221") (pin "1") (pinfunction "DO_1") (pintype "output"))
      (node (ref "D251") (pin "3") (pinfunction "DI_3") (pintype "input"))
    )
    (net (code "231") (name "Net-(D222-DI)") (class "Default")
      (node (ref "D222") (pin "3") (pinfunction "DI_3") (pintype "input"))
      (node (ref "D341") (pin "1") (pinfunction "DO_1") (pintype "output"))
    )
    (net (code "232") (name "Net-(D222-DO)") (class "Default")
      (node (ref "D222") (pin "1") (pinfunction "DO_1") (pintype "output"))
      (node (ref "D252") (pin "3") (pinfunction "DI_3") (pintype "input"))
    )
    (net (code "233") (name "Net-(D223-DI)") (class "Default")
      (node (ref "D223") (pin "3") (pinfunction "DI_3") (pintype "input"))
      (node (ref "D342") (pin "1") (pinfunction "DO_1") (pintype "output"))
    )
    (net (code "234") (name "Net-(D223-DO)") (class "Default")
      (node (ref "D223") (pin "1") (pinfunction "DO_1") (pintype "output"))
      (node (ref "D253") (pin "3") (pinfunction "DI_3") (pintype "input"))
    )
    (net (code "235") (name "Net-(D224-DI)") (class "Default")
      (node (ref "D224") (pin "3") (pinfunction "DI_3") (pintype "input"))
      (node (ref "D343") (pin "1") (pinfunction "DO_1") (pintype "output"))
    )
    (net (code "236") (name "Net-(D224-DO)") (class "Default")
      (node (ref "D224") (pin "1") (pinfunction "DO_1") (pintype "output"))
      (node (ref "D254") (pin "3") (pinfunction "DI_3") (pintype "input"))
    )
    (net (code "237") (name "Net-(D225-DI)") (class "Default")
      (node (ref "D225") (pin "3") (pinfunction "DI_3") (pintype "input"))
      (node (ref "D344") (pin "1") (pinfunction "DO_1") (pintype "output"))
    )
    (net (code "238") (name "Net-(D225-DO)") (class "Default")
      (node (ref "D225") (pin "1") (pinfunction "DO_1") (pintype "output"))
      (node (ref "D255") (pin "3") (pinfunction "DI_3") (pintype "input"))
    )
    (net (code "239") (name "Net-(D226-DI)") (class "Default")
      (node (ref "D226") (pin "3") (pinfunction "DI_3") (pintype "input"))
      (node (ref "D345") (pin "1") (pinfunction "DO_1") (pintype "output"))
    )
    (net (code "240") (name "Net-(D226-DO)") (class "Default")
      (node (ref "D226") (pin "1") (pinfunction "DO_1") (pintype "output"))
      (node (ref "D256") (pin "3") (pinfunction "DI_3") (pintype "input"))
    )
    (net (code "241") (name "Net-(D227-DI)") (class "Default")
      (node (ref "D227") (pin "3") (pinfunction "DI_3") (pintype "input"))
      (node (ref "D346") (pin "1") (pinfunction "DO_1") (pintype "output"))
    )
    (net (code "242") (name "Net-(D227-DO)") (class "Default")
      (node (ref "D227") (pin "1") (pinfunction "DO_1") (pintype "output"))
      (node (ref "D257") (pin "3") (pinfunction "DI_3") (pintype "input"))
    )
    (net (code "243") (name "Net-(D228-DI)") (class "Default")
      (node (ref "D228") (pin "3") (pinfunction "DI_3") (pintype "input"))
      (node (ref "D347") (pin "1") (pinfunction "DO_1") (pintype "output"))
    )
    (net (code "244") (name "Net-(D228-DO)") (class "Default")
      (node (ref "D228") (pin "1") (pinfunction "DO_1") (pintype "output"))
      (node (ref "D258") (pin "3") (pinfunction "DI_3") (pintype "input"))
    )
    (net (code "245") (name "Net-(D229-DI)") (class "Default")
      (node (ref "D229") (pin "3") (pinfunction "DI_3") (pintype "input"))
      (node (ref "D348") (pin "1") (pinfunction "DO_1") (pintype "output"))
    )
    (net (code "246") (name "Net-(D229-DO)") (class "Default")
      (node (ref "D229") (pin "1") (pinfunction "DO_1") (pintype "output"))
      (node (ref "D259") (pin "3") (pinfunction "DI_3") (pintype "input"))
    )
    (net (code "247") (name "Net-(D230-DI)") (class "Default")
      (node (ref "D230") (pin "3") (pinfunction "DI_3") (pintype "input"))
      (node (ref "D349") (pin "1") (pinfunction "DO_1") (pintype "output"))
    )
    (net (code "248") (name "Net-(D230-DO)") (class "Default")
      (node (ref "D230") (pin "1") (pinfunction "DO_1") (pintype "output"))
      (node (ref "D260") (pin "3") (pinfunction "DI_3") (pintype "input"))
    )
    (net (code "249") (name "Net-(D231-DI)") (class "Default")
      (node (ref "D231") (pin "3") (pinfunction "DI_3") (pintype "input"))
      (node (ref "D350") (pin "1") (pinfunction "DO_1") (pintype "output"))
    )
    (net (code "250") (name "Net-(D231-DO)") (class "Default")
      (node (ref "D231") (pin "1") (pinfunction "DO_1") (pintype "output"))
      (node (ref "D261") (pin "3") (pinfunction "DI_3") (pintype "input"))
    )
    (net (code "251") (name "Net-(D232-DI)") (class "Default")
      (node (ref "D232") (pin "3") (pinfunction "DI_3") (pintype "input"))
      (node (ref "D351") (pin "1") (pinfunction "DO_1") (pintype "output"))
    )
    (net (code "252") (name "Net-(D232-DO)") (class "Default")
      (node (ref "D232") (pin "1") (pinfunction "DO_1") (pintype "output"))
      (node (ref "D262") (pin "3") (pinfunction "DI_3") (pintype "input"))
    )
    (net (code "253") (name "Net-(D233-DI)") (class "Default")
      (node (ref "D233") (pin "3") (pinfunction "DI_3") (pintype "input"))
      (node (ref "D352") (pin "1") (pinfunction "DO_1") (pintype "output"))
    )
    (net (code "254") (name "Net-(D233-DO)") (class "Default")
      (node (ref "D233") (pin "1") (pinfunction "DO_1") (pintype "output"))
      (node (ref "D263") (pin "3") (pinfunction "DI_3") (pintype "input"))
    )
    (net (code "255") (name "Net-(D234-DI)") (class "Default")
      (node (ref "D234") (pin "3") (pinfunction "DI_3") (pintype "input"))
      (node (ref "D353") (pin "1") (pinfunction "DO_1") (pintype "output"))
    )
    (net (code "256") (name "Net-(D234-DO)") (class "Default")
      (node (ref "D234") (pin "1") (pinfunction "DO_1") (pintype "output"))
      (node (ref "D264") (pin "3") (pinfunction "DI_3") (pintype "input"))
    )
    (net (code "257") (name "Net-(D235-DI)") (class "Default")
      (node (ref "D235") (pin "3") (pinfunction "DI_3") (pintype "input"))
      (node (ref "D354") (pin "1") (pinfunction "DO_1") (pintype "output"))
    )
    (net (code "258") (name "Net-(D235-DO)") (class "Default")
      (node (ref "D235") (pin "1") (pinfunction "DO_1") (pintype "output"))
      (node (ref "D265") (pin "3") (pinfunction "DI_3") (pintype "input"))
    )
    (net (code "259") (name "Net-(D236-DI)") (class "Default")
      (node (ref "D236") (pin "3") (pinfunction "DI_3") (pintype "input"))
      (node (ref "D355") (pin "1") (pinfunction "DO_1") (pintype "output"))
    )
    (net (code "260") (name "Net-(D236-DO)") (class "Default")
      (node (ref "D236") (pin "1") (pinfunction "DO_1") (pintype "output"))
      (node (ref "D266") (pin "3") (pinfunction "DI_3") (pintype "input"))
    )
    (net (code "261") (name "Net-(D237-DI)") (class "Default")
      (node (ref "D237") (pin "3") (pinfunction "DI_3") (pintype "input"))
      (node (ref "D356") (pin "1") (pinfunction "DO_1") (pintype "output"))
    )
    (net (code "262") (name "Net-(D237-DO)") (class "Default")
      (node (ref "D237") (pin "1") (pinfunction "DO_1") (pintype "output"))
      (node (ref "D267") (pin "3") (pinfunction "DI_3") (pintype "input"))
    )
    (net (code "263") (name "Net-(D238-DI)") (class "Default")
      (node (ref "D238") (pin "3") (pinfunction "DI_3") (pintype "input"))
      (node (ref "D357") (pin "1") (pinfunction "DO_1") (pintype "output"))
    )
    (net (code "264") (name "Net-(D238-DO)") (class "Default")
      (node (ref "D238") (pin "1") (pinfunction "DO_1") (pintype "output"))
      (node (ref "D268") (pin "3") (pinfunction "DI_3") (pintype "input"))
    )
    (net (code "265") (name "Net-(D239-DI)") (class "Default")
      (node (ref "D239") (pin "3") (pinfunction "DI_3") (pintype "input"))
      (node (ref "D358") (pin "1") (pinfunction "DO_1") (pintype "output"))
    )
    (net (code "266") (name "Net-(D239-DO)") (class "Default")
      (node (ref "D239") (pin "1") (pinfunction "DO_1") (pintype "output"))
      (node (ref "D269") (pin "3") (pinfunction "DI_3") (pintype "input"))
    )
    (net (code "267") (name "Net-(D240-DO)") (class "Default")
      (node (ref "D240") (pin "1") (pinfunction "DO_1") (pintype "output"))
      (node (ref "D270") (pin "3") (pinfunction "DI_3") (pintype "input"))
    )
    (net (code "268") (name "Net-(D241-DO)") (class "Default")
      (node (ref "D241") (pin "1") (pinfunction "DO_1") (pintype "output"))
      (node (ref "D271") (pin "3") (pinfunction "DI_3") (pintype "input"))
    )
    (net (code "269") (name "Net-(D242-DO)") (class "Default")
      (node (ref "D242") (pin "1") (pinfunction "DO_1") (pintype "output"))
      (node (ref "D272") (pin "3") (pinfunction "DI_3") (pintype "input"))
    )
    (net (code "270") (name "Net-(D243-DO)") (class "Default")
      (node (ref "D243") (pin "1") (pinfunction "DO_1") (pintype "output"))
      (node (ref "D273") (pin "3") (pinfunction "DI_3") (pintype "input"))
    )
    (net (code "271") (name "Net-(D244-DO)") (class "Default")
      (node (ref "D244") (pin "1") (pinfunction "DO_1") (pintype "output"))
      (node (ref "D274") (pin "3") (pinfunction "DI_3") (pintype "input"))
    )
    (net (code "272") (name "Net-(D245-DO)") (class "Default")
      (node (ref "D245") (pin "1") (pinfunction "DO_1") (pintype "output"))
      (node (ref "D275") (pin "3") (pinfunction "DI_3") (pintype "input"))
    )
    (net (code "273") (name "Net-(D246-DO)") (class "Default")
      (node (ref "D246") (pin "1") (pinfunction "DO_1") (pintype "output"))
      (node (ref "D276") (pin "3") (pinfunction "DI_3") (pintype "input"))
    )
    (net (code "274") (name "Net-(D247-DO)") (class "Default")
      (node (ref "D247") (pin "1") (pinfunction "DO_1") (pintype "output"))
      (node (ref "D277") (pin "3") (pinfunction "DI_3") (pintype "input"))
    )
    (net (code "275") (name "Net-(D248-DO)") (class "Default")
      (node (ref "D248") (pin "1") (pinfunction "DO_1") (pintype "output"))
      (node (ref "D278") (pin "3") (pinfunction "DI_3") (pintype "input"))
    )
    (net (code "276") (name "Net-(D249-DO)") (class "Default")
      (node (ref "D249") (pin "1") (pinfunction "DO_1") (pintype "output"))
      (node (ref "D279") (pin "3") (pinfunction "DI_3") (pintype "input"))
    )
    (net (code "277") (name "Net-(D250-DO)") (class "Default")
      (node (ref "D250") (pin "1") (pinfunction "DO_1") (pintype "output"))
      (node (ref "D280") (pin "3") (pinfunction "DI_3") (pintype "input"))
    )
    (net (code "278") (name "Net-(D251-DO)") (class "Default")
      (node (ref "D251") (pin "1") (pinfunction "DO_1") (pintype "output"))
      (node (ref "D281") (pin "3") (pinfunction "DI_3") (pintype "input"))
    )
    (net (code "279") (name "Net-(D252-DO)") (class "Default")
      (node (ref "D252") (pin "1") (pinfunction "DO_1") (pintype "output"))
      (node (ref "D282") (pin "3") (pinfunction "DI_3") (pintype "input"))
    )
    (net (code "280") (name "Net-(D253-DO)") (class "Default")
      (node (ref "D253") (pin "1") (pinfunction "DO_1") (pintype "output"))
      (node (ref "D283") (pin "3") (pinfunction "DI_3") (pintype "input"))
    )
    (net (code "281") (name "Net-(D254-DO)") (class "Default")
      (node (ref "D254") (pin "1") (pinfunction "DO_1") (pintype "output"))
      (node (ref "D284") (pin "3") (pinfunction "DI_3") (pintype "input"))
    )
    (net (code "282") (name "Net-(D255-DO)") (class "Default")
      (node (ref "D255") (pin "1") (pinfunction "DO_1") (pintype "output"))
      (node (ref "D285") (pin "3") (pinfunction "DI_3") (pintype "input"))
    )
    (net (code "283") (name "Net-(D256-DO)") (class "Default")
      (node (ref "D256") (pin "1") (pinfunction "DO_1") (pintype "output"))
      (node (ref "D286") (pin "3") (pinfunction "DI_3") (pintype "input"))
    )
    (net (code "284") (name "Net-(D257-DO)") (class "Default")
      (node (ref "D257") (pin "1") (pinfunction "DO_1") (pintype "output"))
      (node (ref "D287") (pin "3") (pinfunction "DI_3") (pintype "input"))
    )
    (net (code "285") (name "Net-(D258-DO)") (class "Default")
      (node (ref "D258") (pin "1") (pinfunction "DO_1") (pintype "output"))
      (node (ref "D288") (pin "3") (pinfunction "DI_3") (pintype "input"))
    )
    (net (code "286") (name "Net-(D259-DO)") (class "Default")
      (node (ref "D259") (pin "1") (pinfunction "DO_1") (pintype "output"))
      (node (ref "D289") (pin "3") (pinfunction "DI_3") (pintype "input"))
    )
    (net (code "287") (name "Net-(D260-DO)") (class "Default")
      (node (ref "D260") (pin "1") (pinfunction "DO_1") (pintype "output"))
      (node (ref "D290") (pin "3") (pinfunction "DI_3") (pintype "input"))
    )
    (net (code "288") (name "Net-(D261-DO)") (class "Default")
      (node (ref "D261") (pin "1") (pinfunction "DO_1") (pintype "output"))
      (node (ref "D291") (pin "3") (pinfunction "DI_3") (pintype "input"))
    )
    (net (code "289") (name "Net-(D262-DO)") (class "Default")
      (node (ref "D262") (pin "1") (pinfunction "DO_1") (pintype "output"))
      (node (ref "D292") (pin "3") (pinfunction "DI_3") (pintype "input"))
    )
    (net (code "290") (name "Net-(D263-DO)") (class "Default")
      (node (ref "D263") (pin "1") (pinfunction "DO_1") (pintype "output"))
      (node (ref "D293") (pin "3") (pinfunction "DI_3") (pintype "input"))
    )
    (net (code "291") (name "Net-(D264-DO)") (class "Default")
      (node (ref "D264") (pin "1") (pinfunction "DO_1") (pintype "output"))
      (node (ref "D294") (pin "3") (pinfunction "DI_3") (pintype "input"))
    )
    (net (code "292") (name "Net-(D265-DO)") (class "Default")
      (node (ref "D265") (pin "1") (pinfunction "DO_1") (pintype "output"))
      (node (ref "D295") (pin "3") (pinfunction "DI_3") (pintype "input"))
    )
    (net (code "293") (name "Net-(D266-DO)") (class "Default")
      (node (ref "D266") (pin "1") (pinfunction "DO_1") (pintype "output"))
      (node (ref "D296") (pin "3") (pinfunction "DI_3") (pintype "input"))
    )
    (net (code "294") (name "Net-(D267-DO)") (class "Default")
      (node (ref "D267") (pin "1") (pinfunction "DO_1") (pintype "output"))
      (node (ref "D297") (pin "3") (pinfunction "DI_3") (pintype "input"))
    )
    (net (code "295") (name "Net-(D268-DO)") (class "Default")
      (node (ref "D268") (pin "1") (pinfunction "DO_1") (pintype "output"))
      (node (ref "D298") (pin "3") (pinfunction "DI_3") (pintype "input"))
    )
    (net (code "296") (name "Net-(D269-DO)") (class "Default")
      (node (ref "D269") (pin "1") (pinfunction "DO_1") (pintype "output"))
      (node (ref "D299") (pin "3") (pinfunction "DI_3") (pintype "input"))
    )
    (net (code "297") (name "Net-(D270-DO)") (class "Default")
      (node (ref "D270") (pin "1") (pinfunction "DO_1") (pintype "output"))
      (node (ref "D300") (pin "3") (pinfunction "DI_3") (pintype "input"))
    )
    (net (code "298") (name "Net-(D271-DO)") (class "Default")
      (node (ref "D271") (pin "1") (pinfunction "DO_1") (pintype "output"))
      (node (ref "D301") (pin "3") (pinfunction "DI_3") (pintype "input"))
    )
    (net (code "299") (name "Net-(D272-DO)") (class "Default")
      (node (ref "D272") (pin "1") (pinfunction "DO_1") (pintype "output"))
      (node (ref "D302") (pin "3") (pinfunction "DI_3") (pintype "input"))
    )
    (net (code "300") (name "Net-(D273-DO)") (class "Default")
      (node (ref "D273") (pin "1") (pinfunction "DO_1") (pintype "output"))
      (node (ref "D303") (pin "3") (pinfunction "DI_3") (pintype "input"))
    )
    (net (code "301") (name "Net-(D274-DO)") (class "Default")
      (node (ref "D274") (pin "1") (pinfunction "DO_1") (pintype "output"))
      (node (ref "D304") (pin "3") (pinfunction "DI_3") (pintype "input"))
    )
    (net (code "302") (name "Net-(D275-DO)") (class "Default")
      (node (ref "D275") (pin "1") (pinfunction "DO_1") (pintype "output"))
      (node (ref "D305") (pin "3") (pinfunction "DI_3") (pintype "input"))
    )
    (net (code "303") (name "Net-(D276-DO)") (class "Default")
      (node (ref "D276") (pin "1") (pinfunction "DO_1") (pintype "output"))
      (node (ref "D306") (pin "3") (pinfunction "DI_3") (pintype "input"))
    )
    (net (code "304") (name "Net-(D277-DO)") (class "Default")
      (node (ref "D277") (pin "1") (pinfunction "DO_1") (pintype "output"))
      (node (ref "D307") (pin "3") (pinfunction "DI_3") (pintype "input"))
    )
    (net (code "305") (name "Net-(D278-DO)") (class "Default")
      (node (ref "D278") (pin "1") (pinfunction "DO_1") (pintype "output"))
      (node (ref "D308") (pin "3") (pinfunction "DI_3") (pintype "input"))
    )
    (net (code "306") (name "Net-(D279-DO)") (class "Default")
      (node (ref "D279") (pin "1") (pinfunction "DO_1") (pintype "output"))
      (node (ref "D309") (pin "3") (pinfunction "DI_3") (pintype "input"))
    )
    (net (code "307") (name "Net-(D280-DO)") (class "Default")
      (node (ref "D280") (pin "1") (pinfunction "DO_1") (pintype "output"))
      (node (ref "D310") (pin "3") (pinfunction "DI_3") (pintype "input"))
    )
    (net (code "308") (name "Net-(D281-DO)") (class "Default")
      (node (ref "D281") (pin "1") (pinfunction "DO_1") (pintype "output"))
      (node (ref "D311") (pin "3") (pinfunction "DI_3") (pintype "input"))
    )
    (net (code "309") (name "Net-(D282-DO)") (class "Default")
      (node (ref "D282") (pin "1") (pinfunction "DO_1") (pintype "output"))
      (node (ref "D312") (pin "3") (pinfunction "DI_3") (pintype "input"))
    )
    (net (code "310") (name "Net-(D283-DO)") (class "Default")
      (node (ref "D283") (pin "1") (pinfunction "DO_1") (pintype "output"))
      (node (ref "D313") (pin "3") (pinfunction "DI_3") (pintype "input"))
    )
    (net (code "311") (name "Net-(D284-DO)") (class "Default")
      (node (ref "D284") (pin "1") (pinfunction "DO_1") (pintype "output"))
      (node (ref "D314") (pin "3") (pinfunction "DI_3") (pintype "input"))
    )
    (net (code "312") (name "Net-(D285-DO)") (class "Default")
      (node (ref "D285") (pin "1") (pinfunction "DO_1") (pintype "output"))
      (node (ref "D315") (pin "3") (pinfunction "DI_3") (pintype "input"))
    )
    (net (code "313") (name "Net-(D286-DO)") (class "Default")
      (node (ref "D286") (pin "1") (pinfunction "DO_1") (pintype "output"))
      (node (ref "D316") (pin "3") (pinfunction "DI_3") (pintype "input"))
    )
    (net (code "314") (name "Net-(D287-DO)") (class "Default")
      (node (ref "D287") (pin "1") (pinfunction "DO_1") (pintype "output"))
      (node (ref "D317") (pin "3") (pinfunction "DI_3") (pintype "input"))
    )
    (net (code "315") (name "Net-(D288-DO)") (class "Default")
      (node (ref "D288") (pin "1") (pinfunction "DO_1") (pintype "output"))
      (node (ref "D318") (pin "3") (pinfunction "DI_3") (pintype "input"))
    )
    (net (code "316") (name "Net-(D289-DO)") (class "Default")
      (node (ref "D289") (pin "1") (pinfunction "DO_1") (pintype "output"))
      (node (ref "D319") (pin "3") (pinfunction "DI_3") (pintype "input"))
    )
    (net (code "317") (name "Net-(D290-DO)") (class "Default")
      (node (ref "D290") (pin "1") (pinfunction "DO_1") (pintype "output"))
      (node (ref "D320") (pin "3") (pinfunction "DI_3") (pintype "input"))
    )
    (net (code "318") (name "Net-(D291-DO)") (class "Default")
      (node (ref "D291") (pin "1") (pinfunction "DO_1") (pintype "output"))
      (node (ref "D321") (pin "3") (pinfunction "DI_3") (pintype "input"))
    )
    (net (code "319") (name "Net-(D292-DO)") (class "Default")
      (node (ref "D292") (pin "1") (pinfunction "DO_1") (pintype "output"))
      (node (ref "D322") (pin "3") (pinfunction "DI_3") (pintype "input"))
    )
    (net (code "320") (name "Net-(D293-DO)") (class "Default")
      (node (ref "D293") (pin "1") (pinfunction "DO_1") (pintype "output"))
      (node (ref "D323") (pin "3") (pinfunction "DI_3") (pintype "input"))
    )
    (net (code "321") (name "Net-(D294-DO)") (class "Default")
      (node (ref "D294") (pin "1") (pinfunction "DO_1") (pintype "output"))
      (node (ref "D324") (pin "3") (pinfunction "DI_3") (pintype "input"))
    )
    (net (code "322") (name "Net-(D295-DO)") (class "Default")
      (node (ref "D295") (pin "1") (pinfunction "DO_1") (pintype "output"))
      (node (ref "D325") (pin "3") (pinfunction "DI_3") (pintype "input"))
    )
    (net (code "323") (name "Net-(D296-DO)") (class "Default")
      (node (ref "D296") (pin "1") (pinfunction "DO_1") (pintype "output"))
      (node (ref "D326") (pin "3") (pinfunction "DI_3") (pintype "input"))
    )
    (net (code "324") (name "Net-(D297-DO)") (class "Default")
      (node (ref "D297") (pin "1") (pinfunction "DO_1") (pintype "output"))
      (node (ref "D327") (pin "3") (pinfunction "DI_3") (pintype "input"))
    )
    (net (code "325") (name "Net-(D298-DO)") (class "Default")
      (node (ref "D298") (pin "1") (pinfunction "DO_1") (pintype "output"))
      (node (ref "D328") (pin "3") (pinfunction "DI_3") (pintype "input"))
    )
    (net (code "326") (name "Net-(D299-DO)") (class "Default")
      (node (ref "D299") (pin "1") (pinfunction "DO_1") (pintype "output"))
      (node (ref "D329") (pin "3") (pinfunction "DI_3") (pintype "input"))
    )
    (net (code "327") (name "Net-(D300-DO)") (class "Default")
      (node (ref "D300") (pin "1") (pinfunction "DO_1") (pintype "output"))
      (node (ref "D330") (pin "3") (pinfunction "DI_3") (pintype "input"))
    )
    (net (code "328") (name "Net-(D301-DO)") (class "Default")
      (node (ref "D301") (pin "1") (pinfunction "DO_1") (pintype "output"))
      (node (ref "D331") (pin "3") (pinfunction "DI_3") (pintype "input"))
    )
    (net (code "329") (name "Net-(D302-DO)") (class "Default")
      (node (ref "D302") (pin "1") (pinfunction "DO_1") (pintype "output"))
      (node (ref "D332") (pin "3") (pinfunction "DI_3") (pintype "input"))
    )
    (net (code "330") (name "Net-(D303-DO)") (class "Default")
      (node (ref "D303") (pin "1") (pinfunction "DO_1") (pintype "output"))
      (node (ref "D333") (pin "3") (pinfunction "DI_3") (pintype "input"))
    )
    (net (code "331") (name "Net-(D304-DO)") (class "Default")
      (node (ref "D304") (pin "1") (pinfunction "DO_1") (pintype "output"))
      (node (ref "D334") (pin "3") (pinfunction "DI_3") (pintype "input"))
    )
    (net (code "332") (name "Net-(D305-DO)") (class "Default")
      (node (ref "D305") (pin "1") (pinfunction "DO_1") (pintype "output"))
      (node (ref "D335") (pin "3") (pinfunction "DI_3") (pintype "input"))
    )
    (net (code "333") (name "Net-(D306-DO)") (class "Default")
      (node (ref "D306") (pin "1") (pinfunction "DO_1") (pintype "output"))
      (node (ref "D336") (pin "3") (pinfunction "DI_3") (pintype "input"))
    )
    (net (code "334") (name "Net-(D307-DO)") (class "Default")
      (node (ref "D307") (pin "1") (pinfunction "DO_1") (pintype "output"))
      (node (ref "D337") (pin "3") (pinfunction "DI_3") (pintype "input"))
    )
    (net (code "335") (name "Net-(D308-DO)") (class "Default")
      (node (ref "D308") (pin "1") (pinfunction "DO_1") (pintype "output"))
      (node (ref "D338") (pin "3") (pinfunction "DI_3") (pintype "input"))
    )
    (net (code "336") (name "Net-(D309-DO)") (class "Default")
      (node (ref "D309") (pin "1") (pinfunction "DO_1") (pintype "output"))
      (node (ref "D339") (pin "3") (pinfunction "DI_3") (pintype "input"))
    )
    (net (code "337") (name "Net-(D310-DO)") (class "Default")
      (node (ref "D310") (pin "1") (pinfunction "DO_1") (pintype "output"))
      (node (ref "D340") (pin "3") (pinfunction "DI_3") (pintype "input"))
    )
    (net (code "338") (name "Net-(D311-DO)") (class "Default")
      (node (ref "D311") (pin "1") (pinfunction "DO_1") (pintype "output"))
      (node (ref "D341") (pin "3") (pinfunction "DI_3") (pintype "input"))
    )
    (net (code "339") (name "Net-(D312-DO)") (class "Default")
      (node (ref "D312") (pin "1") (pinfunction "DO_1") (pintype "output"))
      (node (ref "D342") (pin "3") (pinfunction "DI_3") (pintype "input"))
    )
    (net (code "340") (name "Net-(D313-DO)") (class "Default")
      (node (ref "D313") (pin "1") (pinfunction "DO_1") (pintype "output"))
      (node (ref "D343") (pin "3") (pinfunction "DI_3") (pintype "input"))
    )
    (net (code "341") (name "Net-(D314-DO)") (class "Default")
      (node (ref "D314") (pin "1") (pinfunction "DO_1") (pintype "output"))
      (node (ref "D344") (pin "3") (pinfunction "DI_3") (pintype "input"))
    )
    (net (code "342") (name "Net-(D315-DO)") (class "Default")
      (node (ref "D315") (pin "1") (pinfunction "DO_1") (pintype "output"))
      (node (ref "D345") (pin "3") (pinfunction "DI_3") (pintype "input"))
    )
    (net (code "343") (name "Net-(D316-DO)") (class "Default")
      (node (ref "D316") (pin "1") (pinfunction "DO_1") (pintype "output"))
      (node (ref "D346") (pin "3") (pinfunction "DI_3") (pintype "input"))
    )
    (net (code "344") (name "Net-(D317-DO)") (class "Default")
      (node (ref "D317") (pin "1") (pinfunction "DO_1") (pintype "output"))
      (node (ref "D347") (pin "3") (pinfunction "DI_3") (pintype "input"))
    )
    (net (code "345") (name "Net-(D318-DO)") (class "Default")
      (node (ref "D318") (pin "1") (pinfunction "DO_1") (pintype "output"))
      (node (ref "D348") (pin "3") (pinfunction "DI_3") (pintype "input"))
    )
    (net (code "346") (name "Net-(D319-DO)") (class "Default")
      (node (ref "D319") (pin "1") (pinfunction "DO_1") (pintype "output"))
      (node (ref "D349") (pin "3") (pinfunction "DI_3") (pintype "input"))
    )
    (net (code "347") (name "Net-(D320-DO)") (class "Default")
      (node (ref "D320") (pin "1") (pinfunction "DO_1") (pintype "output"))
      (node (ref "D350") (pin "3") (pinfunction "DI_3") (pintype "input"))
    )
    (net (code "348") (name "Net-(D321-DO)") (class "Default")
      (node (ref "D321") (pin "1") (pinfunction "DO_1") (pintype "output"))
      (node (ref "D351") (pin "3") (pinfunction "DI_3") (pintype "input"))
    )
    (net (code "349") (name "Net-(D322-DO)") (class "Default")
      (node (ref "D322") (pin "1") (pinfunction "DO_1") (pintype "output"))
      (node (ref "D352") (pin "3") (pinfunction "DI_3") (pintype "input"))
    )
    (net (code "350") (name "Net-(D323-DO)") (class "Default")
      (node (ref "D323") (pin "1") (pinfunction "DO_1") (pintype "output"))
      (node (ref "D353") (pin "3") (pinfunction "DI_3") (pintype "input"))
    )
    (net (code "351") (name "Net-(D324-DO)") (class "Default")
      (node (ref "D324") (pin "1") (pinfunction "DO_1") (pintype "output"))
      (node (ref "D354") (pin "3") (pinfunction "DI_3") (pintype "input"))
    )
    (net (code "352") (name "Net-(D325-DO)") (class "Default")
      (node (ref "D325") (pin "1") (pinfunction "DO_1") (pintype "output"))
      (node (ref "D355") (pin "3") (pinfunction "DI_3") (pintype "input"))
    )
    (net (code "353") (name "Net-(D326-DO)") (class "Default")
      (node (ref "D326") (pin "1") (pinfunction "DO_1") (pintype "output"))
      (node (ref "D356") (pin "3") (pinfunction "DI_3") (pintype "input"))
    )
    (net (code "354") (name "Net-(D327-DO)") (class "Default")
      (node (ref "D327") (pin "1") (pinfunction "DO_1") (pintype "output"))
      (node (ref "D357") (pin "3") (pinfunction "DI_3") (pintype "input"))
    )
    (net (code "355") (name "Net-(D328-DO)") (class "Default")
      (node (ref "D328") (pin "1") (pinfunction "DO_1") (pintype "output"))
      (node (ref "D358") (pin "3") (pinfunction "DI_3") (pintype "input"))
    )
    (net (code "356") (name "Net-(D329-DO)") (class "Default")
      (node (ref "D329") (pin "1") (pinfunction "DO_1") (pintype "output"))
      (node (ref "D359") (pin "3") (pinfunction "DI_3") (pintype "input"))
    )
    (net (code "357") (name "Net-(D359-DO)") (class "Default")
      (node (ref "D359") (pin "1") (pinfunction "DO_1") (pintype "output"))
      (node (ref "D360") (pin "3") (pinfunction "DI_3") (pintype "input"))
    )
    (net (code "358") (name "Net-(D360-DO)") (class "Default")
      (node (ref "D360") (pin "1") (pinfunction "DO_1") (pintype "output"))
      (node (ref "D361") (pin "3") (pinfunction "DI_3") (pintype "input"))
    )
    (net (code "359") (name "Net-(D361-DO)") (class "Default")
      (node (ref "D361") (pin "1") (pinfunction "DO_1") (pintype "output"))
      (node (ref "D362") (pin "3") (pinfunction "DI_3") (pintype "input"))
    )
    (net (code "360") (name "Net-(D362-DO)") (class "Default")
      (node (ref "D362") (pin "1") (pinfunction "DO_1") (pintype "output"))
      (node (ref "D363") (pin "3") (pinfunction "DI_3") (pintype "input"))
    )
    (net (code "361") (name "Net-(D363-DO)") (class "Default")
      (node (ref "D363") (pin "1") (pinfunction "DO_1") (pintype "output"))
      (node (ref "D364") (pin "3") (pinfunction "DI_3") (pintype "input"))
    )
    (net (code "362") (name "Net-(D364-DO)") (class "Default")
      (node (ref "D364") (pin "1") (pinfunction "DO_1") (pintype "output"))
      (node (ref "D389") (pin "3") (pinfunction "DI_3") (pintype "input"))
    )
    (net (code "363") (name "Net-(D365-DO)") (class "Default")
      (node (ref "D365") (pin "1") (pinfunction "DO_1") (pintype "output"))
      (node (ref "D366") (pin "3") (pinfunction "DI_3") (pintype "input"))
    )
    (net (code "364") (name "Net-(D366-DO)") (class "Default")
      (node (ref "D366") (pin "1") (pinfunction "DO_1") (pintype "output"))
      (node (ref "D367") (pin "3") (pinfunction "DI_3") (pintype "input"))
    )
    (net (code "365") (name "Net-(D367-DO)") (class "Default")
      (node (ref "D367") (pin "1") (pinfunction "DO_1") (pintype "output"))
      (node (ref "D368") (pin "3") (pinfunction "DI_3") (pintype "input"))
    )
    (net (code "366") (name "Net-(D368-DO)") (class "Default")
      (node (ref "D368") (pin "1") (pinfunction "DO_1") (pintype "output"))
      (node (ref "D369") (pin "3") (pinfunction "DI_3") (pintype "input"))
    )
    (net (code "367") (name "Net-(D369-DO)") (class "Default")
      (node (ref "D369") (pin "1") (pinfunction "DO_1") (pintype "output"))
      (node (ref "D394") (pin "3") (pinfunction "DI_3") (pintype "input"))
    )
    (net (code "368") (name "Net-(D370-DO)") (class "Default")
      (node (ref "D370") (pin "1") (pinfunction "DO_1") (pintype "output"))
      (node (ref "D371") (pin "3") (pinfunction "DI_3") (pintype "input"))
    )
    (net (code "369") (name "Net-(D371-DO)") (class "Default")
      (node (ref "D371") (pin "1") (pinfunction "DO_1") (pintype "output"))
      (node (ref "D372") (pin "3") (pinfunction "DI_3") (pintype "input"))
    )
    (net (code "370") (name "Net-(D372-DO)") (class "Default")
      (node (ref "D372") (pin "1") (pinfunction "DO_1") (pintype "output"))
      (node (ref "D373") (pin "3") (pinfunction "DI_3") (pintype "input"))
    )
    (net (code "371") (name "Net-(D373-DO)") (class "Default")
      (node (ref "D373") (pin "1") (pinfunction "DO_1") (pintype "output"))
      (node (ref "D374") (pin "3") (pinfunction "DI_3") (pintype "input"))
    )
    (net (code "372") (name "Net-(D374-DO)") (class "Default")
      (node (ref "D374") (pin "1") (pinfunction "DO_1") (pintype "output"))
      (node (ref "D399") (pin "3") (pinfunction "DI_3") (pintype "input"))
    )
    (net (code "373") (name "Net-(D375-DO)") (class "Default")
      (node (ref "D375") (pin "1") (pinfunction "DO_1") (pintype "output"))
      (node (ref "D376") (pin "3") (pinfunction "DI_3") (pintype "input"))
    )
    (net (code "374") (name "Net-(D376-DO)") (class "Default")
      (node (ref "D376") (pin "1") (pinfunction "DO_1") (pintype "output"))
      (node (ref "D377") (pin "3") (pinfunction "DI_3") (pintype "input"))
    )
    (net (code "375") (name "Net-(D377-DO)") (class "Default")
      (node (ref "D377") (pin "1") (pinfunction "DO_1") (pintype "output"))
      (node (ref "D378") (pin "3") (pinfunction "DI_3") (pintype "input"))
    )
    (net (code "376") (name "Net-(D378-DO)") (class "Default")
      (node (ref "D378") (pin "1") (pinfunction "DO_1") (pintype "output"))
      (node (ref "D379") (pin "3") (pinfunction "DI_3") (pintype "input"))
    )
    (net (code "377") (name "Net-(D379-DO)") (class "Default")
      (node (ref "D379") (pin "1") (pinfunction "DO_1") (pintype "output"))
      (node (ref "D404") (pin "3") (pinfunction "DI_3") (pintype "input"))
    )
    (net (code "378") (name "Net-(D380-DO)") (class "Default")
      (node (ref "D380") (pin "1") (pinfunction "DO_1") (pintype "output"))
      (node (ref "D381") (pin "3") (pinfunction "DI_3") (pintype "input"))
    )
    (net (code "379") (name "Net-(D381-DO)") (class "Default")
      (node (ref "D381") (pin "1") (pinfunction "DO_1") (pintype "output"))
      (node (ref "D382") (pin "3") (pinfunction "DI_3") (pintype "input"))
    )
    (net (code "380") (name "Net-(D382-DO)") (class "Default")
      (node (ref "D382") (pin "1") (pinfunction "DO_1") (pintype "output"))
      (node (ref "D383") (pin "3") (pinfunction "DI_3") (pintype "input"))
    )
    (net (code "381") (name "Net-(D383-DO)") (class "Default")
      (node (ref "D383") (pin "1") (pinfunction "DO_1") (pintype "output"))
      (node (ref "D384") (pin "3") (pinfunction "DI_3") (pintype "input"))
    )
    (net (code "382") (name "Net-(D384-DO)") (class "Default")
      (node (ref "D384") (pin "1") (pinfunction "DO_1") (pintype "output"))
      (node (ref "D409") (pin "3") (pinfunction "DI_3") (pintype "input"))
    )
    (net (code "383") (name "Net-(D385-DI)") (class "Default")
      (node (ref "D385") (pin "3") (pinfunction "DI_3") (pintype "input"))
      (node (ref "D386") (pin "1") (pinfunction "DO_1") (pintype "output"))
    )
    (net (code "384") (name "Net-(D386-DI)") (class "Default")
      (node (ref "D386") (pin "3") (pinfunction "DI_3") (pintype "input"))
      (node (ref "D387") (pin "1") (pinfunction "DO_1") (pintype "output"))
    )
    (net (code "385") (name "Net-(D387-DI)") (class "Default")
      (node (ref "D387") (pin "3") (pinfunction "DI_3") (pintype "input"))
      (node (ref "D388") (pin "1") (pinfunction "DO_1") (pintype "output"))
    )
    (net (code "386") (name "Net-(D388-DI)") (class "Default")
      (node (ref "D388") (pin "3") (pinfunction "DI_3") (pintype "input"))
      (node (ref "D389") (pin "1") (pinfunction "DO_1") (pintype "output"))
    )
    (net (code "387") (name "Net-(D390-DI)") (class "Default")
      (node (ref "D390") (pin "3") (pinfunction "DI_3") (pintype "input"))
      (node (ref "D391") (pin "1") (pinfunction "DO_1") (pintype "output"))
    )
    (net (code "388") (name "Net-(D391-DI)") (class "Default")
      (node (ref "D391") (pin "3") (pinfunction "DI_3") (pintype "input"))
      (node (ref "D392") (pin "1") (pinfunction "DO_1") (pintype "output"))
    )
    (net (code "389") (name "Net-(D392-DI)") (class "Default")
      (node (ref "D392") (pin "3") (pinfunction "DI_3") (pintype "input"))
      (node (ref "D393") (pin "1") (pinfunction "DO_1") (pintype "output"))
    )
    (net (code "390") (name "Net-(D393-DI)") (class "Default")
      (node (ref "D393") (pin "3") (pinfunction "DI_3") (pintype "input"))
      (node (ref "D394") (pin "1") (pinfunction "DO_1") (pintype "output"))
    )
    (net (code "391") (name "Net-(D395-DI)") (class "Default")
      (node (ref "D395") (pin "3") (pinfunction "DI_3") (pintype "input"))
      (node (ref "D396") (pin "1") (pinfunction "DO_1") (pintype "output"))
    )
    (net (code "392") (name "Net-(D396-DI)") (class "Default")
      (node (ref "D396") (pin "3") (pinfunction "DI_3") (pintype "input"))
      (node (ref "D397") (pin "1") (pinfunction "DO_1") (pintype "output"))
    )
    (net (code "393") (name "Net-(D397-DI)") (class "Default")
      (node (ref "D397") (pin "3") (pinfunction "DI_3") (pintype "input"))
      (node (ref "D398") (pin "1") (pinfunction "DO_1") (pintype "output"))
    )
    (net (code "394") (name "Net-(D398-DI)") (class "Default")
      (node (ref "D398") (pin "3") (pinfunction "DI_3") (pintype "input"))
      (node (ref "D399") (pin "1") (pinfunction "DO_1") (pintype "output"))
    )
    (net (code "395") (name "Net-(D400-DI)") (class "Default")
      (node (ref "D400") (pin "3") (pinfunction "DI_3") (pintype "input"))
      (node (ref "D401") (pin "1") (pinfunction "DO_1") (pintype "output"))
    )
    (net (code "396") (name "Net-(D401-DI)") (class "Default")
      (node (ref "D401") (pin "3") (pinfunction "DI_3") (pintype "input"))
      (node (ref "D402") (pin "1") (pinfunction "DO_1") (pintype "output"))
    )
    (net (code "397") (name "Net-(D402-DI)") (class "Default")
      (node (ref "D402") (pin "3") (pinfunction "DI_3") (pintype "input"))
      (node (ref "D403") (pin "1") (pinfunction "DO_1") (pintype "output"))
    )
    (net (code "398") (name "Net-(D403-DI)") (class "Default")
      (node (ref "D403") (pin "3") (pinfunction "DI_3") (pintype "input"))
      (node (ref "D404") (pin "1") (pinfunction "DO_1") (pintype "output"))
    )
    (net (code "399") (name "Net-(D405-DI)") (class "Default")
      (node (ref "D405") (pin "3") (pinfunction "DI_3") (pintype "input"))
      (node (ref "D406") (pin "1") (pinfunction "DO_1") (pintype "output"))
    )
    (net (code "400") (name "Net-(D406-DI)") (class "Default")
      (node (ref "D406") (pin "3") (pinfunction "DI_3") (pintype "input"))
      (node (ref "D407") (pin "1") (pinfunction "DO_1") (pintype "output"))
    )
    (net (code "401") (name "Net-(D407-DI)") (class "Default")
      (node (ref "D407") (pin "3") (pinfunction "DI_3") (pintype "input"))
      (node (ref "D408") (pin "1") (pinfunction "DO_1") (pintype "output"))
    )
    (net (code "402") (name "Net-(D408-DI)") (class "Default")
      (node (ref "D408") (pin "3") (pinfunction "DI_3") (pintype "input"))
      (node (ref "D409") (pin "1") (pinfunction "DO_1") (pintype "output"))
    )
    (net (code "403") (name "unconnected-(D405-DO-Pad1)") (class "Default")
      (node (ref "D405") (pin "1") (pinfunction "DO_1") (pintype "output+no_connect"))
    )
  )
)
